# STM32F446_front_pane_-_v3.net
KiCad netlist of a schematic drawn in EAGLE
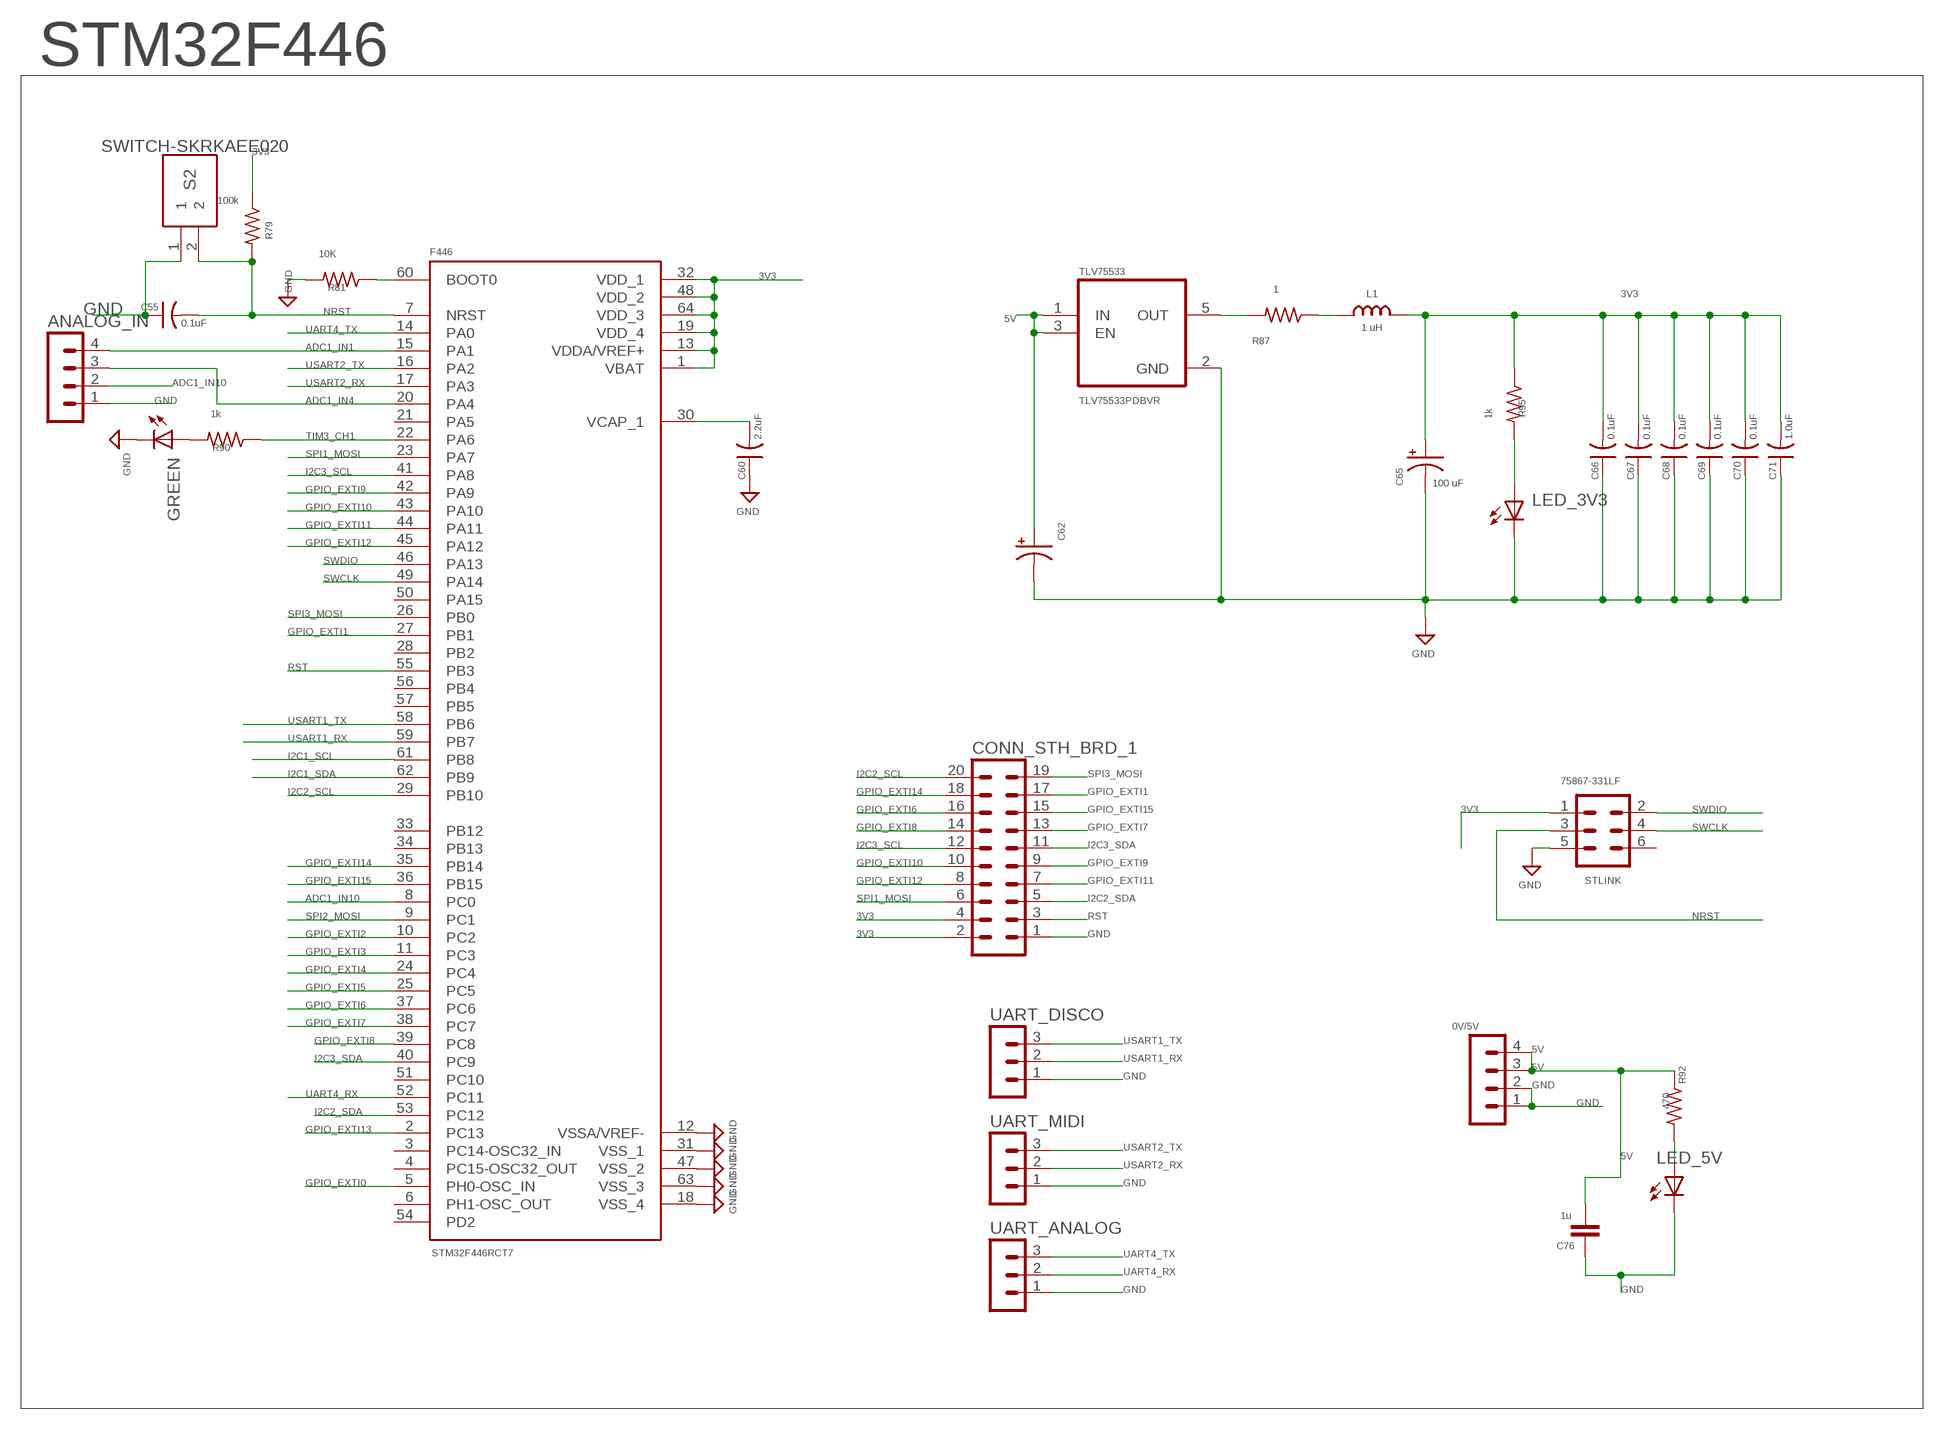
[diagram p0: schematic, sheet 1]
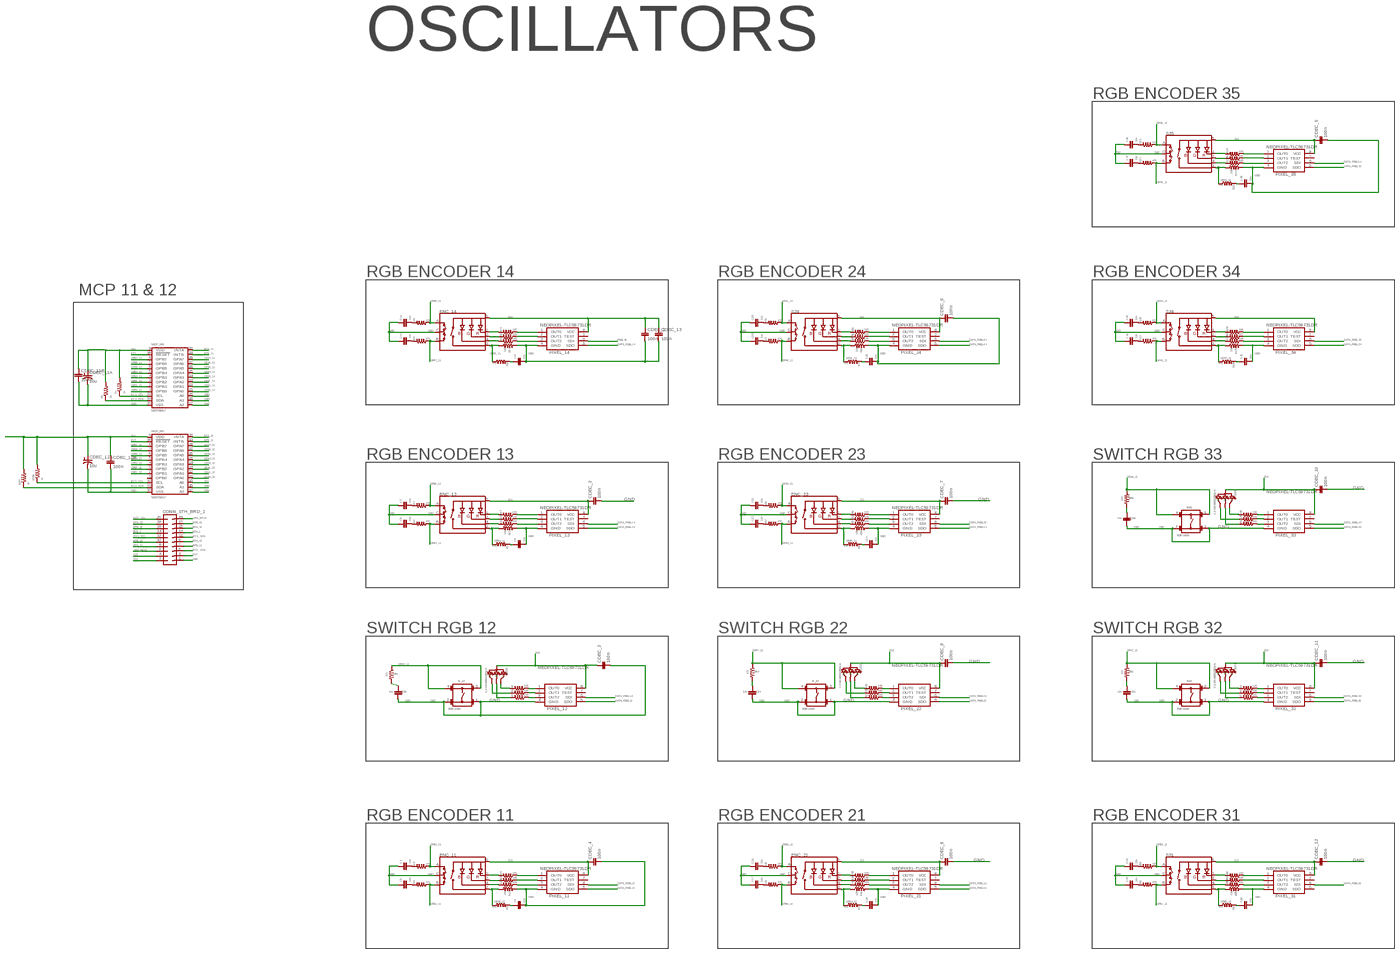
[diagram p1: schematic, sheet 2, overview]
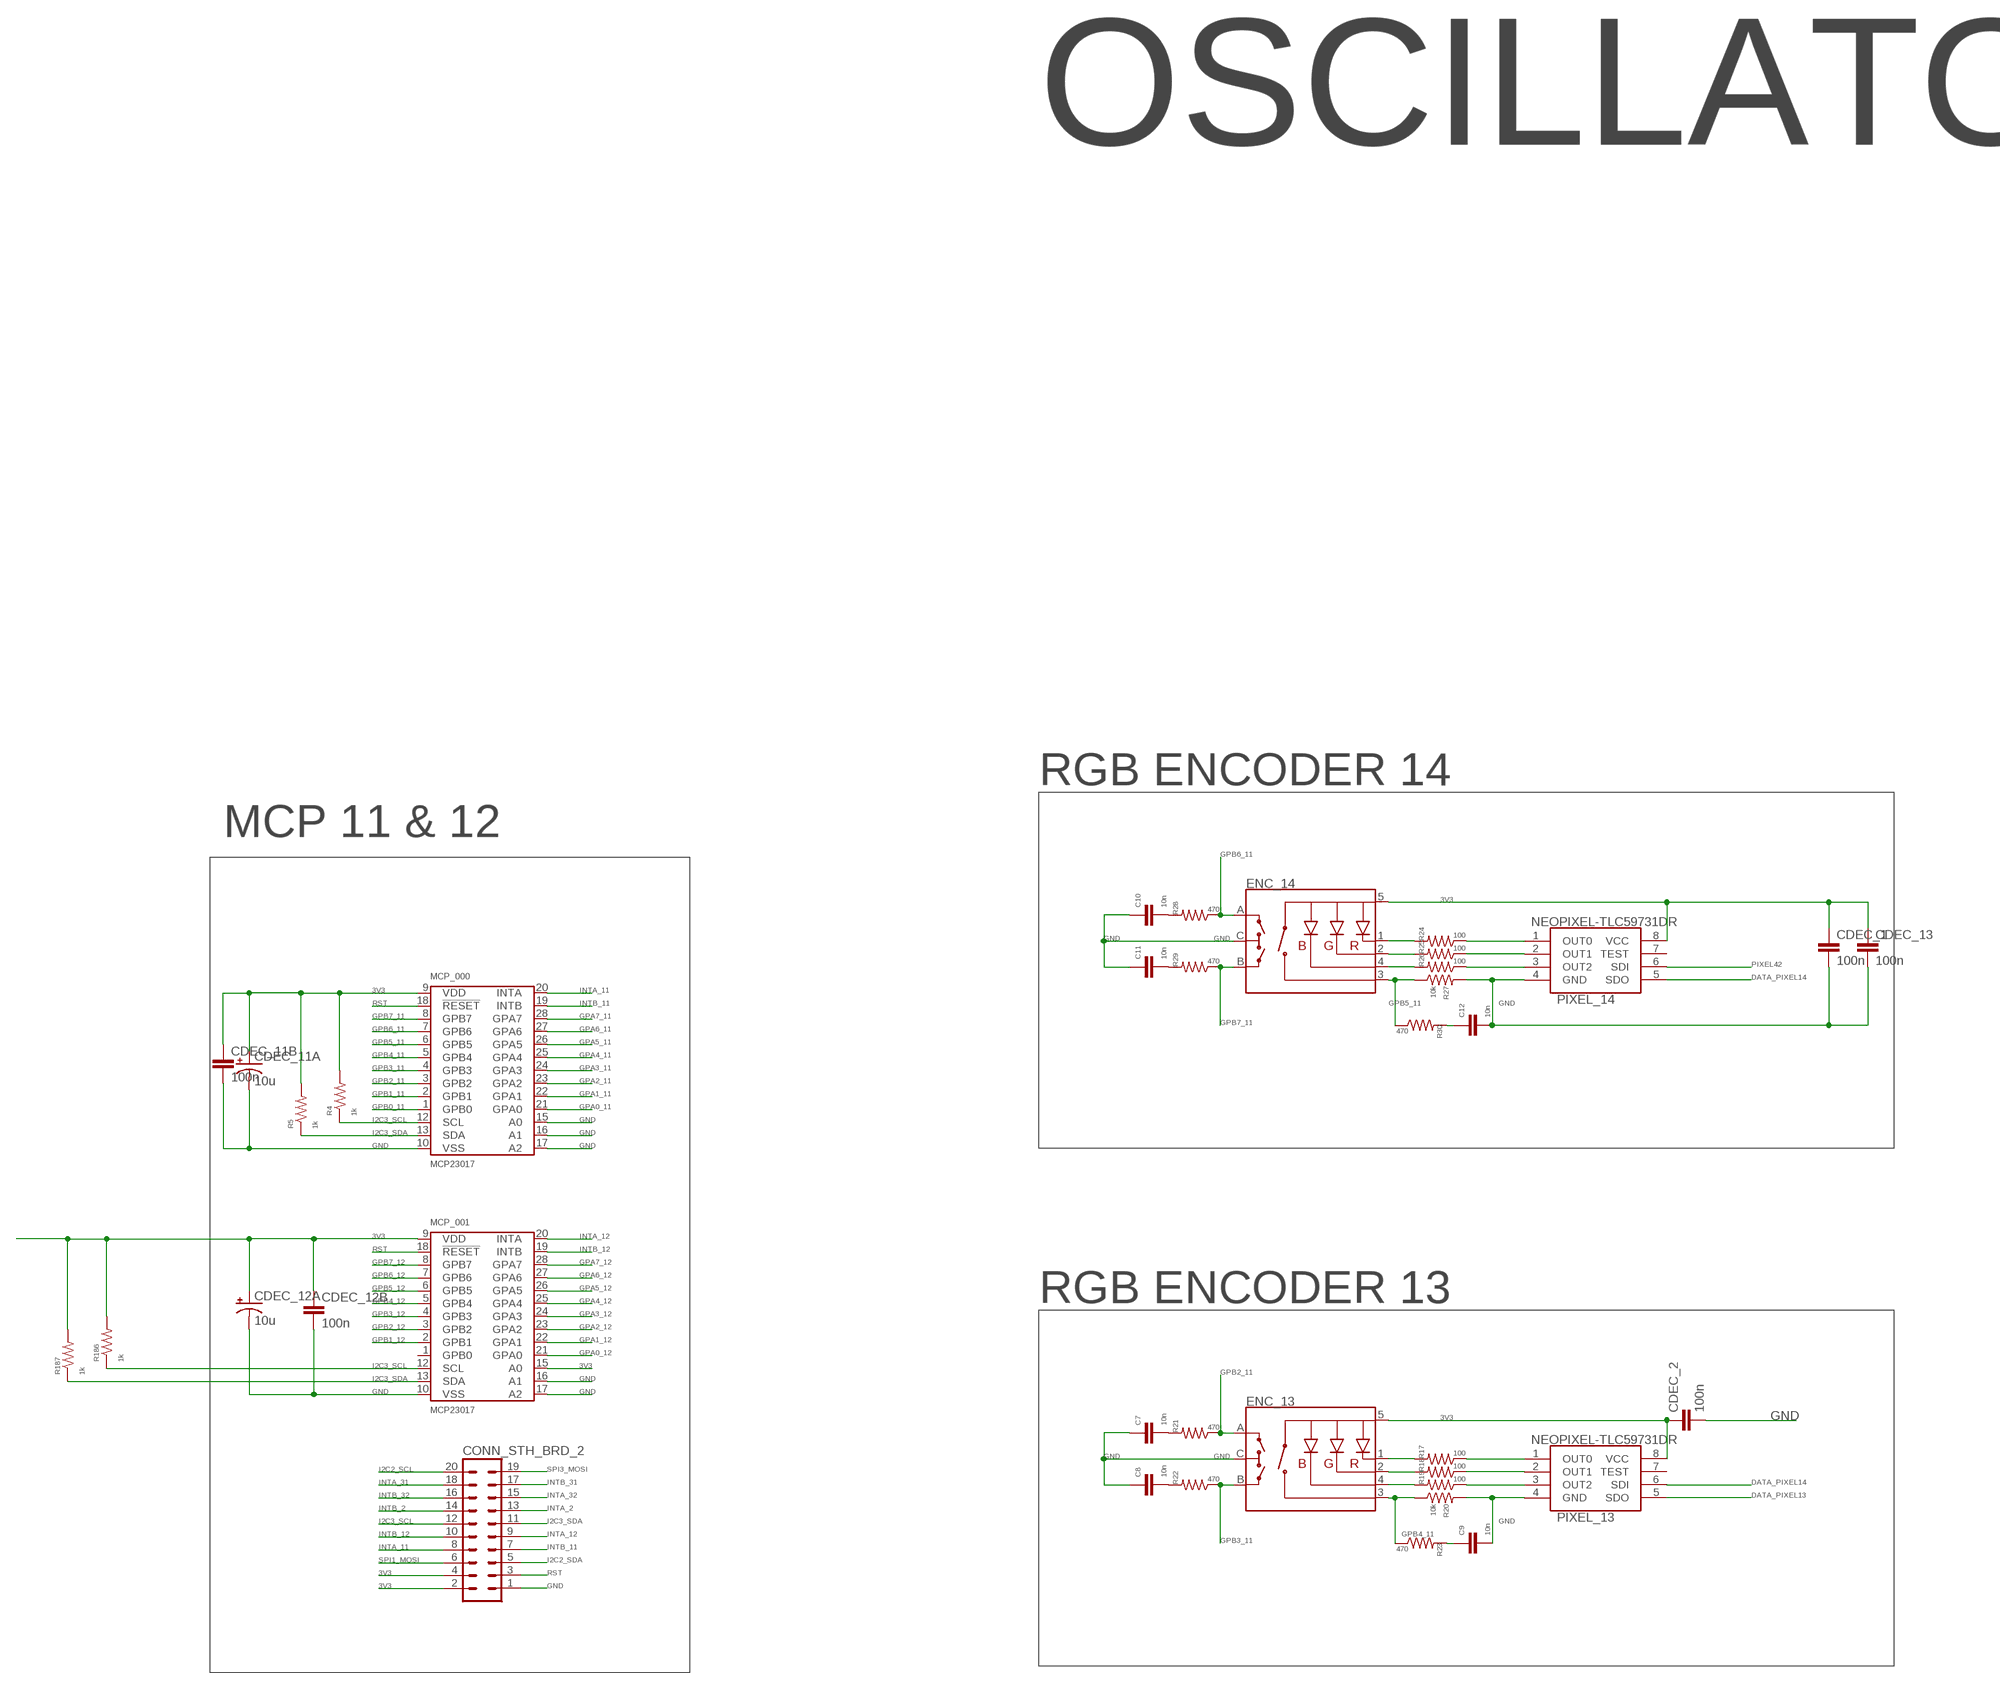
[diagram p2: schematic, sheet 2, part 1 of 4]
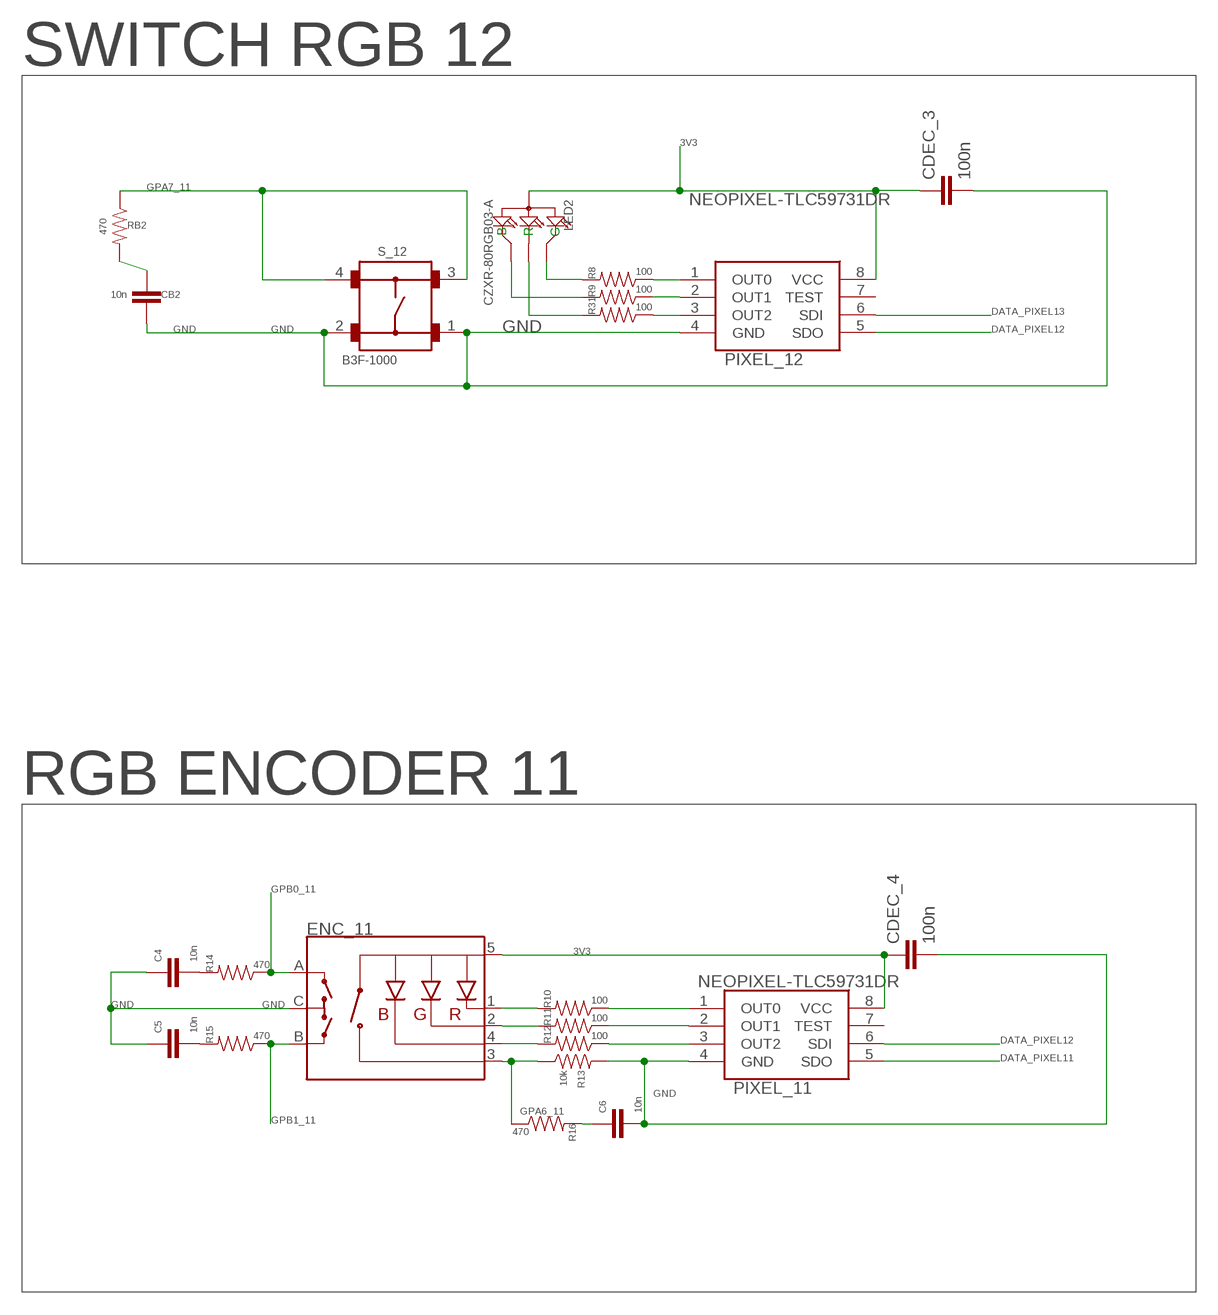
[diagram p3: schematic, sheet 2, part 2 of 4]
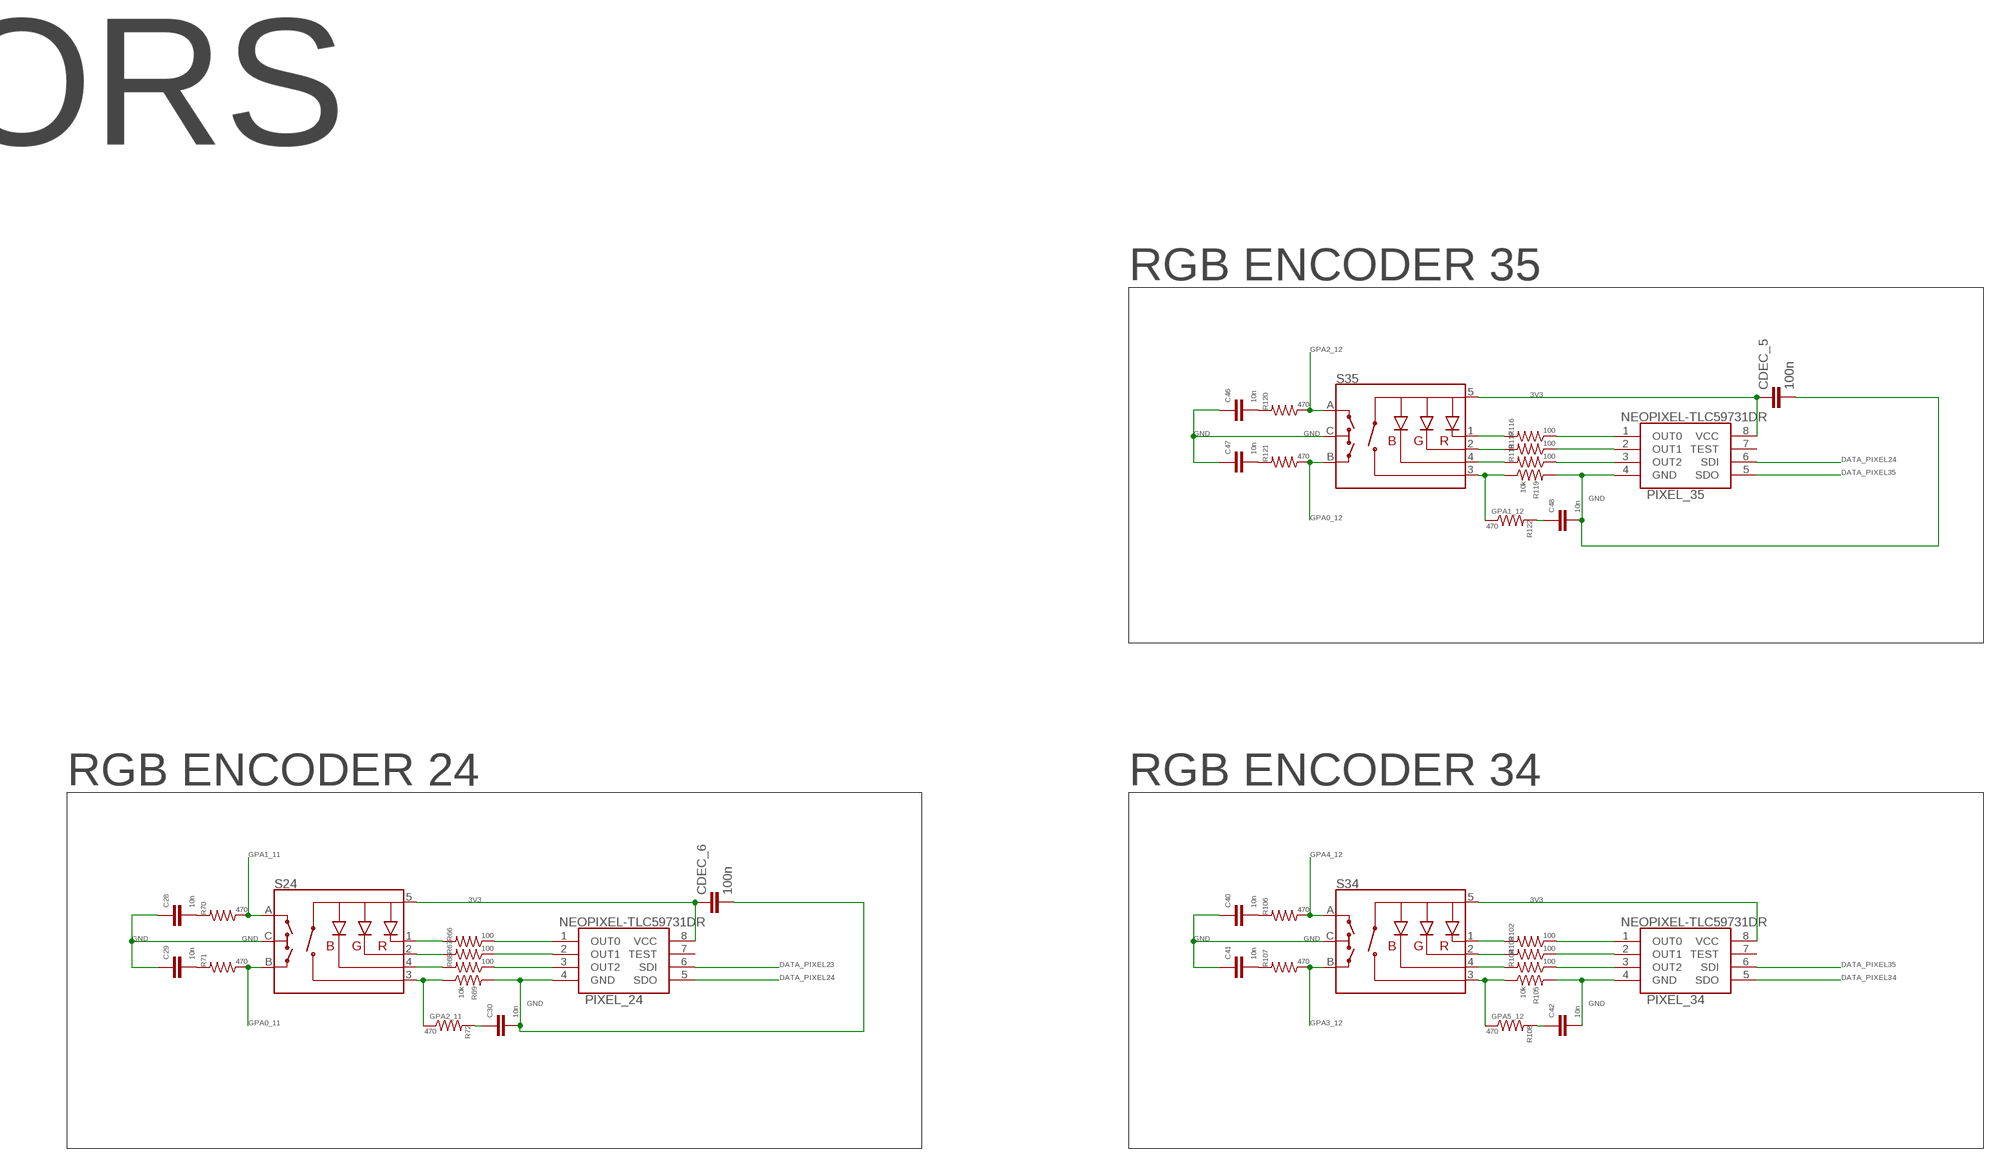
[diagram p4: schematic, sheet 2, part 3 of 4]
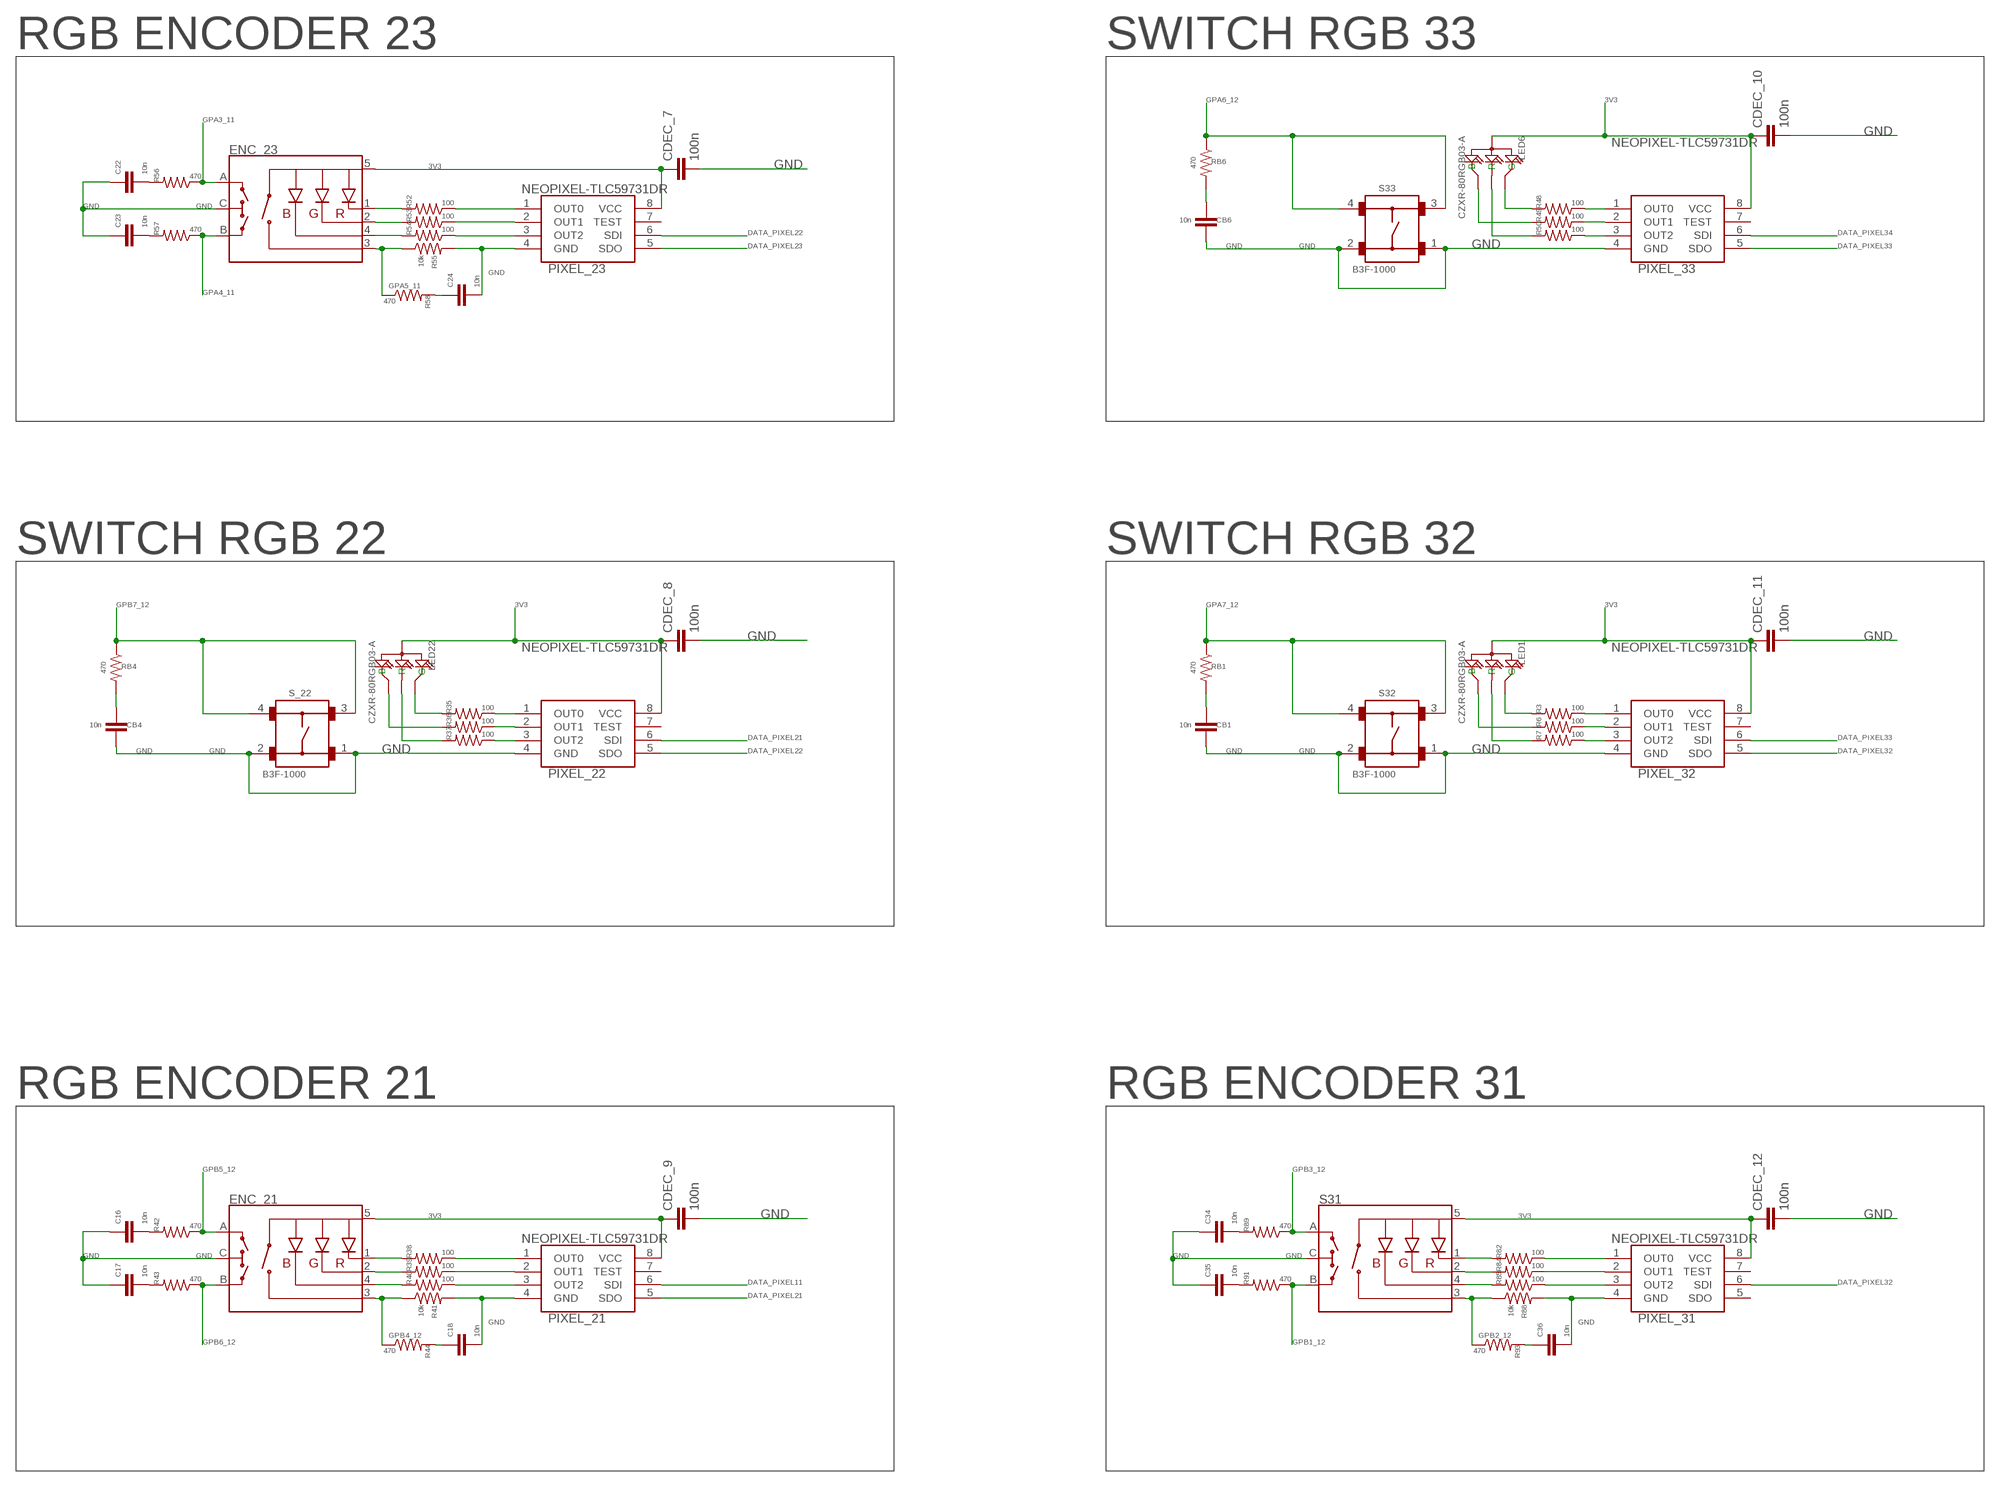
[diagram p5: schematic, sheet 2, part 4 of 4]
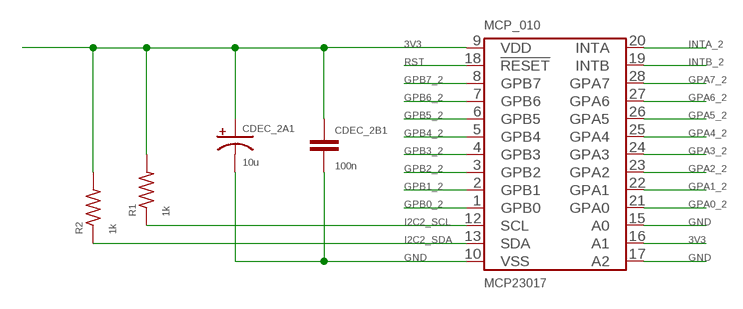
[diagram p6: schematic, sheet 3, part 1 of 2]
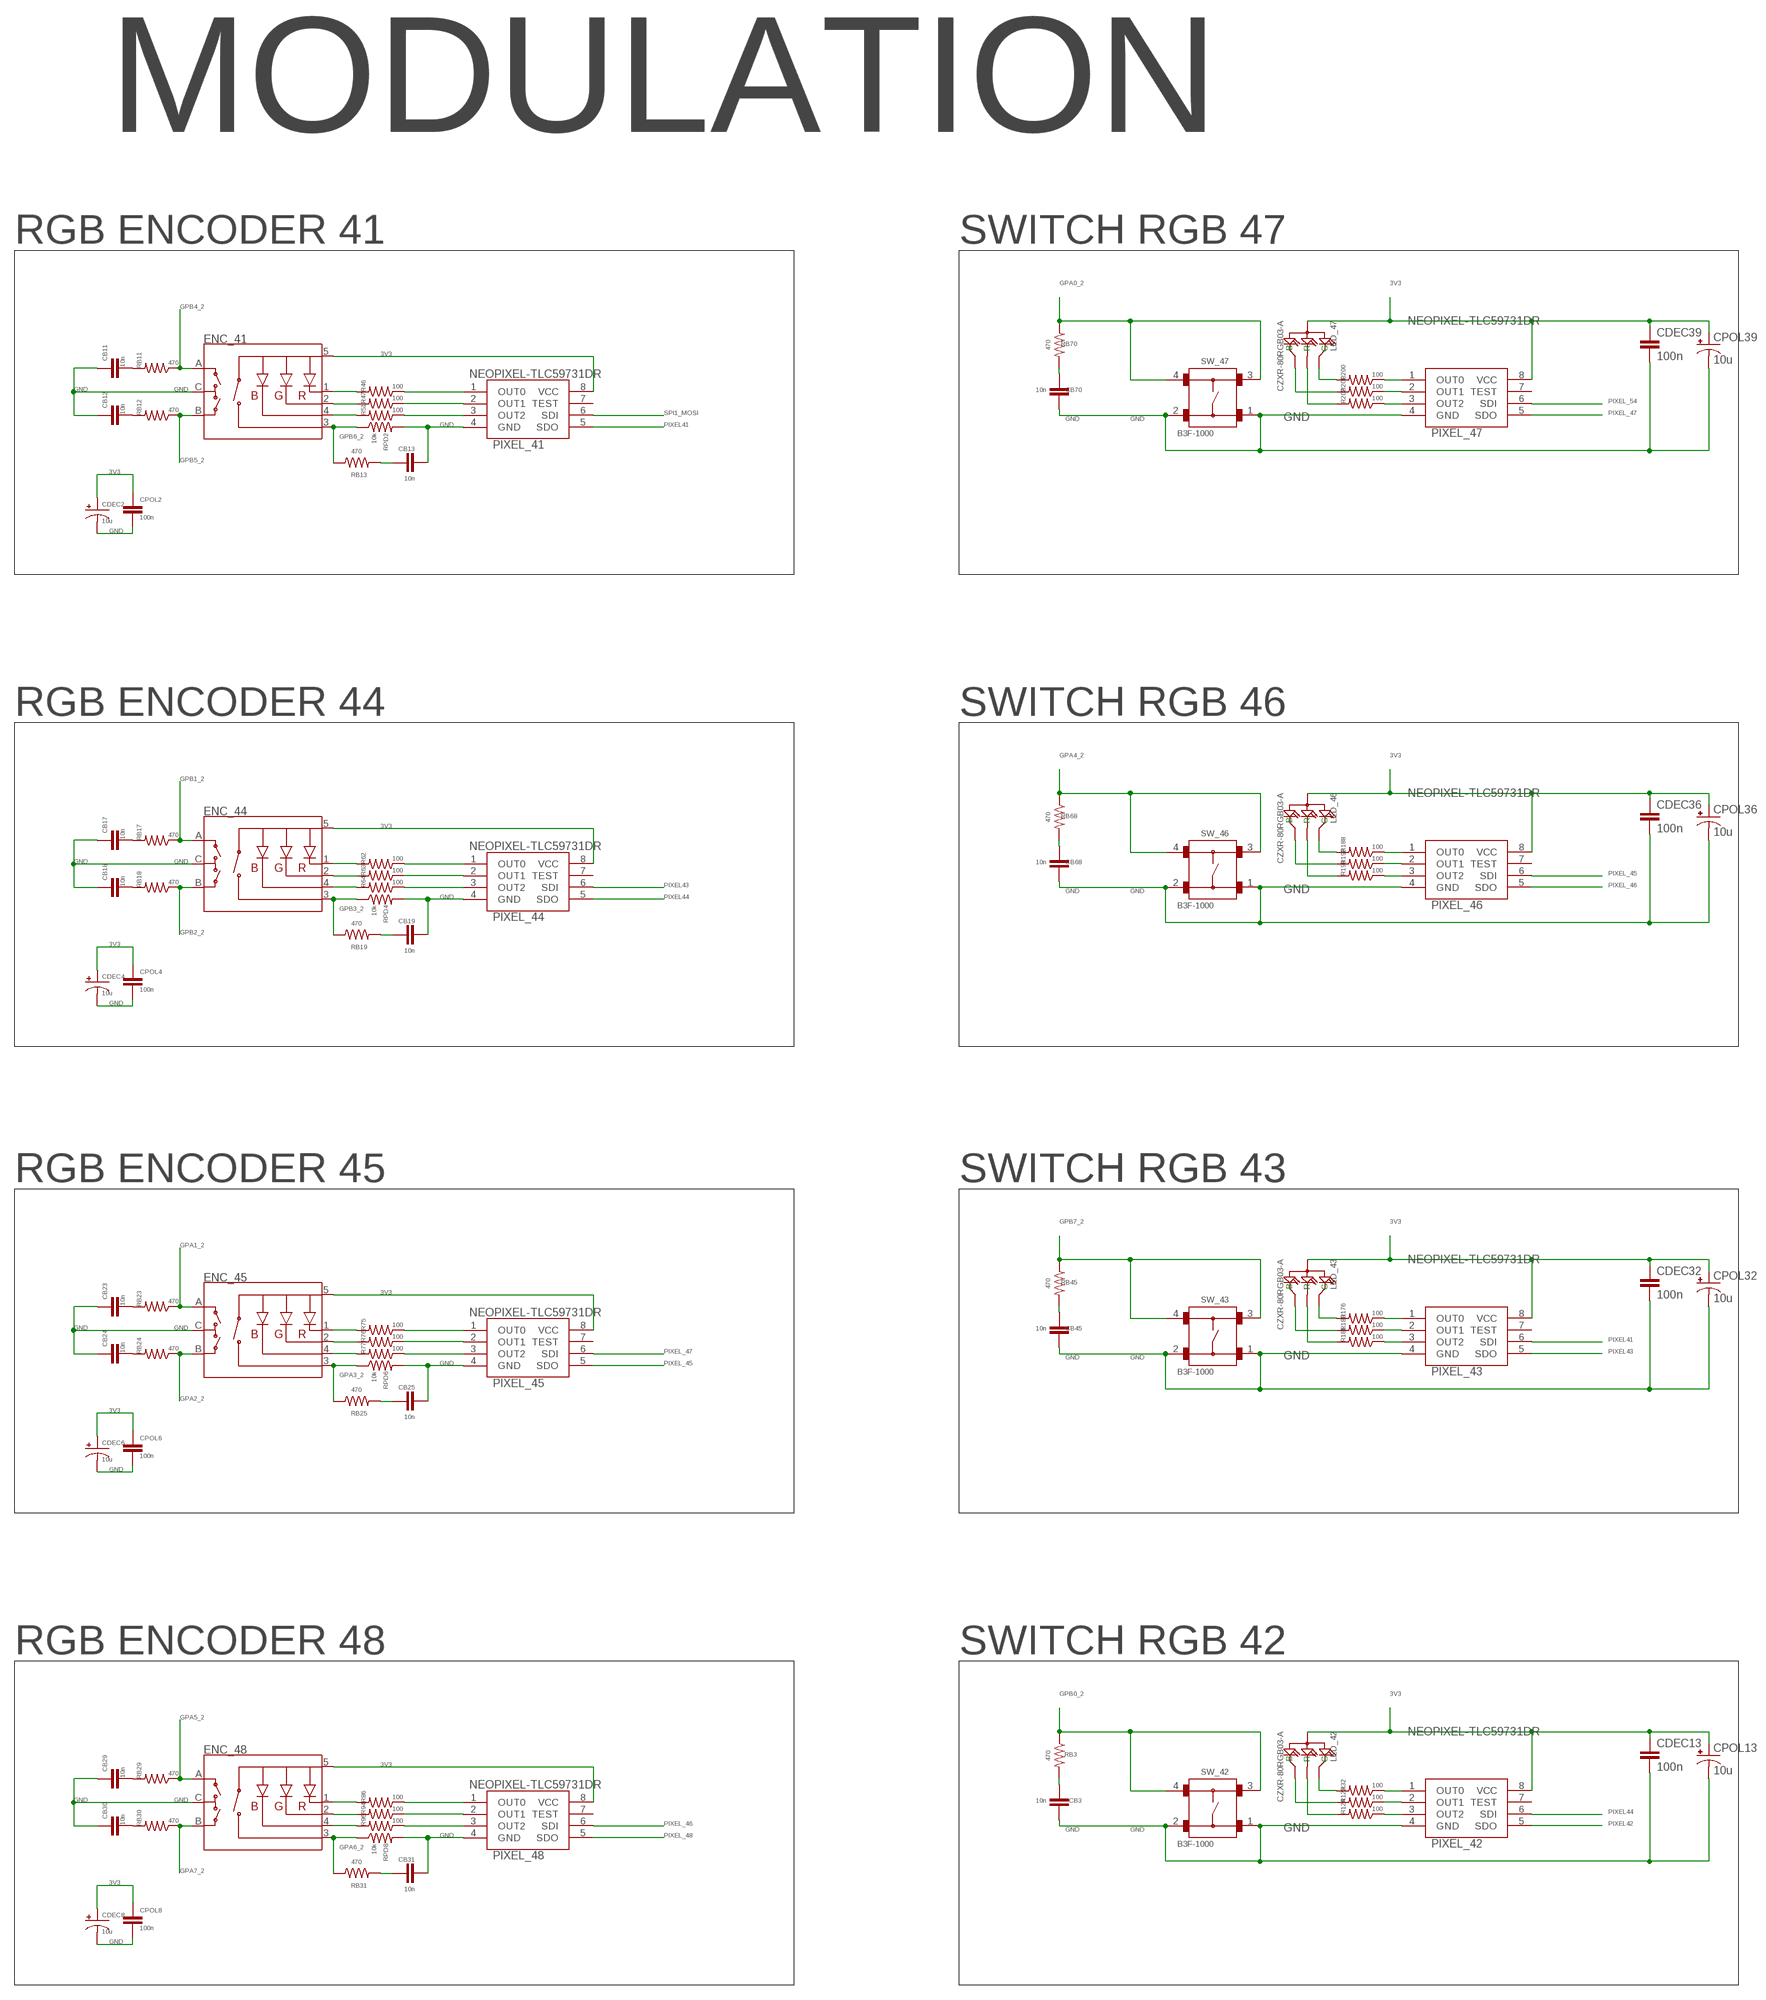
[diagram p7: schematic, sheet 3, part 2 of 2]
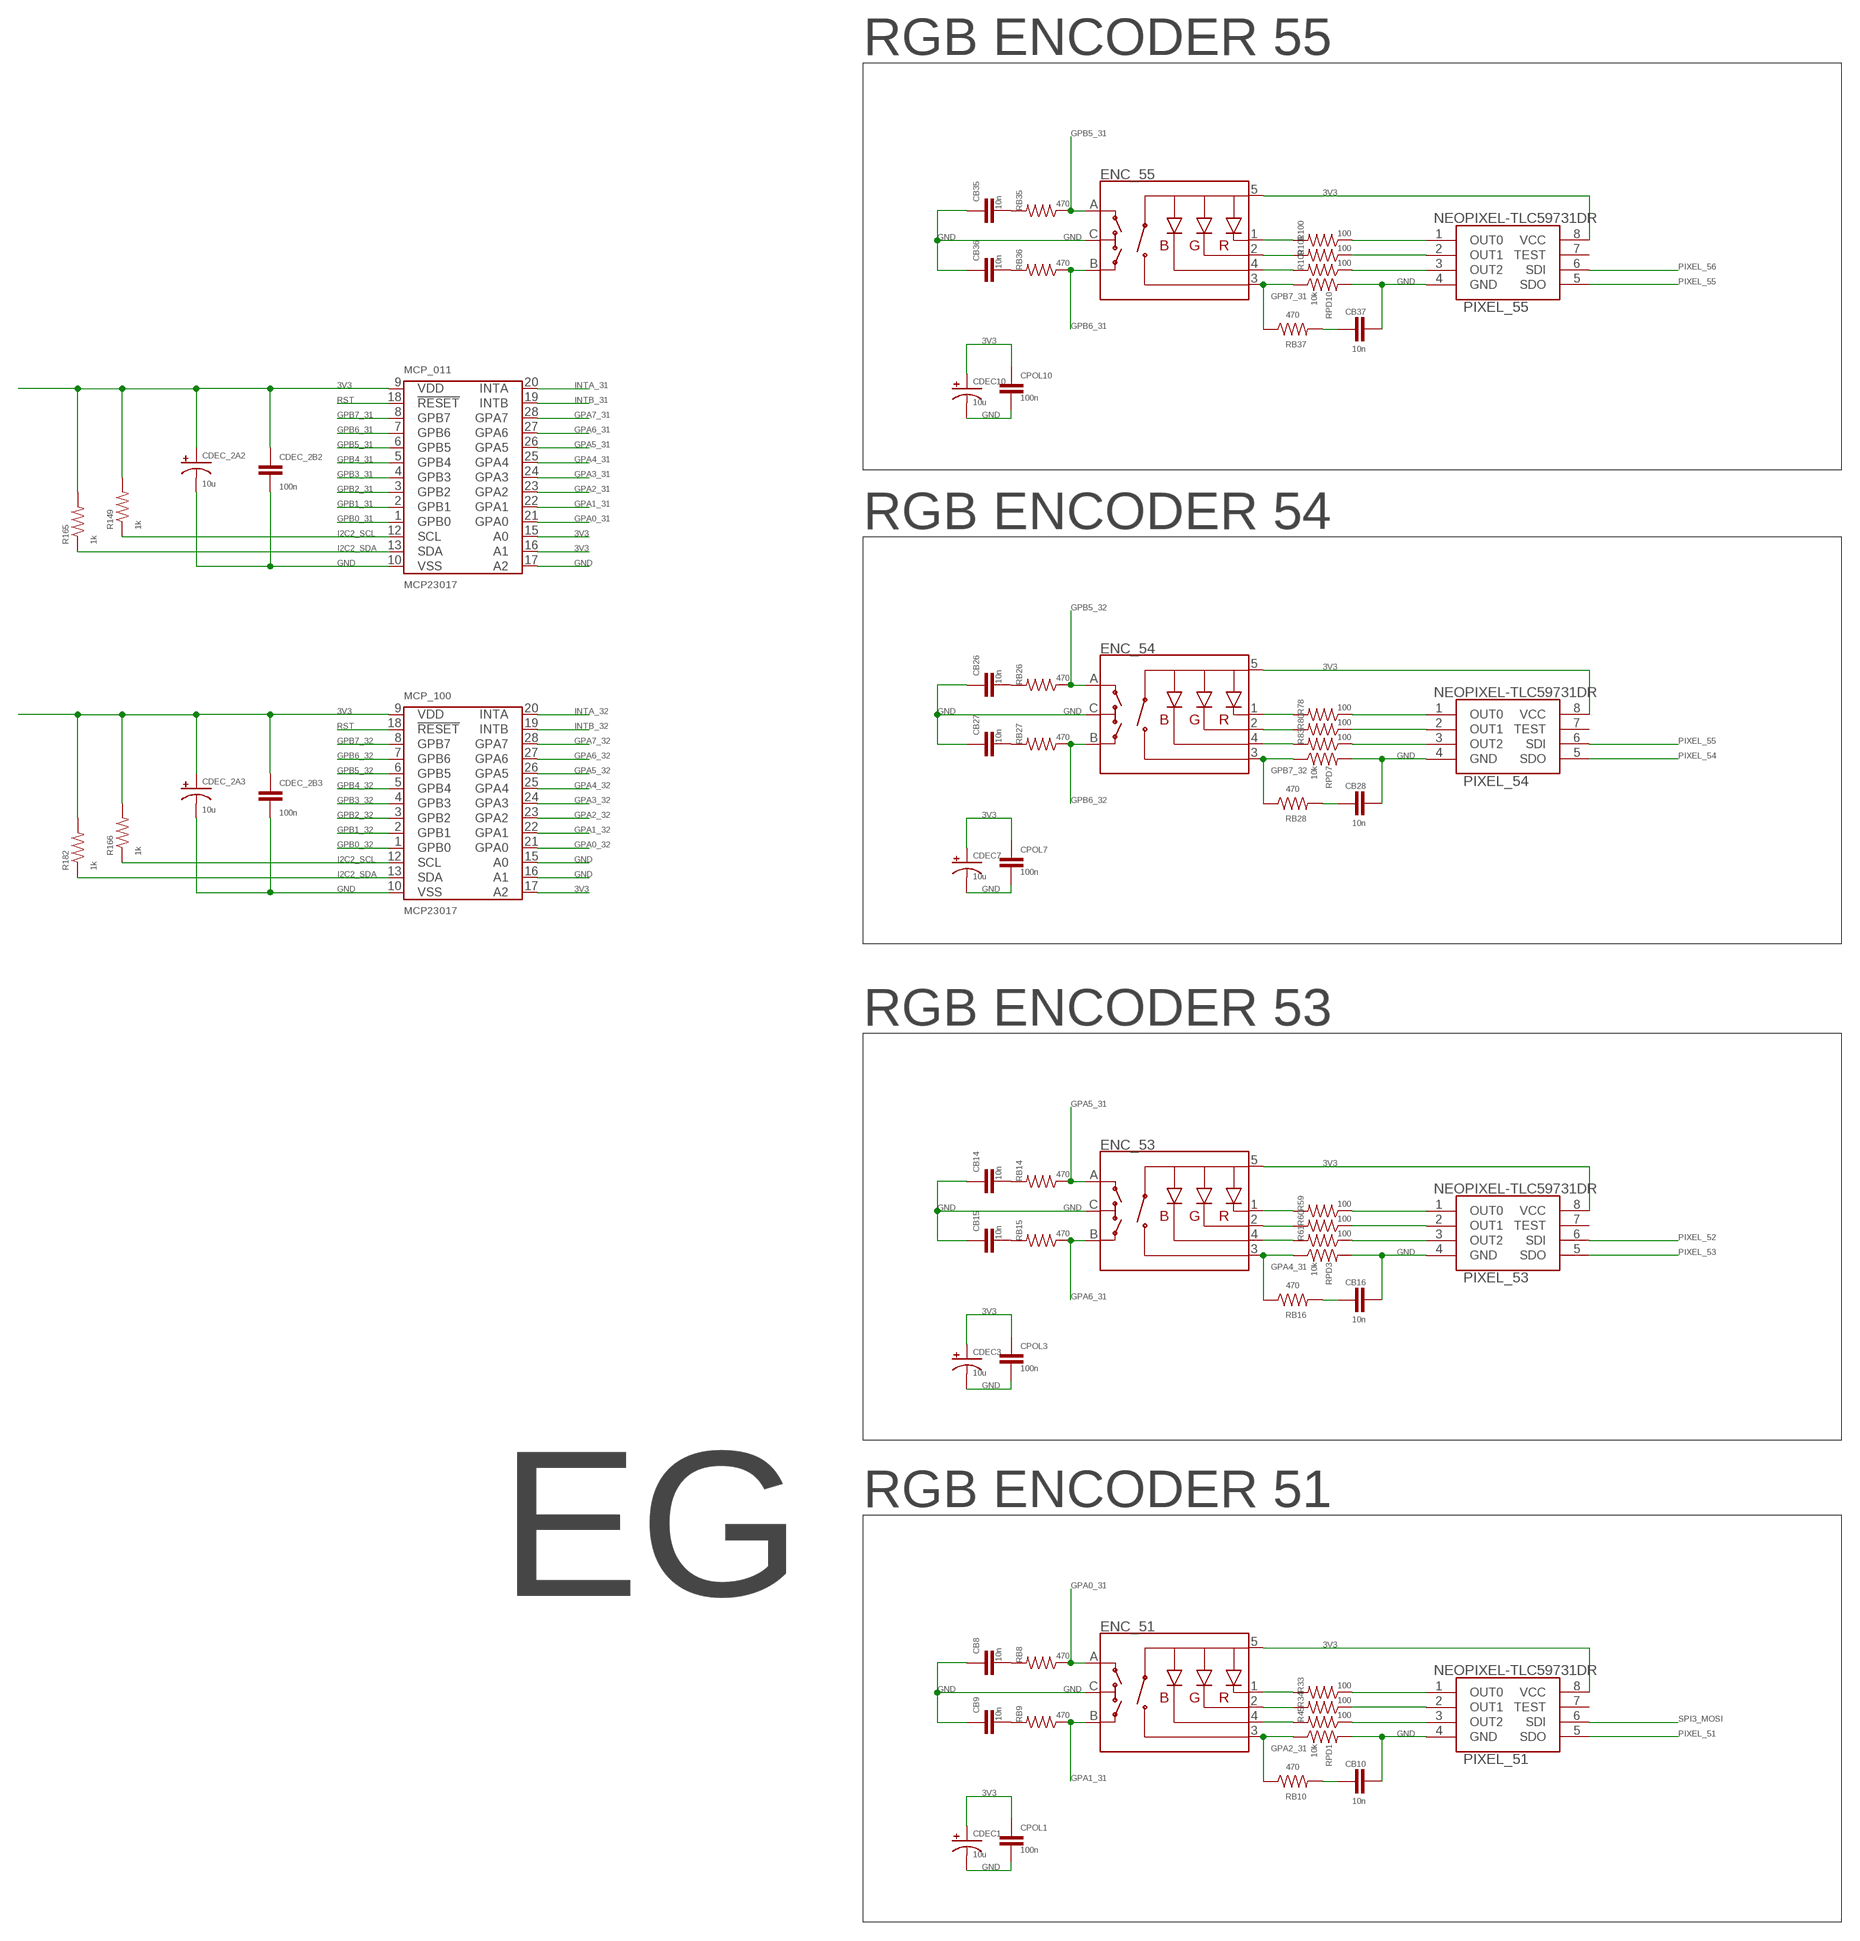
[diagram p8: schematic, sheet 4, part 1 of 2]
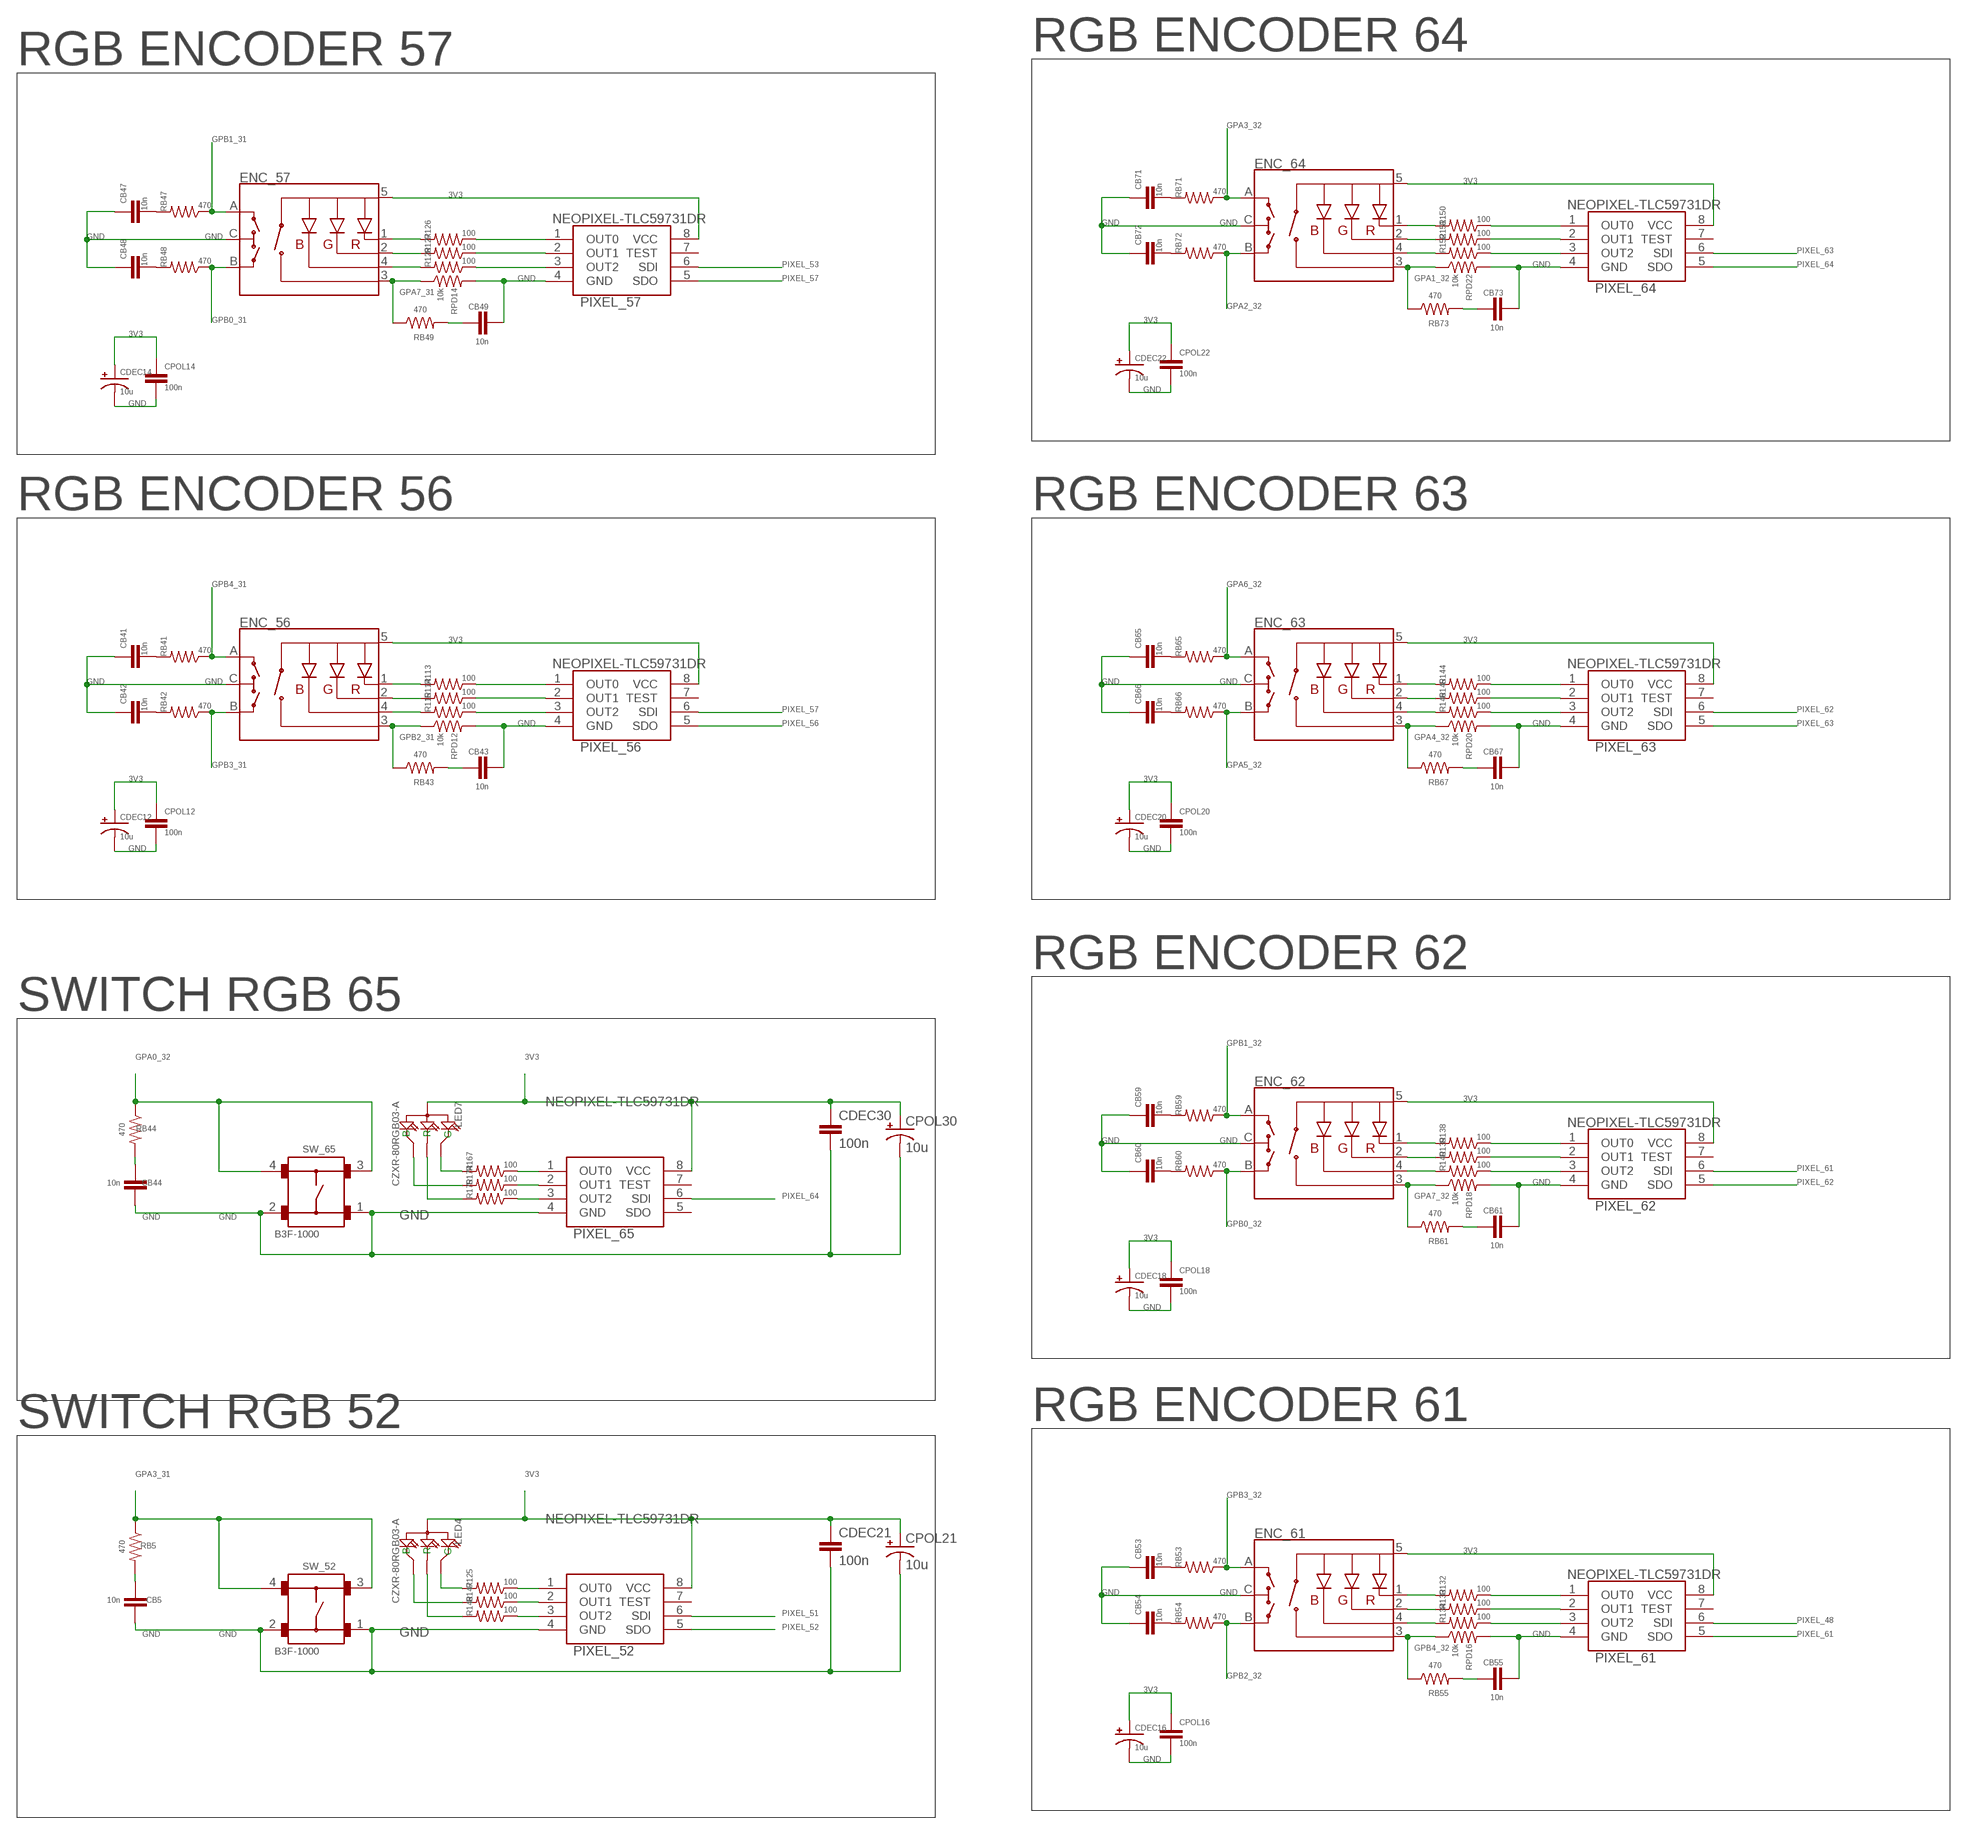
[diagram p9: schematic, sheet 4, part 2 of 2]
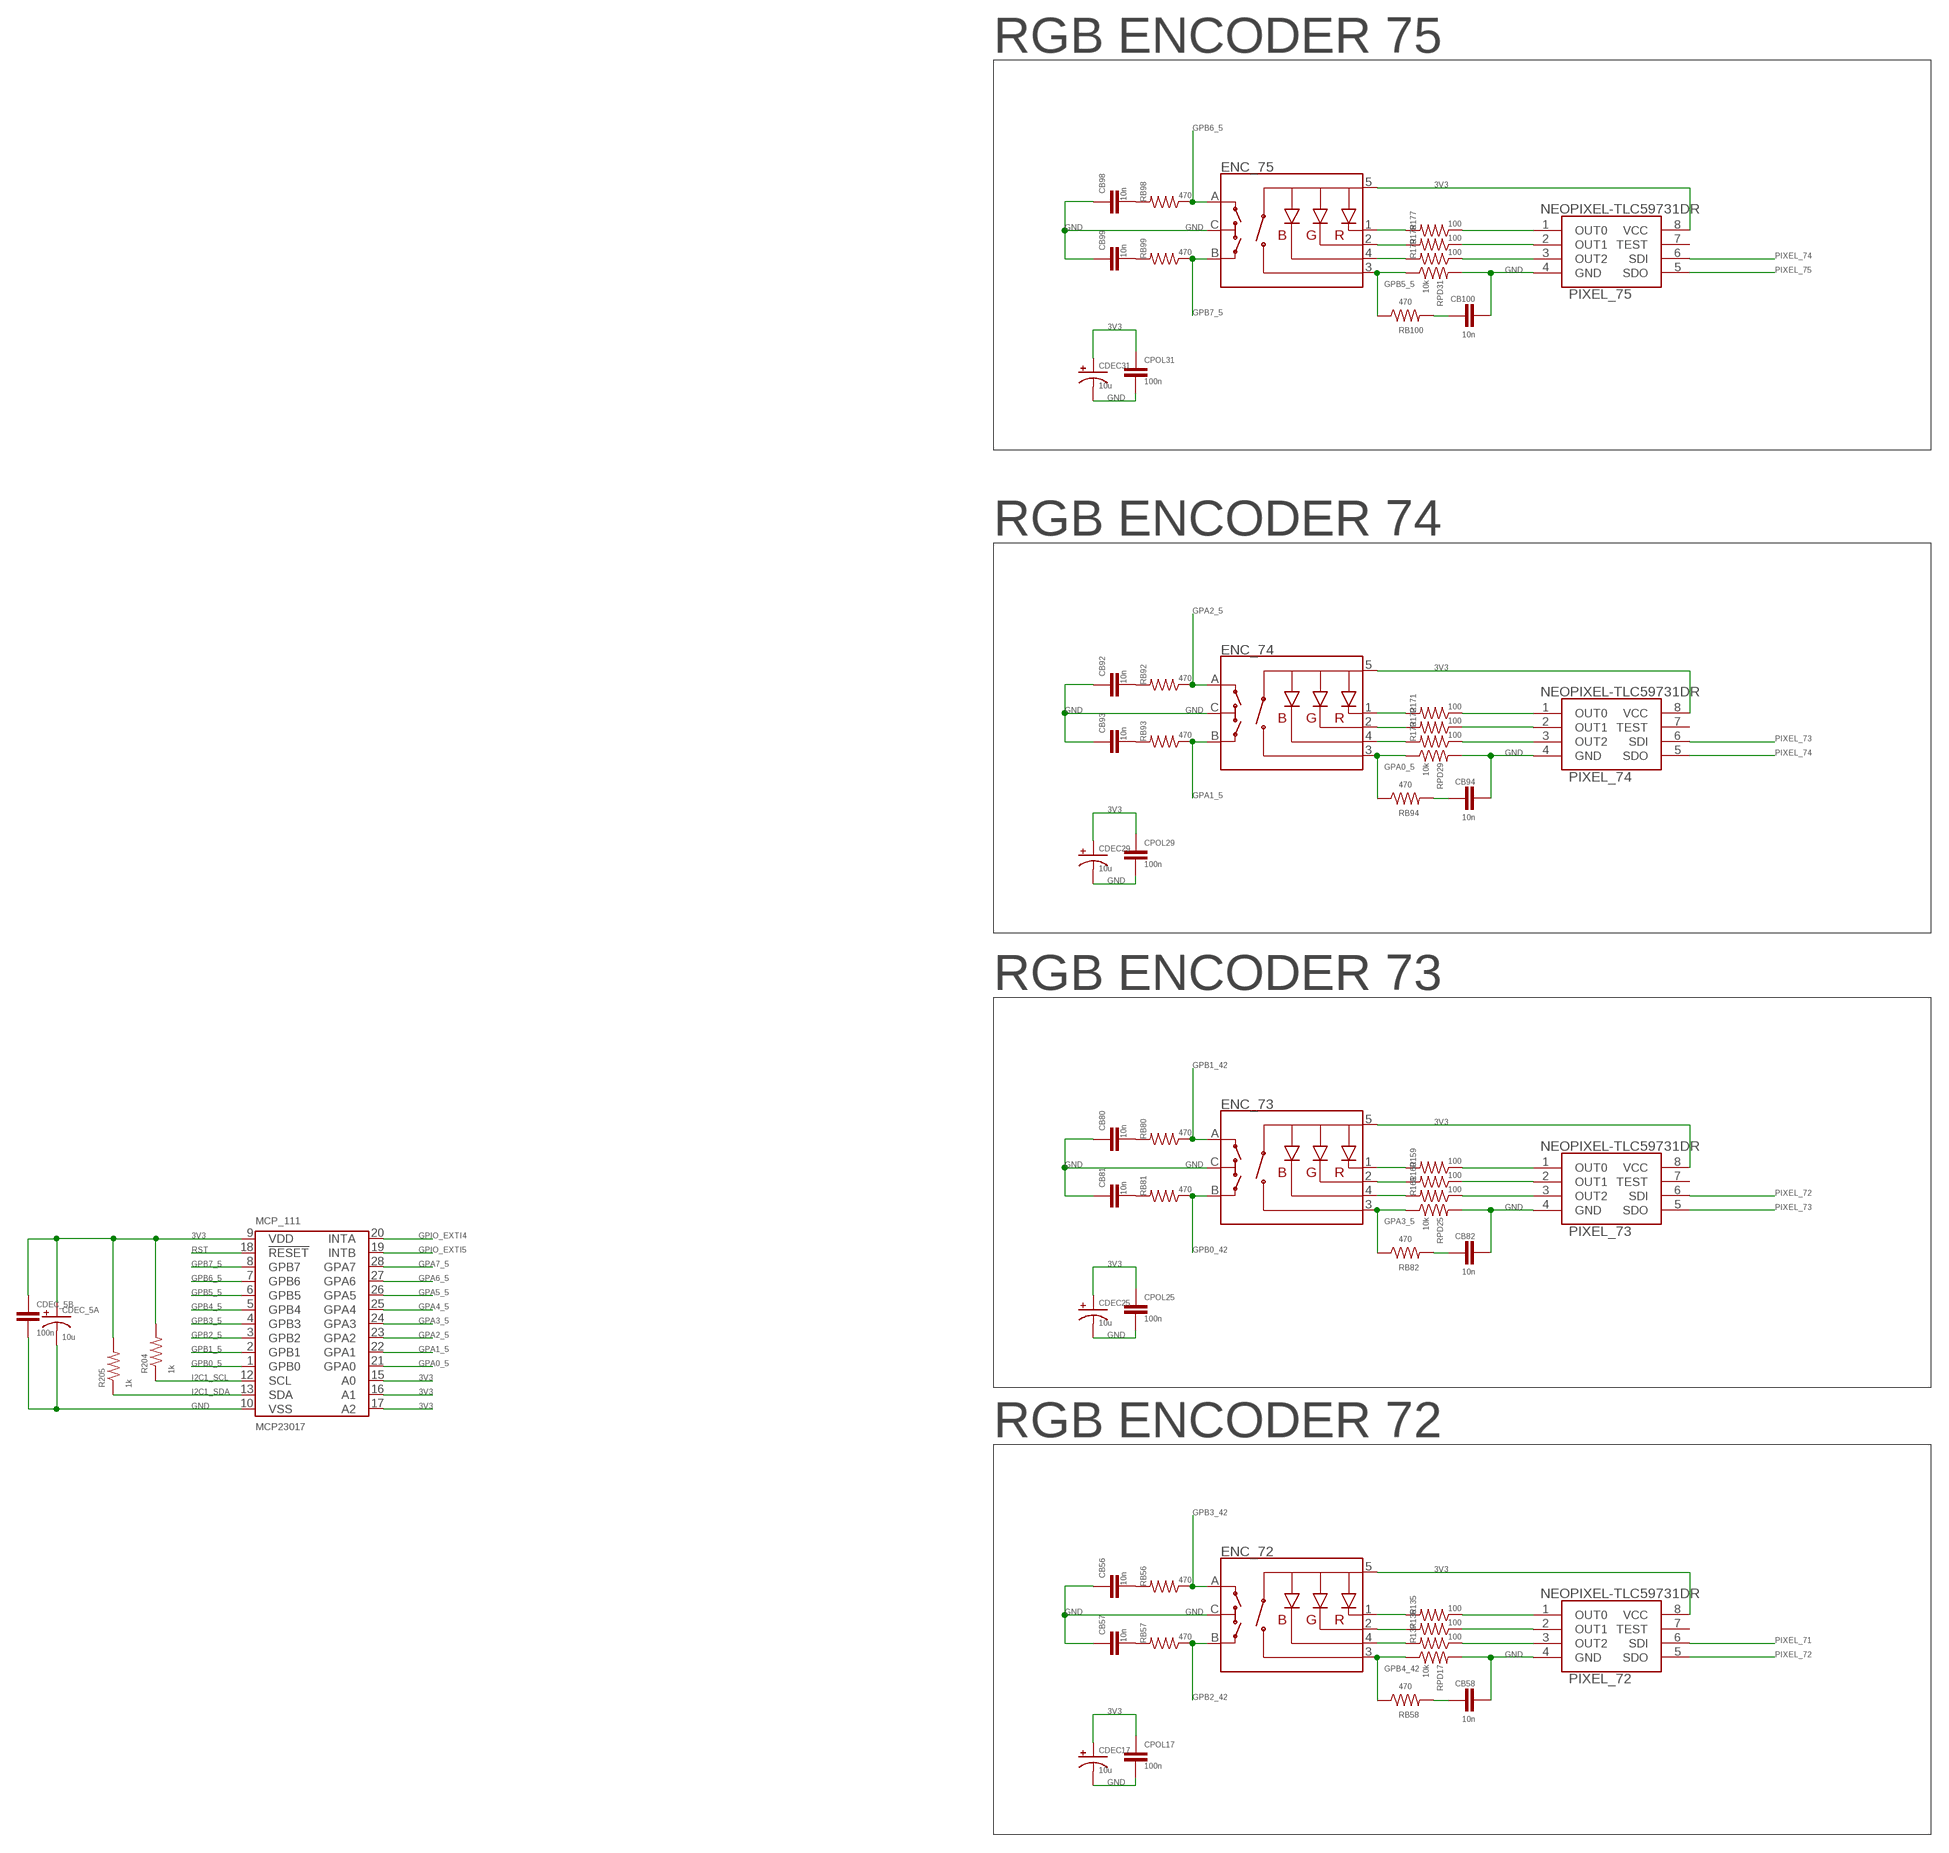
[diagram p10: schematic, sheet 5, part 1 of 2]
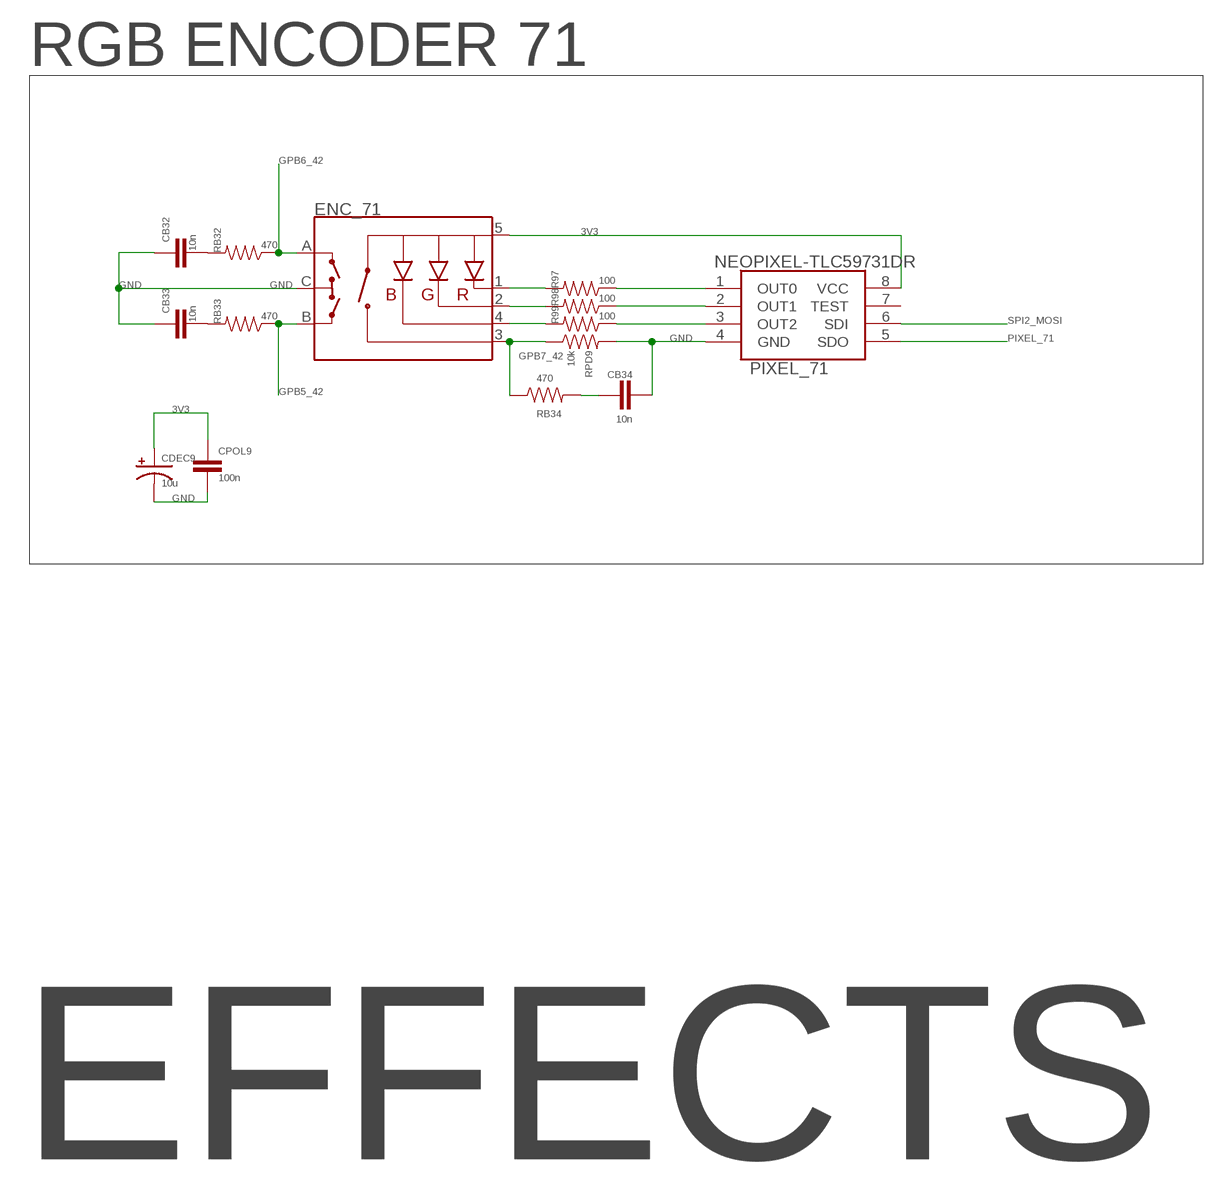
[diagram p11: schematic, sheet 5, part 2 of 2]
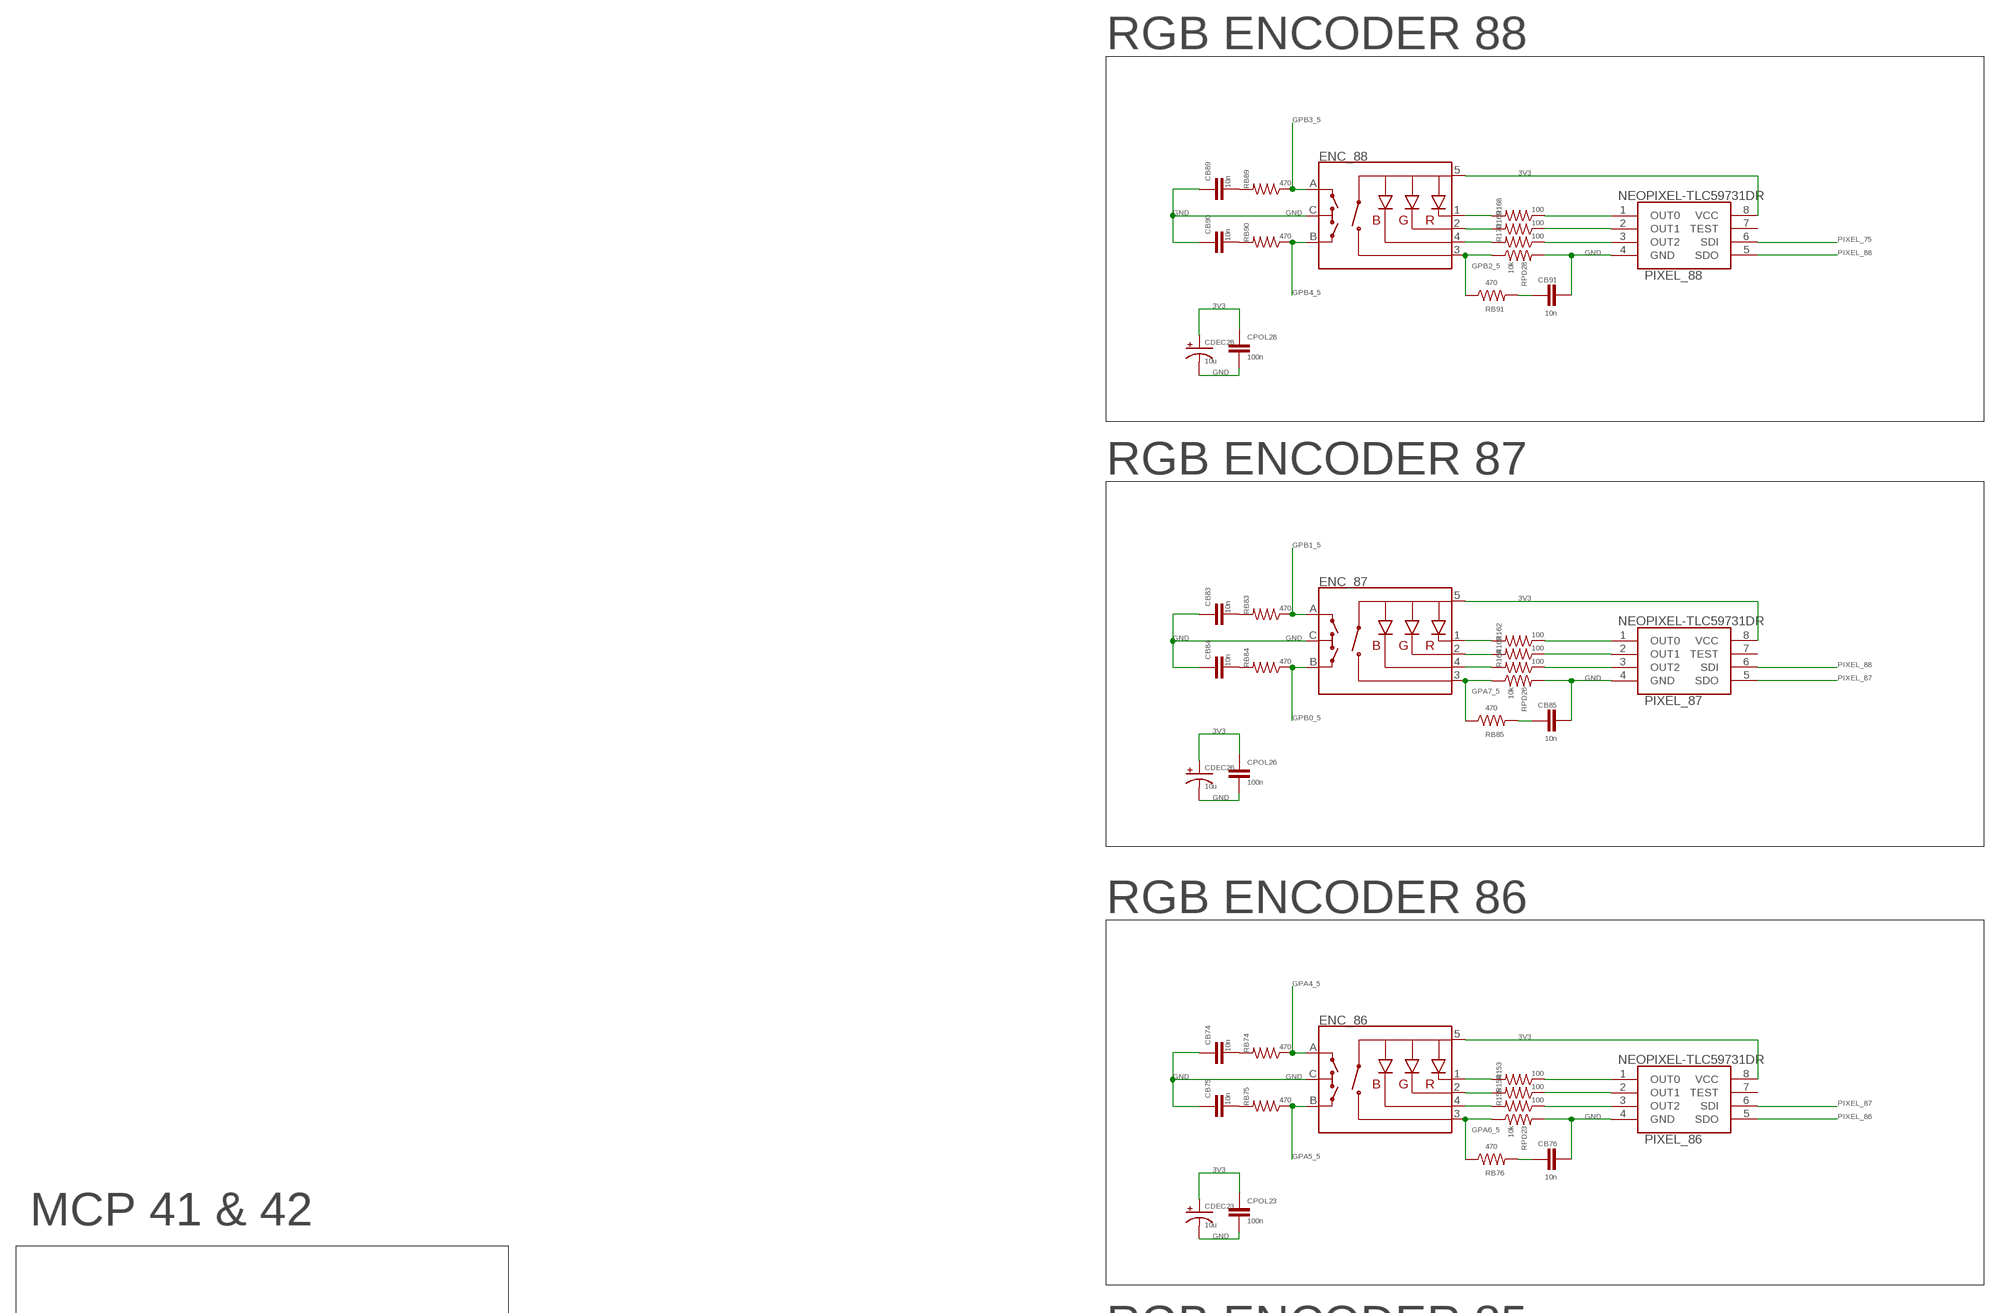
[diagram p12: schematic, sheet 6, part 1 of 2]
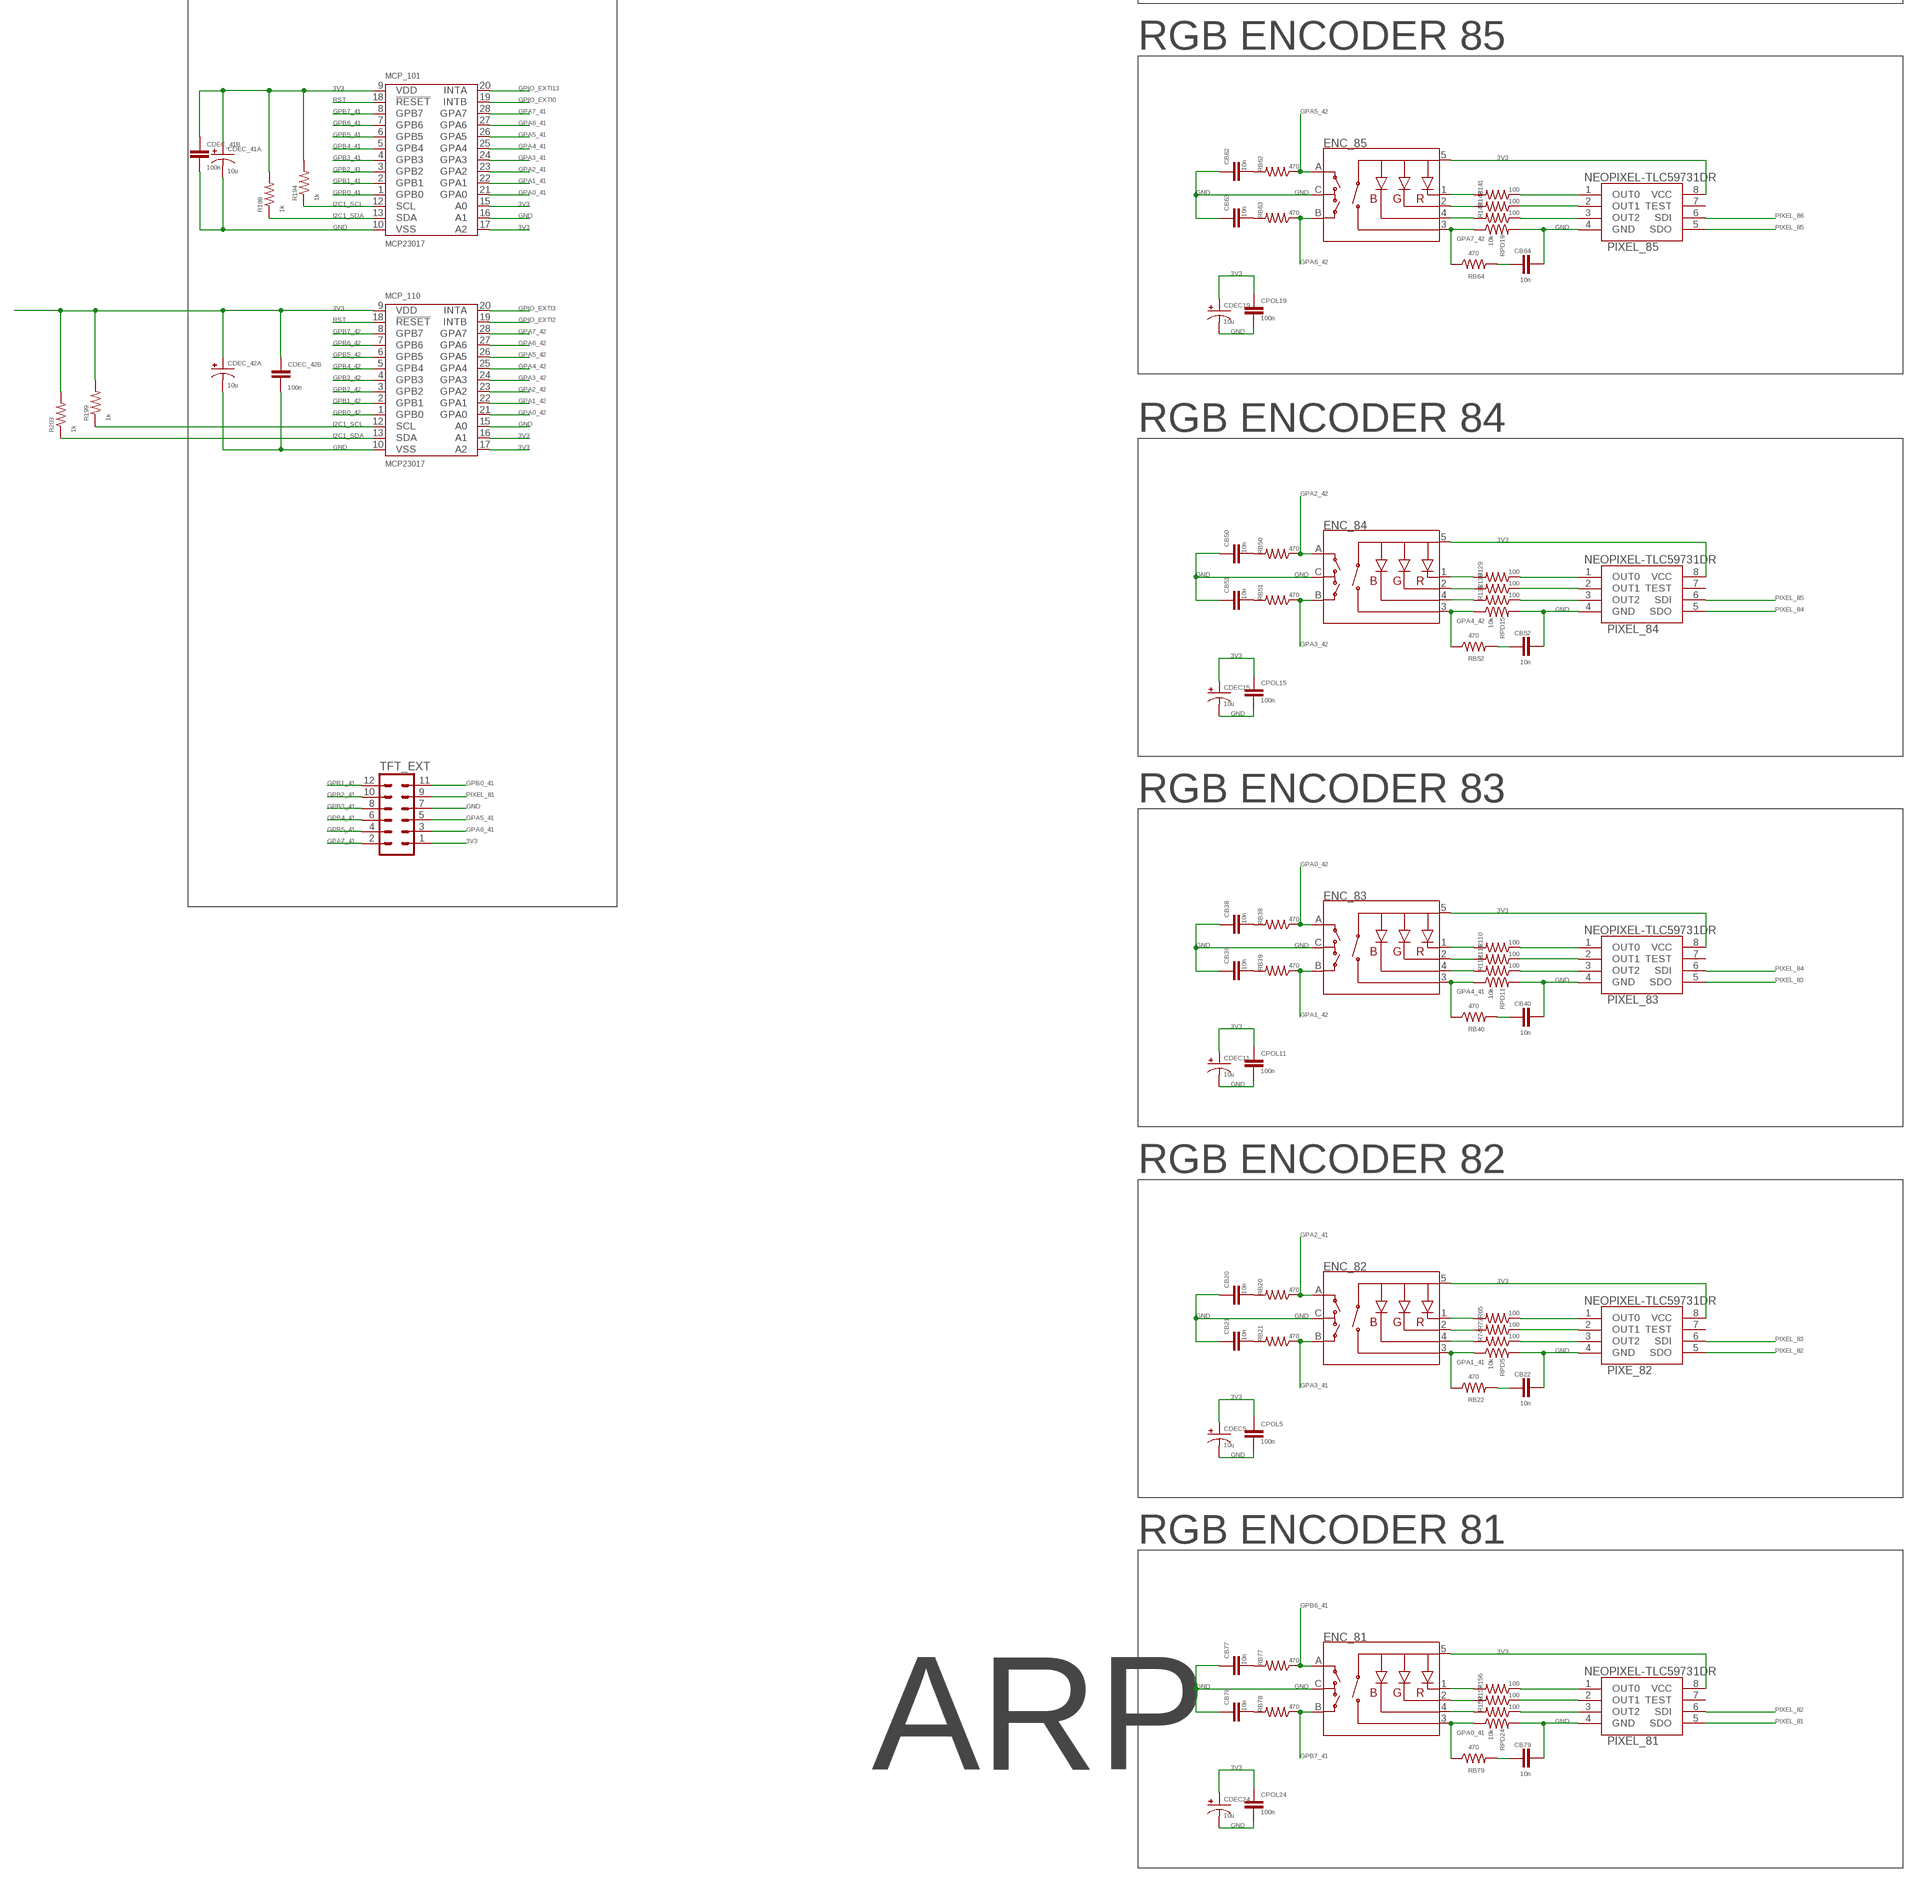
[diagram p13: schematic, sheet 6, part 2 of 2]
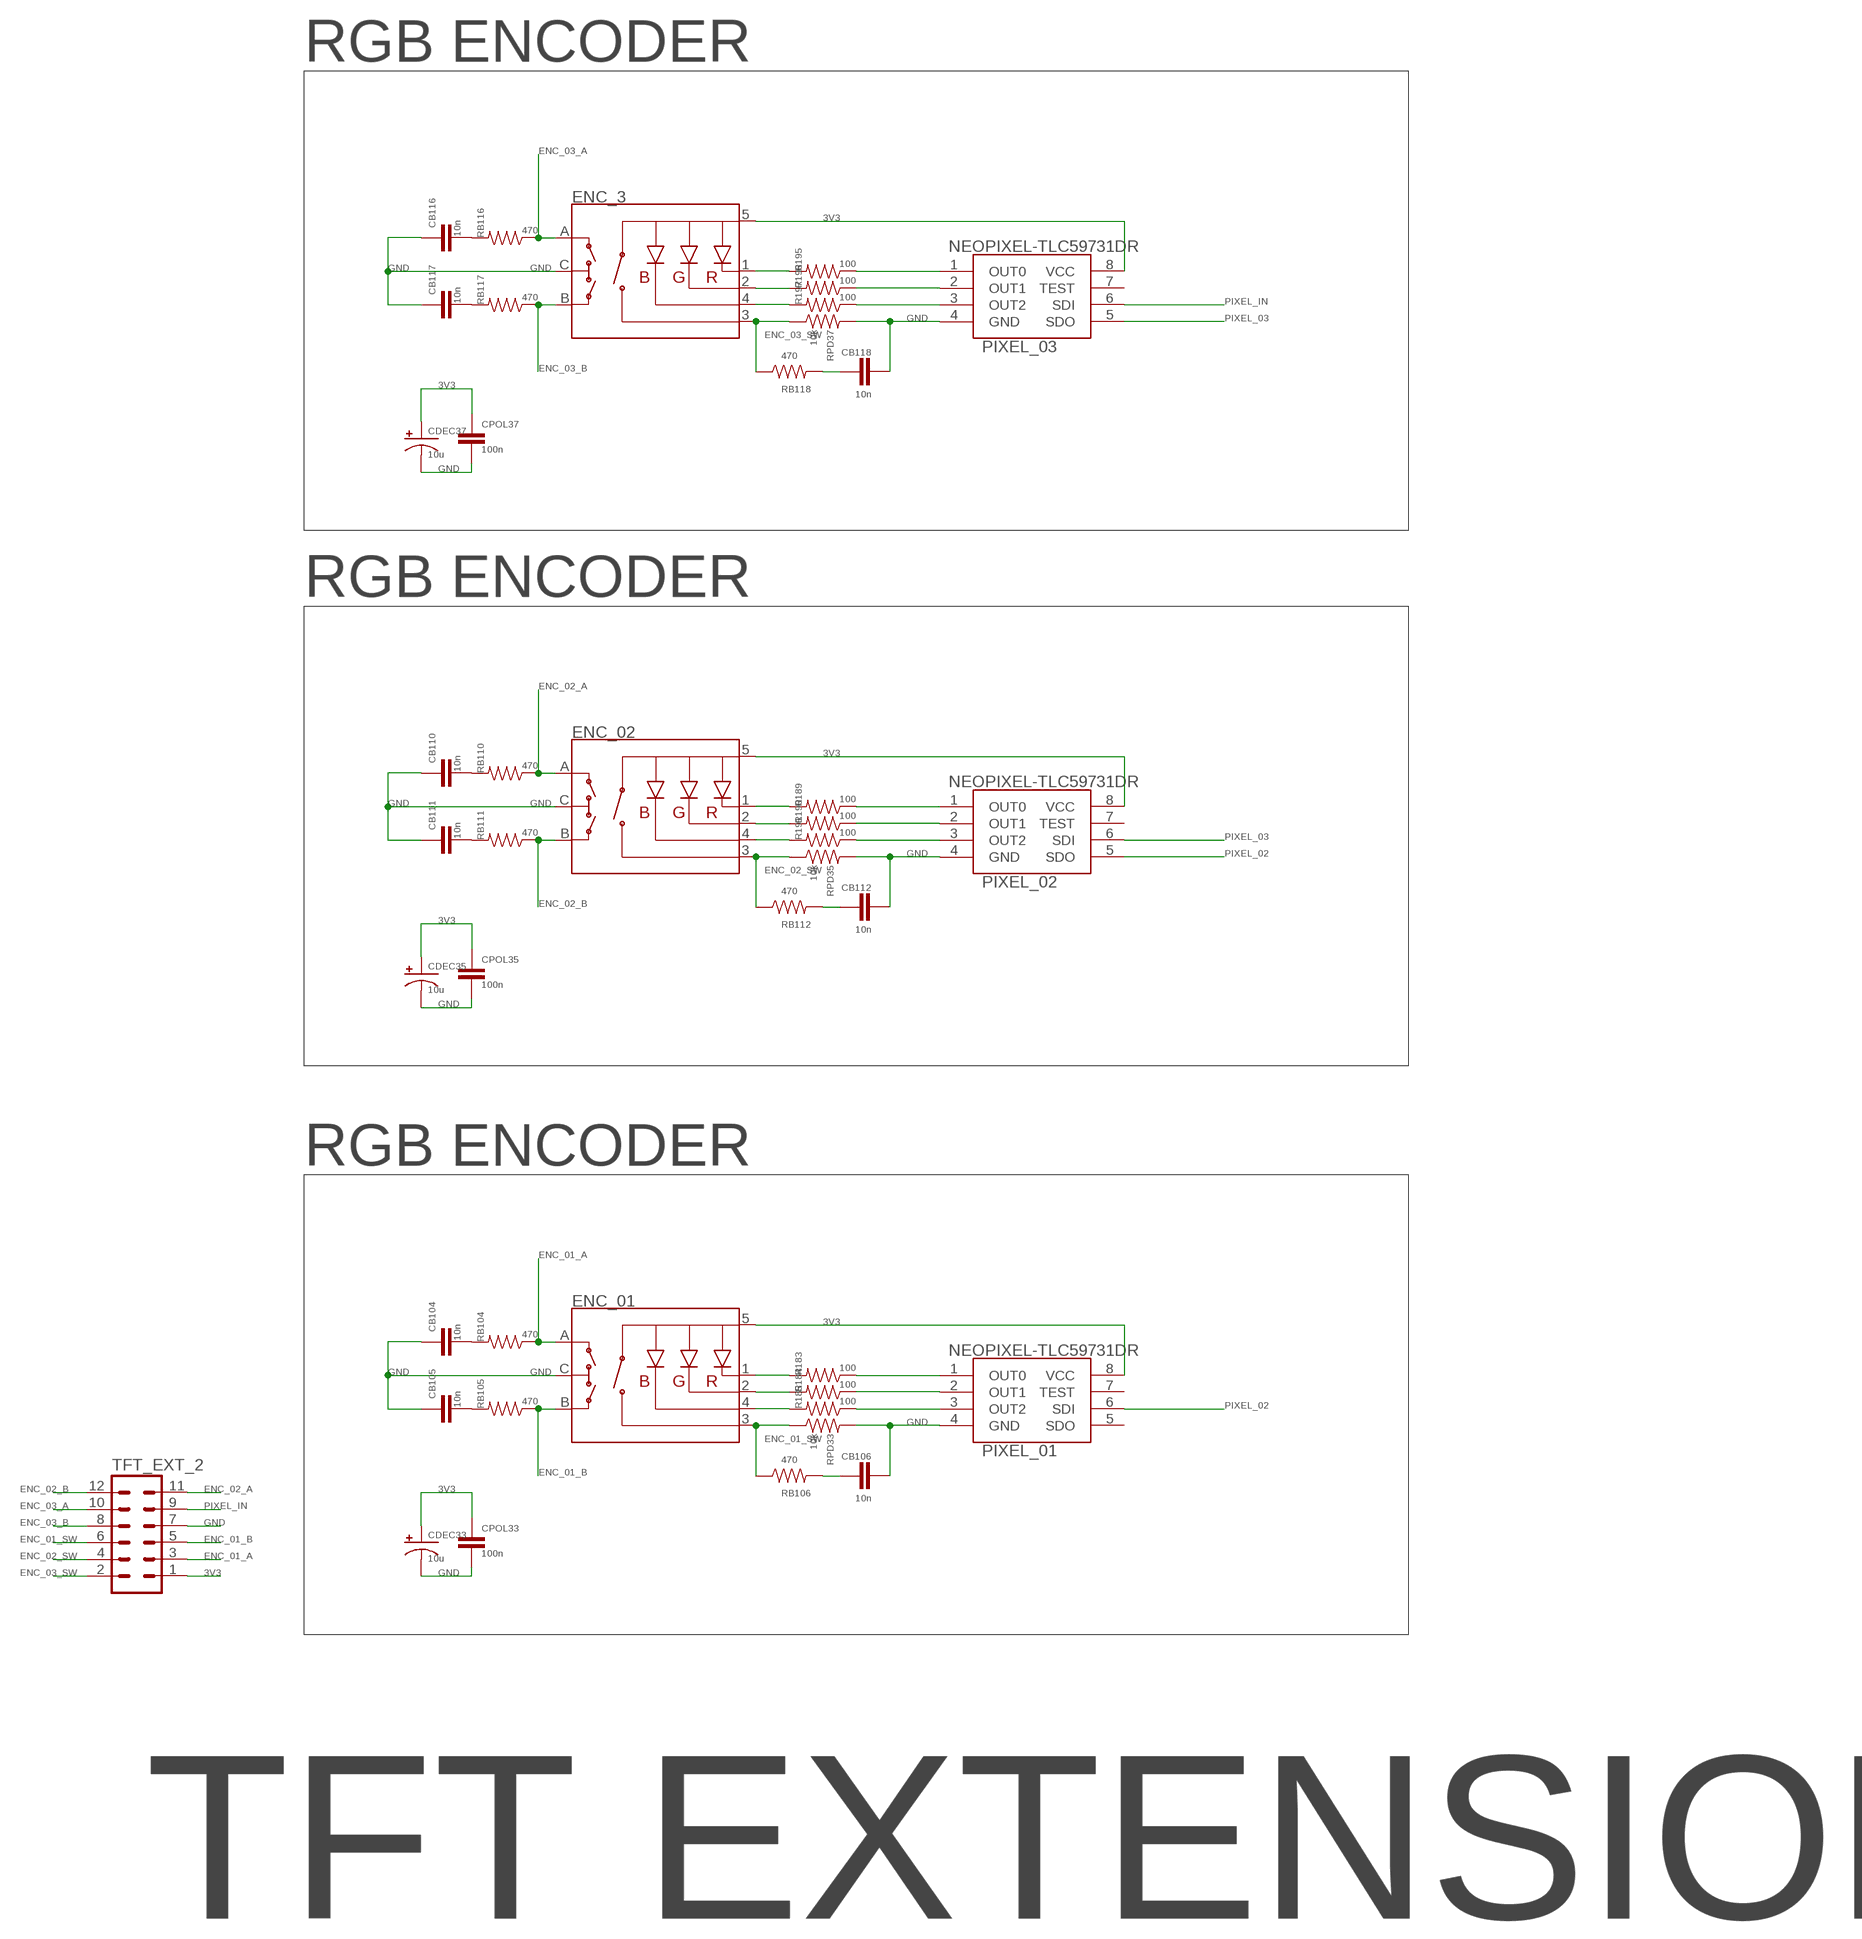
[diagram p14: schematic, sheet 7]

(export (version "E")
  (design (tool "Eeschema 10.0.6"))
  (components
    (comp (ref "CB20")
      (value "10n")
      (footprint "eagle-import:0805-CAP")
      (libsource (lib "eagle-import") (part "PASSIF-CAP-0805"))
    )
    (comp (ref "CB21")
      (value "10n")
      (footprint "eagle-import:0805-CAP")
      (libsource (lib "eagle-import") (part "PASSIF-CAP-0805"))
    )
    (comp (ref "CB22")
      (value "10n")
      (footprint "eagle-import:0805-CAP")
      (libsource (lib "eagle-import") (part "PASSIF-CAP-0805"))
    )
    (comp (ref "CB38")
      (value "10n")
      (footprint "eagle-import:0805-CAP")
      (libsource (lib "eagle-import") (part "PASSIF-CAP-0805"))
    )
    (comp (ref "CB39")
      (value "10n")
      (footprint "eagle-import:0805-CAP")
      (libsource (lib "eagle-import") (part "PASSIF-CAP-0805"))
    )
    (comp (ref "CB40")
      (value "10n")
      (footprint "eagle-import:0805-CAP")
      (libsource (lib "eagle-import") (part "PASSIF-CAP-0805"))
    )
    (comp (ref "CB50")
      (value "10n")
      (footprint "eagle-import:0805-CAP")
      (libsource (lib "eagle-import") (part "PASSIF-CAP-0805"))
    )
    (comp (ref "CB51")
      (value "10n")
      (footprint "eagle-import:0805-CAP")
      (libsource (lib "eagle-import") (part "PASSIF-CAP-0805"))
    )
    (comp (ref "CB52")
      (value "10n")
      (footprint "eagle-import:0805-CAP")
      (libsource (lib "eagle-import") (part "PASSIF-CAP-0805"))
    )
    (comp (ref "CB62")
      (value "10n")
      (footprint "eagle-import:0805-CAP")
      (libsource (lib "eagle-import") (part "PASSIF-CAP-0805"))
    )
    (comp (ref "CB63")
      (value "10n")
      (footprint "eagle-import:0805-CAP")
      (libsource (lib "eagle-import") (part "PASSIF-CAP-0805"))
    )
    (comp (ref "CB64")
      (value "10n")
      (footprint "eagle-import:0805-CAP")
      (libsource (lib "eagle-import") (part "PASSIF-CAP-0805"))
    )
    (comp (ref "CB74")
      (value "10n")
      (footprint "eagle-import:0805-CAP")
      (libsource (lib "eagle-import") (part "PASSIF-CAP-0805"))
    )
    (comp (ref "CB75")
      (value "10n")
      (footprint "eagle-import:0805-CAP")
      (libsource (lib "eagle-import") (part "PASSIF-CAP-0805"))
    )
    (comp (ref "CB76")
      (value "10n")
      (footprint "eagle-import:0805-CAP")
      (libsource (lib "eagle-import") (part "PASSIF-CAP-0805"))
    )
    (comp (ref "CB77")
      (value "10n")
      (footprint "eagle-import:0805-CAP")
      (libsource (lib "eagle-import") (part "PASSIF-CAP-0805"))
    )
    (comp (ref "CB78")
      (value "10n")
      (footprint "eagle-import:0805-CAP")
      (libsource (lib "eagle-import") (part "PASSIF-CAP-0805"))
    )
    (comp (ref "CB79")
      (value "10n")
      (footprint "eagle-import:0805-CAP")
      (libsource (lib "eagle-import") (part "PASSIF-CAP-0805"))
    )
    (comp (ref "CB83")
      (value "10n")
      (footprint "eagle-import:0805-CAP")
      (libsource (lib "eagle-import") (part "PASSIF-CAP-0805"))
    )
    (comp (ref "CB84")
      (value "10n")
      (footprint "eagle-import:0805-CAP")
      (libsource (lib "eagle-import") (part "PASSIF-CAP-0805"))
    )
    (comp (ref "CB85")
      (value "10n")
      (footprint "eagle-import:0805-CAP")
      (libsource (lib "eagle-import") (part "PASSIF-CAP-0805"))
    )
    (comp (ref "CB89")
      (value "10n")
      (footprint "eagle-import:0805-CAP")
      (libsource (lib "eagle-import") (part "PASSIF-CAP-0805"))
    )
    (comp (ref "CB90")
      (value "10n")
      (footprint "eagle-import:0805-CAP")
      (libsource (lib "eagle-import") (part "PASSIF-CAP-0805"))
    )
    (comp (ref "CB91")
      (value "10n")
      (footprint "eagle-import:0805-CAP")
      (libsource (lib "eagle-import") (part "PASSIF-CAP-0805"))
    )
    (comp (ref "CDEC5")
      (value "10u")
      (footprint "eagle-import:CPOL2917")
      (libsource (lib "eagle-import") (part "PASSIF-CPOL-US2917"))
    )
    (comp (ref "CDEC11")
      (value "10u")
      (footprint "eagle-import:CPOL2917")
      (libsource (lib "eagle-import") (part "PASSIF-CPOL-US2917"))
    )
    (comp (ref "CDEC15")
      (value "10u")
      (footprint "eagle-import:CPOL2917")
      (libsource (lib "eagle-import") (part "PASSIF-CPOL-US2917"))
    )
    (comp (ref "CDEC19")
      (value "10u")
      (footprint "eagle-import:CPOL2917")
      (libsource (lib "eagle-import") (part "PASSIF-CPOL-US2917"))
    )
    (comp (ref "CDEC23")
      (value "10u")
      (footprint "eagle-import:CPOL2917")
      (libsource (lib "eagle-import") (part "PASSIF-CPOL-US2917"))
    )
    (comp (ref "CDEC24")
      (value "10u")
      (footprint "eagle-import:CPOL2917")
      (libsource (lib "eagle-import") (part "PASSIF-CPOL-US2917"))
    )
    (comp (ref "CDEC26")
      (value "10u")
      (footprint "eagle-import:CPOL2917")
      (libsource (lib "eagle-import") (part "PASSIF-CPOL-US2917"))
    )
    (comp (ref "CDEC28")
      (value "10u")
      (footprint "eagle-import:CPOL2917")
      (libsource (lib "eagle-import") (part "PASSIF-CPOL-US2917"))
    )
    (comp (ref "CDEC_41A")
      (value "10u")
      (footprint "eagle-import:CPOL2917")
      (libsource (lib "eagle-import") (part "PASSIF-CPOL-US2917"))
    )
    (comp (ref "CDEC_41B")
      (value "100n")
      (footprint "eagle-import:0805-CAP")
      (libsource (lib "eagle-import") (part "PASSIF-CAP-0805"))
    )
    (comp (ref "CDEC_42A")
      (value "10u")
      (footprint "eagle-import:CPOL2917")
      (libsource (lib "eagle-import") (part "PASSIF-CPOL-US2917"))
    )
    (comp (ref "CDEC_42B")
      (value "100n")
      (footprint "eagle-import:0805-CAP")
      (libsource (lib "eagle-import") (part "PASSIF-CAP-0805"))
    )
    (comp (ref "CPOL5")
      (value "100n")
      (footprint "eagle-import:0805-CAP")
      (libsource (lib "eagle-import") (part "PASSIF-CAP-0805"))
    )
    (comp (ref "CPOL11")
      (value "100n")
      (footprint "eagle-import:0805-CAP")
      (libsource (lib "eagle-import") (part "PASSIF-CAP-0805"))
    )
    (comp (ref "CPOL15")
      (value "100n")
      (footprint "eagle-import:0805-CAP")
      (libsource (lib "eagle-import") (part "PASSIF-CAP-0805"))
    )
    (comp (ref "CPOL19")
      (value "100n")
      (footprint "eagle-import:0805-CAP")
      (libsource (lib "eagle-import") (part "PASSIF-CAP-0805"))
    )
    (comp (ref "CPOL23")
      (value "100n")
      (footprint "eagle-import:0805-CAP")
      (libsource (lib "eagle-import") (part "PASSIF-CAP-0805"))
    )
    (comp (ref "CPOL24")
      (value "100n")
      (footprint "eagle-import:0805-CAP")
      (libsource (lib "eagle-import") (part "PASSIF-CAP-0805"))
    )
    (comp (ref "CPOL26")
      (value "100n")
      (footprint "eagle-import:0805-CAP")
      (libsource (lib "eagle-import") (part "PASSIF-CAP-0805"))
    )
    (comp (ref "CPOL28")
      (value "100n")
      (footprint "eagle-import:0805-CAP")
      (libsource (lib "eagle-import") (part "PASSIF-CAP-0805"))
    )
    (comp (ref "ENC_81")
      (value "ENCODER-RGB-SWITCH-NO_NUT")
      (footprint "eagle-import:ENCODER_LED_3")
      (libsource (lib "eagle-import") (part "ENCODER-RGB-SWITCH-NO_NUT"))
    )
    (comp (ref "ENC_82")
      (value "ENCODER-RGB-SWITCH-NO_NUT")
      (footprint "eagle-import:ENCODER_LED_3")
      (libsource (lib "eagle-import") (part "ENCODER-RGB-SWITCH-NO_NUT"))
    )
    (comp (ref "ENC_83")
      (value "ENCODER-RGB-SWITCH-NO_NUT")
      (footprint "eagle-import:ENCODER_LED_3")
      (libsource (lib "eagle-import") (part "ENCODER-RGB-SWITCH-NO_NUT"))
    )
    (comp (ref "ENC_84")
      (value "ENCODER-RGB-SWITCH-NO_NUT")
      (footprint "eagle-import:ENCODER_LED_3")
      (libsource (lib "eagle-import") (part "ENCODER-RGB-SWITCH-NO_NUT"))
    )
    (comp (ref "ENC_85")
      (value "ENCODER-RGB-SWITCH-NO_NUT")
      (footprint "eagle-import:ENCODER_LED_3")
      (libsource (lib "eagle-import") (part "ENCODER-RGB-SWITCH-NO_NUT"))
    )
    (comp (ref "ENC_86")
      (value "ENCODER-RGB-SWITCH-NO_NUT")
      (footprint "eagle-import:ENCODER_LED_3")
      (libsource (lib "eagle-import") (part "ENCODER-RGB-SWITCH-NO_NUT"))
    )
    (comp (ref "ENC_87")
      (value "ENCODER-RGB-SWITCH-NO_NUT")
      (footprint "eagle-import:ENCODER_LED_3")
      (libsource (lib "eagle-import") (part "ENCODER-RGB-SWITCH-NO_NUT"))
    )
    (comp (ref "ENC_88")
      (value "ENCODER-RGB-SWITCH-NO_NUT")
      (footprint "eagle-import:ENCODER_LED_3")
      (libsource (lib "eagle-import") (part "ENCODER-RGB-SWITCH-NO_NUT"))
    )
    (comp (ref "MCP_101")
      (value "MCP23017")
      (footprint "eagle-import:SOIC-28")
      (libsource (lib "eagle-import") (part "MCP23017"))
    )
    (comp (ref "MCP_110")
      (value "MCP23017")
      (footprint "eagle-import:SOIC-28")
      (libsource (lib "eagle-import") (part "MCP23017"))
    )
    (comp (ref "PIXEL_81")
      (value "NEOPIXEL-TLC59731DR")
      (footprint "eagle-import:SOIC127P600X175-8N")
      (fields
        (field (name "ARROW_PART_NUMBER") "TLC59731DR")
        (field (name "MOUSER_PART_NUMBER") "595-TLC59731DR")
      )
      (libsource (lib "eagle-import") (part "NEOPIXEL-TLC59731DR"))
    )
    (comp (ref "PIXEL_83")
      (value "NEOPIXEL-TLC59731DR")
      (footprint "eagle-import:SOIC127P600X175-8N")
      (fields
        (field (name "ARROW_PART_NUMBER") "TLC59731DR")
        (field (name "MOUSER_PART_NUMBER") "595-TLC59731DR")
      )
      (libsource (lib "eagle-import") (part "NEOPIXEL-TLC59731DR"))
    )
    (comp (ref "PIXEL_84")
      (value "NEOPIXEL-TLC59731DR")
      (footprint "eagle-import:SOIC127P600X175-8N")
      (fields
        (field (name "ARROW_PART_NUMBER") "TLC59731DR")
        (field (name "MOUSER_PART_NUMBER") "595-TLC59731DR")
      )
      (libsource (lib "eagle-import") (part "NEOPIXEL-TLC59731DR"))
    )
    (comp (ref "PIXEL_85")
      (value "NEOPIXEL-TLC59731DR")
      (footprint "eagle-import:SOIC127P600X175-8N")
      (fields
        (field (name "ARROW_PART_NUMBER") "TLC59731DR")
        (field (name "MOUSER_PART_NUMBER") "595-TLC59731DR")
      )
      (libsource (lib "eagle-import") (part "NEOPIXEL-TLC59731DR"))
    )
    (comp (ref "PIXEL_86")
      (value "NEOPIXEL-TLC59731DR")
      (footprint "eagle-import:SOIC127P600X175-8N")
      (fields
        (field (name "ARROW_PART_NUMBER") "TLC59731DR")
        (field (name "MOUSER_PART_NUMBER") "595-TLC59731DR")
      )
      (libsource (lib "eagle-import") (part "NEOPIXEL-TLC59731DR"))
    )
    (comp (ref "PIXEL_87")
      (value "NEOPIXEL-TLC59731DR")
      (footprint "eagle-import:SOIC127P600X175-8N")
      (fields
        (field (name "ARROW_PART_NUMBER") "TLC59731DR")
        (field (name "MOUSER_PART_NUMBER") "595-TLC59731DR")
      )
      (libsource (lib "eagle-import") (part "NEOPIXEL-TLC59731DR"))
    )
    (comp (ref "PIXEL_88")
      (value "NEOPIXEL-TLC59731DR")
      (footprint "eagle-import:SOIC127P600X175-8N")
      (fields
        (field (name "ARROW_PART_NUMBER") "TLC59731DR")
        (field (name "MOUSER_PART_NUMBER") "595-TLC59731DR")
      )
      (libsource (lib "eagle-import") (part "NEOPIXEL-TLC59731DR"))
    )
    (comp (ref "PIXE_82")
      (value "NEOPIXEL-TLC59731DR")
      (footprint "eagle-import:SOIC127P600X175-8N")
      (fields
        (field (name "ARROW_PART_NUMBER") "TLC59731DR")
        (field (name "MOUSER_PART_NUMBER") "595-TLC59731DR")
      )
      (libsource (lib "eagle-import") (part "NEOPIXEL-TLC59731DR"))
    )
    (comp (ref "R65")
      (value "100")
      (footprint "eagle-import:1206")
      (libsource (lib "eagle-import") (part "PASSIF-RESISTOR-1206"))
    )
    (comp (ref "R73")
      (value "100")
      (footprint "eagle-import:1206")
      (libsource (lib "eagle-import") (part "PASSIF-RESISTOR-1206"))
    )
    (comp (ref "R74")
      (value "100")
      (footprint "eagle-import:1206")
      (libsource (lib "eagle-import") (part "PASSIF-RESISTOR-1206"))
    )
    (comp (ref "R110")
      (value "100")
      (footprint "eagle-import:1206")
      (libsource (lib "eagle-import") (part "PASSIF-RESISTOR-1206"))
    )
    (comp (ref "R111")
      (value "100")
      (footprint "eagle-import:1206")
      (libsource (lib "eagle-import") (part "PASSIF-RESISTOR-1206"))
    )
    (comp (ref "R112")
      (value "100")
      (footprint "eagle-import:1206")
      (libsource (lib "eagle-import") (part "PASSIF-RESISTOR-1206"))
    )
    (comp (ref "R129")
      (value "100")
      (footprint "eagle-import:1206")
      (libsource (lib "eagle-import") (part "PASSIF-RESISTOR-1206"))
    )
    (comp (ref "R130")
      (value "100")
      (footprint "eagle-import:1206")
      (libsource (lib "eagle-import") (part "PASSIF-RESISTOR-1206"))
    )
    (comp (ref "R131")
      (value "100")
      (footprint "eagle-import:1206")
      (libsource (lib "eagle-import") (part "PASSIF-RESISTOR-1206"))
    )
    (comp (ref "R141")
      (value "100")
      (footprint "eagle-import:1206")
      (libsource (lib "eagle-import") (part "PASSIF-RESISTOR-1206"))
    )
    (comp (ref "R142")
      (value "100")
      (footprint "eagle-import:1206")
      (libsource (lib "eagle-import") (part "PASSIF-RESISTOR-1206"))
    )
    (comp (ref "R143")
      (value "100")
      (footprint "eagle-import:1206")
      (libsource (lib "eagle-import") (part "PASSIF-RESISTOR-1206"))
    )
    (comp (ref "R153")
      (value "100")
      (footprint "eagle-import:1206")
      (libsource (lib "eagle-import") (part "PASSIF-RESISTOR-1206"))
    )
    (comp (ref "R154")
      (value "100")
      (footprint "eagle-import:1206")
      (libsource (lib "eagle-import") (part "PASSIF-RESISTOR-1206"))
    )
    (comp (ref "R155")
      (value "100")
      (footprint "eagle-import:1206")
      (libsource (lib "eagle-import") (part "PASSIF-RESISTOR-1206"))
    )
    (comp (ref "R156")
      (value "100")
      (footprint "eagle-import:1206")
      (libsource (lib "eagle-import") (part "PASSIF-RESISTOR-1206"))
    )
    (comp (ref "R157")
      (value "100")
      (footprint "eagle-import:1206")
      (libsource (lib "eagle-import") (part "PASSIF-RESISTOR-1206"))
    )
    (comp (ref "R158")
      (value "100")
      (footprint "eagle-import:1206")
      (libsource (lib "eagle-import") (part "PASSIF-RESISTOR-1206"))
    )
    (comp (ref "R162")
      (value "100")
      (footprint "eagle-import:1206")
      (libsource (lib "eagle-import") (part "PASSIF-RESISTOR-1206"))
    )
    (comp (ref "R163")
      (value "100")
      (footprint "eagle-import:1206")
      (libsource (lib "eagle-import") (part "PASSIF-RESISTOR-1206"))
    )
    (comp (ref "R164")
      (value "100")
      (footprint "eagle-import:1206")
      (libsource (lib "eagle-import") (part "PASSIF-RESISTOR-1206"))
    )
    (comp (ref "R168")
      (value "100")
      (footprint "eagle-import:1206")
      (libsource (lib "eagle-import") (part "PASSIF-RESISTOR-1206"))
    )
    (comp (ref "R169")
      (value "100")
      (footprint "eagle-import:1206")
      (libsource (lib "eagle-import") (part "PASSIF-RESISTOR-1206"))
    )
    (comp (ref "R170")
      (value "100")
      (footprint "eagle-import:1206")
      (libsource (lib "eagle-import") (part "PASSIF-RESISTOR-1206"))
    )
    (comp (ref "R194")
      (value "1k")
      (footprint "eagle-import:R0805")
      (libsource (lib "eagle-import") (part "R-US_R0805"))
    )
    (comp (ref "R198")
      (value "1k")
      (footprint "eagle-import:R0805")
      (libsource (lib "eagle-import") (part "R-US_R0805"))
    )
    (comp (ref "R199")
      (value "1k")
      (footprint "eagle-import:R0805")
      (libsource (lib "eagle-import") (part "R-US_R0805"))
    )
    (comp (ref "R203")
      (value "1k")
      (footprint "eagle-import:R0805")
      (libsource (lib "eagle-import") (part "R-US_R0805"))
    )
    (comp (ref "RB20")
      (value "470")
      (footprint "eagle-import:1206")
      (libsource (lib "eagle-import") (part "PASSIF-RESISTOR-1206"))
    )
    (comp (ref "RB21")
      (value "470")
      (footprint "eagle-import:1206")
      (libsource (lib "eagle-import") (part "PASSIF-RESISTOR-1206"))
    )
    (comp (ref "RB22")
      (value "470")
      (footprint "eagle-import:1206")
      (libsource (lib "eagle-import") (part "PASSIF-RESISTOR-1206"))
    )
    (comp (ref "RB38")
      (value "470")
      (footprint "eagle-import:1206")
      (libsource (lib "eagle-import") (part "PASSIF-RESISTOR-1206"))
    )
    (comp (ref "RB39")
      (value "470")
      (footprint "eagle-import:1206")
      (libsource (lib "eagle-import") (part "PASSIF-RESISTOR-1206"))
    )
    (comp (ref "RB40")
      (value "470")
      (footprint "eagle-import:1206")
      (libsource (lib "eagle-import") (part "PASSIF-RESISTOR-1206"))
    )
    (comp (ref "RB50")
      (value "470")
      (footprint "eagle-import:1206")
      (libsource (lib "eagle-import") (part "PASSIF-RESISTOR-1206"))
    )
    (comp (ref "RB51")
      (value "470")
      (footprint "eagle-import:1206")
      (libsource (lib "eagle-import") (part "PASSIF-RESISTOR-1206"))
    )
    (comp (ref "RB52")
      (value "470")
      (footprint "eagle-import:1206")
      (libsource (lib "eagle-import") (part "PASSIF-RESISTOR-1206"))
    )
    (comp (ref "RB62")
      (value "470")
      (footprint "eagle-import:1206")
      (libsource (lib "eagle-import") (part "PASSIF-RESISTOR-1206"))
    )
    (comp (ref "RB63")
      (value "470")
      (footprint "eagle-import:1206")
      (libsource (lib "eagle-import") (part "PASSIF-RESISTOR-1206"))
    )
    (comp (ref "RB64")
      (value "470")
      (footprint "eagle-import:1206")
      (libsource (lib "eagle-import") (part "PASSIF-RESISTOR-1206"))
    )
    (comp (ref "RB74")
      (value "470")
      (footprint "eagle-import:1206")
      (libsource (lib "eagle-import") (part "PASSIF-RESISTOR-1206"))
    )
    (comp (ref "RB75")
      (value "470")
      (footprint "eagle-import:1206")
      (libsource (lib "eagle-import") (part "PASSIF-RESISTOR-1206"))
    )
    (comp (ref "RB76")
      (value "470")
      (footprint "eagle-import:1206")
      (libsource (lib "eagle-import") (part "PASSIF-RESISTOR-1206"))
    )
    (comp (ref "RB77")
      (value "470")
      (footprint "eagle-import:1206")
      (libsource (lib "eagle-import") (part "PASSIF-RESISTOR-1206"))
    )
    (comp (ref "RB78")
      (value "470")
      (footprint "eagle-import:1206")
      (libsource (lib "eagle-import") (part "PASSIF-RESISTOR-1206"))
    )
    (comp (ref "RB79")
      (value "470")
      (footprint "eagle-import:1206")
      (libsource (lib "eagle-import") (part "PASSIF-RESISTOR-1206"))
    )
    (comp (ref "RB83")
      (value "470")
      (footprint "eagle-import:1206")
      (libsource (lib "eagle-import") (part "PASSIF-RESISTOR-1206"))
    )
    (comp (ref "RB84")
      (value "470")
      (footprint "eagle-import:1206")
      (libsource (lib "eagle-import") (part "PASSIF-RESISTOR-1206"))
    )
    (comp (ref "RB85")
      (value "470")
      (footprint "eagle-import:1206")
      (libsource (lib "eagle-import") (part "PASSIF-RESISTOR-1206"))
    )
    (comp (ref "RB89")
      (value "470")
      (footprint "eagle-import:1206")
      (libsource (lib "eagle-import") (part "PASSIF-RESISTOR-1206"))
    )
    (comp (ref "RB90")
      (value "470")
      (footprint "eagle-import:1206")
      (libsource (lib "eagle-import") (part "PASSIF-RESISTOR-1206"))
    )
    (comp (ref "RB91")
      (value "470")
      (footprint "eagle-import:1206")
      (libsource (lib "eagle-import") (part "PASSIF-RESISTOR-1206"))
    )
    (comp (ref "RPD5")
      (value "10k")
      (footprint "eagle-import:1206")
      (libsource (lib "eagle-import") (part "PASSIF-RESISTOR-1206"))
    )
    (comp (ref "RPD11")
      (value "10k")
      (footprint "eagle-import:1206")
      (libsource (lib "eagle-import") (part "PASSIF-RESISTOR-1206"))
    )
    (comp (ref "RPD15")
      (value "10k")
      (footprint "eagle-import:1206")
      (libsource (lib "eagle-import") (part "PASSIF-RESISTOR-1206"))
    )
    (comp (ref "RPD19")
      (value "10k")
      (footprint "eagle-import:1206")
      (libsource (lib "eagle-import") (part "PASSIF-RESISTOR-1206"))
    )
    (comp (ref "RPD23")
      (value "10k")
      (footprint "eagle-import:1206")
      (libsource (lib "eagle-import") (part "PASSIF-RESISTOR-1206"))
    )
    (comp (ref "RPD24")
      (value "10k")
      (footprint "eagle-import:1206")
      (libsource (lib "eagle-import") (part "PASSIF-RESISTOR-1206"))
    )
    (comp (ref "RPD26")
      (value "10k")
      (footprint "eagle-import:1206")
      (libsource (lib "eagle-import") (part "PASSIF-RESISTOR-1206"))
    )
    (comp (ref "RPD28")
      (value "10k")
      (footprint "eagle-import:1206")
      (libsource (lib "eagle-import") (part "PASSIF-RESISTOR-1206"))
    )
    (comp (ref "TFT_EXT")
      (value "MA06-2")
      (footprint "eagle-import:MA06-2")
      (libsource (lib "eagle-import") (part "MA06-2"))
    )
    (comp (ref "C4")
      (value "10n")
      (footprint "eagle-import:0805-CAP")
      (libsource (lib "eagle-import") (part "PASSIF-CAP-0805"))
    )
    (comp (ref "C5")
      (value "10n")
      (footprint "eagle-import:0805-CAP")
      (libsource (lib "eagle-import") (part "PASSIF-CAP-0805"))
    )
    (comp (ref "C6")
      (value "10n")
      (footprint "eagle-import:0805-CAP")
      (libsource (lib "eagle-import") (part "PASSIF-CAP-0805"))
    )
    (comp (ref "C7")
      (value "10n")
      (footprint "eagle-import:0805-CAP")
      (libsource (lib "eagle-import") (part "PASSIF-CAP-0805"))
    )
    (comp (ref "C8")
      (value "10n")
      (footprint "eagle-import:0805-CAP")
      (libsource (lib "eagle-import") (part "PASSIF-CAP-0805"))
    )
    (comp (ref "C9")
      (value "10n")
      (footprint "eagle-import:0805-CAP")
      (libsource (lib "eagle-import") (part "PASSIF-CAP-0805"))
    )
    (comp (ref "C10")
      (value "10n")
      (footprint "eagle-import:0805-CAP")
      (libsource (lib "eagle-import") (part "PASSIF-CAP-0805"))
    )
    (comp (ref "C11")
      (value "10n")
      (footprint "eagle-import:0805-CAP")
      (libsource (lib "eagle-import") (part "PASSIF-CAP-0805"))
    )
    (comp (ref "C12")
      (value "10n")
      (footprint "eagle-import:0805-CAP")
      (libsource (lib "eagle-import") (part "PASSIF-CAP-0805"))
    )
    (comp (ref "C16")
      (value "10n")
      (footprint "eagle-import:0805-CAP")
      (libsource (lib "eagle-import") (part "PASSIF-CAP-0805"))
    )
    (comp (ref "C17")
      (value "10n")
      (footprint "eagle-import:0805-CAP")
      (libsource (lib "eagle-import") (part "PASSIF-CAP-0805"))
    )
    (comp (ref "C18")
      (value "10n")
      (footprint "eagle-import:0805-CAP")
      (libsource (lib "eagle-import") (part "PASSIF-CAP-0805"))
    )
    (comp (ref "C22")
      (value "10n")
      (footprint "eagle-import:0805-CAP")
      (libsource (lib "eagle-import") (part "PASSIF-CAP-0805"))
    )
    (comp (ref "C23")
      (value "10n")
      (footprint "eagle-import:0805-CAP")
      (libsource (lib "eagle-import") (part "PASSIF-CAP-0805"))
    )
    (comp (ref "C24")
      (value "10n")
      (footprint "eagle-import:0805-CAP")
      (libsource (lib "eagle-import") (part "PASSIF-CAP-0805"))
    )
    (comp (ref "C28")
      (value "10n")
      (footprint "eagle-import:0805-CAP")
      (libsource (lib "eagle-import") (part "PASSIF-CAP-0805"))
    )
    (comp (ref "C29")
      (value "10n")
      (footprint "eagle-import:0805-CAP")
      (libsource (lib "eagle-import") (part "PASSIF-CAP-0805"))
    )
    (comp (ref "C30")
      (value "10n")
      (footprint "eagle-import:0805-CAP")
      (libsource (lib "eagle-import") (part "PASSIF-CAP-0805"))
    )
    (comp (ref "C34")
      (value "10n")
      (footprint "eagle-import:0805-CAP")
      (libsource (lib "eagle-import") (part "PASSIF-CAP-0805"))
    )
    (comp (ref "C35")
      (value "10n")
      (footprint "eagle-import:0805-CAP")
      (libsource (lib "eagle-import") (part "PASSIF-CAP-0805"))
    )
    (comp (ref "C36")
      (value "10n")
      (footprint "eagle-import:0805-CAP")
      (libsource (lib "eagle-import") (part "PASSIF-CAP-0805"))
    )
    (comp (ref "C40")
      (value "10n")
      (footprint "eagle-import:0805-CAP")
      (libsource (lib "eagle-import") (part "PASSIF-CAP-0805"))
    )
    (comp (ref "C41")
      (value "10n")
      (footprint "eagle-import:0805-CAP")
      (libsource (lib "eagle-import") (part "PASSIF-CAP-0805"))
    )
    (comp (ref "C42")
      (value "10n")
      (footprint "eagle-import:0805-CAP")
      (libsource (lib "eagle-import") (part "PASSIF-CAP-0805"))
    )
    (comp (ref "C46")
      (value "10n")
      (footprint "eagle-import:0805-CAP")
      (libsource (lib "eagle-import") (part "PASSIF-CAP-0805"))
    )
    (comp (ref "C47")
      (value "10n")
      (footprint "eagle-import:0805-CAP")
      (libsource (lib "eagle-import") (part "PASSIF-CAP-0805"))
    )
    (comp (ref "C48")
      (value "10n")
      (footprint "eagle-import:0805-CAP")
      (libsource (lib "eagle-import") (part "PASSIF-CAP-0805"))
    )
    (comp (ref "CB1")
      (value "10n")
      (footprint "eagle-import:0805-CAP")
      (libsource (lib "eagle-import") (part "PASSIF-CAP-0805"))
    )
    (comp (ref "CB2")
      (value "10n")
      (footprint "eagle-import:0805-CAP")
      (libsource (lib "eagle-import") (part "PASSIF-CAP-0805"))
    )
    (comp (ref "CB4")
      (value "10n")
      (footprint "eagle-import:0805-CAP")
      (libsource (lib "eagle-import") (part "PASSIF-CAP-0805"))
    )
    (comp (ref "CB6")
      (value "10n")
      (footprint "eagle-import:0805-CAP")
      (libsource (lib "eagle-import") (part "PASSIF-CAP-0805"))
    )
    (comp (ref "CDEC_1")
      (value "100n")
      (footprint "eagle-import:1206")
      (libsource (lib "eagle-import") (part "PASSIF-CAP-1206"))
    )
    (comp (ref "CDEC_2")
      (value "100n")
      (footprint "eagle-import:1206")
      (libsource (lib "eagle-import") (part "PASSIF-CAP-1206"))
    )
    (comp (ref "CDEC_3")
      (value "100n")
      (footprint "eagle-import:1206")
      (libsource (lib "eagle-import") (part "PASSIF-CAP-1206"))
    )
    (comp (ref "CDEC_4")
      (value "100n")
      (footprint "eagle-import:1206")
      (libsource (lib "eagle-import") (part "PASSIF-CAP-1206"))
    )
    (comp (ref "CDEC_5")
      (value "100n")
      (footprint "eagle-import:1206")
      (libsource (lib "eagle-import") (part "PASSIF-CAP-1206"))
    )
    (comp (ref "CDEC_6")
      (value "100n")
      (footprint "eagle-import:1206")
      (libsource (lib "eagle-import") (part "PASSIF-CAP-1206"))
    )
    (comp (ref "CDEC_7")
      (value "100n")
      (footprint "eagle-import:1206")
      (libsource (lib "eagle-import") (part "PASSIF-CAP-1206"))
    )
    (comp (ref "CDEC_8")
      (value "100n")
      (footprint "eagle-import:1206")
      (libsource (lib "eagle-import") (part "PASSIF-CAP-1206"))
    )
    (comp (ref "CDEC_9")
      (value "100n")
      (footprint "eagle-import:1206")
      (libsource (lib "eagle-import") (part "PASSIF-CAP-1206"))
    )
    (comp (ref "CDEC_10")
      (value "100n")
      (footprint "eagle-import:1206")
      (libsource (lib "eagle-import") (part "PASSIF-CAP-1206"))
    )
    (comp (ref "CDEC_11")
      (value "100n")
      (footprint "eagle-import:1206")
      (libsource (lib "eagle-import") (part "PASSIF-CAP-1206"))
    )
    (comp (ref "CDEC_11A")
      (value "10u")
      (footprint "eagle-import:CPOL2917")
      (libsource (lib "eagle-import") (part "PASSIF-CPOL-US2917"))
    )
    (comp (ref "CDEC_11B")
      (value "100n")
      (footprint "eagle-import:0805-CAP")
      (libsource (lib "eagle-import") (part "PASSIF-CAP-0805"))
    )
    (comp (ref "CDEC_12")
      (value "100n")
      (footprint "eagle-import:1206")
      (libsource (lib "eagle-import") (part "PASSIF-CAP-1206"))
    )
    (comp (ref "CDEC_12A")
      (value "10u")
      (footprint "eagle-import:CPOL2917")
      (libsource (lib "eagle-import") (part "PASSIF-CPOL-US2917"))
    )
    (comp (ref "CDEC_12B")
      (value "100n")
      (footprint "eagle-import:0805-CAP")
      (libsource (lib "eagle-import") (part "PASSIF-CAP-0805"))
    )
    (comp (ref "CDEC_13")
      (value "100n")
      (footprint "eagle-import:1206")
      (libsource (lib "eagle-import") (part "PASSIF-CAP-1206"))
    )
    (comp (ref "CONN_STH_BRD_2")
      (value "MA10-2")
      (footprint "eagle-import:MA10-2")
      (libsource (lib "eagle-import") (part "MA10-2"))
    )
    (comp (ref "ENC_11")
      (value "ENCODER-RGB-SWITCH-NO_NUT")
      (footprint "eagle-import:ENCODER_LED_3")
      (libsource (lib "eagle-import") (part "ENCODER-RGB-SWITCH-NO_NUT"))
    )
    (comp (ref "ENC_13")
      (value "ENCODER-RGB-SWITCH-NO_NUT")
      (footprint "eagle-import:ENCODER_LED_3")
      (libsource (lib "eagle-import") (part "ENCODER-RGB-SWITCH-NO_NUT"))
    )
    (comp (ref "ENC_14")
      (value "ENCODER-RGB-SWITCH-NO_NUT")
      (footprint "eagle-import:ENCODER_LED_3")
      (libsource (lib "eagle-import") (part "ENCODER-RGB-SWITCH-NO_NUT"))
    )
    (comp (ref "ENC_21")
      (value "ENCODER-RGB-SWITCH-NO_NUT")
      (footprint "eagle-import:ENCODER_LED_3")
      (libsource (lib "eagle-import") (part "ENCODER-RGB-SWITCH-NO_NUT"))
    )
    (comp (ref "ENC_23")
      (value "ENCODER-RGB-SWITCH-NO_NUT")
      (footprint "eagle-import:ENCODER_LED_3")
      (libsource (lib "eagle-import") (part "ENCODER-RGB-SWITCH-NO_NUT"))
    )
    (comp (ref "LED1")
      (value "CZXR-80RGB03-A")
      (footprint "eagle-import:LED4-2.0-D8.0MM")
      (libsource (lib "eagle-import") (part "DIP-LED-RGB-COMMON-ANODE(4P-D8MM)"))
    )
    (comp (ref "LED2")
      (value "CZXR-80RGB03-A")
      (footprint "eagle-import:LED4-2.0-D8.0MM")
      (libsource (lib "eagle-import") (part "DIP-LED-RGB-COMMON-ANODE(4P-D8MM)"))
    )
    (comp (ref "LED6")
      (value "CZXR-80RGB03-A")
      (footprint "eagle-import:LED4-2.0-D8.0MM")
      (libsource (lib "eagle-import") (part "DIP-LED-RGB-COMMON-ANODE(4P-D8MM)"))
    )
    (comp (ref "LED22")
      (value "CZXR-80RGB03-A")
      (footprint "eagle-import:LED4-2.0-D8.0MM")
      (libsource (lib "eagle-import") (part "DIP-LED-RGB-COMMON-ANODE(4P-D8MM)"))
    )
    (comp (ref "MCP_000")
      (value "MCP23017")
      (footprint "eagle-import:SOIC-28")
      (libsource (lib "eagle-import") (part "MCP23017"))
    )
    (comp (ref "MCP_001")
      (value "MCP23017")
      (footprint "eagle-import:SOIC-28")
      (libsource (lib "eagle-import") (part "MCP23017"))
    )
    (comp (ref "PIXEL_11")
      (value "NEOPIXEL-TLC59731DR")
      (footprint "eagle-import:SOIC127P600X175-8N")
      (fields
        (field (name "ARROW_PART_NUMBER") "TLC59731DR")
        (field (name "MOUSER_PART_NUMBER") "595-TLC59731DR")
      )
      (libsource (lib "eagle-import") (part "NEOPIXEL-TLC59731DR"))
    )
    (comp (ref "PIXEL_12")
      (value "NEOPIXEL-TLC59731DR")
      (footprint "eagle-import:SOIC127P600X175-8N")
      (fields
        (field (name "ARROW_PART_NUMBER") "TLC59731DR")
        (field (name "MOUSER_PART_NUMBER") "595-TLC59731DR")
      )
      (libsource (lib "eagle-import") (part "NEOPIXEL-TLC59731DR"))
    )
    (comp (ref "PIXEL_13")
      (value "NEOPIXEL-TLC59731DR")
      (footprint "eagle-import:SOIC127P600X175-8N")
      (fields
        (field (name "ARROW_PART_NUMBER") "TLC59731DR")
        (field (name "MOUSER_PART_NUMBER") "595-TLC59731DR")
      )
      (libsource (lib "eagle-import") (part "NEOPIXEL-TLC59731DR"))
    )
    (comp (ref "PIXEL_14")
      (value "NEOPIXEL-TLC59731DR")
      (footprint "eagle-import:SOIC127P600X175-8N")
      (fields
        (field (name "ARROW_PART_NUMBER") "TLC59731DR")
        (field (name "MOUSER_PART_NUMBER") "595-TLC59731DR")
      )
      (libsource (lib "eagle-import") (part "NEOPIXEL-TLC59731DR"))
    )
    (comp (ref "PIXEL_21")
      (value "NEOPIXEL-TLC59731DR")
      (footprint "eagle-import:SOIC127P600X175-8N")
      (fields
        (field (name "ARROW_PART_NUMBER") "TLC59731DR")
        (field (name "MOUSER_PART_NUMBER") "595-TLC59731DR")
      )
      (libsource (lib "eagle-import") (part "NEOPIXEL-TLC59731DR"))
    )
    (comp (ref "PIXEL_22")
      (value "NEOPIXEL-TLC59731DR")
      (footprint "eagle-import:SOIC127P600X175-8N")
      (fields
        (field (name "ARROW_PART_NUMBER") "TLC59731DR")
        (field (name "MOUSER_PART_NUMBER") "595-TLC59731DR")
      )
      (libsource (lib "eagle-import") (part "NEOPIXEL-TLC59731DR"))
    )
    (comp (ref "PIXEL_23")
      (value "NEOPIXEL-TLC59731DR")
      (footprint "eagle-import:SOIC127P600X175-8N")
      (fields
        (field (name "ARROW_PART_NUMBER") "TLC59731DR")
        (field (name "MOUSER_PART_NUMBER") "595-TLC59731DR")
      )
      (libsource (lib "eagle-import") (part "NEOPIXEL-TLC59731DR"))
    )
    (comp (ref "PIXEL_24")
      (value "NEOPIXEL-TLC59731DR")
      (footprint "eagle-import:SOIC127P600X175-8N")
      (fields
        (field (name "ARROW_PART_NUMBER") "TLC59731DR")
        (field (name "MOUSER_PART_NUMBER") "595-TLC59731DR")
      )
      (libsource (lib "eagle-import") (part "NEOPIXEL-TLC59731DR"))
    )
    (comp (ref "PIXEL_31")
      (value "NEOPIXEL-TLC59731DR")
      (footprint "eagle-import:SOIC127P600X175-8N")
      (fields
        (field (name "ARROW_PART_NUMBER") "TLC59731DR")
        (field (name "MOUSER_PART_NUMBER") "595-TLC59731DR")
      )
      (libsource (lib "eagle-import") (part "NEOPIXEL-TLC59731DR"))
    )
    (comp (ref "PIXEL_32")
      (value "NEOPIXEL-TLC59731DR")
      (footprint "eagle-import:SOIC127P600X175-8N")
      (fields
        (field (name "ARROW_PART_NUMBER") "TLC59731DR")
        (field (name "MOUSER_PART_NUMBER") "595-TLC59731DR")
      )
      (libsource (lib "eagle-import") (part "NEOPIXEL-TLC59731DR"))
    )
    (comp (ref "PIXEL_33")
      (value "NEOPIXEL-TLC59731DR")
      (footprint "eagle-import:SOIC127P600X175-8N")
      (fields
        (field (name "ARROW_PART_NUMBER") "TLC59731DR")
        (field (name "MOUSER_PART_NUMBER") "595-TLC59731DR")
      )
      (libsource (lib "eagle-import") (part "NEOPIXEL-TLC59731DR"))
    )
    (comp (ref "PIXEL_34")
      (value "NEOPIXEL-TLC59731DR")
      (footprint "eagle-import:SOIC127P600X175-8N")
      (fields
        (field (name "ARROW_PART_NUMBER") "TLC59731DR")
        (field (name "MOUSER_PART_NUMBER") "595-TLC59731DR")
      )
      (libsource (lib "eagle-import") (part "NEOPIXEL-TLC59731DR"))
    )
    (comp (ref "PIXEL_35")
      (value "NEOPIXEL-TLC59731DR")
      (footprint "eagle-import:SOIC127P600X175-8N")
      (fields
        (field (name "ARROW_PART_NUMBER") "TLC59731DR")
        (field (name "MOUSER_PART_NUMBER") "595-TLC59731DR")
      )
      (libsource (lib "eagle-import") (part "NEOPIXEL-TLC59731DR"))
    )
    (comp (ref "R3")
      (value "100")
      (footprint "eagle-import:1206")
      (libsource (lib "eagle-import") (part "PASSIF-RESISTOR-1206"))
    )
    (comp (ref "R4")
      (value "1k")
      (footprint "eagle-import:R0805")
      (libsource (lib "eagle-import") (part "R-US_R0805"))
    )
    (comp (ref "R5")
      (value "1k")
      (footprint "eagle-import:R0805")
      (libsource (lib "eagle-import") (part "R-US_R0805"))
    )
    (comp (ref "R6")
      (value "100")
      (footprint "eagle-import:1206")
      (libsource (lib "eagle-import") (part "PASSIF-RESISTOR-1206"))
    )
    (comp (ref "R7")
      (value "100")
      (footprint "eagle-import:1206")
      (libsource (lib "eagle-import") (part "PASSIF-RESISTOR-1206"))
    )
    (comp (ref "R8")
      (value "100")
      (footprint "eagle-import:1206")
      (libsource (lib "eagle-import") (part "PASSIF-RESISTOR-1206"))
    )
    (comp (ref "R9")
      (value "100")
      (footprint "eagle-import:1206")
      (libsource (lib "eagle-import") (part "PASSIF-RESISTOR-1206"))
    )
    (comp (ref "R10")
      (value "100")
      (footprint "eagle-import:1206")
      (libsource (lib "eagle-import") (part "PASSIF-RESISTOR-1206"))
    )
    (comp (ref "R11")
      (value "100")
      (footprint "eagle-import:1206")
      (libsource (lib "eagle-import") (part "PASSIF-RESISTOR-1206"))
    )
    (comp (ref "R12")
      (value "100")
      (footprint "eagle-import:1206")
      (libsource (lib "eagle-import") (part "PASSIF-RESISTOR-1206"))
    )
    (comp (ref "R13")
      (value "10k")
      (footprint "eagle-import:1206")
      (libsource (lib "eagle-import") (part "PASSIF-RESISTOR-1206"))
    )
    (comp (ref "R14")
      (value "470")
      (footprint "eagle-import:1206")
      (libsource (lib "eagle-import") (part "PASSIF-RESISTOR-1206"))
    )
    (comp (ref "R15")
      (value "470")
      (footprint "eagle-import:1206")
      (libsource (lib "eagle-import") (part "PASSIF-RESISTOR-1206"))
    )
    (comp (ref "R16")
      (value "470")
      (footprint "eagle-import:1206")
      (libsource (lib "eagle-import") (part "PASSIF-RESISTOR-1206"))
    )
    (comp (ref "R17")
      (value "100")
      (footprint "eagle-import:1206")
      (libsource (lib "eagle-import") (part "PASSIF-RESISTOR-1206"))
    )
    (comp (ref "R18")
      (value "100")
      (footprint "eagle-import:1206")
      (libsource (lib "eagle-import") (part "PASSIF-RESISTOR-1206"))
    )
    (comp (ref "R19")
      (value "100")
      (footprint "eagle-import:1206")
      (libsource (lib "eagle-import") (part "PASSIF-RESISTOR-1206"))
    )
    (comp (ref "R20")
      (value "10k")
      (footprint "eagle-import:1206")
      (libsource (lib "eagle-import") (part "PASSIF-RESISTOR-1206"))
    )
    (comp (ref "R21")
      (value "470")
      (footprint "eagle-import:1206")
      (libsource (lib "eagle-import") (part "PASSIF-RESISTOR-1206"))
    )
    (comp (ref "R22")
      (value "470")
      (footprint "eagle-import:1206")
      (libsource (lib "eagle-import") (part "PASSIF-RESISTOR-1206"))
    )
    (comp (ref "R23")
      (value "470")
      (footprint "eagle-import:1206")
      (libsource (lib "eagle-import") (part "PASSIF-RESISTOR-1206"))
    )
    (comp (ref "R24")
      (value "100")
      (footprint "eagle-import:1206")
      (libsource (lib "eagle-import") (part "PASSIF-RESISTOR-1206"))
    )
    (comp (ref "R25")
      (value "100")
      (footprint "eagle-import:1206")
      (libsource (lib "eagle-import") (part "PASSIF-RESISTOR-1206"))
    )
    (comp (ref "R26")
      (value "100")
      (footprint "eagle-import:1206")
      (libsource (lib "eagle-import") (part "PASSIF-RESISTOR-1206"))
    )
    (comp (ref "R27")
      (value "10k")
      (footprint "eagle-import:1206")
      (libsource (lib "eagle-import") (part "PASSIF-RESISTOR-1206"))
    )
    (comp (ref "R28")
      (value "470")
      (footprint "eagle-import:1206")
      (libsource (lib "eagle-import") (part "PASSIF-RESISTOR-1206"))
    )
    (comp (ref "R29")
      (value "470")
      (footprint "eagle-import:1206")
      (libsource (lib "eagle-import") (part "PASSIF-RESISTOR-1206"))
    )
    (comp (ref "R30")
      (value "470")
      (footprint "eagle-import:1206")
      (libsource (lib "eagle-import") (part "PASSIF-RESISTOR-1206"))
    )
    (comp (ref "R31")
      (value "100")
      (footprint "eagle-import:1206")
      (libsource (lib "eagle-import") (part "PASSIF-RESISTOR-1206"))
    )
    (comp (ref "R35")
      (value "100")
      (footprint "eagle-import:1206")
      (libsource (lib "eagle-import") (part "PASSIF-RESISTOR-1206"))
    )
    (comp (ref "R36")
      (value "100")
      (footprint "eagle-import:1206")
      (libsource (lib "eagle-import") (part "PASSIF-RESISTOR-1206"))
    )
    (comp (ref "R37")
      (value "100")
      (footprint "eagle-import:1206")
      (libsource (lib "eagle-import") (part "PASSIF-RESISTOR-1206"))
    )
    (comp (ref "R38")
      (value "100")
      (footprint "eagle-import:1206")
      (libsource (lib "eagle-import") (part "PASSIF-RESISTOR-1206"))
    )
    (comp (ref "R39")
      (value "100")
      (footprint "eagle-import:1206")
      (libsource (lib "eagle-import") (part "PASSIF-RESISTOR-1206"))
    )
    (comp (ref "R40")
      (value "100")
      (footprint "eagle-import:1206")
      (libsource (lib "eagle-import") (part "PASSIF-RESISTOR-1206"))
    )
    (comp (ref "R41")
      (value "10k")
      (footprint "eagle-import:1206")
      (libsource (lib "eagle-import") (part "PASSIF-RESISTOR-1206"))
    )
    (comp (ref "R42")
      (value "470")
      (footprint "eagle-import:1206")
      (libsource (lib "eagle-import") (part "PASSIF-RESISTOR-1206"))
    )
    (comp (ref "R43")
      (value "470")
      (footprint "eagle-import:1206")
      (libsource (lib "eagle-import") (part "PASSIF-RESISTOR-1206"))
    )
    (comp (ref "R44")
      (value "470")
      (footprint "eagle-import:1206")
      (libsource (lib "eagle-import") (part "PASSIF-RESISTOR-1206"))
    )
    (comp (ref "R48")
      (value "100")
      (footprint "eagle-import:1206")
      (libsource (lib "eagle-import") (part "PASSIF-RESISTOR-1206"))
    )
    (comp (ref "R49")
      (value "100")
      (footprint "eagle-import:1206")
      (libsource (lib "eagle-import") (part "PASSIF-RESISTOR-1206"))
    )
    (comp (ref "R50")
      (value "100")
      (footprint "eagle-import:1206")
      (libsource (lib "eagle-import") (part "PASSIF-RESISTOR-1206"))
    )
    (comp (ref "R52")
      (value "100")
      (footprint "eagle-import:1206")
      (libsource (lib "eagle-import") (part "PASSIF-RESISTOR-1206"))
    )
    (comp (ref "R53")
      (value "100")
      (footprint "eagle-import:1206")
      (libsource (lib "eagle-import") (part "PASSIF-RESISTOR-1206"))
    )
    (comp (ref "R54")
      (value "100")
      (footprint "eagle-import:1206")
      (libsource (lib "eagle-import") (part "PASSIF-RESISTOR-1206"))
    )
    (comp (ref "R55")
      (value "10k")
      (footprint "eagle-import:1206")
      (libsource (lib "eagle-import") (part "PASSIF-RESISTOR-1206"))
    )
    (comp (ref "R56")
      (value "470")
      (footprint "eagle-import:1206")
      (libsource (lib "eagle-import") (part "PASSIF-RESISTOR-1206"))
    )
    (comp (ref "R57")
      (value "470")
      (footprint "eagle-import:1206")
      (libsource (lib "eagle-import") (part "PASSIF-RESISTOR-1206"))
    )
    (comp (ref "R58")
      (value "470")
      (footprint "eagle-import:1206")
      (libsource (lib "eagle-import") (part "PASSIF-RESISTOR-1206"))
    )
    (comp (ref "R66")
      (value "100")
      (footprint "eagle-import:1206")
      (libsource (lib "eagle-import") (part "PASSIF-RESISTOR-1206"))
    )
    (comp (ref "R67")
      (value "100")
      (footprint "eagle-import:1206")
      (libsource (lib "eagle-import") (part "PASSIF-RESISTOR-1206"))
    )
    (comp (ref "R68")
      (value "100")
      (footprint "eagle-import:1206")
      (libsource (lib "eagle-import") (part "PASSIF-RESISTOR-1206"))
    )
    (comp (ref "R69")
      (value "10k")
      (footprint "eagle-import:1206")
      (libsource (lib "eagle-import") (part "PASSIF-RESISTOR-1206"))
    )
    (comp (ref "R70")
      (value "470")
      (footprint "eagle-import:1206")
      (libsource (lib "eagle-import") (part "PASSIF-RESISTOR-1206"))
    )
    (comp (ref "R71")
      (value "470")
      (footprint "eagle-import:1206")
      (libsource (lib "eagle-import") (part "PASSIF-RESISTOR-1206"))
    )
    (comp (ref "R72")
      (value "470")
      (footprint "eagle-import:1206")
      (libsource (lib "eagle-import") (part "PASSIF-RESISTOR-1206"))
    )
    (comp (ref "R82")
      (value "100")
      (footprint "eagle-import:1206")
      (libsource (lib "eagle-import") (part "PASSIF-RESISTOR-1206"))
    )
    (comp (ref "R84")
      (value "100")
      (footprint "eagle-import:1206")
      (libsource (lib "eagle-import") (part "PASSIF-RESISTOR-1206"))
    )
    (comp (ref "R85")
      (value "100")
      (footprint "eagle-import:1206")
      (libsource (lib "eagle-import") (part "PASSIF-RESISTOR-1206"))
    )
    (comp (ref "R88")
      (value "10k")
      (footprint "eagle-import:1206")
      (libsource (lib "eagle-import") (part "PASSIF-RESISTOR-1206"))
    )
    (comp (ref "R89")
      (value "470")
      (footprint "eagle-import:1206")
      (libsource (lib "eagle-import") (part "PASSIF-RESISTOR-1206"))
    )
    (comp (ref "R91")
      (value "470")
      (footprint "eagle-import:1206")
      (libsource (lib "eagle-import") (part "PASSIF-RESISTOR-1206"))
    )
    (comp (ref "R93")
      (value "470")
      (footprint "eagle-import:1206")
      (libsource (lib "eagle-import") (part "PASSIF-RESISTOR-1206"))
    )
    (comp (ref "R102")
      (value "100")
      (footprint "eagle-import:1206")
      (libsource (lib "eagle-import") (part "PASSIF-RESISTOR-1206"))
    )
    (comp (ref "R103")
      (value "100")
      (footprint "eagle-import:1206")
      (libsource (lib "eagle-import") (part "PASSIF-RESISTOR-1206"))
    )
    (comp (ref "R104")
      (value "100")
      (footprint "eagle-import:1206")
      (libsource (lib "eagle-import") (part "PASSIF-RESISTOR-1206"))
    )
    (comp (ref "R105")
      (value "10k")
      (footprint "eagle-import:1206")
      (libsource (lib "eagle-import") (part "PASSIF-RESISTOR-1206"))
    )
    (comp (ref "R106")
      (value "470")
      (footprint "eagle-import:1206")
      (libsource (lib "eagle-import") (part "PASSIF-RESISTOR-1206"))
    )
    (comp (ref "R107")
      (value "470")
      (footprint "eagle-import:1206")
      (libsource (lib "eagle-import") (part "PASSIF-RESISTOR-1206"))
    )
    (comp (ref "R108")
      (value "470")
      (footprint "eagle-import:1206")
      (libsource (lib "eagle-import") (part "PASSIF-RESISTOR-1206"))
    )
    (comp (ref "R116")
      (value "100")
      (footprint "eagle-import:1206")
      (libsource (lib "eagle-import") (part "PASSIF-RESISTOR-1206"))
    )
    (comp (ref "R117")
      (value "100")
      (footprint "eagle-import:1206")
      (libsource (lib "eagle-import") (part "PASSIF-RESISTOR-1206"))
    )
    (comp (ref "R118")
      (value "100")
      (footprint "eagle-import:1206")
      (libsource (lib "eagle-import") (part "PASSIF-RESISTOR-1206"))
    )
    (comp (ref "R119")
      (value "10k")
      (footprint "eagle-import:1206")
      (libsource (lib "eagle-import") (part "PASSIF-RESISTOR-1206"))
    )
    (comp (ref "R120")
      (value "470")
      (footprint "eagle-import:1206")
      (libsource (lib "eagle-import") (part "PASSIF-RESISTOR-1206"))
    )
    (comp (ref "R121")
      (value "470")
      (footprint "eagle-import:1206")
      (libsource (lib "eagle-import") (part "PASSIF-RESISTOR-1206"))
    )
    (comp (ref "R122")
      (value "470")
      (footprint "eagle-import:1206")
      (libsource (lib "eagle-import") (part "PASSIF-RESISTOR-1206"))
    )
    (comp (ref "R186")
      (value "1k")
      (footprint "eagle-import:R0805")
      (libsource (lib "eagle-import") (part "R-US_R0805"))
    )
    (comp (ref "R187")
      (value "1k")
      (footprint "eagle-import:R0805")
      (libsource (lib "eagle-import") (part "R-US_R0805"))
    )
    (comp (ref "RB1")
      (value "470")
      (footprint "eagle-import:1206")
      (libsource (lib "eagle-import") (part "PASSIF-RESISTOR-1206"))
    )
    (comp (ref "RB2")
      (value "470")
      (footprint "eagle-import:1206")
      (libsource (lib "eagle-import") (part "PASSIF-RESISTOR-1206"))
    )
    (comp (ref "RB4")
      (value "470")
      (footprint "eagle-import:1206")
      (libsource (lib "eagle-import") (part "PASSIF-RESISTOR-1206"))
    )
    (comp (ref "RB6")
      (value "470")
      (footprint "eagle-import:1206")
      (libsource (lib "eagle-import") (part "PASSIF-RESISTOR-1206"))
    )
    (comp (ref "S24")
      (value "ENCODER-RGB-SWITCH-NO_NUT")
      (footprint "eagle-import:ENCODER_LED_3")
      (libsource (lib "eagle-import") (part "ENCODER-RGB-SWITCH-NO_NUT"))
    )
    (comp (ref "S31")
      (value "ENCODER-RGB-SWITCH-NO_NUT")
      (footprint "eagle-import:ENCODER_LED_3")
      (libsource (lib "eagle-import") (part "ENCODER-RGB-SWITCH-NO_NUT"))
    )
    (comp (ref "S32")
      (value "B3F-1000")
      (footprint "eagle-import:B3F-1000")
      (fields
        (field (name "DIGI_KEY_PART_NUMBER") "SW400-ND")
        (field (name "MANUFACTURER") "Omron Electronics Inc-EMC Div")
        (field (name "CREATED_BY") "PCBLayout.com")
      )
      (libsource (lib "eagle-import") (part "B3F-1000"))
    )
    (comp (ref "S33")
      (value "B3F-1000")
      (footprint "eagle-import:B3F-1000")
      (fields
        (field (name "DIGI_KEY_PART_NUMBER") "SW400-ND")
        (field (name "MANUFACTURER") "Omron Electronics Inc-EMC Div")
        (field (name "CREATED_BY") "PCBLayout.com")
      )
      (libsource (lib "eagle-import") (part "B3F-1000"))
    )
    (comp (ref "S34")
      (value "ENCODER-RGB-SWITCH-NO_NUT")
      (footprint "eagle-import:ENCODER_LED_3")
      (libsource (lib "eagle-import") (part "ENCODER-RGB-SWITCH-NO_NUT"))
    )
    (comp (ref "S35")
      (value "ENCODER-RGB-SWITCH-NO_NUT")
      (footprint "eagle-import:ENCODER_LED_3")
      (libsource (lib "eagle-import") (part "ENCODER-RGB-SWITCH-NO_NUT"))
    )
    (comp (ref "S_12")
      (value "B3F-1000")
      (footprint "eagle-import:B3F-1000")
      (fields
        (field (name "DIGI_KEY_PART_NUMBER") "SW400-ND")
        (field (name "MANUFACTURER") "Omron Electronics Inc-EMC Div")
        (field (name "CREATED_BY") "PCBLayout.com")
      )
      (libsource (lib "eagle-import") (part "B3F-1000"))
    )
    (comp (ref "S_22")
      (value "B3F-1000")
      (footprint "eagle-import:B3F-1000")
      (fields
        (field (name "DIGI_KEY_PART_NUMBER") "SW400-ND")
        (field (name "MANUFACTURER") "Omron Electronics Inc-EMC Div")
        (field (name "CREATED_BY") "PCBLayout.com")
      )
      (libsource (lib "eagle-import") (part "B3F-1000"))
    )
    (comp (ref "CB3")
      (value "10n")
      (footprint "eagle-import:0805-CAP")
      (libsource (lib "eagle-import") (part "PASSIF-CAP-0805"))
    )
    (comp (ref "CB11")
      (value "10n")
      (footprint "eagle-import:0805-CAP")
      (libsource (lib "eagle-import") (part "PASSIF-CAP-0805"))
    )
    (comp (ref "CB12")
      (value "10n")
      (footprint "eagle-import:0805-CAP")
      (libsource (lib "eagle-import") (part "PASSIF-CAP-0805"))
    )
    (comp (ref "CB13")
      (value "10n")
      (footprint "eagle-import:0805-CAP")
      (libsource (lib "eagle-import") (part "PASSIF-CAP-0805"))
    )
    (comp (ref "CB17")
      (value "10n")
      (footprint "eagle-import:0805-CAP")
      (libsource (lib "eagle-import") (part "PASSIF-CAP-0805"))
    )
    (comp (ref "CB18")
      (value "10n")
      (footprint "eagle-import:0805-CAP")
      (libsource (lib "eagle-import") (part "PASSIF-CAP-0805"))
    )
    (comp (ref "CB19")
      (value "10n")
      (footprint "eagle-import:0805-CAP")
      (libsource (lib "eagle-import") (part "PASSIF-CAP-0805"))
    )
    (comp (ref "CB23")
      (value "10n")
      (footprint "eagle-import:0805-CAP")
      (libsource (lib "eagle-import") (part "PASSIF-CAP-0805"))
    )
    (comp (ref "CB24")
      (value "10n")
      (footprint "eagle-import:0805-CAP")
      (libsource (lib "eagle-import") (part "PASSIF-CAP-0805"))
    )
    (comp (ref "CB25")
      (value "10n")
      (footprint "eagle-import:0805-CAP")
      (libsource (lib "eagle-import") (part "PASSIF-CAP-0805"))
    )
    (comp (ref "CB29")
      (value "10n")
      (footprint "eagle-import:0805-CAP")
      (libsource (lib "eagle-import") (part "PASSIF-CAP-0805"))
    )
    (comp (ref "CB30")
      (value "10n")
      (footprint "eagle-import:0805-CAP")
      (libsource (lib "eagle-import") (part "PASSIF-CAP-0805"))
    )
    (comp (ref "CB31")
      (value "10n")
      (footprint "eagle-import:0805-CAP")
      (libsource (lib "eagle-import") (part "PASSIF-CAP-0805"))
    )
    (comp (ref "CB45")
      (value "10n")
      (footprint "eagle-import:0805-CAP")
      (libsource (lib "eagle-import") (part "PASSIF-CAP-0805"))
    )
    (comp (ref "CB68")
      (value "10n")
      (footprint "eagle-import:0805-CAP")
      (libsource (lib "eagle-import") (part "PASSIF-CAP-0805"))
    )
    (comp (ref "CB70")
      (value "10n")
      (footprint "eagle-import:0805-CAP")
      (libsource (lib "eagle-import") (part "PASSIF-CAP-0805"))
    )
    (comp (ref "CDEC2")
      (value "10u")
      (footprint "eagle-import:CPOL2917")
      (libsource (lib "eagle-import") (part "PASSIF-CPOL-US2917"))
    )
    (comp (ref "CDEC4")
      (value "10u")
      (footprint "eagle-import:CPOL2917")
      (libsource (lib "eagle-import") (part "PASSIF-CPOL-US2917"))
    )
    (comp (ref "CDEC6")
      (value "10u")
      (footprint "eagle-import:CPOL2917")
      (libsource (lib "eagle-import") (part "PASSIF-CPOL-US2917"))
    )
    (comp (ref "CDEC8")
      (value "10u")
      (footprint "eagle-import:CPOL2917")
      (libsource (lib "eagle-import") (part "PASSIF-CPOL-US2917"))
    )
    (comp (ref "CDEC13")
      (value "100n")
      (footprint "eagle-import:0805-CAP")
      (libsource (lib "eagle-import") (part "PASSIF-CAP-0805"))
    )
    (comp (ref "CDEC32")
      (value "100n")
      (footprint "eagle-import:0805-CAP")
      (libsource (lib "eagle-import") (part "PASSIF-CAP-0805"))
    )
    (comp (ref "CDEC36")
      (value "100n")
      (footprint "eagle-import:0805-CAP")
      (libsource (lib "eagle-import") (part "PASSIF-CAP-0805"))
    )
    (comp (ref "CDEC39")
      (value "100n")
      (footprint "eagle-import:0805-CAP")
      (libsource (lib "eagle-import") (part "PASSIF-CAP-0805"))
    )
    (comp (ref "CDEC_2A1")
      (value "10u")
      (footprint "eagle-import:CPOL2917")
      (libsource (lib "eagle-import") (part "PASSIF-CPOL-US2917"))
    )
    (comp (ref "CDEC_2B1")
      (value "100n")
      (footprint "eagle-import:0805-CAP")
      (libsource (lib "eagle-import") (part "PASSIF-CAP-0805"))
    )
    (comp (ref "CPOL2")
      (value "100n")
      (footprint "eagle-import:0805-CAP")
      (libsource (lib "eagle-import") (part "PASSIF-CAP-0805"))
    )
    (comp (ref "CPOL4")
      (value "100n")
      (footprint "eagle-import:0805-CAP")
      (libsource (lib "eagle-import") (part "PASSIF-CAP-0805"))
    )
    (comp (ref "CPOL6")
      (value "100n")
      (footprint "eagle-import:0805-CAP")
      (libsource (lib "eagle-import") (part "PASSIF-CAP-0805"))
    )
    (comp (ref "CPOL8")
      (value "100n")
      (footprint "eagle-import:0805-CAP")
      (libsource (lib "eagle-import") (part "PASSIF-CAP-0805"))
    )
    (comp (ref "CPOL13")
      (value "10u")
      (footprint "eagle-import:CPOL2917")
      (libsource (lib "eagle-import") (part "PASSIF-CPOL-US2917"))
    )
    (comp (ref "CPOL32")
      (value "10u")
      (footprint "eagle-import:CPOL2917")
      (libsource (lib "eagle-import") (part "PASSIF-CPOL-US2917"))
    )
    (comp (ref "CPOL36")
      (value "10u")
      (footprint "eagle-import:CPOL2917")
      (libsource (lib "eagle-import") (part "PASSIF-CPOL-US2917"))
    )
    (comp (ref "CPOL39")
      (value "10u")
      (footprint "eagle-import:CPOL2917")
      (libsource (lib "eagle-import") (part "PASSIF-CPOL-US2917"))
    )
    (comp (ref "ENC_41")
      (value "ENCODER-RGB-SWITCH-NO_NUT")
      (footprint "eagle-import:ENCODER_LED_3")
      (libsource (lib "eagle-import") (part "ENCODER-RGB-SWITCH-NO_NUT"))
    )
    (comp (ref "ENC_44")
      (value "ENCODER-RGB-SWITCH-NO_NUT")
      (footprint "eagle-import:ENCODER_LED_3")
      (libsource (lib "eagle-import") (part "ENCODER-RGB-SWITCH-NO_NUT"))
    )
    (comp (ref "ENC_45")
      (value "ENCODER-RGB-SWITCH-NO_NUT")
      (footprint "eagle-import:ENCODER_LED_3")
      (libsource (lib "eagle-import") (part "ENCODER-RGB-SWITCH-NO_NUT"))
    )
    (comp (ref "ENC_48")
      (value "ENCODER-RGB-SWITCH-NO_NUT")
      (footprint "eagle-import:ENCODER_LED_3")
      (libsource (lib "eagle-import") (part "ENCODER-RGB-SWITCH-NO_NUT"))
    )
    (comp (ref "LED_42")
      (value "CZXR-80RGB03-A")
      (footprint "eagle-import:LED4-2.0-D8.0MM")
      (libsource (lib "eagle-import") (part "DIP-LED-RGB-COMMON-ANODE(4P-D8MM)"))
    )
    (comp (ref "LED_43")
      (value "CZXR-80RGB03-A")
      (footprint "eagle-import:LED4-2.0-D8.0MM")
      (libsource (lib "eagle-import") (part "DIP-LED-RGB-COMMON-ANODE(4P-D8MM)"))
    )
    (comp (ref "LED_46")
      (value "CZXR-80RGB03-A")
      (footprint "eagle-import:LED4-2.0-D8.0MM")
      (libsource (lib "eagle-import") (part "DIP-LED-RGB-COMMON-ANODE(4P-D8MM)"))
    )
    (comp (ref "LED_47")
      (value "CZXR-80RGB03-A")
      (footprint "eagle-import:LED4-2.0-D8.0MM")
      (libsource (lib "eagle-import") (part "DIP-LED-RGB-COMMON-ANODE(4P-D8MM)"))
    )
    (comp (ref "MCP_010")
      (value "MCP23017")
      (footprint "eagle-import:SOIC-28")
      (libsource (lib "eagle-import") (part "MCP23017"))
    )
    (comp (ref "PIXEL_41")
      (value "NEOPIXEL-TLC59731DR")
      (footprint "eagle-import:SOIC127P600X175-8N")
      (fields
        (field (name "ARROW_PART_NUMBER") "TLC59731DR")
        (field (name "MOUSER_PART_NUMBER") "595-TLC59731DR")
      )
      (libsource (lib "eagle-import") (part "NEOPIXEL-TLC59731DR"))
    )
    (comp (ref "PIXEL_42")
      (value "NEOPIXEL-TLC59731DR")
      (footprint "eagle-import:SOIC127P600X175-8N")
      (fields
        (field (name "ARROW_PART_NUMBER") "TLC59731DR")
        (field (name "MOUSER_PART_NUMBER") "595-TLC59731DR")
      )
      (libsource (lib "eagle-import") (part "NEOPIXEL-TLC59731DR"))
    )
    (comp (ref "PIXEL_43")
      (value "NEOPIXEL-TLC59731DR")
      (footprint "eagle-import:SOIC127P600X175-8N")
      (fields
        (field (name "ARROW_PART_NUMBER") "TLC59731DR")
        (field (name "MOUSER_PART_NUMBER") "595-TLC59731DR")
      )
      (libsource (lib "eagle-import") (part "NEOPIXEL-TLC59731DR"))
    )
    (comp (ref "PIXEL_44")
      (value "NEOPIXEL-TLC59731DR")
      (footprint "eagle-import:SOIC127P600X175-8N")
      (fields
        (field (name "ARROW_PART_NUMBER") "TLC59731DR")
        (field (name "MOUSER_PART_NUMBER") "595-TLC59731DR")
      )
      (libsource (lib "eagle-import") (part "NEOPIXEL-TLC59731DR"))
    )
    (comp (ref "PIXEL_45")
      (value "NEOPIXEL-TLC59731DR")
      (footprint "eagle-import:SOIC127P600X175-8N")
      (fields
        (field (name "ARROW_PART_NUMBER") "TLC59731DR")
        (field (name "MOUSER_PART_NUMBER") "595-TLC59731DR")
      )
      (libsource (lib "eagle-import") (part "NEOPIXEL-TLC59731DR"))
    )
    (comp (ref "PIXEL_46")
      (value "NEOPIXEL-TLC59731DR")
      (footprint "eagle-import:SOIC127P600X175-8N")
      (fields
        (field (name "ARROW_PART_NUMBER") "TLC59731DR")
        (field (name "MOUSER_PART_NUMBER") "595-TLC59731DR")
      )
      (libsource (lib "eagle-import") (part "NEOPIXEL-TLC59731DR"))
    )
    (comp (ref "PIXEL_47")
      (value "NEOPIXEL-TLC59731DR")
      (footprint "eagle-import:SOIC127P600X175-8N")
      (fields
        (field (name "ARROW_PART_NUMBER") "TLC59731DR")
        (field (name "MOUSER_PART_NUMBER") "595-TLC59731DR")
      )
      (libsource (lib "eagle-import") (part "NEOPIXEL-TLC59731DR"))
    )
    (comp (ref "PIXEL_48")
      (value "NEOPIXEL-TLC59731DR")
      (footprint "eagle-import:SOIC127P600X175-8N")
      (fields
        (field (name "ARROW_PART_NUMBER") "TLC59731DR")
        (field (name "MOUSER_PART_NUMBER") "595-TLC59731DR")
      )
      (libsource (lib "eagle-import") (part "NEOPIXEL-TLC59731DR"))
    )
    (comp (ref "R1")
      (value "1k")
      (footprint "eagle-import:R0805")
      (libsource (lib "eagle-import") (part "R-US_R0805"))
    )
    (comp (ref "R2")
      (value "1k")
      (footprint "eagle-import:R0805")
      (libsource (lib "eagle-import") (part "R-US_R0805"))
    )
    (comp (ref "R32")
      (value "100")
      (footprint "eagle-import:1206")
      (libsource (lib "eagle-import") (part "PASSIF-RESISTOR-1206"))
    )
    (comp (ref "R46")
      (value "100")
      (footprint "eagle-import:1206")
      (libsource (lib "eagle-import") (part "PASSIF-RESISTOR-1206"))
    )
    (comp (ref "R47")
      (value "100")
      (footprint "eagle-import:1206")
      (libsource (lib "eagle-import") (part "PASSIF-RESISTOR-1206"))
    )
    (comp (ref "R51")
      (value "100")
      (footprint "eagle-import:1206")
      (libsource (lib "eagle-import") (part "PASSIF-RESISTOR-1206"))
    )
    (comp (ref "R62")
      (value "100")
      (footprint "eagle-import:1206")
      (libsource (lib "eagle-import") (part "PASSIF-RESISTOR-1206"))
    )
    (comp (ref "R63")
      (value "100")
      (footprint "eagle-import:1206")
      (libsource (lib "eagle-import") (part "PASSIF-RESISTOR-1206"))
    )
    (comp (ref "R64")
      (value "100")
      (footprint "eagle-import:1206")
      (libsource (lib "eagle-import") (part "PASSIF-RESISTOR-1206"))
    )
    (comp (ref "R75")
      (value "100")
      (footprint "eagle-import:1206")
      (libsource (lib "eagle-import") (part "PASSIF-RESISTOR-1206"))
    )
    (comp (ref "R76")
      (value "100")
      (footprint "eagle-import:1206")
      (libsource (lib "eagle-import") (part "PASSIF-RESISTOR-1206"))
    )
    (comp (ref "R77")
      (value "100")
      (footprint "eagle-import:1206")
      (libsource (lib "eagle-import") (part "PASSIF-RESISTOR-1206"))
    )
    (comp (ref "R86")
      (value "100")
      (footprint "eagle-import:1206")
      (libsource (lib "eagle-import") (part "PASSIF-RESISTOR-1206"))
    )
    (comp (ref "R94")
      (value "100")
      (footprint "eagle-import:1206")
      (libsource (lib "eagle-import") (part "PASSIF-RESISTOR-1206"))
    )
    (comp (ref "R96")
      (value "100")
      (footprint "eagle-import:1206")
      (libsource (lib "eagle-import") (part "PASSIF-RESISTOR-1206"))
    )
    (comp (ref "R123")
      (value "100")
      (footprint "eagle-import:1206")
      (libsource (lib "eagle-import") (part "PASSIF-RESISTOR-1206"))
    )
    (comp (ref "R124")
      (value "100")
      (footprint "eagle-import:1206")
      (libsource (lib "eagle-import") (part "PASSIF-RESISTOR-1206"))
    )
    (comp (ref "R176")
      (value "100")
      (footprint "eagle-import:1206")
      (libsource (lib "eagle-import") (part "PASSIF-RESISTOR-1206"))
    )
    (comp (ref "R180")
      (value "100")
      (footprint "eagle-import:1206")
      (libsource (lib "eagle-import") (part "PASSIF-RESISTOR-1206"))
    )
    (comp (ref "R181")
      (value "100")
      (footprint "eagle-import:1206")
      (libsource (lib "eagle-import") (part "PASSIF-RESISTOR-1206"))
    )
    (comp (ref "R188")
      (value "100")
      (footprint "eagle-import:1206")
      (libsource (lib "eagle-import") (part "PASSIF-RESISTOR-1206"))
    )
    (comp (ref "R192")
      (value "100")
      (footprint "eagle-import:1206")
      (libsource (lib "eagle-import") (part "PASSIF-RESISTOR-1206"))
    )
    (comp (ref "R193")
      (value "100")
      (footprint "eagle-import:1206")
      (libsource (lib "eagle-import") (part "PASSIF-RESISTOR-1206"))
    )
    (comp (ref "R200")
      (value "100")
      (footprint "eagle-import:1206")
      (libsource (lib "eagle-import") (part "PASSIF-RESISTOR-1206"))
    )
    (comp (ref "R201")
      (value "100")
      (footprint "eagle-import:1206")
      (libsource (lib "eagle-import") (part "PASSIF-RESISTOR-1206"))
    )
    (comp (ref "R202")
      (value "100")
      (footprint "eagle-import:1206")
      (libsource (lib "eagle-import") (part "PASSIF-RESISTOR-1206"))
    )
    (comp (ref "RB3")
      (value "470")
      (footprint "eagle-import:1206")
      (libsource (lib "eagle-import") (part "PASSIF-RESISTOR-1206"))
    )
    (comp (ref "RB11")
      (value "470")
      (footprint "eagle-import:1206")
      (libsource (lib "eagle-import") (part "PASSIF-RESISTOR-1206"))
    )
    (comp (ref "RB12")
      (value "470")
      (footprint "eagle-import:1206")
      (libsource (lib "eagle-import") (part "PASSIF-RESISTOR-1206"))
    )
    (comp (ref "RB13")
      (value "470")
      (footprint "eagle-import:1206")
      (libsource (lib "eagle-import") (part "PASSIF-RESISTOR-1206"))
    )
    (comp (ref "RB17")
      (value "470")
      (footprint "eagle-import:1206")
      (libsource (lib "eagle-import") (part "PASSIF-RESISTOR-1206"))
    )
    (comp (ref "RB18")
      (value "470")
      (footprint "eagle-import:1206")
      (libsource (lib "eagle-import") (part "PASSIF-RESISTOR-1206"))
    )
    (comp (ref "RB19")
      (value "470")
      (footprint "eagle-import:1206")
      (libsource (lib "eagle-import") (part "PASSIF-RESISTOR-1206"))
    )
    (comp (ref "RB23")
      (value "470")
      (footprint "eagle-import:1206")
      (libsource (lib "eagle-import") (part "PASSIF-RESISTOR-1206"))
    )
    (comp (ref "RB24")
      (value "470")
      (footprint "eagle-import:1206")
      (libsource (lib "eagle-import") (part "PASSIF-RESISTOR-1206"))
    )
    (comp (ref "RB25")
      (value "470")
      (footprint "eagle-import:1206")
      (libsource (lib "eagle-import") (part "PASSIF-RESISTOR-1206"))
    )
    (comp (ref "RB29")
      (value "470")
      (footprint "eagle-import:1206")
      (libsource (lib "eagle-import") (part "PASSIF-RESISTOR-1206"))
    )
    (comp (ref "RB30")
      (value "470")
      (footprint "eagle-import:1206")
      (libsource (lib "eagle-import") (part "PASSIF-RESISTOR-1206"))
    )
    (comp (ref "RB31")
      (value "470")
      (footprint "eagle-import:1206")
      (libsource (lib "eagle-import") (part "PASSIF-RESISTOR-1206"))
    )
    (comp (ref "RB45")
      (value "470")
      (footprint "eagle-import:1206")
      (libsource (lib "eagle-import") (part "PASSIF-RESISTOR-1206"))
    )
    (comp (ref "RB68")
      (value "470")
      (footprint "eagle-import:1206")
      (libsource (lib "eagle-import") (part "PASSIF-RESISTOR-1206"))
    )
    (comp (ref "RB70")
      (value "470")
      (footprint "eagle-import:1206")
      (libsource (lib "eagle-import") (part "PASSIF-RESISTOR-1206"))
    )
    (comp (ref "RPD2")
      (value "10k")
      (footprint "eagle-import:1206")
      (libsource (lib "eagle-import") (part "PASSIF-RESISTOR-1206"))
    )
    (comp (ref "RPD4")
      (value "10k")
      (footprint "eagle-import:1206")
      (libsource (lib "eagle-import") (part "PASSIF-RESISTOR-1206"))
    )
    (comp (ref "RPD6")
      (value "10k")
      (footprint "eagle-import:1206")
      (libsource (lib "eagle-import") (part "PASSIF-RESISTOR-1206"))
    )
    (comp (ref "RPD8")
      (value "10k")
      (footprint "eagle-import:1206")
      (libsource (lib "eagle-import") (part "PASSIF-RESISTOR-1206"))
    )
    (comp (ref "SW_42")
      (value "B3F-1000")
      (footprint "eagle-import:B3F-1000")
      (fields
        (field (name "DIGI_KEY_PART_NUMBER") "SW400-ND")
        (field (name "MANUFACTURER") "Omron Electronics Inc-EMC Div")
        (field (name "CREATED_BY") "PCBLayout.com")
      )
      (libsource (lib "eagle-import") (part "B3F-1000"))
    )
    (comp (ref "SW_43")
      (value "B3F-1000")
      (footprint "eagle-import:B3F-1000")
      (fields
        (field (name "DIGI_KEY_PART_NUMBER") "SW400-ND")
        (field (name "MANUFACTURER") "Omron Electronics Inc-EMC Div")
        (field (name "CREATED_BY") "PCBLayout.com")
      )
      (libsource (lib "eagle-import") (part "B3F-1000"))
    )
    (comp (ref "SW_46")
      (value "B3F-1000")
      (footprint "eagle-import:B3F-1000")
      (fields
        (field (name "DIGI_KEY_PART_NUMBER") "SW400-ND")
        (field (name "MANUFACTURER") "Omron Electronics Inc-EMC Div")
        (field (name "CREATED_BY") "PCBLayout.com")
      )
      (libsource (lib "eagle-import") (part "B3F-1000"))
    )
    (comp (ref "SW_47")
      (value "B3F-1000")
      (footprint "eagle-import:B3F-1000")
      (fields
        (field (name "DIGI_KEY_PART_NUMBER") "SW400-ND")
        (field (name "MANUFACTURER") "Omron Electronics Inc-EMC Div")
        (field (name "CREATED_BY") "PCBLayout.com")
      )
      (libsource (lib "eagle-import") (part "B3F-1000"))
    )
    (comp (ref "0V/5V")
      (value "PINHEADER-M04PL")
      (footprint "eagle-import:MA04-1")
      (libsource (lib "eagle-import") (part "PINHEADER-M04PL"))
    )
    (comp (ref "ANALOG_IN")
      (value "MA04-1")
      (footprint "eagle-import:MA04-1")
      (libsource (lib "eagle-import") (part "MA04-1"))
    )
    (comp (ref "C55")
      (value "0.1uF")
      (footprint "eagle-import:C0805")
      (libsource (lib "eagle-import") (part "C-US0805"))
    )
    (comp (ref "C60")
      (value "2.2uF")
      (footprint "eagle-import:C0805")
      (libsource (lib "eagle-import") (part "C-US0805"))
    )
    (comp (ref "C62")
      (value "10u")
      (footprint "eagle-import:CPOL2917")
      (libsource (lib "eagle-import") (part "CPOL-US2917"))
    )
    (comp (ref "C65")
      (value "100 uF")
      (footprint "eagle-import:CPOL2917")
      (libsource (lib "eagle-import") (part "CPOL-US2917"))
    )
    (comp (ref "C66")
      (value "0.1uF")
      (footprint "eagle-import:C0805")
      (libsource (lib "eagle-import") (part "C-US0805"))
    )
    (comp (ref "C67")
      (value "0.1uF")
      (footprint "eagle-import:C0805")
      (libsource (lib "eagle-import") (part "C-US0805"))
    )
    (comp (ref "C68")
      (value "0.1uF")
      (footprint "eagle-import:C0805")
      (libsource (lib "eagle-import") (part "C-US0805"))
    )
    (comp (ref "C69")
      (value "0.1uF")
      (footprint "eagle-import:C0805")
      (libsource (lib "eagle-import") (part "C-US0805"))
    )
    (comp (ref "C70")
      (value "0.1uF")
      (footprint "eagle-import:C0805")
      (libsource (lib "eagle-import") (part "C-US0805"))
    )
    (comp (ref "C71")
      (value "1.0uF")
      (footprint "eagle-import:C0805")
      (libsource (lib "eagle-import") (part "C-US0805"))
    )
    (comp (ref "C76")
      (value "1u")
      (footprint "eagle-import:C1206")
      (libsource (lib "eagle-import") (part "C-EUC1206"))
    )
    (comp (ref "CONN_STH_BRD_1")
      (value "MA10-2")
      (footprint "eagle-import:MA10-2")
      (libsource (lib "eagle-import") (part "MA10-2"))
    )
    (comp (ref "F446")
      (value "STM32F446RCT7")
      (footprint "eagle-import:QFP50P1200X1200X160-64N")
      (fields (field (name "MF") "STMicroelectronics"))
      (libsource (lib "eagle-import") (part "STM32F446RCT7"))
    )
    (comp (ref "GREEN")
      (value "LED-0805")
      (footprint "eagle-import:0805-LED")
      (libsource (lib "eagle-import") (part "LED-0805"))
    )
    (comp (ref "L1")
      (value "1 uH")
      (footprint "eagle-import:L0805")
      (libsource (lib "eagle-import") (part "L-USL0805"))
    )
    (comp (ref "LED_3V3")
      (value "LED-0805")
      (footprint "eagle-import:0805-LED")
      (libsource (lib "eagle-import") (part "LED-0805"))
    )
    (comp (ref "LED_5V")
      (value "LED-0603")
      (footprint "eagle-import:0603-LED")
      (libsource (lib "eagle-import") (part "LED-0603"))
    )
    (comp (ref "R79")
      (value "100k")
      (footprint "eagle-import:R0805")
      (libsource (lib "eagle-import") (part "R-US0805"))
    )
    (comp (ref "R81")
      (value "10K")
      (footprint "eagle-import:R0805")
      (libsource (lib "eagle-import") (part "R-US0805"))
    )
    (comp (ref "R87")
      (value "1")
      (footprint "eagle-import:R0805")
      (libsource (lib "eagle-import") (part "R-US0805"))
    )
    (comp (ref "R90")
      (value "1k")
      (footprint "eagle-import:R0805")
      (libsource (lib "eagle-import") (part "R-US0805"))
    )
    (comp (ref "R92")
      (value "470")
      (footprint "eagle-import:R0805")
      (libsource (lib "eagle-import") (part "R-US0805"))
    )
    (comp (ref "R95")
      (value "1k")
      (footprint "eagle-import:R0805")
      (libsource (lib "eagle-import") (part "R-US0805"))
    )
    (comp (ref "S2")
      (value "SWITCH-SKRKAEE020")
      (footprint "eagle-import:SKRKAEE020")
      (fields
        (field (name "MANUFACTURER_PART_NUMBER") "SKRKAEE020")
        (field (name "MOUSER_PART_NUMBER") "688-SKRKAEE020")
      )
      (libsource (lib "eagle-import") (part "SWITCH-SKRKAEE020"))
    )
    (comp (ref "STLINK")
      (value "75867-331LF")
      (footprint "eagle-import:MA03-2")
      (libsource (lib "eagle-import") (part "MA03-2"))
    )
    (comp (ref "TLV75533")
      (value "TLV75533PDBVR")
      (footprint "eagle-import:SOT95P280X145-5N")
      (fields (field (name "MF") "Texas Instruments"))
      (libsource (lib "eagle-import") (part "TLV75533PDBVR"))
    )
    (comp (ref "UART_ANALOG")
      (value "MA03-1")
      (footprint "eagle-import:MA03-1")
      (libsource (lib "eagle-import") (part "MA03-1"))
    )
    (comp (ref "UART_DISCO")
      (value "MA03-1")
      (footprint "eagle-import:MA03-1")
      (libsource (lib "eagle-import") (part "MA03-1"))
    )
    (comp (ref "UART_MIDI")
      (value "MA03-1")
      (footprint "eagle-import:MA03-1")
      (libsource (lib "eagle-import") (part "MA03-1"))
    )
    (comp (ref "CB32")
      (value "10n")
      (footprint "eagle-import:0805-CAP")
      (libsource (lib "eagle-import") (part "PASSIF-CAP-0805"))
    )
    (comp (ref "CB33")
      (value "10n")
      (footprint "eagle-import:0805-CAP")
      (libsource (lib "eagle-import") (part "PASSIF-CAP-0805"))
    )
    (comp (ref "CB34")
      (value "10n")
      (footprint "eagle-import:0805-CAP")
      (libsource (lib "eagle-import") (part "PASSIF-CAP-0805"))
    )
    (comp (ref "CB56")
      (value "10n")
      (footprint "eagle-import:0805-CAP")
      (libsource (lib "eagle-import") (part "PASSIF-CAP-0805"))
    )
    (comp (ref "CB57")
      (value "10n")
      (footprint "eagle-import:0805-CAP")
      (libsource (lib "eagle-import") (part "PASSIF-CAP-0805"))
    )
    (comp (ref "CB58")
      (value "10n")
      (footprint "eagle-import:0805-CAP")
      (libsource (lib "eagle-import") (part "PASSIF-CAP-0805"))
    )
    (comp (ref "CB80")
      (value "10n")
      (footprint "eagle-import:0805-CAP")
      (libsource (lib "eagle-import") (part "PASSIF-CAP-0805"))
    )
    (comp (ref "CB81")
      (value "10n")
      (footprint "eagle-import:0805-CAP")
      (libsource (lib "eagle-import") (part "PASSIF-CAP-0805"))
    )
    (comp (ref "CB82")
      (value "10n")
      (footprint "eagle-import:0805-CAP")
      (libsource (lib "eagle-import") (part "PASSIF-CAP-0805"))
    )
    (comp (ref "CB92")
      (value "10n")
      (footprint "eagle-import:0805-CAP")
      (libsource (lib "eagle-import") (part "PASSIF-CAP-0805"))
    )
    (comp (ref "CB93")
      (value "10n")
      (footprint "eagle-import:0805-CAP")
      (libsource (lib "eagle-import") (part "PASSIF-CAP-0805"))
    )
    (comp (ref "CB94")
      (value "10n")
      (footprint "eagle-import:0805-CAP")
      (libsource (lib "eagle-import") (part "PASSIF-CAP-0805"))
    )
    (comp (ref "CB98")
      (value "10n")
      (footprint "eagle-import:0805-CAP")
      (libsource (lib "eagle-import") (part "PASSIF-CAP-0805"))
    )
    (comp (ref "CB99")
      (value "10n")
      (footprint "eagle-import:0805-CAP")
      (libsource (lib "eagle-import") (part "PASSIF-CAP-0805"))
    )
    (comp (ref "CB100")
      (value "10n")
      (footprint "eagle-import:0805-CAP")
      (libsource (lib "eagle-import") (part "PASSIF-CAP-0805"))
    )
    (comp (ref "CDEC9")
      (value "10u")
      (footprint "eagle-import:CPOL2917")
      (libsource (lib "eagle-import") (part "PASSIF-CPOL-US2917"))
    )
    (comp (ref "CDEC17")
      (value "10u")
      (footprint "eagle-import:CPOL2917")
      (libsource (lib "eagle-import") (part "PASSIF-CPOL-US2917"))
    )
    (comp (ref "CDEC25")
      (value "10u")
      (footprint "eagle-import:CPOL2917")
      (libsource (lib "eagle-import") (part "PASSIF-CPOL-US2917"))
    )
    (comp (ref "CDEC29")
      (value "10u")
      (footprint "eagle-import:CPOL2917")
      (libsource (lib "eagle-import") (part "PASSIF-CPOL-US2917"))
    )
    (comp (ref "CDEC31")
      (value "10u")
      (footprint "eagle-import:CPOL2917")
      (libsource (lib "eagle-import") (part "PASSIF-CPOL-US2917"))
    )
    (comp (ref "CDEC_5A")
      (value "10u")
      (footprint "eagle-import:CPOL2917")
      (libsource (lib "eagle-import") (part "PASSIF-CPOL-US2917"))
    )
    (comp (ref "CDEC_5B")
      (value "100n")
      (footprint "eagle-import:0805-CAP")
      (libsource (lib "eagle-import") (part "PASSIF-CAP-0805"))
    )
    (comp (ref "CPOL9")
      (value "100n")
      (footprint "eagle-import:0805-CAP")
      (libsource (lib "eagle-import") (part "PASSIF-CAP-0805"))
    )
    (comp (ref "CPOL17")
      (value "100n")
      (footprint "eagle-import:0805-CAP")
      (libsource (lib "eagle-import") (part "PASSIF-CAP-0805"))
    )
    (comp (ref "CPOL25")
      (value "100n")
      (footprint "eagle-import:0805-CAP")
      (libsource (lib "eagle-import") (part "PASSIF-CAP-0805"))
    )
    (comp (ref "CPOL29")
      (value "100n")
      (footprint "eagle-import:0805-CAP")
      (libsource (lib "eagle-import") (part "PASSIF-CAP-0805"))
    )
    (comp (ref "CPOL31")
      (value "100n")
      (footprint "eagle-import:0805-CAP")
      (libsource (lib "eagle-import") (part "PASSIF-CAP-0805"))
    )
    (comp (ref "ENC_71")
      (value "ENCODER-RGB-SWITCH-NO_NUT")
      (footprint "eagle-import:ENCODER_LED_3")
      (libsource (lib "eagle-import") (part "ENCODER-RGB-SWITCH-NO_NUT"))
    )
    (comp (ref "ENC_72")
      (value "ENCODER-RGB-SWITCH-NO_NUT")
      (footprint "eagle-import:ENCODER_LED_3")
      (libsource (lib "eagle-import") (part "ENCODER-RGB-SWITCH-NO_NUT"))
    )
    (comp (ref "ENC_73")
      (value "ENCODER-RGB-SWITCH-NO_NUT")
      (footprint "eagle-import:ENCODER_LED_3")
      (libsource (lib "eagle-import") (part "ENCODER-RGB-SWITCH-NO_NUT"))
    )
    (comp (ref "ENC_74")
      (value "ENCODER-RGB-SWITCH-NO_NUT")
      (footprint "eagle-import:ENCODER_LED_3")
      (libsource (lib "eagle-import") (part "ENCODER-RGB-SWITCH-NO_NUT"))
    )
    (comp (ref "ENC_75")
      (value "ENCODER-RGB-SWITCH-NO_NUT")
      (footprint "eagle-import:ENCODER_LED_3")
      (libsource (lib "eagle-import") (part "ENCODER-RGB-SWITCH-NO_NUT"))
    )
    (comp (ref "MCP_111")
      (value "MCP23017")
      (footprint "eagle-import:SOIC-28")
      (libsource (lib "eagle-import") (part "MCP23017"))
    )
    (comp (ref "PIXEL_71")
      (value "NEOPIXEL-TLC59731DR")
      (footprint "eagle-import:SOIC127P600X175-8N")
      (fields
        (field (name "ARROW_PART_NUMBER") "TLC59731DR")
        (field (name "MOUSER_PART_NUMBER") "595-TLC59731DR")
      )
      (libsource (lib "eagle-import") (part "NEOPIXEL-TLC59731DR"))
    )
    (comp (ref "PIXEL_72")
      (value "NEOPIXEL-TLC59731DR")
      (footprint "eagle-import:SOIC127P600X175-8N")
      (fields
        (field (name "ARROW_PART_NUMBER") "TLC59731DR")
        (field (name "MOUSER_PART_NUMBER") "595-TLC59731DR")
      )
      (libsource (lib "eagle-import") (part "NEOPIXEL-TLC59731DR"))
    )
    (comp (ref "PIXEL_73")
      (value "NEOPIXEL-TLC59731DR")
      (footprint "eagle-import:SOIC127P600X175-8N")
      (fields
        (field (name "ARROW_PART_NUMBER") "TLC59731DR")
        (field (name "MOUSER_PART_NUMBER") "595-TLC59731DR")
      )
      (libsource (lib "eagle-import") (part "NEOPIXEL-TLC59731DR"))
    )
    (comp (ref "PIXEL_74")
      (value "NEOPIXEL-TLC59731DR")
      (footprint "eagle-import:SOIC127P600X175-8N")
      (fields
        (field (name "ARROW_PART_NUMBER") "TLC59731DR")
        (field (name "MOUSER_PART_NUMBER") "595-TLC59731DR")
      )
      (libsource (lib "eagle-import") (part "NEOPIXEL-TLC59731DR"))
    )
    (comp (ref "PIXEL_75")
      (value "NEOPIXEL-TLC59731DR")
      (footprint "eagle-import:SOIC127P600X175-8N")
      (fields
        (field (name "ARROW_PART_NUMBER") "TLC59731DR")
        (field (name "MOUSER_PART_NUMBER") "595-TLC59731DR")
      )
      (libsource (lib "eagle-import") (part "NEOPIXEL-TLC59731DR"))
    )
    (comp (ref "R97")
      (value "100")
      (footprint "eagle-import:1206")
      (libsource (lib "eagle-import") (part "PASSIF-RESISTOR-1206"))
    )
    (comp (ref "R98")
      (value "100")
      (footprint "eagle-import:1206")
      (libsource (lib "eagle-import") (part "PASSIF-RESISTOR-1206"))
    )
    (comp (ref "R99")
      (value "100")
      (footprint "eagle-import:1206")
      (libsource (lib "eagle-import") (part "PASSIF-RESISTOR-1206"))
    )
    (comp (ref "R135")
      (value "100")
      (footprint "eagle-import:1206")
      (libsource (lib "eagle-import") (part "PASSIF-RESISTOR-1206"))
    )
    (comp (ref "R136")
      (value "100")
      (footprint "eagle-import:1206")
      (libsource (lib "eagle-import") (part "PASSIF-RESISTOR-1206"))
    )
    (comp (ref "R137")
      (value "100")
      (footprint "eagle-import:1206")
      (libsource (lib "eagle-import") (part "PASSIF-RESISTOR-1206"))
    )
    (comp (ref "R159")
      (value "100")
      (footprint "eagle-import:1206")
      (libsource (lib "eagle-import") (part "PASSIF-RESISTOR-1206"))
    )
    (comp (ref "R160")
      (value "100")
      (footprint "eagle-import:1206")
      (libsource (lib "eagle-import") (part "PASSIF-RESISTOR-1206"))
    )
    (comp (ref "R161")
      (value "100")
      (footprint "eagle-import:1206")
      (libsource (lib "eagle-import") (part "PASSIF-RESISTOR-1206"))
    )
    (comp (ref "R171")
      (value "100")
      (footprint "eagle-import:1206")
      (libsource (lib "eagle-import") (part "PASSIF-RESISTOR-1206"))
    )
    (comp (ref "R172")
      (value "100")
      (footprint "eagle-import:1206")
      (libsource (lib "eagle-import") (part "PASSIF-RESISTOR-1206"))
    )
    (comp (ref "R173")
      (value "100")
      (footprint "eagle-import:1206")
      (libsource (lib "eagle-import") (part "PASSIF-RESISTOR-1206"))
    )
    (comp (ref "R177")
      (value "100")
      (footprint "eagle-import:1206")
      (libsource (lib "eagle-import") (part "PASSIF-RESISTOR-1206"))
    )
    (comp (ref "R178")
      (value "100")
      (footprint "eagle-import:1206")
      (libsource (lib "eagle-import") (part "PASSIF-RESISTOR-1206"))
    )
    (comp (ref "R179")
      (value "100")
      (footprint "eagle-import:1206")
      (libsource (lib "eagle-import") (part "PASSIF-RESISTOR-1206"))
    )
    (comp (ref "R204")
      (value "1k")
      (footprint "eagle-import:R0805")
      (libsource (lib "eagle-import") (part "R-US_R0805"))
    )
    (comp (ref "R205")
      (value "1k")
      (footprint "eagle-import:R0805")
      (libsource (lib "eagle-import") (part "R-US_R0805"))
    )
    (comp (ref "RB32")
      (value "470")
      (footprint "eagle-import:1206")
      (libsource (lib "eagle-import") (part "PASSIF-RESISTOR-1206"))
    )
    (comp (ref "RB33")
      (value "470")
      (footprint "eagle-import:1206")
      (libsource (lib "eagle-import") (part "PASSIF-RESISTOR-1206"))
    )
    (comp (ref "RB34")
      (value "470")
      (footprint "eagle-import:1206")
      (libsource (lib "eagle-import") (part "PASSIF-RESISTOR-1206"))
    )
    (comp (ref "RB56")
      (value "470")
      (footprint "eagle-import:1206")
      (libsource (lib "eagle-import") (part "PASSIF-RESISTOR-1206"))
    )
    (comp (ref "RB57")
      (value "470")
      (footprint "eagle-import:1206")
      (libsource (lib "eagle-import") (part "PASSIF-RESISTOR-1206"))
    )
    (comp (ref "RB58")
      (value "470")
      (footprint "eagle-import:1206")
      (libsource (lib "eagle-import") (part "PASSIF-RESISTOR-1206"))
    )
    (comp (ref "RB80")
      (value "470")
      (footprint "eagle-import:1206")
      (libsource (lib "eagle-import") (part "PASSIF-RESISTOR-1206"))
    )
    (comp (ref "RB81")
      (value "470")
      (footprint "eagle-import:1206")
      (libsource (lib "eagle-import") (part "PASSIF-RESISTOR-1206"))
    )
    (comp (ref "RB82")
      (value "470")
      (footprint "eagle-import:1206")
      (libsource (lib "eagle-import") (part "PASSIF-RESISTOR-1206"))
    )
    (comp (ref "RB92")
      (value "470")
      (footprint "eagle-import:1206")
      (libsource (lib "eagle-import") (part "PASSIF-RESISTOR-1206"))
    )
    (comp (ref "RB93")
      (value "470")
      (footprint "eagle-import:1206")
      (libsource (lib "eagle-import") (part "PASSIF-RESISTOR-1206"))
    )
    (comp (ref "RB94")
      (value "470")
      (footprint "eagle-import:1206")
      (libsource (lib "eagle-import") (part "PASSIF-RESISTOR-1206"))
    )
    (comp (ref "RB98")
      (value "470")
      (footprint "eagle-import:1206")
      (libsource (lib "eagle-import") (part "PASSIF-RESISTOR-1206"))
    )
    (comp (ref "RB99")
      (value "470")
      (footprint "eagle-import:1206")
      (libsource (lib "eagle-import") (part "PASSIF-RESISTOR-1206"))
    )
    (comp (ref "RB100")
      (value "470")
      (footprint "eagle-import:1206")
      (libsource (lib "eagle-import") (part "PASSIF-RESISTOR-1206"))
    )
    (comp (ref "RPD9")
      (value "10k")
      (footprint "eagle-import:1206")
      (libsource (lib "eagle-import") (part "PASSIF-RESISTOR-1206"))
    )
    (comp (ref "RPD17")
      (value "10k")
      (footprint "eagle-import:1206")
      (libsource (lib "eagle-import") (part "PASSIF-RESISTOR-1206"))
    )
    (comp (ref "RPD25")
      (value "10k")
      (footprint "eagle-import:1206")
      (libsource (lib "eagle-import") (part "PASSIF-RESISTOR-1206"))
    )
    (comp (ref "RPD29")
      (value "10k")
      (footprint "eagle-import:1206")
      (libsource (lib "eagle-import") (part "PASSIF-RESISTOR-1206"))
    )
    (comp (ref "RPD31")
      (value "10k")
      (footprint "eagle-import:1206")
      (libsource (lib "eagle-import") (part "PASSIF-RESISTOR-1206"))
    )
    (comp (ref "CB104")
      (value "10n")
      (footprint "eagle-import:0805-CAP")
      (libsource (lib "eagle-import") (part "PASSIF-CAP-0805"))
    )
    (comp (ref "CB105")
      (value "10n")
      (footprint "eagle-import:0805-CAP")
      (libsource (lib "eagle-import") (part "PASSIF-CAP-0805"))
    )
    (comp (ref "CB106")
      (value "10n")
      (footprint "eagle-import:0805-CAP")
      (libsource (lib "eagle-import") (part "PASSIF-CAP-0805"))
    )
    (comp (ref "CB110")
      (value "10n")
      (footprint "eagle-import:0805-CAP")
      (libsource (lib "eagle-import") (part "PASSIF-CAP-0805"))
    )
    (comp (ref "CB111")
      (value "10n")
      (footprint "eagle-import:0805-CAP")
      (libsource (lib "eagle-import") (part "PASSIF-CAP-0805"))
    )
    (comp (ref "CB112")
      (value "10n")
      (footprint "eagle-import:0805-CAP")
      (libsource (lib "eagle-import") (part "PASSIF-CAP-0805"))
    )
    (comp (ref "CB116")
      (value "10n")
      (footprint "eagle-import:0805-CAP")
      (libsource (lib "eagle-import") (part "PASSIF-CAP-0805"))
    )
    (comp (ref "CB117")
      (value "10n")
      (footprint "eagle-import:0805-CAP")
      (libsource (lib "eagle-import") (part "PASSIF-CAP-0805"))
    )
    (comp (ref "CB118")
      (value "10n")
      (footprint "eagle-import:0805-CAP")
      (libsource (lib "eagle-import") (part "PASSIF-CAP-0805"))
    )
    (comp (ref "CDEC33")
      (value "10u")
      (footprint "eagle-import:CPOL2917")
      (libsource (lib "eagle-import") (part "PASSIF-CPOL-US2917"))
    )
    (comp (ref "CDEC35")
      (value "10u")
      (footprint "eagle-import:CPOL2917")
      (libsource (lib "eagle-import") (part "PASSIF-CPOL-US2917"))
    )
    (comp (ref "CDEC37")
      (value "10u")
      (footprint "eagle-import:CPOL2917")
      (libsource (lib "eagle-import") (part "PASSIF-CPOL-US2917"))
    )
    (comp (ref "CPOL33")
      (value "100n")
      (footprint "eagle-import:0805-CAP")
      (libsource (lib "eagle-import") (part "PASSIF-CAP-0805"))
    )
    (comp (ref "CPOL35")
      (value "100n")
      (footprint "eagle-import:0805-CAP")
      (libsource (lib "eagle-import") (part "PASSIF-CAP-0805"))
    )
    (comp (ref "CPOL37")
      (value "100n")
      (footprint "eagle-import:0805-CAP")
      (libsource (lib "eagle-import") (part "PASSIF-CAP-0805"))
    )
    (comp (ref "ENC_01")
      (value "ENCODER-RGB-SWITCH-NO_NUT")
      (footprint "eagle-import:ENCODER_LED_3")
      (libsource (lib "eagle-import") (part "ENCODER-RGB-SWITCH-NO_NUT"))
    )
    (comp (ref "ENC_02")
      (value "ENCODER-RGB-SWITCH-NO_NUT")
      (footprint "eagle-import:ENCODER_LED_3")
      (libsource (lib "eagle-import") (part "ENCODER-RGB-SWITCH-NO_NUT"))
    )
    (comp (ref "ENC_3")
      (value "ENCODER-RGB-SWITCH-NO_NUT")
      (footprint "eagle-import:ENCODER_LED_3")
      (libsource (lib "eagle-import") (part "ENCODER-RGB-SWITCH-NO_NUT"))
    )
    (comp (ref "PIXEL_01")
      (value "NEOPIXEL-TLC59731DR")
      (footprint "eagle-import:SOIC127P600X175-8N")
      (fields
        (field (name "ARROW_PART_NUMBER") "TLC59731DR")
        (field (name "MOUSER_PART_NUMBER") "595-TLC59731DR")
      )
      (libsource (lib "eagle-import") (part "NEOPIXEL-TLC59731DR"))
    )
    (comp (ref "PIXEL_02")
      (value "NEOPIXEL-TLC59731DR")
      (footprint "eagle-import:SOIC127P600X175-8N")
      (fields
        (field (name "ARROW_PART_NUMBER") "TLC59731DR")
        (field (name "MOUSER_PART_NUMBER") "595-TLC59731DR")
      )
      (libsource (lib "eagle-import") (part "NEOPIXEL-TLC59731DR"))
    )
    (comp (ref "PIXEL_03")
      (value "NEOPIXEL-TLC59731DR")
      (footprint "eagle-import:SOIC127P600X175-8N")
      (fields
        (field (name "ARROW_PART_NUMBER") "TLC59731DR")
        (field (name "MOUSER_PART_NUMBER") "595-TLC59731DR")
      )
      (libsource (lib "eagle-import") (part "NEOPIXEL-TLC59731DR"))
    )
    (comp (ref "R183")
      (value "100")
      (footprint "eagle-import:1206")
      (libsource (lib "eagle-import") (part "PASSIF-RESISTOR-1206"))
    )
    (comp (ref "R184")
      (value "100")
      (footprint "eagle-import:1206")
      (libsource (lib "eagle-import") (part "PASSIF-RESISTOR-1206"))
    )
    (comp (ref "R185")
      (value "100")
      (footprint "eagle-import:1206")
      (libsource (lib "eagle-import") (part "PASSIF-RESISTOR-1206"))
    )
    (comp (ref "R189")
      (value "100")
      (footprint "eagle-import:1206")
      (libsource (lib "eagle-import") (part "PASSIF-RESISTOR-1206"))
    )
    (comp (ref "R190")
      (value "100")
      (footprint "eagle-import:1206")
      (libsource (lib "eagle-import") (part "PASSIF-RESISTOR-1206"))
    )
    (comp (ref "R191")
      (value "100")
      (footprint "eagle-import:1206")
      (libsource (lib "eagle-import") (part "PASSIF-RESISTOR-1206"))
    )
    (comp (ref "R195")
      (value "100")
      (footprint "eagle-import:1206")
      (libsource (lib "eagle-import") (part "PASSIF-RESISTOR-1206"))
    )
    (comp (ref "R196")
      (value "100")
      (footprint "eagle-import:1206")
      (libsource (lib "eagle-import") (part "PASSIF-RESISTOR-1206"))
    )
    (comp (ref "R197")
      (value "100")
      (footprint "eagle-import:1206")
      (libsource (lib "eagle-import") (part "PASSIF-RESISTOR-1206"))
    )
    (comp (ref "RB104")
      (value "470")
      (footprint "eagle-import:1206")
      (libsource (lib "eagle-import") (part "PASSIF-RESISTOR-1206"))
    )
    (comp (ref "RB105")
      (value "470")
      (footprint "eagle-import:1206")
      (libsource (lib "eagle-import") (part "PASSIF-RESISTOR-1206"))
    )
    (comp (ref "RB106")
      (value "470")
      (footprint "eagle-import:1206")
      (libsource (lib "eagle-import") (part "PASSIF-RESISTOR-1206"))
    )
    (comp (ref "RB110")
      (value "470")
      (footprint "eagle-import:1206")
      (libsource (lib "eagle-import") (part "PASSIF-RESISTOR-1206"))
    )
    (comp (ref "RB111")
      (value "470")
      (footprint "eagle-import:1206")
      (libsource (lib "eagle-import") (part "PASSIF-RESISTOR-1206"))
    )
    (comp (ref "RB112")
      (value "470")
      (footprint "eagle-import:1206")
      (libsource (lib "eagle-import") (part "PASSIF-RESISTOR-1206"))
    )
    (comp (ref "RB116")
      (value "470")
      (footprint "eagle-import:1206")
      (libsource (lib "eagle-import") (part "PASSIF-RESISTOR-1206"))
    )
    (comp (ref "RB117")
      (value "470")
      (footprint "eagle-import:1206")
      (libsource (lib "eagle-import") (part "PASSIF-RESISTOR-1206"))
    )
    (comp (ref "RB118")
      (value "470")
      (footprint "eagle-import:1206")
      (libsource (lib "eagle-import") (part "PASSIF-RESISTOR-1206"))
    )
    (comp (ref "RPD33")
      (value "10k")
      (footprint "eagle-import:1206")
      (libsource (lib "eagle-import") (part "PASSIF-RESISTOR-1206"))
    )
    (comp (ref "RPD35")
      (value "10k")
      (footprint "eagle-import:1206")
      (libsource (lib "eagle-import") (part "PASSIF-RESISTOR-1206"))
    )
    (comp (ref "RPD37")
      (value "10k")
      (footprint "eagle-import:1206")
      (libsource (lib "eagle-import") (part "PASSIF-RESISTOR-1206"))
    )
    (comp (ref "TFT_EXT_2")
      (value "MA06-2")
      (footprint "eagle-import:MA06-2")
      (libsource (lib "eagle-import") (part "MA06-2"))
    )
    (comp (ref "CB5")
      (value "10n")
      (footprint "eagle-import:0805-CAP")
      (libsource (lib "eagle-import") (part "PASSIF-CAP-0805"))
    )
    (comp (ref "CB8")
      (value "10n")
      (footprint "eagle-import:0805-CAP")
      (libsource (lib "eagle-import") (part "PASSIF-CAP-0805"))
    )
    (comp (ref "CB9")
      (value "10n")
      (footprint "eagle-import:0805-CAP")
      (libsource (lib "eagle-import") (part "PASSIF-CAP-0805"))
    )
    (comp (ref "CB10")
      (value "10n")
      (footprint "eagle-import:0805-CAP")
      (libsource (lib "eagle-import") (part "PASSIF-CAP-0805"))
    )
    (comp (ref "CB14")
      (value "10n")
      (footprint "eagle-import:0805-CAP")
      (libsource (lib "eagle-import") (part "PASSIF-CAP-0805"))
    )
    (comp (ref "CB15")
      (value "10n")
      (footprint "eagle-import:0805-CAP")
      (libsource (lib "eagle-import") (part "PASSIF-CAP-0805"))
    )
    (comp (ref "CB16")
      (value "10n")
      (footprint "eagle-import:0805-CAP")
      (libsource (lib "eagle-import") (part "PASSIF-CAP-0805"))
    )
    (comp (ref "CB26")
      (value "10n")
      (footprint "eagle-import:0805-CAP")
      (libsource (lib "eagle-import") (part "PASSIF-CAP-0805"))
    )
    (comp (ref "CB27")
      (value "10n")
      (footprint "eagle-import:0805-CAP")
      (libsource (lib "eagle-import") (part "PASSIF-CAP-0805"))
    )
    (comp (ref "CB28")
      (value "10n")
      (footprint "eagle-import:0805-CAP")
      (libsource (lib "eagle-import") (part "PASSIF-CAP-0805"))
    )
    (comp (ref "CB35")
      (value "10n")
      (footprint "eagle-import:0805-CAP")
      (libsource (lib "eagle-import") (part "PASSIF-CAP-0805"))
    )
    (comp (ref "CB36")
      (value "10n")
      (footprint "eagle-import:0805-CAP")
      (libsource (lib "eagle-import") (part "PASSIF-CAP-0805"))
    )
    (comp (ref "CB37")
      (value "10n")
      (footprint "eagle-import:0805-CAP")
      (libsource (lib "eagle-import") (part "PASSIF-CAP-0805"))
    )
    (comp (ref "CB41")
      (value "10n")
      (footprint "eagle-import:0805-CAP")
      (libsource (lib "eagle-import") (part "PASSIF-CAP-0805"))
    )
    (comp (ref "CB42")
      (value "10n")
      (footprint "eagle-import:0805-CAP")
      (libsource (lib "eagle-import") (part "PASSIF-CAP-0805"))
    )
    (comp (ref "CB43")
      (value "10n")
      (footprint "eagle-import:0805-CAP")
      (libsource (lib "eagle-import") (part "PASSIF-CAP-0805"))
    )
    (comp (ref "CB44")
      (value "10n")
      (footprint "eagle-import:0805-CAP")
      (libsource (lib "eagle-import") (part "PASSIF-CAP-0805"))
    )
    (comp (ref "CB47")
      (value "10n")
      (footprint "eagle-import:0805-CAP")
      (libsource (lib "eagle-import") (part "PASSIF-CAP-0805"))
    )
    (comp (ref "CB48")
      (value "10n")
      (footprint "eagle-import:0805-CAP")
      (libsource (lib "eagle-import") (part "PASSIF-CAP-0805"))
    )
    (comp (ref "CB49")
      (value "10n")
      (footprint "eagle-import:0805-CAP")
      (libsource (lib "eagle-import") (part "PASSIF-CAP-0805"))
    )
    (comp (ref "CB53")
      (value "10n")
      (footprint "eagle-import:0805-CAP")
      (libsource (lib "eagle-import") (part "PASSIF-CAP-0805"))
    )
    (comp (ref "CB54")
      (value "10n")
      (footprint "eagle-import:0805-CAP")
      (libsource (lib "eagle-import") (part "PASSIF-CAP-0805"))
    )
    (comp (ref "CB55")
      (value "10n")
      (footprint "eagle-import:0805-CAP")
      (libsource (lib "eagle-import") (part "PASSIF-CAP-0805"))
    )
    (comp (ref "CB59")
      (value "10n")
      (footprint "eagle-import:0805-CAP")
      (libsource (lib "eagle-import") (part "PASSIF-CAP-0805"))
    )
    (comp (ref "CB60")
      (value "10n")
      (footprint "eagle-import:0805-CAP")
      (libsource (lib "eagle-import") (part "PASSIF-CAP-0805"))
    )
    (comp (ref "CB61")
      (value "10n")
      (footprint "eagle-import:0805-CAP")
      (libsource (lib "eagle-import") (part "PASSIF-CAP-0805"))
    )
    (comp (ref "CB65")
      (value "10n")
      (footprint "eagle-import:0805-CAP")
      (libsource (lib "eagle-import") (part "PASSIF-CAP-0805"))
    )
    (comp (ref "CB66")
      (value "10n")
      (footprint "eagle-import:0805-CAP")
      (libsource (lib "eagle-import") (part "PASSIF-CAP-0805"))
    )
    (comp (ref "CB67")
      (value "10n")
      (footprint "eagle-import:0805-CAP")
      (libsource (lib "eagle-import") (part "PASSIF-CAP-0805"))
    )
    (comp (ref "CB71")
      (value "10n")
      (footprint "eagle-import:0805-CAP")
      (libsource (lib "eagle-import") (part "PASSIF-CAP-0805"))
    )
    (comp (ref "CB72")
      (value "10n")
      (footprint "eagle-import:0805-CAP")
      (libsource (lib "eagle-import") (part "PASSIF-CAP-0805"))
    )
    (comp (ref "CB73")
      (value "10n")
      (footprint "eagle-import:0805-CAP")
      (libsource (lib "eagle-import") (part "PASSIF-CAP-0805"))
    )
    (comp (ref "CDEC1")
      (value "10u")
      (footprint "eagle-import:CPOL2917")
      (libsource (lib "eagle-import") (part "PASSIF-CPOL-US2917"))
    )
    (comp (ref "CDEC3")
      (value "10u")
      (footprint "eagle-import:CPOL2917")
      (libsource (lib "eagle-import") (part "PASSIF-CPOL-US2917"))
    )
    (comp (ref "CDEC7")
      (value "10u")
      (footprint "eagle-import:CPOL2917")
      (libsource (lib "eagle-import") (part "PASSIF-CPOL-US2917"))
    )
    (comp (ref "CDEC10")
      (value "10u")
      (footprint "eagle-import:CPOL2917")
      (libsource (lib "eagle-import") (part "PASSIF-CPOL-US2917"))
    )
    (comp (ref "CDEC12")
      (value "10u")
      (footprint "eagle-import:CPOL2917")
      (libsource (lib "eagle-import") (part "PASSIF-CPOL-US2917"))
    )
    (comp (ref "CDEC14")
      (value "10u")
      (footprint "eagle-import:CPOL2917")
      (libsource (lib "eagle-import") (part "PASSIF-CPOL-US2917"))
    )
    (comp (ref "CDEC16")
      (value "10u")
      (footprint "eagle-import:CPOL2917")
      (libsource (lib "eagle-import") (part "PASSIF-CPOL-US2917"))
    )
    (comp (ref "CDEC18")
      (value "10u")
      (footprint "eagle-import:CPOL2917")
      (libsource (lib "eagle-import") (part "PASSIF-CPOL-US2917"))
    )
    (comp (ref "CDEC20")
      (value "10u")
      (footprint "eagle-import:CPOL2917")
      (libsource (lib "eagle-import") (part "PASSIF-CPOL-US2917"))
    )
    (comp (ref "CDEC21")
      (value "100n")
      (footprint "eagle-import:0805-CAP")
      (libsource (lib "eagle-import") (part "PASSIF-CAP-0805"))
    )
    (comp (ref "CDEC22")
      (value "10u")
      (footprint "eagle-import:CPOL2917")
      (libsource (lib "eagle-import") (part "PASSIF-CPOL-US2917"))
    )
    (comp (ref "CDEC30")
      (value "100n")
      (footprint "eagle-import:0805-CAP")
      (libsource (lib "eagle-import") (part "PASSIF-CAP-0805"))
    )
    (comp (ref "CDEC_2A2")
      (value "10u")
      (footprint "eagle-import:CPOL2917")
      (libsource (lib "eagle-import") (part "PASSIF-CPOL-US2917"))
    )
    (comp (ref "CDEC_2A3")
      (value "10u")
      (footprint "eagle-import:CPOL2917")
      (libsource (lib "eagle-import") (part "PASSIF-CPOL-US2917"))
    )
    (comp (ref "CDEC_2B2")
      (value "100n")
      (footprint "eagle-import:0805-CAP")
      (libsource (lib "eagle-import") (part "PASSIF-CAP-0805"))
    )
    (comp (ref "CDEC_2B3")
      (value "100n")
      (footprint "eagle-import:0805-CAP")
      (libsource (lib "eagle-import") (part "PASSIF-CAP-0805"))
    )
    (comp (ref "CPOL1")
      (value "100n")
      (footprint "eagle-import:0805-CAP")
      (libsource (lib "eagle-import") (part "PASSIF-CAP-0805"))
    )
    (comp (ref "CPOL3")
      (value "100n")
      (footprint "eagle-import:0805-CAP")
      (libsource (lib "eagle-import") (part "PASSIF-CAP-0805"))
    )
    (comp (ref "CPOL7")
      (value "100n")
      (footprint "eagle-import:0805-CAP")
      (libsource (lib "eagle-import") (part "PASSIF-CAP-0805"))
    )
    (comp (ref "CPOL10")
      (value "100n")
      (footprint "eagle-import:0805-CAP")
      (libsource (lib "eagle-import") (part "PASSIF-CAP-0805"))
    )
    (comp (ref "CPOL12")
      (value "100n")
      (footprint "eagle-import:0805-CAP")
      (libsource (lib "eagle-import") (part "PASSIF-CAP-0805"))
    )
    (comp (ref "CPOL14")
      (value "100n")
      (footprint "eagle-import:0805-CAP")
      (libsource (lib "eagle-import") (part "PASSIF-CAP-0805"))
    )
    (comp (ref "CPOL16")
      (value "100n")
      (footprint "eagle-import:0805-CAP")
      (libsource (lib "eagle-import") (part "PASSIF-CAP-0805"))
    )
    (comp (ref "CPOL18")
      (value "100n")
      (footprint "eagle-import:0805-CAP")
      (libsource (lib "eagle-import") (part "PASSIF-CAP-0805"))
    )
    (comp (ref "CPOL20")
      (value "100n")
      (footprint "eagle-import:0805-CAP")
      (libsource (lib "eagle-import") (part "PASSIF-CAP-0805"))
    )
    (comp (ref "CPOL21")
      (value "10u")
      (footprint "eagle-import:CPOL2917")
      (libsource (lib "eagle-import") (part "PASSIF-CPOL-US2917"))
    )
    (comp (ref "CPOL22")
      (value "100n")
      (footprint "eagle-import:0805-CAP")
      (libsource (lib "eagle-import") (part "PASSIF-CAP-0805"))
    )
    (comp (ref "CPOL30")
      (value "10u")
      (footprint "eagle-import:CPOL2917")
      (libsource (lib "eagle-import") (part "PASSIF-CPOL-US2917"))
    )
    (comp (ref "ENC_51")
      (value "ENCODER-RGB-SWITCH-NO_NUT")
      (footprint "eagle-import:ENCODER_LED_3")
      (libsource (lib "eagle-import") (part "ENCODER-RGB-SWITCH-NO_NUT"))
    )
    (comp (ref "ENC_53")
      (value "ENCODER-RGB-SWITCH-NO_NUT")
      (footprint "eagle-import:ENCODER_LED_3")
      (libsource (lib "eagle-import") (part "ENCODER-RGB-SWITCH-NO_NUT"))
    )
    (comp (ref "ENC_54")
      (value "ENCODER-RGB-SWITCH-NO_NUT")
      (footprint "eagle-import:ENCODER_LED_3")
      (libsource (lib "eagle-import") (part "ENCODER-RGB-SWITCH-NO_NUT"))
    )
    (comp (ref "ENC_55")
      (value "ENCODER-RGB-SWITCH-NO_NUT")
      (footprint "eagle-import:ENCODER_LED_3")
      (libsource (lib "eagle-import") (part "ENCODER-RGB-SWITCH-NO_NUT"))
    )
    (comp (ref "ENC_56")
      (value "ENCODER-RGB-SWITCH-NO_NUT")
      (footprint "eagle-import:ENCODER_LED_3")
      (libsource (lib "eagle-import") (part "ENCODER-RGB-SWITCH-NO_NUT"))
    )
    (comp (ref "ENC_57")
      (value "ENCODER-RGB-SWITCH-NO_NUT")
      (footprint "eagle-import:ENCODER_LED_3")
      (libsource (lib "eagle-import") (part "ENCODER-RGB-SWITCH-NO_NUT"))
    )
    (comp (ref "ENC_61")
      (value "ENCODER-RGB-SWITCH-NO_NUT")
      (footprint "eagle-import:ENCODER_LED_3")
      (libsource (lib "eagle-import") (part "ENCODER-RGB-SWITCH-NO_NUT"))
    )
    (comp (ref "ENC_62")
      (value "ENCODER-RGB-SWITCH-NO_NUT")
      (footprint "eagle-import:ENCODER_LED_3")
      (libsource (lib "eagle-import") (part "ENCODER-RGB-SWITCH-NO_NUT"))
    )
    (comp (ref "ENC_63")
      (value "ENCODER-RGB-SWITCH-NO_NUT")
      (footprint "eagle-import:ENCODER_LED_3")
      (libsource (lib "eagle-import") (part "ENCODER-RGB-SWITCH-NO_NUT"))
    )
    (comp (ref "ENC_64")
      (value "ENCODER-RGB-SWITCH-NO_NUT")
      (footprint "eagle-import:ENCODER_LED_3")
      (libsource (lib "eagle-import") (part "ENCODER-RGB-SWITCH-NO_NUT"))
    )
    (comp (ref "LED4")
      (value "CZXR-80RGB03-A")
      (footprint "eagle-import:LED4-2.0-D8.0MM")
      (libsource (lib "eagle-import") (part "DIP-LED-RGB-COMMON-ANODE(4P-D8MM)"))
    )
    (comp (ref "LED7")
      (value "CZXR-80RGB03-A")
      (footprint "eagle-import:LED4-2.0-D8.0MM")
      (libsource (lib "eagle-import") (part "DIP-LED-RGB-COMMON-ANODE(4P-D8MM)"))
    )
    (comp (ref "MCP_011")
      (value "MCP23017")
      (footprint "eagle-import:SOIC-28")
      (libsource (lib "eagle-import") (part "MCP23017"))
    )
    (comp (ref "MCP_100")
      (value "MCP23017")
      (footprint "eagle-import:SOIC-28")
      (libsource (lib "eagle-import") (part "MCP23017"))
    )
    (comp (ref "PIXEL_51")
      (value "NEOPIXEL-TLC59731DR")
      (footprint "eagle-import:SOIC127P600X175-8N")
      (fields
        (field (name "ARROW_PART_NUMBER") "TLC59731DR")
        (field (name "MOUSER_PART_NUMBER") "595-TLC59731DR")
      )
      (libsource (lib "eagle-import") (part "NEOPIXEL-TLC59731DR"))
    )
    (comp (ref "PIXEL_52")
      (value "NEOPIXEL-TLC59731DR")
      (footprint "eagle-import:SOIC127P600X175-8N")
      (fields
        (field (name "ARROW_PART_NUMBER") "TLC59731DR")
        (field (name "MOUSER_PART_NUMBER") "595-TLC59731DR")
      )
      (libsource (lib "eagle-import") (part "NEOPIXEL-TLC59731DR"))
    )
    (comp (ref "PIXEL_53")
      (value "NEOPIXEL-TLC59731DR")
      (footprint "eagle-import:SOIC127P600X175-8N")
      (fields
        (field (name "ARROW_PART_NUMBER") "TLC59731DR")
        (field (name "MOUSER_PART_NUMBER") "595-TLC59731DR")
      )
      (libsource (lib "eagle-import") (part "NEOPIXEL-TLC59731DR"))
    )
    (comp (ref "PIXEL_54")
      (value "NEOPIXEL-TLC59731DR")
      (footprint "eagle-import:SOIC127P600X175-8N")
      (fields
        (field (name "ARROW_PART_NUMBER") "TLC59731DR")
        (field (name "MOUSER_PART_NUMBER") "595-TLC59731DR")
      )
      (libsource (lib "eagle-import") (part "NEOPIXEL-TLC59731DR"))
    )
    (comp (ref "PIXEL_55")
      (value "NEOPIXEL-TLC59731DR")
      (footprint "eagle-import:SOIC127P600X175-8N")
      (fields
        (field (name "ARROW_PART_NUMBER") "TLC59731DR")
        (field (name "MOUSER_PART_NUMBER") "595-TLC59731DR")
      )
      (libsource (lib "eagle-import") (part "NEOPIXEL-TLC59731DR"))
    )
    (comp (ref "PIXEL_56")
      (value "NEOPIXEL-TLC59731DR")
      (footprint "eagle-import:SOIC127P600X175-8N")
      (fields
        (field (name "ARROW_PART_NUMBER") "TLC59731DR")
        (field (name "MOUSER_PART_NUMBER") "595-TLC59731DR")
      )
      (libsource (lib "eagle-import") (part "NEOPIXEL-TLC59731DR"))
    )
    (comp (ref "PIXEL_57")
      (value "NEOPIXEL-TLC59731DR")
      (footprint "eagle-import:SOIC127P600X175-8N")
      (fields
        (field (name "ARROW_PART_NUMBER") "TLC59731DR")
        (field (name "MOUSER_PART_NUMBER") "595-TLC59731DR")
      )
      (libsource (lib "eagle-import") (part "NEOPIXEL-TLC59731DR"))
    )
    (comp (ref "PIXEL_61")
      (value "NEOPIXEL-TLC59731DR")
      (footprint "eagle-import:SOIC127P600X175-8N")
      (fields
        (field (name "ARROW_PART_NUMBER") "TLC59731DR")
        (field (name "MOUSER_PART_NUMBER") "595-TLC59731DR")
      )
      (libsource (lib "eagle-import") (part "NEOPIXEL-TLC59731DR"))
    )
    (comp (ref "PIXEL_62")
      (value "NEOPIXEL-TLC59731DR")
      (footprint "eagle-import:SOIC127P600X175-8N")
      (fields
        (field (name "ARROW_PART_NUMBER") "TLC59731DR")
        (field (name "MOUSER_PART_NUMBER") "595-TLC59731DR")
      )
      (libsource (lib "eagle-import") (part "NEOPIXEL-TLC59731DR"))
    )
    (comp (ref "PIXEL_63")
      (value "NEOPIXEL-TLC59731DR")
      (footprint "eagle-import:SOIC127P600X175-8N")
      (fields
        (field (name "ARROW_PART_NUMBER") "TLC59731DR")
        (field (name "MOUSER_PART_NUMBER") "595-TLC59731DR")
      )
      (libsource (lib "eagle-import") (part "NEOPIXEL-TLC59731DR"))
    )
    (comp (ref "PIXEL_64")
      (value "NEOPIXEL-TLC59731DR")
      (footprint "eagle-import:SOIC127P600X175-8N")
      (fields
        (field (name "ARROW_PART_NUMBER") "TLC59731DR")
        (field (name "MOUSER_PART_NUMBER") "595-TLC59731DR")
      )
      (libsource (lib "eagle-import") (part "NEOPIXEL-TLC59731DR"))
    )
    (comp (ref "PIXEL_65")
      (value "NEOPIXEL-TLC59731DR")
      (footprint "eagle-import:SOIC127P600X175-8N")
      (fields
        (field (name "ARROW_PART_NUMBER") "TLC59731DR")
        (field (name "MOUSER_PART_NUMBER") "595-TLC59731DR")
      )
      (libsource (lib "eagle-import") (part "NEOPIXEL-TLC59731DR"))
    )
    (comp (ref "R33")
      (value "100")
      (footprint "eagle-import:1206")
      (libsource (lib "eagle-import") (part "PASSIF-RESISTOR-1206"))
    )
    (comp (ref "R34")
      (value "100")
      (footprint "eagle-import:1206")
      (libsource (lib "eagle-import") (part "PASSIF-RESISTOR-1206"))
    )
    (comp (ref "R45")
      (value "100")
      (footprint "eagle-import:1206")
      (libsource (lib "eagle-import") (part "PASSIF-RESISTOR-1206"))
    )
    (comp (ref "R59")
      (value "100")
      (footprint "eagle-import:1206")
      (libsource (lib "eagle-import") (part "PASSIF-RESISTOR-1206"))
    )
    (comp (ref "R60")
      (value "100")
      (footprint "eagle-import:1206")
      (libsource (lib "eagle-import") (part "PASSIF-RESISTOR-1206"))
    )
    (comp (ref "R61")
      (value "100")
      (footprint "eagle-import:1206")
      (libsource (lib "eagle-import") (part "PASSIF-RESISTOR-1206"))
    )
    (comp (ref "R78")
      (value "100")
      (footprint "eagle-import:1206")
      (libsource (lib "eagle-import") (part "PASSIF-RESISTOR-1206"))
    )
    (comp (ref "R80")
      (value "100")
      (footprint "eagle-import:1206")
      (libsource (lib "eagle-import") (part "PASSIF-RESISTOR-1206"))
    )
    (comp (ref "R83")
      (value "100")
      (footprint "eagle-import:1206")
      (libsource (lib "eagle-import") (part "PASSIF-RESISTOR-1206"))
    )
    (comp (ref "R100")
      (value "100")
      (footprint "eagle-import:1206")
      (libsource (lib "eagle-import") (part "PASSIF-RESISTOR-1206"))
    )
    (comp (ref "R101")
      (value "100")
      (footprint "eagle-import:1206")
      (libsource (lib "eagle-import") (part "PASSIF-RESISTOR-1206"))
    )
    (comp (ref "R109")
      (value "100")
      (footprint "eagle-import:1206")
      (libsource (lib "eagle-import") (part "PASSIF-RESISTOR-1206"))
    )
    (comp (ref "R113")
      (value "100")
      (footprint "eagle-import:1206")
      (libsource (lib "eagle-import") (part "PASSIF-RESISTOR-1206"))
    )
    (comp (ref "R114")
      (value "100")
      (footprint "eagle-import:1206")
      (libsource (lib "eagle-import") (part "PASSIF-RESISTOR-1206"))
    )
    (comp (ref "R115")
      (value "100")
      (footprint "eagle-import:1206")
      (libsource (lib "eagle-import") (part "PASSIF-RESISTOR-1206"))
    )
    (comp (ref "R125")
      (value "100")
      (footprint "eagle-import:1206")
      (libsource (lib "eagle-import") (part "PASSIF-RESISTOR-1206"))
    )
    (comp (ref "R126")
      (value "100")
      (footprint "eagle-import:1206")
      (libsource (lib "eagle-import") (part "PASSIF-RESISTOR-1206"))
    )
    (comp (ref "R127")
      (value "100")
      (footprint "eagle-import:1206")
      (libsource (lib "eagle-import") (part "PASSIF-RESISTOR-1206"))
    )
    (comp (ref "R128")
      (value "100")
      (footprint "eagle-import:1206")
      (libsource (lib "eagle-import") (part "PASSIF-RESISTOR-1206"))
    )
    (comp (ref "R132")
      (value "100")
      (footprint "eagle-import:1206")
      (libsource (lib "eagle-import") (part "PASSIF-RESISTOR-1206"))
    )
    (comp (ref "R133")
      (value "100")
      (footprint "eagle-import:1206")
      (libsource (lib "eagle-import") (part "PASSIF-RESISTOR-1206"))
    )
    (comp (ref "R134")
      (value "100")
      (footprint "eagle-import:1206")
      (libsource (lib "eagle-import") (part "PASSIF-RESISTOR-1206"))
    )
    (comp (ref "R138")
      (value "100")
      (footprint "eagle-import:1206")
      (libsource (lib "eagle-import") (part "PASSIF-RESISTOR-1206"))
    )
    (comp (ref "R139")
      (value "100")
      (footprint "eagle-import:1206")
      (libsource (lib "eagle-import") (part "PASSIF-RESISTOR-1206"))
    )
    (comp (ref "R140")
      (value "100")
      (footprint "eagle-import:1206")
      (libsource (lib "eagle-import") (part "PASSIF-RESISTOR-1206"))
    )
    (comp (ref "R144")
      (value "100")
      (footprint "eagle-import:1206")
      (libsource (lib "eagle-import") (part "PASSIF-RESISTOR-1206"))
    )
    (comp (ref "R145")
      (value "100")
      (footprint "eagle-import:1206")
      (libsource (lib "eagle-import") (part "PASSIF-RESISTOR-1206"))
    )
    (comp (ref "R146")
      (value "100")
      (footprint "eagle-import:1206")
      (libsource (lib "eagle-import") (part "PASSIF-RESISTOR-1206"))
    )
    (comp (ref "R147")
      (value "100")
      (footprint "eagle-import:1206")
      (libsource (lib "eagle-import") (part "PASSIF-RESISTOR-1206"))
    )
    (comp (ref "R148")
      (value "100")
      (footprint "eagle-import:1206")
      (libsource (lib "eagle-import") (part "PASSIF-RESISTOR-1206"))
    )
    (comp (ref "R149")
      (value "1k")
      (footprint "eagle-import:R0805")
      (libsource (lib "eagle-import") (part "R-US_R0805"))
    )
    (comp (ref "R150")
      (value "100")
      (footprint "eagle-import:1206")
      (libsource (lib "eagle-import") (part "PASSIF-RESISTOR-1206"))
    )
    (comp (ref "R151")
      (value "100")
      (footprint "eagle-import:1206")
      (libsource (lib "eagle-import") (part "PASSIF-RESISTOR-1206"))
    )
    (comp (ref "R152")
      (value "100")
      (footprint "eagle-import:1206")
      (libsource (lib "eagle-import") (part "PASSIF-RESISTOR-1206"))
    )
    (comp (ref "R165")
      (value "1k")
      (footprint "eagle-import:R0805")
      (libsource (lib "eagle-import") (part "R-US_R0805"))
    )
    (comp (ref "R166")
      (value "1k")
      (footprint "eagle-import:R0805")
      (libsource (lib "eagle-import") (part "R-US_R0805"))
    )
    (comp (ref "R167")
      (value "100")
      (footprint "eagle-import:1206")
      (libsource (lib "eagle-import") (part "PASSIF-RESISTOR-1206"))
    )
    (comp (ref "R174")
      (value "100")
      (footprint "eagle-import:1206")
      (libsource (lib "eagle-import") (part "PASSIF-RESISTOR-1206"))
    )
    (comp (ref "R175")
      (value "100")
      (footprint "eagle-import:1206")
      (libsource (lib "eagle-import") (part "PASSIF-RESISTOR-1206"))
    )
    (comp (ref "R182")
      (value "1k")
      (footprint "eagle-import:R0805")
      (libsource (lib "eagle-import") (part "R-US_R0805"))
    )
    (comp (ref "RB5")
      (value "470")
      (footprint "eagle-import:1206")
      (libsource (lib "eagle-import") (part "PASSIF-RESISTOR-1206"))
    )
    (comp (ref "RB8")
      (value "470")
      (footprint "eagle-import:1206")
      (libsource (lib "eagle-import") (part "PASSIF-RESISTOR-1206"))
    )
    (comp (ref "RB9")
      (value "470")
      (footprint "eagle-import:1206")
      (libsource (lib "eagle-import") (part "PASSIF-RESISTOR-1206"))
    )
    (comp (ref "RB10")
      (value "470")
      (footprint "eagle-import:1206")
      (libsource (lib "eagle-import") (part "PASSIF-RESISTOR-1206"))
    )
    (comp (ref "RB14")
      (value "470")
      (footprint "eagle-import:1206")
      (libsource (lib "eagle-import") (part "PASSIF-RESISTOR-1206"))
    )
    (comp (ref "RB15")
      (value "470")
      (footprint "eagle-import:1206")
      (libsource (lib "eagle-import") (part "PASSIF-RESISTOR-1206"))
    )
    (comp (ref "RB16")
      (value "470")
      (footprint "eagle-import:1206")
      (libsource (lib "eagle-import") (part "PASSIF-RESISTOR-1206"))
    )
    (comp (ref "RB26")
      (value "470")
      (footprint "eagle-import:1206")
      (libsource (lib "eagle-import") (part "PASSIF-RESISTOR-1206"))
    )
    (comp (ref "RB27")
      (value "470")
      (footprint "eagle-import:1206")
      (libsource (lib "eagle-import") (part "PASSIF-RESISTOR-1206"))
    )
    (comp (ref "RB28")
      (value "470")
      (footprint "eagle-import:1206")
      (libsource (lib "eagle-import") (part "PASSIF-RESISTOR-1206"))
    )
    (comp (ref "RB35")
      (value "470")
      (footprint "eagle-import:1206")
      (libsource (lib "eagle-import") (part "PASSIF-RESISTOR-1206"))
    )
    (comp (ref "RB36")
      (value "470")
      (footprint "eagle-import:1206")
      (libsource (lib "eagle-import") (part "PASSIF-RESISTOR-1206"))
    )
    (comp (ref "RB37")
      (value "470")
      (footprint "eagle-import:1206")
      (libsource (lib "eagle-import") (part "PASSIF-RESISTOR-1206"))
    )
    (comp (ref "RB41")
      (value "470")
      (footprint "eagle-import:1206")
      (libsource (lib "eagle-import") (part "PASSIF-RESISTOR-1206"))
    )
    (comp (ref "RB42")
      (value "470")
      (footprint "eagle-import:1206")
      (libsource (lib "eagle-import") (part "PASSIF-RESISTOR-1206"))
    )
    (comp (ref "RB43")
      (value "470")
      (footprint "eagle-import:1206")
      (libsource (lib "eagle-import") (part "PASSIF-RESISTOR-1206"))
    )
    (comp (ref "RB44")
      (value "470")
      (footprint "eagle-import:1206")
      (libsource (lib "eagle-import") (part "PASSIF-RESISTOR-1206"))
    )
    (comp (ref "RB47")
      (value "470")
      (footprint "eagle-import:1206")
      (libsource (lib "eagle-import") (part "PASSIF-RESISTOR-1206"))
    )
    (comp (ref "RB48")
      (value "470")
      (footprint "eagle-import:1206")
      (libsource (lib "eagle-import") (part "PASSIF-RESISTOR-1206"))
    )
    (comp (ref "RB49")
      (value "470")
      (footprint "eagle-import:1206")
      (libsource (lib "eagle-import") (part "PASSIF-RESISTOR-1206"))
    )
    (comp (ref "RB53")
      (value "470")
      (footprint "eagle-import:1206")
      (libsource (lib "eagle-import") (part "PASSIF-RESISTOR-1206"))
    )
    (comp (ref "RB54")
      (value "470")
      (footprint "eagle-import:1206")
      (libsource (lib "eagle-import") (part "PASSIF-RESISTOR-1206"))
    )
    (comp (ref "RB55")
      (value "470")
      (footprint "eagle-import:1206")
      (libsource (lib "eagle-import") (part "PASSIF-RESISTOR-1206"))
    )
    (comp (ref "RB59")
      (value "470")
      (footprint "eagle-import:1206")
      (libsource (lib "eagle-import") (part "PASSIF-RESISTOR-1206"))
    )
    (comp (ref "RB60")
      (value "470")
      (footprint "eagle-import:1206")
      (libsource (lib "eagle-import") (part "PASSIF-RESISTOR-1206"))
    )
    (comp (ref "RB61")
      (value "470")
      (footprint "eagle-import:1206")
      (libsource (lib "eagle-import") (part "PASSIF-RESISTOR-1206"))
    )
    (comp (ref "RB65")
      (value "470")
      (footprint "eagle-import:1206")
      (libsource (lib "eagle-import") (part "PASSIF-RESISTOR-1206"))
    )
    (comp (ref "RB66")
      (value "470")
      (footprint "eagle-import:1206")
      (libsource (lib "eagle-import") (part "PASSIF-RESISTOR-1206"))
    )
    (comp (ref "RB67")
      (value "470")
      (footprint "eagle-import:1206")
      (libsource (lib "eagle-import") (part "PASSIF-RESISTOR-1206"))
    )
    (comp (ref "RB71")
      (value "470")
      (footprint "eagle-import:1206")
      (libsource (lib "eagle-import") (part "PASSIF-RESISTOR-1206"))
    )
    (comp (ref "RB72")
      (value "470")
      (footprint "eagle-import:1206")
      (libsource (lib "eagle-import") (part "PASSIF-RESISTOR-1206"))
    )
    (comp (ref "RB73")
      (value "470")
      (footprint "eagle-import:1206")
      (libsource (lib "eagle-import") (part "PASSIF-RESISTOR-1206"))
    )
    (comp (ref "RPD1")
      (value "10k")
      (footprint "eagle-import:1206")
      (libsource (lib "eagle-import") (part "PASSIF-RESISTOR-1206"))
    )
    (comp (ref "RPD3")
      (value "10k")
      (footprint "eagle-import:1206")
      (libsource (lib "eagle-import") (part "PASSIF-RESISTOR-1206"))
    )
    (comp (ref "RPD7")
      (value "10k")
      (footprint "eagle-import:1206")
      (libsource (lib "eagle-import") (part "PASSIF-RESISTOR-1206"))
    )
    (comp (ref "RPD10")
      (value "10k")
      (footprint "eagle-import:1206")
      (libsource (lib "eagle-import") (part "PASSIF-RESISTOR-1206"))
    )
    (comp (ref "RPD12")
      (value "10k")
      (footprint "eagle-import:1206")
      (libsource (lib "eagle-import") (part "PASSIF-RESISTOR-1206"))
    )
    (comp (ref "RPD14")
      (value "10k")
      (footprint "eagle-import:1206")
      (libsource (lib "eagle-import") (part "PASSIF-RESISTOR-1206"))
    )
    (comp (ref "RPD16")
      (value "10k")
      (footprint "eagle-import:1206")
      (libsource (lib "eagle-import") (part "PASSIF-RESISTOR-1206"))
    )
    (comp (ref "RPD18")
      (value "10k")
      (footprint "eagle-import:1206")
      (libsource (lib "eagle-import") (part "PASSIF-RESISTOR-1206"))
    )
    (comp (ref "RPD20")
      (value "10k")
      (footprint "eagle-import:1206")
      (libsource (lib "eagle-import") (part "PASSIF-RESISTOR-1206"))
    )
    (comp (ref "RPD22")
      (value "10k")
      (footprint "eagle-import:1206")
      (libsource (lib "eagle-import") (part "PASSIF-RESISTOR-1206"))
    )
    (comp (ref "SW_52")
      (value "B3F-1000")
      (footprint "eagle-import:B3F-1000")
      (fields
        (field (name "DIGI_KEY_PART_NUMBER") "SW400-ND")
        (field (name "MANUFACTURER") "Omron Electronics Inc-EMC Div")
        (field (name "CREATED_BY") "PCBLayout.com")
      )
      (libsource (lib "eagle-import") (part "B3F-1000"))
    )
    (comp (ref "SW_65")
      (value "B3F-1000")
      (footprint "eagle-import:B3F-1000")
      (fields
        (field (name "DIGI_KEY_PART_NUMBER") "SW400-ND")
        (field (name "MANUFACTURER") "Omron Electronics Inc-EMC Div")
        (field (name "CREATED_BY") "PCBLayout.com")
      )
      (libsource (lib "eagle-import") (part "B3F-1000"))
    )
  )
  (nets
    (net (code "1") (name "3V3") (class "Default")
      (node (ref "C65") (pin "+") (pinfunction "+_+") (pintype "passive"))
      (node (ref "C66") (pin "2") (pinfunction "2_2") (pintype "passive"))
      (node (ref "C67") (pin "2") (pinfunction "2_2") (pintype "passive"))
      (node (ref "C68") (pin "2") (pinfunction "2_2") (pintype "passive"))
      (node (ref "C69") (pin "2") (pinfunction "2_2") (pintype "passive"))
      (node (ref "C70") (pin "2") (pinfunction "2_2") (pintype "passive"))
      (node (ref "C71") (pin "2") (pinfunction "2_2") (pintype "passive"))
      (node (ref "CDEC1") (pin "+") (pinfunction "+_+") (pintype "passive"))
      (node (ref "CDEC10") (pin "+") (pinfunction "+_+") (pintype "passive"))
      (node (ref "CDEC11") (pin "+") (pinfunction "+_+") (pintype "passive"))
      (node (ref "CDEC12") (pin "+") (pinfunction "+_+") (pintype "passive"))
      (node (ref "CDEC13") (pin "1") (pinfunction "1_1") (pintype "passive"))
      (node (ref "CDEC14") (pin "+") (pinfunction "+_+") (pintype "passive"))
      (node (ref "CDEC15") (pin "+") (pinfunction "+_+") (pintype "passive"))
      (node (ref "CDEC16") (pin "+") (pinfunction "+_+") (pintype "passive"))
      (node (ref "CDEC17") (pin "+") (pinfunction "+_+") (pintype "passive"))
      (node (ref "CDEC18") (pin "+") (pinfunction "+_+") (pintype "passive"))
      (node (ref "CDEC19") (pin "+") (pinfunction "+_+") (pintype "passive"))
      (node (ref "CDEC2") (pin "+") (pinfunction "+_+") (pintype "passive"))
      (node (ref "CDEC20") (pin "+") (pinfunction "+_+") (pintype "passive"))
      (node (ref "CDEC21") (pin "1") (pinfunction "1_1") (pintype "passive"))
      (node (ref "CDEC22") (pin "+") (pinfunction "+_+") (pintype "passive"))
      (node (ref "CDEC23") (pin "+") (pinfunction "+_+") (pintype "passive"))
      (node (ref "CDEC24") (pin "+") (pinfunction "+_+") (pintype "passive"))
      (node (ref "CDEC25") (pin "+") (pinfunction "+_+") (pintype "passive"))
      (node (ref "CDEC26") (pin "+") (pinfunction "+_+") (pintype "passive"))
      (node (ref "CDEC28") (pin "+") (pinfunction "+_+") (pintype "passive"))
      (node (ref "CDEC29") (pin "+") (pinfunction "+_+") (pintype "passive"))
      (node (ref "CDEC3") (pin "+") (pinfunction "+_+") (pintype "passive"))
      (node (ref "CDEC30") (pin "1") (pinfunction "1_1") (pintype "passive"))
      (node (ref "CDEC31") (pin "+") (pinfunction "+_+") (pintype "passive"))
      (node (ref "CDEC32") (pin "1") (pinfunction "1_1") (pintype "passive"))
      (node (ref "CDEC33") (pin "+") (pinfunction "+_+") (pintype "passive"))
      (node (ref "CDEC35") (pin "+") (pinfunction "+_+") (pintype "passive"))
      (node (ref "CDEC36") (pin "1") (pinfunction "1_1") (pintype "passive"))
      (node (ref "CDEC37") (pin "+") (pinfunction "+_+") (pintype "passive"))
      (node (ref "CDEC39") (pin "1") (pinfunction "1_1") (pintype "passive"))
      (node (ref "CDEC4") (pin "+") (pinfunction "+_+") (pintype "passive"))
      (node (ref "CDEC5") (pin "+") (pinfunction "+_+") (pintype "passive"))
      (node (ref "CDEC6") (pin "+") (pinfunction "+_+") (pintype "passive"))
      (node (ref "CDEC7") (pin "+") (pinfunction "+_+") (pintype "passive"))
      (node (ref "CDEC8") (pin "+") (pinfunction "+_+") (pintype "passive"))
      (node (ref "CDEC9") (pin "+") (pinfunction "+_+") (pintype "passive"))
      (node (ref "CDEC_1") (pin "1") (pinfunction "1_1") (pintype "passive"))
      (node (ref "CDEC_10") (pin "1") (pinfunction "1_1") (pintype "passive"))
      (node (ref "CDEC_11") (pin "1") (pinfunction "1_1") (pintype "passive"))
      (node (ref "CDEC_11A") (pin "+") (pinfunction "+_+") (pintype "passive"))
      (node (ref "CDEC_11B") (pin "1") (pinfunction "1_1") (pintype "passive"))
      (node (ref "CDEC_12") (pin "1") (pinfunction "1_1") (pintype "passive"))
      (node (ref "CDEC_12A") (pin "+") (pinfunction "+_+") (pintype "passive"))
      (node (ref "CDEC_12B") (pin "1") (pinfunction "1_1") (pintype "passive"))
      (node (ref "CDEC_13") (pin "1") (pinfunction "1_1") (pintype "passive"))
      (node (ref "CDEC_2") (pin "1") (pinfunction "1_1") (pintype "passive"))
      (node (ref "CDEC_2A1") (pin "+") (pinfunction "+_+") (pintype "passive"))
      (node (ref "CDEC_2A2") (pin "+") (pinfunction "+_+") (pintype "passive"))
      (node (ref "CDEC_2A3") (pin "+") (pinfunction "+_+") (pintype "passive"))
      (node (ref "CDEC_2B1") (pin "1") (pinfunction "1_1") (pintype "passive"))
      (node (ref "CDEC_2B2") (pin "1") (pinfunction "1_1") (pintype "passive"))
      (node (ref "CDEC_2B3") (pin "1") (pinfunction "1_1") (pintype "passive"))
      (node (ref "CDEC_3") (pin "1") (pinfunction "1_1") (pintype "passive"))
      (node (ref "CDEC_4") (pin "1") (pinfunction "1_1") (pintype "passive"))
      (node (ref "CDEC_41A") (pin "+") (pinfunction "+_+") (pintype "passive"))
      (node (ref "CDEC_41B") (pin "1") (pinfunction "1_1") (pintype "passive"))
      (node (ref "CDEC_42A") (pin "+") (pinfunction "+_+") (pintype "passive"))
      (node (ref "CDEC_42B") (pin "1") (pinfunction "1_1") (pintype "passive"))
      (node (ref "CDEC_5") (pin "1") (pinfunction "1_1") (pintype "passive"))
      (node (ref "CDEC_5A") (pin "+") (pinfunction "+_+") (pintype "passive"))
      (node (ref "CDEC_5B") (pin "1") (pinfunction "1_1") (pintype "passive"))
      (node (ref "CDEC_6") (pin "1") (pinfunction "1_1") (pintype "passive"))
      (node (ref "CDEC_7") (pin "1") (pinfunction "1_1") (pintype "passive"))
      (node (ref "CDEC_8") (pin "1") (pinfunction "1_1") (pintype "passive"))
      (node (ref "CDEC_9") (pin "1") (pinfunction "1_1") (pintype "passive"))
      (node (ref "CONN_STH_BRD_1") (pin "2") (pinfunction "2_2") (pintype "passive"))
      (node (ref "CONN_STH_BRD_1") (pin "4") (pinfunction "4_4") (pintype "passive"))
      (node (ref "CONN_STH_BRD_2") (pin "2") (pinfunction "2_2") (pintype "passive"))
      (node (ref "CONN_STH_BRD_2") (pin "4") (pinfunction "4_4") (pintype "passive"))
      (node (ref "CPOL1") (pin "1") (pinfunction "1_1") (pintype "passive"))
      (node (ref "CPOL10") (pin "1") (pinfunction "1_1") (pintype "passive"))
      (node (ref "CPOL11") (pin "1") (pinfunction "1_1") (pintype "passive"))
      (node (ref "CPOL12") (pin "1") (pinfunction "1_1") (pintype "passive"))
      (node (ref "CPOL13") (pin "+") (pinfunction "+_+") (pintype "passive"))
      (node (ref "CPOL14") (pin "1") (pinfunction "1_1") (pintype "passive"))
      (node (ref "CPOL15") (pin "1") (pinfunction "1_1") (pintype "passive"))
      (node (ref "CPOL16") (pin "1") (pinfunction "1_1") (pintype "passive"))
      (node (ref "CPOL17") (pin "1") (pinfunction "1_1") (pintype "passive"))
      (node (ref "CPOL18") (pin "1") (pinfunction "1_1") (pintype "passive"))
      (node (ref "CPOL19") (pin "1") (pinfunction "1_1") (pintype "passive"))
      (node (ref "CPOL2") (pin "1") (pinfunction "1_1") (pintype "passive"))
      (node (ref "CPOL20") (pin "1") (pinfunction "1_1") (pintype "passive"))
      (node (ref "CPOL21") (pin "+") (pinfunction "+_+") (pintype "passive"))
      (node (ref "CPOL22") (pin "1") (pinfunction "1_1") (pintype "passive"))
      (node (ref "CPOL23") (pin "1") (pinfunction "1_1") (pintype "passive"))
      (node (ref "CPOL24") (pin "1") (pinfunction "1_1") (pintype "passive"))
      (node (ref "CPOL25") (pin "1") (pinfunction "1_1") (pintype "passive"))
      (node (ref "CPOL26") (pin "1") (pinfunction "1_1") (pintype "passive"))
      (node (ref "CPOL28") (pin "1") (pinfunction "1_1") (pintype "passive"))
      (node (ref "CPOL29") (pin "1") (pinfunction "1_1") (pintype "passive"))
      (node (ref "CPOL3") (pin "1") (pinfunction "1_1") (pintype "passive"))
      (node (ref "CPOL30") (pin "+") (pinfunction "+_+") (pintype "passive"))
      (node (ref "CPOL31") (pin "1") (pinfunction "1_1") (pintype "passive"))
      (node (ref "CPOL32") (pin "+") (pinfunction "+_+") (pintype "passive"))
      (node (ref "CPOL33") (pin "1") (pinfunction "1_1") (pintype "passive"))
      (node (ref "CPOL35") (pin "1") (pinfunction "1_1") (pintype "passive"))
      (node (ref "CPOL36") (pin "+") (pinfunction "+_+") (pintype "passive"))
      (node (ref "CPOL37") (pin "1") (pinfunction "1_1") (pintype "passive"))
      (node (ref "CPOL39") (pin "+") (pinfunction "+_+") (pintype "passive"))
      (node (ref "CPOL4") (pin "1") (pinfunction "1_1") (pintype "passive"))
      (node (ref "CPOL5") (pin "1") (pinfunction "1_1") (pintype "passive"))
      (node (ref "CPOL6") (pin "1") (pinfunction "1_1") (pintype "passive"))
      (node (ref "CPOL7") (pin "1") (pinfunction "1_1") (pintype "passive"))
      (node (ref "CPOL8") (pin "1") (pinfunction "1_1") (pintype "passive"))
      (node (ref "CPOL9") (pin "1") (pinfunction "1_1") (pintype "passive"))
      (node (ref "ENC_01") (pin "5") (pinfunction "+_5") (pintype "passive"))
      (node (ref "ENC_02") (pin "5") (pinfunction "+_5") (pintype "passive"))
      (node (ref "ENC_11") (pin "5") (pinfunction "+_5") (pintype "passive"))
      (node (ref "ENC_13") (pin "5") (pinfunction "+_5") (pintype "passive"))
      (node (ref "ENC_14") (pin "5") (pinfunction "+_5") (pintype "passive"))
      (node (ref "ENC_21") (pin "5") (pinfunction "+_5") (pintype "passive"))
      (node (ref "ENC_23") (pin "5") (pinfunction "+_5") (pintype "passive"))
      (node (ref "ENC_3") (pin "5") (pinfunction "+_5") (pintype "passive"))
      (node (ref "ENC_41") (pin "5") (pinfunction "+_5") (pintype "passive"))
      (node (ref "ENC_44") (pin "5") (pinfunction "+_5") (pintype "passive"))
      (node (ref "ENC_45") (pin "5") (pinfunction "+_5") (pintype "passive"))
      (node (ref "ENC_48") (pin "5") (pinfunction "+_5") (pintype "passive"))
      (node (ref "ENC_51") (pin "5") (pinfunction "+_5") (pintype "passive"))
      (node (ref "ENC_53") (pin "5") (pinfunction "+_5") (pintype "passive"))
      (node (ref "ENC_54") (pin "5") (pinfunction "+_5") (pintype "passive"))
      (node (ref "ENC_55") (pin "5") (pinfunction "+_5") (pintype "passive"))
      (node (ref "ENC_56") (pin "5") (pinfunction "+_5") (pintype "passive"))
      (node (ref "ENC_57") (pin "5") (pinfunction "+_5") (pintype "passive"))
      (node (ref "ENC_61") (pin "5") (pinfunction "+_5") (pintype "passive"))
      (node (ref "ENC_62") (pin "5") (pinfunction "+_5") (pintype "passive"))
      (node (ref "ENC_63") (pin "5") (pinfunction "+_5") (pintype "passive"))
      (node (ref "ENC_64") (pin "5") (pinfunction "+_5") (pintype "passive"))
      (node (ref "ENC_71") (pin "5") (pinfunction "+_5") (pintype "passive"))
      (node (ref "ENC_72") (pin "5") (pinfunction "+_5") (pintype "passive"))
      (node (ref "ENC_73") (pin "5") (pinfunction "+_5") (pintype "passive"))
      (node (ref "ENC_74") (pin "5") (pinfunction "+_5") (pintype "passive"))
      (node (ref "ENC_75") (pin "5") (pinfunction "+_5") (pintype "passive"))
      (node (ref "ENC_81") (pin "5") (pinfunction "+_5") (pintype "passive"))
      (node (ref "ENC_82") (pin "5") (pinfunction "+_5") (pintype "passive"))
      (node (ref "ENC_83") (pin "5") (pinfunction "+_5") (pintype "passive"))
      (node (ref "ENC_84") (pin "5") (pinfunction "+_5") (pintype "passive"))
      (node (ref "ENC_85") (pin "5") (pinfunction "+_5") (pintype "passive"))
      (node (ref "ENC_86") (pin "5") (pinfunction "+_5") (pintype "passive"))
      (node (ref "ENC_87") (pin "5") (pinfunction "+_5") (pintype "passive"))
      (node (ref "ENC_88") (pin "5") (pinfunction "+_5") (pintype "passive"))
      (node (ref "F446") (pin "1") (pinfunction "VBAT_1") (pintype "power_in"))
      (node (ref "F446") (pin "13") (pinfunction "VDDA/VREF+_13") (pintype "power_in"))
      (node (ref "F446") (pin "19") (pinfunction "VDD_4_19") (pintype "power_in"))
      (node (ref "F446") (pin "32") (pinfunction "VDD_1_32") (pintype "power_in"))
      (node (ref "F446") (pin "48") (pinfunction "VDD_2_48") (pintype "power_in"))
      (node (ref "F446") (pin "64") (pinfunction "VDD_3_64") (pintype "power_in"))
      (node (ref "L1") (pin "2") (pinfunction "2_2") (pintype "passive"))
      (node (ref "LED1") (pin "2") (pinfunction "+_2") (pintype "bidirectional"))
      (node (ref "LED2") (pin "2") (pinfunction "+_2") (pintype "bidirectional"))
      (node (ref "LED22") (pin "2") (pinfunction "+_2") (pintype "bidirectional"))
      (node (ref "LED4") (pin "2") (pinfunction "+_2") (pintype "bidirectional"))
      (node (ref "LED6") (pin "2") (pinfunction "+_2") (pintype "bidirectional"))
      (node (ref "LED7") (pin "2") (pinfunction "+_2") (pintype "bidirectional"))
      (node (ref "LED_42") (pin "2") (pinfunction "+_2") (pintype "bidirectional"))
      (node (ref "LED_43") (pin "2") (pinfunction "+_2") (pintype "bidirectional"))
      (node (ref "LED_46") (pin "2") (pinfunction "+_2") (pintype "bidirectional"))
      (node (ref "LED_47") (pin "2") (pinfunction "+_2") (pintype "bidirectional"))
      (node (ref "MCP_000") (pin "9") (pinfunction "VDD_9") (pintype "bidirectional"))
      (node (ref "MCP_001") (pin "15") (pinfunction "A0_15") (pintype "bidirectional"))
      (node (ref "MCP_001") (pin "9") (pinfunction "VDD_9") (pintype "bidirectional"))
      (node (ref "MCP_010") (pin "16") (pinfunction "A1_16") (pintype "bidirectional"))
      (node (ref "MCP_010") (pin "9") (pinfunction "VDD_9") (pintype "bidirectional"))
      (node (ref "MCP_011") (pin "15") (pinfunction "A0_15") (pintype "bidirectional"))
      (node (ref "MCP_011") (pin "16") (pinfunction "A1_16") (pintype "bidirectional"))
      (node (ref "MCP_011") (pin "9") (pinfunction "VDD_9") (pintype "bidirectional"))
      (node (ref "MCP_100") (pin "17") (pinfunction "A2_17") (pintype "bidirectional"))
      (node (ref "MCP_100") (pin "9") (pinfunction "VDD_9") (pintype "bidirectional"))
      (node (ref "MCP_101") (pin "15") (pinfunction "A0_15") (pintype "bidirectional"))
      (node (ref "MCP_101") (pin "17") (pinfunction "A2_17") (pintype "bidirectional"))
      (node (ref "MCP_101") (pin "9") (pinfunction "VDD_9") (pintype "bidirectional"))
      (node (ref "MCP_110") (pin "16") (pinfunction "A1_16") (pintype "bidirectional"))
      (node (ref "MCP_110") (pin "17") (pinfunction "A2_17") (pintype "bidirectional"))
      (node (ref "MCP_110") (pin "9") (pinfunction "VDD_9") (pintype "bidirectional"))
      (node (ref "MCP_111") (pin "15") (pinfunction "A0_15") (pintype "bidirectional"))
      (node (ref "MCP_111") (pin "16") (pinfunction "A1_16") (pintype "bidirectional"))
      (node (ref "MCP_111") (pin "17") (pinfunction "A2_17") (pintype "bidirectional"))
      (node (ref "MCP_111") (pin "9") (pinfunction "VDD_9") (pintype "bidirectional"))
      (node (ref "PIXEL_01") (pin "8") (pinfunction "VCC_8") (pintype "bidirectional"))
      (node (ref "PIXEL_02") (pin "8") (pinfunction "VCC_8") (pintype "bidirectional"))
      (node (ref "PIXEL_03") (pin "8") (pinfunction "VCC_8") (pintype "bidirectional"))
      (node (ref "PIXEL_11") (pin "8") (pinfunction "VCC_8") (pintype "bidirectional"))
      (node (ref "PIXEL_12") (pin "8") (pinfunction "VCC_8") (pintype "bidirectional"))
      (node (ref "PIXEL_13") (pin "8") (pinfunction "VCC_8") (pintype "bidirectional"))
      (node (ref "PIXEL_14") (pin "8") (pinfunction "VCC_8") (pintype "bidirectional"))
      (node (ref "PIXEL_21") (pin "8") (pinfunction "VCC_8") (pintype "bidirectional"))
      (node (ref "PIXEL_22") (pin "8") (pinfunction "VCC_8") (pintype "bidirectional"))
      (node (ref "PIXEL_23") (pin "8") (pinfunction "VCC_8") (pintype "bidirectional"))
      (node (ref "PIXEL_24") (pin "8") (pinfunction "VCC_8") (pintype "bidirectional"))
      (node (ref "PIXEL_31") (pin "8") (pinfunction "VCC_8") (pintype "bidirectional"))
      (node (ref "PIXEL_32") (pin "8") (pinfunction "VCC_8") (pintype "bidirectional"))
      (node (ref "PIXEL_33") (pin "8") (pinfunction "VCC_8") (pintype "bidirectional"))
      (node (ref "PIXEL_34") (pin "8") (pinfunction "VCC_8") (pintype "bidirectional"))
      (node (ref "PIXEL_35") (pin "8") (pinfunction "VCC_8") (pintype "bidirectional"))
      (node (ref "PIXEL_41") (pin "8") (pinfunction "VCC_8") (pintype "bidirectional"))
      (node (ref "PIXEL_42") (pin "8") (pinfunction "VCC_8") (pintype "bidirectional"))
      (node (ref "PIXEL_43") (pin "8") (pinfunction "VCC_8") (pintype "bidirectional"))
      (node (ref "PIXEL_44") (pin "8") (pinfunction "VCC_8") (pintype "bidirectional"))
      (node (ref "PIXEL_45") (pin "8") (pinfunction "VCC_8") (pintype "bidirectional"))
      (node (ref "PIXEL_46") (pin "8") (pinfunction "VCC_8") (pintype "bidirectional"))
      (node (ref "PIXEL_47") (pin "8") (pinfunction "VCC_8") (pintype "bidirectional"))
      (node (ref "PIXEL_48") (pin "8") (pinfunction "VCC_8") (pintype "bidirectional"))
      (node (ref "PIXEL_51") (pin "8") (pinfunction "VCC_8") (pintype "bidirectional"))
      (node (ref "PIXEL_52") (pin "8") (pinfunction "VCC_8") (pintype "bidirectional"))
      (node (ref "PIXEL_53") (pin "8") (pinfunction "VCC_8") (pintype "bidirectional"))
      (node (ref "PIXEL_54") (pin "8") (pinfunction "VCC_8") (pintype "bidirectional"))
      (node (ref "PIXEL_55") (pin "8") (pinfunction "VCC_8") (pintype "bidirectional"))
      (node (ref "PIXEL_56") (pin "8") (pinfunction "VCC_8") (pintype "bidirectional"))
      (node (ref "PIXEL_57") (pin "8") (pinfunction "VCC_8") (pintype "bidirectional"))
      (node (ref "PIXEL_61") (pin "8") (pinfunction "VCC_8") (pintype "bidirectional"))
      (node (ref "PIXEL_62") (pin "8") (pinfunction "VCC_8") (pintype "bidirectional"))
      (node (ref "PIXEL_63") (pin "8") (pinfunction "VCC_8") (pintype "bidirectional"))
      (node (ref "PIXEL_64") (pin "8") (pinfunction "VCC_8") (pintype "bidirectional"))
      (node (ref "PIXEL_65") (pin "8") (pinfunction "VCC_8") (pintype "bidirectional"))
      (node (ref "PIXEL_71") (pin "8") (pinfunction "VCC_8") (pintype "bidirectional"))
      (node (ref "PIXEL_72") (pin "8") (pinfunction "VCC_8") (pintype "bidirectional"))
      (node (ref "PIXEL_73") (pin "8") (pinfunction "VCC_8") (pintype "bidirectional"))
      (node (ref "PIXEL_74") (pin "8") (pinfunction "VCC_8") (pintype "bidirectional"))
      (node (ref "PIXEL_75") (pin "8") (pinfunction "VCC_8") (pintype "bidirectional"))
      (node (ref "PIXEL_81") (pin "8") (pinfunction "VCC_8") (pintype "bidirectional"))
      (node (ref "PIXEL_83") (pin "8") (pinfunction "VCC_8") (pintype "bidirectional"))
      (node (ref "PIXEL_84") (pin "8") (pinfunction "VCC_8") (pintype "bidirectional"))
      (node (ref "PIXEL_85") (pin "8") (pinfunction "VCC_8") (pintype "bidirectional"))
      (node (ref "PIXEL_86") (pin "8") (pinfunction "VCC_8") (pintype "bidirectional"))
      (node (ref "PIXEL_87") (pin "8") (pinfunction "VCC_8") (pintype "bidirectional"))
      (node (ref "PIXEL_88") (pin "8") (pinfunction "VCC_8") (pintype "bidirectional"))
      (node (ref "PIXE_82") (pin "8") (pinfunction "VCC_8") (pintype "bidirectional"))
      (node (ref "R1") (pin "2") (pinfunction "2_2") (pintype "passive"))
      (node (ref "R149") (pin "2") (pinfunction "2_2") (pintype "passive"))
      (node (ref "R165") (pin "2") (pinfunction "2_2") (pintype "passive"))
      (node (ref "R166") (pin "2") (pinfunction "2_2") (pintype "passive"))
      (node (ref "R182") (pin "2") (pinfunction "2_2") (pintype "passive"))
      (node (ref "R186") (pin "2") (pinfunction "2_2") (pintype "passive"))
      (node (ref "R187") (pin "2") (pinfunction "2_2") (pintype "passive"))
      (node (ref "R194") (pin "2") (pinfunction "2_2") (pintype "passive"))
      (node (ref "R198") (pin "2") (pinfunction "2_2") (pintype "passive"))
      (node (ref "R199") (pin "2") (pinfunction "2_2") (pintype "passive"))
      (node (ref "R2") (pin "2") (pinfunction "2_2") (pintype "passive"))
      (node (ref "R203") (pin "2") (pinfunction "2_2") (pintype "passive"))
      (node (ref "R204") (pin "2") (pinfunction "2_2") (pintype "passive"))
      (node (ref "R205") (pin "2") (pinfunction "2_2") (pintype "passive"))
      (node (ref "R4") (pin "2") (pinfunction "2_2") (pintype "passive"))
      (node (ref "R5") (pin "2") (pinfunction "2_2") (pintype "passive"))
      (node (ref "R79") (pin "1") (pinfunction "1_1") (pintype "passive"))
      (node (ref "R95") (pin "1") (pinfunction "1_1") (pintype "passive"))
      (node (ref "S24") (pin "5") (pinfunction "+_5") (pintype "passive"))
      (node (ref "S31") (pin "5") (pinfunction "+_5") (pintype "passive"))
      (node (ref "S34") (pin "5") (pinfunction "+_5") (pintype "passive"))
      (node (ref "S35") (pin "5") (pinfunction "+_5") (pintype "passive"))
      (node (ref "STLINK") (pin "1") (pinfunction "1_1") (pintype "passive"))
      (node (ref "TFT_EXT") (pin "1") (pinfunction "1_1") (pintype "passive"))
      (node (ref "TFT_EXT_2") (pin "1") (pinfunction "1_1") (pintype "passive"))
    )
    (net (code "2") (name "5V") (class "Default")
      (node (ref "0V/5V") (pin "3") (pinfunction "3_3") (pintype "passive"))
      (node (ref "0V/5V") (pin "4") (pinfunction "4_4") (pintype "passive"))
      (node (ref "C62") (pin "+") (pinfunction "+_+") (pintype "passive"))
      (node (ref "C76") (pin "2") (pinfunction "2_2") (pintype "passive"))
      (node (ref "R92") (pin "1") (pinfunction "1_1") (pintype "passive"))
      (node (ref "TLV75533") (pin "1") (pinfunction "IN_1") (pintype "input"))
      (node (ref "TLV75533") (pin "3") (pinfunction "EN_3") (pintype "input"))
    )
    (net (code "3") (name "ADC1_IN1") (class "Default")
      (node (ref "ANALOG_IN") (pin "4") (pinfunction "4_4") (pintype "passive"))
      (node (ref "F446") (pin "15") (pinfunction "PA1_15") (pintype "bidirectional"))
    )
    (net (code "4") (name "ADC1_IN4") (class "Default")
      (node (ref "ANALOG_IN") (pin "3") (pinfunction "3_3") (pintype "passive"))
      (node (ref "F446") (pin "20") (pinfunction "PA4_20") (pintype "bidirectional"))
    )
    (net (code "5") (name "ADC1_IN10") (class "Default")
      (node (ref "ANALOG_IN") (pin "2") (pinfunction "2_2") (pintype "passive"))
      (node (ref "F446") (pin "8") (pinfunction "PC0_8") (pintype "bidirectional"))
    )
    (net (code "6") (name "DATA_PIXEL11") (class "Default")
      (node (ref "PIXEL_11") (pin "5") (pinfunction "SDO_5") (pintype "bidirectional"))
      (node (ref "PIXEL_21") (pin "6") (pinfunction "SDI_6") (pintype "bidirectional"))
    )
    (net (code "7") (name "DATA_PIXEL12") (class "Default")
      (node (ref "PIXEL_11") (pin "6") (pinfunction "SDI_6") (pintype "bidirectional"))
      (node (ref "PIXEL_12") (pin "5") (pinfunction "SDO_5") (pintype "bidirectional"))
    )
    (net (code "8") (name "DATA_PIXEL13") (class "Default")
      (node (ref "PIXEL_12") (pin "6") (pinfunction "SDI_6") (pintype "bidirectional"))
      (node (ref "PIXEL_13") (pin "5") (pinfunction "SDO_5") (pintype "bidirectional"))
    )
    (net (code "9") (name "DATA_PIXEL14") (class "Default")
      (node (ref "PIXEL_13") (pin "6") (pinfunction "SDI_6") (pintype "bidirectional"))
      (node (ref "PIXEL_14") (pin "5") (pinfunction "SDO_5") (pintype "bidirectional"))
    )
    (net (code "10") (name "DATA_PIXEL21") (class "Default")
      (node (ref "PIXEL_21") (pin "5") (pinfunction "SDO_5") (pintype "bidirectional"))
      (node (ref "PIXEL_22") (pin "6") (pinfunction "SDI_6") (pintype "bidirectional"))
    )
    (net (code "11") (name "DATA_PIXEL22") (class "Default")
      (node (ref "PIXEL_22") (pin "5") (pinfunction "SDO_5") (pintype "bidirectional"))
      (node (ref "PIXEL_23") (pin "6") (pinfunction "SDI_6") (pintype "bidirectional"))
    )
    (net (code "12") (name "DATA_PIXEL23") (class "Default")
      (node (ref "PIXEL_23") (pin "5") (pinfunction "SDO_5") (pintype "bidirectional"))
      (node (ref "PIXEL_24") (pin "6") (pinfunction "SDI_6") (pintype "bidirectional"))
    )
    (net (code "13") (name "DATA_PIXEL24") (class "Default")
      (node (ref "PIXEL_24") (pin "5") (pinfunction "SDO_5") (pintype "bidirectional"))
      (node (ref "PIXEL_35") (pin "6") (pinfunction "SDI_6") (pintype "bidirectional"))
    )
    (net (code "14") (name "DATA_PIXEL32") (class "Default")
      (node (ref "PIXEL_31") (pin "6") (pinfunction "SDI_6") (pintype "bidirectional"))
      (node (ref "PIXEL_32") (pin "5") (pinfunction "SDO_5") (pintype "bidirectional"))
    )
    (net (code "15") (name "DATA_PIXEL33") (class "Default")
      (node (ref "PIXEL_32") (pin "6") (pinfunction "SDI_6") (pintype "bidirectional"))
      (node (ref "PIXEL_33") (pin "5") (pinfunction "SDO_5") (pintype "bidirectional"))
    )
    (net (code "16") (name "DATA_PIXEL34") (class "Default")
      (node (ref "PIXEL_33") (pin "6") (pinfunction "SDI_6") (pintype "bidirectional"))
      (node (ref "PIXEL_34") (pin "5") (pinfunction "SDO_5") (pintype "bidirectional"))
    )
    (net (code "17") (name "DATA_PIXEL35") (class "Default")
      (node (ref "PIXEL_34") (pin "6") (pinfunction "SDI_6") (pintype "bidirectional"))
      (node (ref "PIXEL_35") (pin "5") (pinfunction "SDO_5") (pintype "bidirectional"))
    )
    (net (code "18") (name "ENC_01_A") (class "Default")
      (node (ref "ENC_01") (pin "A") (pinfunction "A_A") (pintype "bidirectional"))
      (node (ref "RB104") (pin "1") (pinfunction "1_1") (pintype "passive"))
      (node (ref "TFT_EXT_2") (pin "3") (pinfunction "3_3") (pintype "passive"))
    )
    (net (code "19") (name "ENC_01_B") (class "Default")
      (node (ref "ENC_01") (pin "B") (pinfunction "B_B") (pintype "bidirectional"))
      (node (ref "RB105") (pin "1") (pinfunction "1_1") (pintype "passive"))
      (node (ref "TFT_EXT_2") (pin "5") (pinfunction "5_5") (pintype "passive"))
    )
    (net (code "20") (name "ENC_01_SW") (class "Default")
      (node (ref "ENC_01") (pin "3") (pinfunction "SW_3") (pintype "passive"))
      (node (ref "RB106") (pin "1") (pinfunction "1_1") (pintype "passive"))
      (node (ref "RPD33") (pin "1") (pinfunction "1_1") (pintype "passive"))
      (node (ref "TFT_EXT_2") (pin "6") (pinfunction "6_6") (pintype "passive"))
    )
    (net (code "21") (name "ENC_02_A") (class "Default")
      (node (ref "ENC_02") (pin "A") (pinfunction "A_A") (pintype "bidirectional"))
      (node (ref "RB110") (pin "1") (pinfunction "1_1") (pintype "passive"))
      (node (ref "TFT_EXT_2") (pin "11") (pinfunction "11_11") (pintype "passive"))
    )
    (net (code "22") (name "ENC_02_B") (class "Default")
      (node (ref "ENC_02") (pin "B") (pinfunction "B_B") (pintype "bidirectional"))
      (node (ref "RB111") (pin "1") (pinfunction "1_1") (pintype "passive"))
      (node (ref "TFT_EXT_2") (pin "12") (pinfunction "12_12") (pintype "passive"))
    )
    (net (code "23") (name "ENC_02_SW") (class "Default")
      (node (ref "ENC_02") (pin "3") (pinfunction "SW_3") (pintype "passive"))
      (node (ref "RB112") (pin "1") (pinfunction "1_1") (pintype "passive"))
      (node (ref "RPD35") (pin "1") (pinfunction "1_1") (pintype "passive"))
      (node (ref "TFT_EXT_2") (pin "4") (pinfunction "4_4") (pintype "passive"))
    )
    (net (code "24") (name "ENC_03_A") (class "Default")
      (node (ref "ENC_3") (pin "A") (pinfunction "A_A") (pintype "bidirectional"))
      (node (ref "RB116") (pin "1") (pinfunction "1_1") (pintype "passive"))
      (node (ref "TFT_EXT_2") (pin "10") (pinfunction "10_10") (pintype "passive"))
    )
    (net (code "25") (name "ENC_03_B") (class "Default")
      (node (ref "ENC_3") (pin "B") (pinfunction "B_B") (pintype "bidirectional"))
      (node (ref "RB117") (pin "1") (pinfunction "1_1") (pintype "passive"))
      (node (ref "TFT_EXT_2") (pin "8") (pinfunction "8_8") (pintype "passive"))
    )
    (net (code "26") (name "ENC_03_SW") (class "Default")
      (node (ref "ENC_3") (pin "3") (pinfunction "SW_3") (pintype "passive"))
      (node (ref "RB118") (pin "1") (pinfunction "1_1") (pintype "passive"))
      (node (ref "RPD37") (pin "1") (pinfunction "1_1") (pintype "passive"))
      (node (ref "TFT_EXT_2") (pin "2") (pinfunction "2_2") (pintype "passive"))
    )
    (net (code "27") (name "GND") (class "Default")
      (node (ref "0V/5V") (pin "1") (pinfunction "1_1") (pintype "passive"))
      (node (ref "0V/5V") (pin "2") (pinfunction "2_2") (pintype "passive"))
      (node (ref "ANALOG_IN") (pin "1") (pinfunction "1_1") (pintype "passive"))
      (node (ref "C10") (pin "1") (pinfunction "1_1") (pintype "passive"))
      (node (ref "C11") (pin "1") (pinfunction "1_1") (pintype "passive"))
      (node (ref "C12") (pin "2") (pinfunction "2_2") (pintype "passive"))
      (node (ref "C16") (pin "1") (pinfunction "1_1") (pintype "passive"))
      (node (ref "C17") (pin "1") (pinfunction "1_1") (pintype "passive"))
      (node (ref "C18") (pin "2") (pinfunction "2_2") (pintype "passive"))
      (node (ref "C22") (pin "1") (pinfunction "1_1") (pintype "passive"))
      (node (ref "C23") (pin "1") (pinfunction "1_1") (pintype "passive"))
      (node (ref "C24") (pin "2") (pinfunction "2_2") (pintype "passive"))
      (node (ref "C28") (pin "1") (pinfunction "1_1") (pintype "passive"))
      (node (ref "C29") (pin "1") (pinfunction "1_1") (pintype "passive"))
      (node (ref "C30") (pin "2") (pinfunction "2_2") (pintype "passive"))
      (node (ref "C34") (pin "1") (pinfunction "1_1") (pintype "passive"))
      (node (ref "C35") (pin "1") (pinfunction "1_1") (pintype "passive"))
      (node (ref "C36") (pin "2") (pinfunction "2_2") (pintype "passive"))
      (node (ref "C4") (pin "1") (pinfunction "1_1") (pintype "passive"))
      (node (ref "C40") (pin "1") (pinfunction "1_1") (pintype "passive"))
      (node (ref "C41") (pin "1") (pinfunction "1_1") (pintype "passive"))
      (node (ref "C42") (pin "2") (pinfunction "2_2") (pintype "passive"))
      (node (ref "C46") (pin "1") (pinfunction "1_1") (pintype "passive"))
      (node (ref "C47") (pin "1") (pinfunction "1_1") (pintype "passive"))
      (node (ref "C48") (pin "2") (pinfunction "2_2") (pintype "passive"))
      (node (ref "C5") (pin "1") (pinfunction "1_1") (pintype "passive"))
      (node (ref "C55") (pin "1") (pinfunction "1_1") (pintype "passive"))
      (node (ref "C6") (pin "2") (pinfunction "2_2") (pintype "passive"))
      (node (ref "C60") (pin "1") (pinfunction "1_1") (pintype "passive"))
      (node (ref "C62") (pin "-") (pinfunction "-_-") (pintype "passive"))
      (node (ref "C65") (pin "-") (pinfunction "-_-") (pintype "passive"))
      (node (ref "C66") (pin "1") (pinfunction "1_1") (pintype "passive"))
      (node (ref "C67") (pin "1") (pinfunction "1_1") (pintype "passive"))
      (node (ref "C68") (pin "1") (pinfunction "1_1") (pintype "passive"))
      (node (ref "C69") (pin "1") (pinfunction "1_1") (pintype "passive"))
      (node (ref "C7") (pin "1") (pinfunction "1_1") (pintype "passive"))
      (node (ref "C70") (pin "1") (pinfunction "1_1") (pintype "passive"))
      (node (ref "C71") (pin "1") (pinfunction "1_1") (pintype "passive"))
      (node (ref "C76") (pin "1") (pinfunction "1_1") (pintype "passive"))
      (node (ref "C8") (pin "1") (pinfunction "1_1") (pintype "passive"))
      (node (ref "C9") (pin "2") (pinfunction "2_2") (pintype "passive"))
      (node (ref "CB1") (pin "1") (pinfunction "1_1") (pintype "passive"))
      (node (ref "CB10") (pin "2") (pinfunction "2_2") (pintype "passive"))
      (node (ref "CB100") (pin "2") (pinfunction "2_2") (pintype "passive"))
      (node (ref "CB104") (pin "1") (pinfunction "1_1") (pintype "passive"))
      (node (ref "CB105") (pin "1") (pinfunction "1_1") (pintype "passive"))
      (node (ref "CB106") (pin "2") (pinfunction "2_2") (pintype "passive"))
      (node (ref "CB11") (pin "1") (pinfunction "1_1") (pintype "passive"))
      (node (ref "CB110") (pin "1") (pinfunction "1_1") (pintype "passive"))
      (node (ref "CB111") (pin "1") (pinfunction "1_1") (pintype "passive"))
      (node (ref "CB112") (pin "2") (pinfunction "2_2") (pintype "passive"))
      (node (ref "CB116") (pin "1") (pinfunction "1_1") (pintype "passive"))
      (node (ref "CB117") (pin "1") (pinfunction "1_1") (pintype "passive"))
      (node (ref "CB118") (pin "2") (pinfunction "2_2") (pintype "passive"))
      (node (ref "CB12") (pin "1") (pinfunction "1_1") (pintype "passive"))
      (node (ref "CB13") (pin "2") (pinfunction "2_2") (pintype "passive"))
      (node (ref "CB14") (pin "1") (pinfunction "1_1") (pintype "passive"))
      (node (ref "CB15") (pin "1") (pinfunction "1_1") (pintype "passive"))
      (node (ref "CB16") (pin "2") (pinfunction "2_2") (pintype "passive"))
      (node (ref "CB17") (pin "1") (pinfunction "1_1") (pintype "passive"))
      (node (ref "CB18") (pin "1") (pinfunction "1_1") (pintype "passive"))
      (node (ref "CB19") (pin "2") (pinfunction "2_2") (pintype "passive"))
      (node (ref "CB2") (pin "1") (pinfunction "1_1") (pintype "passive"))
      (node (ref "CB20") (pin "1") (pinfunction "1_1") (pintype "passive"))
      (node (ref "CB21") (pin "1") (pinfunction "1_1") (pintype "passive"))
      (node (ref "CB22") (pin "2") (pinfunction "2_2") (pintype "passive"))
      (node (ref "CB23") (pin "1") (pinfunction "1_1") (pintype "passive"))
      (node (ref "CB24") (pin "1") (pinfunction "1_1") (pintype "passive"))
      (node (ref "CB25") (pin "2") (pinfunction "2_2") (pintype "passive"))
      (node (ref "CB26") (pin "1") (pinfunction "1_1") (pintype "passive"))
      (node (ref "CB27") (pin "1") (pinfunction "1_1") (pintype "passive"))
      (node (ref "CB28") (pin "2") (pinfunction "2_2") (pintype "passive"))
      (node (ref "CB29") (pin "1") (pinfunction "1_1") (pintype "passive"))
      (node (ref "CB3") (pin "1") (pinfunction "1_1") (pintype "passive"))
      (node (ref "CB30") (pin "1") (pinfunction "1_1") (pintype "passive"))
      (node (ref "CB31") (pin "2") (pinfunction "2_2") (pintype "passive"))
      (node (ref "CB32") (pin "1") (pinfunction "1_1") (pintype "passive"))
      (node (ref "CB33") (pin "1") (pinfunction "1_1") (pintype "passive"))
      (node (ref "CB34") (pin "2") (pinfunction "2_2") (pintype "passive"))
      (node (ref "CB35") (pin "1") (pinfunction "1_1") (pintype "passive"))
      (node (ref "CB36") (pin "1") (pinfunction "1_1") (pintype "passive"))
      (node (ref "CB37") (pin "2") (pinfunction "2_2") (pintype "passive"))
      (node (ref "CB38") (pin "1") (pinfunction "1_1") (pintype "passive"))
      (node (ref "CB39") (pin "1") (pinfunction "1_1") (pintype "passive"))
      (node (ref "CB4") (pin "1") (pinfunction "1_1") (pintype "passive"))
      (node (ref "CB40") (pin "2") (pinfunction "2_2") (pintype "passive"))
      (node (ref "CB41") (pin "1") (pinfunction "1_1") (pintype "passive"))
      (node (ref "CB42") (pin "1") (pinfunction "1_1") (pintype "passive"))
      (node (ref "CB43") (pin "2") (pinfunction "2_2") (pintype "passive"))
      (node (ref "CB44") (pin "1") (pinfunction "1_1") (pintype "passive"))
      (node (ref "CB45") (pin "1") (pinfunction "1_1") (pintype "passive"))
      (node (ref "CB47") (pin "1") (pinfunction "1_1") (pintype "passive"))
      (node (ref "CB48") (pin "1") (pinfunction "1_1") (pintype "passive"))
      (node (ref "CB49") (pin "2") (pinfunction "2_2") (pintype "passive"))
      (node (ref "CB5") (pin "1") (pinfunction "1_1") (pintype "passive"))
      (node (ref "CB50") (pin "1") (pinfunction "1_1") (pintype "passive"))
      (node (ref "CB51") (pin "1") (pinfunction "1_1") (pintype "passive"))
      (node (ref "CB52") (pin "2") (pinfunction "2_2") (pintype "passive"))
      (node (ref "CB53") (pin "1") (pinfunction "1_1") (pintype "passive"))
      (node (ref "CB54") (pin "1") (pinfunction "1_1") (pintype "passive"))
      (node (ref "CB55") (pin "2") (pinfunction "2_2") (pintype "passive"))
      (node (ref "CB56") (pin "1") (pinfunction "1_1") (pintype "passive"))
      (node (ref "CB57") (pin "1") (pinfunction "1_1") (pintype "passive"))
      (node (ref "CB58") (pin "2") (pinfunction "2_2") (pintype "passive"))
      (node (ref "CB59") (pin "1") (pinfunction "1_1") (pintype "passive"))
      (node (ref "CB6") (pin "1") (pinfunction "1_1") (pintype "passive"))
      (node (ref "CB60") (pin "1") (pinfunction "1_1") (pintype "passive"))
      (node (ref "CB61") (pin "2") (pinfunction "2_2") (pintype "passive"))
      (node (ref "CB62") (pin "1") (pinfunction "1_1") (pintype "passive"))
      (node (ref "CB63") (pin "1") (pinfunction "1_1") (pintype "passive"))
      (node (ref "CB64") (pin "2") (pinfunction "2_2") (pintype "passive"))
      (node (ref "CB65") (pin "1") (pinfunction "1_1") (pintype "passive"))
      (node (ref "CB66") (pin "1") (pinfunction "1_1") (pintype "passive"))
      (node (ref "CB67") (pin "2") (pinfunction "2_2") (pintype "passive"))
      (node (ref "CB68") (pin "1") (pinfunction "1_1") (pintype "passive"))
      (node (ref "CB70") (pin "1") (pinfunction "1_1") (pintype "passive"))
      (node (ref "CB71") (pin "1") (pinfunction "1_1") (pintype "passive"))
      (node (ref "CB72") (pin "1") (pinfunction "1_1") (pintype "passive"))
      (node (ref "CB73") (pin "2") (pinfunction "2_2") (pintype "passive"))
      (node (ref "CB74") (pin "1") (pinfunction "1_1") (pintype "passive"))
      (node (ref "CB75") (pin "1") (pinfunction "1_1") (pintype "passive"))
      (node (ref "CB76") (pin "2") (pinfunction "2_2") (pintype "passive"))
      (node (ref "CB77") (pin "1") (pinfunction "1_1") (pintype "passive"))
      (node (ref "CB78") (pin "1") (pinfunction "1_1") (pintype "passive"))
      (node (ref "CB79") (pin "2") (pinfunction "2_2") (pintype "passive"))
      (node (ref "CB8") (pin "1") (pinfunction "1_1") (pintype "passive"))
      (node (ref "CB80") (pin "1") (pinfunction "1_1") (pintype "passive"))
      (node (ref "CB81") (pin "1") (pinfunction "1_1") (pintype "passive"))
      (node (ref "CB82") (pin "2") (pinfunction "2_2") (pintype "passive"))
      (node (ref "CB83") (pin "1") (pinfunction "1_1") (pintype "passive"))
      (node (ref "CB84") (pin "1") (pinfunction "1_1") (pintype "passive"))
      (node (ref "CB85") (pin "2") (pinfunction "2_2") (pintype "passive"))
      (node (ref "CB89") (pin "1") (pinfunction "1_1") (pintype "passive"))
      (node (ref "CB9") (pin "1") (pinfunction "1_1") (pintype "passive"))
      (node (ref "CB90") (pin "1") (pinfunction "1_1") (pintype "passive"))
      (node (ref "CB91") (pin "2") (pinfunction "2_2") (pintype "passive"))
      (node (ref "CB92") (pin "1") (pinfunction "1_1") (pintype "passive"))
      (node (ref "CB93") (pin "1") (pinfunction "1_1") (pintype "passive"))
      (node (ref "CB94") (pin "2") (pinfunction "2_2") (pintype "passive"))
      (node (ref "CB98") (pin "1") (pinfunction "1_1") (pintype "passive"))
      (node (ref "CB99") (pin "1") (pinfunction "1_1") (pintype "passive"))
      (node (ref "CDEC1") (pin "-") (pinfunction "-_-") (pintype "passive"))
      (node (ref "CDEC10") (pin "-") (pinfunction "-_-") (pintype "passive"))
      (node (ref "CDEC11") (pin "-") (pinfunction "-_-") (pintype "passive"))
      (node (ref "CDEC12") (pin "-") (pinfunction "-_-") (pintype "passive"))
      (node (ref "CDEC13") (pin "2") (pinfunction "2_2") (pintype "passive"))
      (node (ref "CDEC14") (pin "-") (pinfunction "-_-") (pintype "passive"))
      (node (ref "CDEC15") (pin "-") (pinfunction "-_-") (pintype "passive"))
      (node (ref "CDEC16") (pin "-") (pinfunction "-_-") (pintype "passive"))
      (node (ref "CDEC17") (pin "-") (pinfunction "-_-") (pintype "passive"))
      (node (ref "CDEC18") (pin "-") (pinfunction "-_-") (pintype "passive"))
      (node (ref "CDEC19") (pin "-") (pinfunction "-_-") (pintype "passive"))
      (node (ref "CDEC2") (pin "-") (pinfunction "-_-") (pintype "passive"))
      (node (ref "CDEC20") (pin "-") (pinfunction "-_-") (pintype "passive"))
      (node (ref "CDEC21") (pin "2") (pinfunction "2_2") (pintype "passive"))
      (node (ref "CDEC22") (pin "-") (pinfunction "-_-") (pintype "passive"))
      (node (ref "CDEC23") (pin "-") (pinfunction "-_-") (pintype "passive"))
      (node (ref "CDEC24") (pin "-") (pinfunction "-_-") (pintype "passive"))
      (node (ref "CDEC25") (pin "-") (pinfunction "-_-") (pintype "passive"))
      (node (ref "CDEC26") (pin "-") (pinfunction "-_-") (pintype "passive"))
      (node (ref "CDEC28") (pin "-") (pinfunction "-_-") (pintype "passive"))
      (node (ref "CDEC29") (pin "-") (pinfunction "-_-") (pintype "passive"))
      (node (ref "CDEC3") (pin "-") (pinfunction "-_-") (pintype "passive"))
      (node (ref "CDEC30") (pin "2") (pinfunction "2_2") (pintype "passive"))
      (node (ref "CDEC31") (pin "-") (pinfunction "-_-") (pintype "passive"))
      (node (ref "CDEC32") (pin "2") (pinfunction "2_2") (pintype "passive"))
      (node (ref "CDEC33") (pin "-") (pinfunction "-_-") (pintype "passive"))
      (node (ref "CDEC35") (pin "-") (pinfunction "-_-") (pintype "passive"))
      (node (ref "CDEC36") (pin "2") (pinfunction "2_2") (pintype "passive"))
      (node (ref "CDEC37") (pin "-") (pinfunction "-_-") (pintype "passive"))
      (node (ref "CDEC39") (pin "2") (pinfunction "2_2") (pintype "passive"))
      (node (ref "CDEC4") (pin "-") (pinfunction "-_-") (pintype "passive"))
      (node (ref "CDEC5") (pin "-") (pinfunction "-_-") (pintype "passive"))
      (node (ref "CDEC6") (pin "-") (pinfunction "-_-") (pintype "passive"))
      (node (ref "CDEC7") (pin "-") (pinfunction "-_-") (pintype "passive"))
      (node (ref "CDEC8") (pin "-") (pinfunction "-_-") (pintype "passive"))
      (node (ref "CDEC9") (pin "-") (pinfunction "-_-") (pintype "passive"))
      (node (ref "CDEC_1") (pin "2") (pinfunction "2_2") (pintype "passive"))
      (node (ref "CDEC_10") (pin "2") (pinfunction "2_2") (pintype "passive"))
      (node (ref "CDEC_11") (pin "2") (pinfunction "2_2") (pintype "passive"))
      (node (ref "CDEC_11A") (pin "-") (pinfunction "-_-") (pintype "passive"))
      (node (ref "CDEC_11B") (pin "2") (pinfunction "2_2") (pintype "passive"))
      (node (ref "CDEC_12") (pin "2") (pinfunction "2_2") (pintype "passive"))
      (node (ref "CDEC_12A") (pin "-") (pinfunction "-_-") (pintype "passive"))
      (node (ref "CDEC_12B") (pin "2") (pinfunction "2_2") (pintype "passive"))
      (node (ref "CDEC_13") (pin "2") (pinfunction "2_2") (pintype "passive"))
      (node (ref "CDEC_2") (pin "2") (pinfunction "2_2") (pintype "passive"))
      (node (ref "CDEC_2A1") (pin "-") (pinfunction "-_-") (pintype "passive"))
      (node (ref "CDEC_2A2") (pin "-") (pinfunction "-_-") (pintype "passive"))
      (node (ref "CDEC_2A3") (pin "-") (pinfunction "-_-") (pintype "passive"))
      (node (ref "CDEC_2B1") (pin "2") (pinfunction "2_2") (pintype "passive"))
      (node (ref "CDEC_2B2") (pin "2") (pinfunction "2_2") (pintype "passive"))
      (node (ref "CDEC_2B3") (pin "2") (pinfunction "2_2") (pintype "passive"))
      (node (ref "CDEC_3") (pin "2") (pinfunction "2_2") (pintype "passive"))
      (node (ref "CDEC_4") (pin "2") (pinfunction "2_2") (pintype "passive"))
      (node (ref "CDEC_41A") (pin "-") (pinfunction "-_-") (pintype "passive"))
      (node (ref "CDEC_41B") (pin "2") (pinfunction "2_2") (pintype "passive"))
      (node (ref "CDEC_42A") (pin "-") (pinfunction "-_-") (pintype "passive"))
      (node (ref "CDEC_42B") (pin "2") (pinfunction "2_2") (pintype "passive"))
      (node (ref "CDEC_5") (pin "2") (pinfunction "2_2") (pintype "passive"))
      (node (ref "CDEC_5A") (pin "-") (pinfunction "-_-") (pintype "passive"))
      (node (ref "CDEC_5B") (pin "2") (pinfunction "2_2") (pintype "passive"))
      (node (ref "CDEC_6") (pin "2") (pinfunction "2_2") (pintype "passive"))
      (node (ref "CDEC_7") (pin "2") (pinfunction "2_2") (pintype "passive"))
      (node (ref "CDEC_8") (pin "2") (pinfunction "2_2") (pintype "passive"))
      (node (ref "CDEC_9") (pin "2") (pinfunction "2_2") (pintype "passive"))
      (node (ref "CONN_STH_BRD_1") (pin "1") (pinfunction "1_1") (pintype "passive"))
      (node (ref "CONN_STH_BRD_2") (pin "1") (pinfunction "1_1") (pintype "passive"))
      (node (ref "CPOL1") (pin "2") (pinfunction "2_2") (pintype "passive"))
      (node (ref "CPOL10") (pin "2") (pinfunction "2_2") (pintype "passive"))
      (node (ref "CPOL11") (pin "2") (pinfunction "2_2") (pintype "passive"))
      (node (ref "CPOL12") (pin "2") (pinfunction "2_2") (pintype "passive"))
      (node (ref "CPOL13") (pin "-") (pinfunction "-_-") (pintype "passive"))
      (node (ref "CPOL14") (pin "2") (pinfunction "2_2") (pintype "passive"))
      (node (ref "CPOL15") (pin "2") (pinfunction "2_2") (pintype "passive"))
      (node (ref "CPOL16") (pin "2") (pinfunction "2_2") (pintype "passive"))
      (node (ref "CPOL17") (pin "2") (pinfunction "2_2") (pintype "passive"))
      (node (ref "CPOL18") (pin "2") (pinfunction "2_2") (pintype "passive"))
      (node (ref "CPOL19") (pin "2") (pinfunction "2_2") (pintype "passive"))
      (node (ref "CPOL2") (pin "2") (pinfunction "2_2") (pintype "passive"))
      (node (ref "CPOL20") (pin "2") (pinfunction "2_2") (pintype "passive"))
      (node (ref "CPOL21") (pin "-") (pinfunction "-_-") (pintype "passive"))
      (node (ref "CPOL22") (pin "2") (pinfunction "2_2") (pintype "passive"))
      (node (ref "CPOL23") (pin "2") (pinfunction "2_2") (pintype "passive"))
      (node (ref "CPOL24") (pin "2") (pinfunction "2_2") (pintype "passive"))
      (node (ref "CPOL25") (pin "2") (pinfunction "2_2") (pintype "passive"))
      (node (ref "CPOL26") (pin "2") (pinfunction "2_2") (pintype "passive"))
      (node (ref "CPOL28") (pin "2") (pinfunction "2_2") (pintype "passive"))
      (node (ref "CPOL29") (pin "2") (pinfunction "2_2") (pintype "passive"))
      (node (ref "CPOL3") (pin "2") (pinfunction "2_2") (pintype "passive"))
      (node (ref "CPOL30") (pin "-") (pinfunction "-_-") (pintype "passive"))
      (node (ref "CPOL31") (pin "2") (pinfunction "2_2") (pintype "passive"))
      (node (ref "CPOL32") (pin "-") (pinfunction "-_-") (pintype "passive"))
      (node (ref "CPOL33") (pin "2") (pinfunction "2_2") (pintype "passive"))
      (node (ref "CPOL35") (pin "2") (pinfunction "2_2") (pintype "passive"))
      (node (ref "CPOL36") (pin "-") (pinfunction "-_-") (pintype "passive"))
      (node (ref "CPOL37") (pin "2") (pinfunction "2_2") (pintype "passive"))
      (node (ref "CPOL39") (pin "-") (pinfunction "-_-") (pintype "passive"))
      (node (ref "CPOL4") (pin "2") (pinfunction "2_2") (pintype "passive"))
      (node (ref "CPOL5") (pin "2") (pinfunction "2_2") (pintype "passive"))
      (node (ref "CPOL6") (pin "2") (pinfunction "2_2") (pintype "passive"))
      (node (ref "CPOL7") (pin "2") (pinfunction "2_2") (pintype "passive"))
      (node (ref "CPOL8") (pin "2") (pinfunction "2_2") (pintype "passive"))
      (node (ref "CPOL9") (pin "2") (pinfunction "2_2") (pintype "passive"))
      (node (ref "ENC_01") (pin "C") (pinfunction "C_C") (pintype "bidirectional"))
      (node (ref "ENC_02") (pin "C") (pinfunction "C_C") (pintype "bidirectional"))
      (node (ref "ENC_11") (pin "C") (pinfunction "C_C") (pintype "bidirectional"))
      (node (ref "ENC_13") (pin "C") (pinfunction "C_C") (pintype "bidirectional"))
      (node (ref "ENC_14") (pin "C") (pinfunction "C_C") (pintype "bidirectional"))
      (node (ref "ENC_21") (pin "C") (pinfunction "C_C") (pintype "bidirectional"))
      (node (ref "ENC_23") (pin "C") (pinfunction "C_C") (pintype "bidirectional"))
      (node (ref "ENC_3") (pin "C") (pinfunction "C_C") (pintype "bidirectional"))
      (node (ref "ENC_41") (pin "C") (pinfunction "C_C") (pintype "bidirectional"))
      (node (ref "ENC_44") (pin "C") (pinfunction "C_C") (pintype "bidirectional"))
      (node (ref "ENC_45") (pin "C") (pinfunction "C_C") (pintype "bidirectional"))
      (node (ref "ENC_48") (pin "C") (pinfunction "C_C") (pintype "bidirectional"))
      (node (ref "ENC_51") (pin "C") (pinfunction "C_C") (pintype "bidirectional"))
      (node (ref "ENC_53") (pin "C") (pinfunction "C_C") (pintype "bidirectional"))
      (node (ref "ENC_54") (pin "C") (pinfunction "C_C") (pintype "bidirectional"))
      (node (ref "ENC_55") (pin "C") (pinfunction "C_C") (pintype "bidirectional"))
      (node (ref "ENC_56") (pin "C") (pinfunction "C_C") (pintype "bidirectional"))
      (node (ref "ENC_57") (pin "C") (pinfunction "C_C") (pintype "bidirectional"))
      (node (ref "ENC_61") (pin "C") (pinfunction "C_C") (pintype "bidirectional"))
      (node (ref "ENC_62") (pin "C") (pinfunction "C_C") (pintype "bidirectional"))
      (node (ref "ENC_63") (pin "C") (pinfunction "C_C") (pintype "bidirectional"))
      (node (ref "ENC_64") (pin "C") (pinfunction "C_C") (pintype "bidirectional"))
      (node (ref "ENC_71") (pin "C") (pinfunction "C_C") (pintype "bidirectional"))
      (node (ref "ENC_72") (pin "C") (pinfunction "C_C") (pintype "bidirectional"))
      (node (ref "ENC_73") (pin "C") (pinfunction "C_C") (pintype "bidirectional"))
      (node (ref "ENC_74") (pin "C") (pinfunction "C_C") (pintype "bidirectional"))
      (node (ref "ENC_75") (pin "C") (pinfunction "C_C") (pintype "bidirectional"))
      (node (ref "ENC_81") (pin "C") (pinfunction "C_C") (pintype "bidirectional"))
      (node (ref "ENC_82") (pin "C") (pinfunction "C_C") (pintype "bidirectional"))
      (node (ref "ENC_83") (pin "C") (pinfunction "C_C") (pintype "bidirectional"))
      (node (ref "ENC_84") (pin "C") (pinfunction "C_C") (pintype "bidirectional"))
      (node (ref "ENC_85") (pin "C") (pinfunction "C_C") (pintype "bidirectional"))
      (node (ref "ENC_86") (pin "C") (pinfunction "C_C") (pintype "bidirectional"))
      (node (ref "ENC_87") (pin "C") (pinfunction "C_C") (pintype "bidirectional"))
      (node (ref "ENC_88") (pin "C") (pinfunction "C_C") (pintype "bidirectional"))
      (node (ref "F446") (pin "12") (pinfunction "VSSA/VREF-_12") (pintype "power_in"))
      (node (ref "F446") (pin "18") (pinfunction "VSS_4_18") (pintype "power_in"))
      (node (ref "F446") (pin "31") (pinfunction "VSS_1_31") (pintype "power_in"))
      (node (ref "F446") (pin "47") (pinfunction "VSS_2_47") (pintype "power_in"))
      (node (ref "F446") (pin "63") (pinfunction "VSS_3_63") (pintype "power_in"))
      (node (ref "GREEN") (pin "C") (pinfunction "C_C") (pintype "passive"))
      (node (ref "LED_3V3") (pin "C") (pinfunction "C_C") (pintype "passive"))
      (node (ref "LED_5V") (pin "C") (pinfunction "C_C") (pintype "passive"))
      (node (ref "MCP_000") (pin "10") (pinfunction "VSS_10") (pintype "bidirectional"))
      (node (ref "MCP_000") (pin "15") (pinfunction "A0_15") (pintype "bidirectional"))
      (node (ref "MCP_000") (pin "16") (pinfunction "A1_16") (pintype "bidirectional"))
      (node (ref "MCP_000") (pin "17") (pinfunction "A2_17") (pintype "bidirectional"))
      (node (ref "MCP_001") (pin "10") (pinfunction "VSS_10") (pintype "bidirectional"))
      (node (ref "MCP_001") (pin "16") (pinfunction "A1_16") (pintype "bidirectional"))
      (node (ref "MCP_001") (pin "17") (pinfunction "A2_17") (pintype "bidirectional"))
      (node (ref "MCP_010") (pin "10") (pinfunction "VSS_10") (pintype "bidirectional"))
      (node (ref "MCP_010") (pin "15") (pinfunction "A0_15") (pintype "bidirectional"))
      (node (ref "MCP_010") (pin "17") (pinfunction "A2_17") (pintype "bidirectional"))
      (node (ref "MCP_011") (pin "10") (pinfunction "VSS_10") (pintype "bidirectional"))
      (node (ref "MCP_011") (pin "17") (pinfunction "A2_17") (pintype "bidirectional"))
      (node (ref "MCP_100") (pin "10") (pinfunction "VSS_10") (pintype "bidirectional"))
      (node (ref "MCP_100") (pin "15") (pinfunction "A0_15") (pintype "bidirectional"))
      (node (ref "MCP_100") (pin "16") (pinfunction "A1_16") (pintype "bidirectional"))
      (node (ref "MCP_101") (pin "10") (pinfunction "VSS_10") (pintype "bidirectional"))
      (node (ref "MCP_101") (pin "16") (pinfunction "A1_16") (pintype "bidirectional"))
      (node (ref "MCP_110") (pin "10") (pinfunction "VSS_10") (pintype "bidirectional"))
      (node (ref "MCP_110") (pin "15") (pinfunction "A0_15") (pintype "bidirectional"))
      (node (ref "MCP_111") (pin "10") (pinfunction "VSS_10") (pintype "bidirectional"))
      (node (ref "PIXEL_01") (pin "4") (pinfunction "GND_4") (pintype "bidirectional"))
      (node (ref "PIXEL_02") (pin "4") (pinfunction "GND_4") (pintype "bidirectional"))
      (node (ref "PIXEL_03") (pin "4") (pinfunction "GND_4") (pintype "bidirectional"))
      (node (ref "PIXEL_11") (pin "4") (pinfunction "GND_4") (pintype "bidirectional"))
      (node (ref "PIXEL_12") (pin "4") (pinfunction "GND_4") (pintype "bidirectional"))
      (node (ref "PIXEL_13") (pin "4") (pinfunction "GND_4") (pintype "bidirectional"))
      (node (ref "PIXEL_14") (pin "4") (pinfunction "GND_4") (pintype "bidirectional"))
      (node (ref "PIXEL_21") (pin "4") (pinfunction "GND_4") (pintype "bidirectional"))
      (node (ref "PIXEL_22") (pin "4") (pinfunction "GND_4") (pintype "bidirectional"))
      (node (ref "PIXEL_23") (pin "4") (pinfunction "GND_4") (pintype "bidirectional"))
      (node (ref "PIXEL_24") (pin "4") (pinfunction "GND_4") (pintype "bidirectional"))
      (node (ref "PIXEL_31") (pin "4") (pinfunction "GND_4") (pintype "bidirectional"))
      (node (ref "PIXEL_32") (pin "4") (pinfunction "GND_4") (pintype "bidirectional"))
      (node (ref "PIXEL_33") (pin "4") (pinfunction "GND_4") (pintype "bidirectional"))
      (node (ref "PIXEL_34") (pin "4") (pinfunction "GND_4") (pintype "bidirectional"))
      (node (ref "PIXEL_35") (pin "4") (pinfunction "GND_4") (pintype "bidirectional"))
      (node (ref "PIXEL_41") (pin "4") (pinfunction "GND_4") (pintype "bidirectional"))
      (node (ref "PIXEL_42") (pin "4") (pinfunction "GND_4") (pintype "bidirectional"))
      (node (ref "PIXEL_43") (pin "4") (pinfunction "GND_4") (pintype "bidirectional"))
      (node (ref "PIXEL_44") (pin "4") (pinfunction "GND_4") (pintype "bidirectional"))
      (node (ref "PIXEL_45") (pin "4") (pinfunction "GND_4") (pintype "bidirectional"))
      (node (ref "PIXEL_46") (pin "4") (pinfunction "GND_4") (pintype "bidirectional"))
      (node (ref "PIXEL_47") (pin "4") (pinfunction "GND_4") (pintype "bidirectional"))
      (node (ref "PIXEL_48") (pin "4") (pinfunction "GND_4") (pintype "bidirectional"))
      (node (ref "PIXEL_51") (pin "4") (pinfunction "GND_4") (pintype "bidirectional"))
      (node (ref "PIXEL_52") (pin "4") (pinfunction "GND_4") (pintype "bidirectional"))
      (node (ref "PIXEL_53") (pin "4") (pinfunction "GND_4") (pintype "bidirectional"))
      (node (ref "PIXEL_54") (pin "4") (pinfunction "GND_4") (pintype "bidirectional"))
      (node (ref "PIXEL_55") (pin "4") (pinfunction "GND_4") (pintype "bidirectional"))
      (node (ref "PIXEL_56") (pin "4") (pinfunction "GND_4") (pintype "bidirectional"))
      (node (ref "PIXEL_57") (pin "4") (pinfunction "GND_4") (pintype "bidirectional"))
      (node (ref "PIXEL_61") (pin "4") (pinfunction "GND_4") (pintype "bidirectional"))
      (node (ref "PIXEL_62") (pin "4") (pinfunction "GND_4") (pintype "bidirectional"))
      (node (ref "PIXEL_63") (pin "4") (pinfunction "GND_4") (pintype "bidirectional"))
      (node (ref "PIXEL_64") (pin "4") (pinfunction "GND_4") (pintype "bidirectional"))
      (node (ref "PIXEL_65") (pin "4") (pinfunction "GND_4") (pintype "bidirectional"))
      (node (ref "PIXEL_71") (pin "4") (pinfunction "GND_4") (pintype "bidirectional"))
      (node (ref "PIXEL_72") (pin "4") (pinfunction "GND_4") (pintype "bidirectional"))
      (node (ref "PIXEL_73") (pin "4") (pinfunction "GND_4") (pintype "bidirectional"))
      (node (ref "PIXEL_74") (pin "4") (pinfunction "GND_4") (pintype "bidirectional"))
      (node (ref "PIXEL_75") (pin "4") (pinfunction "GND_4") (pintype "bidirectional"))
      (node (ref "PIXEL_81") (pin "4") (pinfunction "GND_4") (pintype "bidirectional"))
      (node (ref "PIXEL_83") (pin "4") (pinfunction "GND_4") (pintype "bidirectional"))
      (node (ref "PIXEL_84") (pin "4") (pinfunction "GND_4") (pintype "bidirectional"))
      (node (ref "PIXEL_85") (pin "4") (pinfunction "GND_4") (pintype "bidirectional"))
      (node (ref "PIXEL_86") (pin "4") (pinfunction "GND_4") (pintype "bidirectional"))
      (node (ref "PIXEL_87") (pin "4") (pinfunction "GND_4") (pintype "bidirectional"))
      (node (ref "PIXEL_88") (pin "4") (pinfunction "GND_4") (pintype "bidirectional"))
      (node (ref "PIXE_82") (pin "4") (pinfunction "GND_4") (pintype "bidirectional"))
      (node (ref "R105") (pin "2") (pinfunction "2_2") (pintype "passive"))
      (node (ref "R119") (pin "2") (pinfunction "2_2") (pintype "passive"))
      (node (ref "R13") (pin "2") (pinfunction "2_2") (pintype "passive"))
      (node (ref "R20") (pin "2") (pinfunction "2_2") (pintype "passive"))
      (node (ref "R27") (pin "2") (pinfunction "2_2") (pintype "passive"))
      (node (ref "R41") (pin "2") (pinfunction "2_2") (pintype "passive"))
      (node (ref "R55") (pin "2") (pinfunction "2_2") (pintype "passive"))
      (node (ref "R69") (pin "2") (pinfunction "2_2") (pintype "passive"))
      (node (ref "R81") (pin "2") (pinfunction "2_2") (pintype "passive"))
      (node (ref "R88") (pin "2") (pinfunction "2_2") (pintype "passive"))
      (node (ref "RPD1") (pin "2") (pinfunction "2_2") (pintype "passive"))
      (node (ref "RPD10") (pin "2") (pinfunction "2_2") (pintype "passive"))
      (node (ref "RPD11") (pin "2") (pinfunction "2_2") (pintype "passive"))
      (node (ref "RPD12") (pin "2") (pinfunction "2_2") (pintype "passive"))
      (node (ref "RPD14") (pin "2") (pinfunction "2_2") (pintype "passive"))
      (node (ref "RPD15") (pin "2") (pinfunction "2_2") (pintype "passive"))
      (node (ref "RPD16") (pin "2") (pinfunction "2_2") (pintype "passive"))
      (node (ref "RPD17") (pin "2") (pinfunction "2_2") (pintype "passive"))
      (node (ref "RPD18") (pin "2") (pinfunction "2_2") (pintype "passive"))
      (node (ref "RPD19") (pin "2") (pinfunction "2_2") (pintype "passive"))
      (node (ref "RPD2") (pin "2") (pinfunction "2_2") (pintype "passive"))
      (node (ref "RPD20") (pin "2") (pinfunction "2_2") (pintype "passive"))
      (node (ref "RPD22") (pin "2") (pinfunction "2_2") (pintype "passive"))
      (node (ref "RPD23") (pin "2") (pinfunction "2_2") (pintype "passive"))
      (node (ref "RPD24") (pin "2") (pinfunction "2_2") (pintype "passive"))
      (node (ref "RPD25") (pin "2") (pinfunction "2_2") (pintype "passive"))
      (node (ref "RPD26") (pin "2") (pinfunction "2_2") (pintype "passive"))
      (node (ref "RPD28") (pin "2") (pinfunction "2_2") (pintype "passive"))
      (node (ref "RPD29") (pin "2") (pinfunction "2_2") (pintype "passive"))
      (node (ref "RPD3") (pin "2") (pinfunction "2_2") (pintype "passive"))
      (node (ref "RPD31") (pin "2") (pinfunction "2_2") (pintype "passive"))
      (node (ref "RPD33") (pin "2") (pinfunction "2_2") (pintype "passive"))
      (node (ref "RPD35") (pin "2") (pinfunction "2_2") (pintype "passive"))
      (node (ref "RPD37") (pin "2") (pinfunction "2_2") (pintype "passive"))
      (node (ref "RPD4") (pin "2") (pinfunction "2_2") (pintype "passive"))
      (node (ref "RPD5") (pin "2") (pinfunction "2_2") (pintype "passive"))
      (node (ref "RPD6") (pin "2") (pinfunction "2_2") (pintype "passive"))
      (node (ref "RPD7") (pin "2") (pinfunction "2_2") (pintype "passive"))
      (node (ref "RPD8") (pin "2") (pinfunction "2_2") (pintype "passive"))
      (node (ref "RPD9") (pin "2") (pinfunction "2_2") (pintype "passive"))
      (node (ref "S2") (pin "1") (pinfunction "1_1") (pintype "bidirectional"))
      (node (ref "S24") (pin "C") (pinfunction "C_C") (pintype "bidirectional"))
      (node (ref "S31") (pin "C") (pinfunction "C_C") (pintype "bidirectional"))
      (node (ref "S32") (pin "1") (pinfunction "1_1") (pintype "passive"))
      (node (ref "S32") (pin "2") (pinfunction "2_2") (pintype "passive"))
      (node (ref "S33") (pin "1") (pinfunction "1_1") (pintype "passive"))
      (node (ref "S33") (pin "2") (pinfunction "2_2") (pintype "passive"))
      (node (ref "S34") (pin "C") (pinfunction "C_C") (pintype "bidirectional"))
      (node (ref "S35") (pin "C") (pinfunction "C_C") (pintype "bidirectional"))
      (node (ref "STLINK") (pin "5") (pinfunction "5_5") (pintype "passive"))
      (node (ref "SW_42") (pin "1") (pinfunction "1_1") (pintype "passive"))
      (node (ref "SW_42") (pin "2") (pinfunction "2_2") (pintype "passive"))
      (node (ref "SW_43") (pin "1") (pinfunction "1_1") (pintype "passive"))
      (node (ref "SW_43") (pin "2") (pinfunction "2_2") (pintype "passive"))
      (node (ref "SW_46") (pin "1") (pinfunction "1_1") (pintype "passive"))
      (node (ref "SW_46") (pin "2") (pinfunction "2_2") (pintype "passive"))
      (node (ref "SW_47") (pin "1") (pinfunction "1_1") (pintype "passive"))
      (node (ref "SW_47") (pin "2") (pinfunction "2_2") (pintype "passive"))
      (node (ref "SW_52") (pin "1") (pinfunction "1_1") (pintype "passive"))
      (node (ref "SW_52") (pin "2") (pinfunction "2_2") (pintype "passive"))
      (node (ref "SW_65") (pin "1") (pinfunction "1_1") (pintype "passive"))
      (node (ref "SW_65") (pin "2") (pinfunction "2_2") (pintype "passive"))
      (node (ref "S_12") (pin "1") (pinfunction "1_1") (pintype "passive"))
      (node (ref "S_12") (pin "2") (pinfunction "2_2") (pintype "passive"))
      (node (ref "S_22") (pin "1") (pinfunction "1_1") (pintype "passive"))
      (node (ref "S_22") (pin "2") (pinfunction "2_2") (pintype "passive"))
      (node (ref "TFT_EXT") (pin "7") (pinfunction "7_7") (pintype "passive"))
      (node (ref "TFT_EXT_2") (pin "7") (pinfunction "7_7") (pintype "passive"))
      (node (ref "TLV75533") (pin "2") (pinfunction "GND_2") (pintype "power_in"))
      (node (ref "UART_ANALOG") (pin "1") (pinfunction "1_1") (pintype "passive"))
      (node (ref "UART_DISCO") (pin "1") (pinfunction "1_1") (pintype "passive"))
      (node (ref "UART_MIDI") (pin "1") (pinfunction "1_1") (pintype "passive"))
    )
    (net (code "28") (name "GPA0_2") (class "Default")
      (node (ref "MCP_010") (pin "21") (pinfunction "GPA0_21") (pintype "bidirectional"))
      (node (ref "RB70") (pin "1") (pinfunction "1_1") (pintype "passive"))
      (node (ref "SW_47") (pin "3") (pinfunction "3_3") (pintype "passive"))
      (node (ref "SW_47") (pin "4") (pinfunction "4_4") (pintype "passive"))
    )
    (net (code "29") (name "GPA0_5") (class "Default")
      (node (ref "ENC_74") (pin "3") (pinfunction "SW_3") (pintype "passive"))
      (node (ref "MCP_111") (pin "21") (pinfunction "GPA0_21") (pintype "bidirectional"))
      (node (ref "RB94") (pin "1") (pinfunction "1_1") (pintype "passive"))
      (node (ref "RPD29") (pin "1") (pinfunction "1_1") (pintype "passive"))
    )
    (net (code "30") (name "GPA0_11") (class "Default")
      (node (ref "MCP_000") (pin "21") (pinfunction "GPA0_21") (pintype "bidirectional"))
      (node (ref "R71") (pin "1") (pinfunction "1_1") (pintype "passive"))
      (node (ref "S24") (pin "B") (pinfunction "B_B") (pintype "bidirectional"))
    )
    (net (code "31") (name "GPA0_12") (class "Default")
      (node (ref "MCP_001") (pin "21") (pinfunction "GPA0_21") (pintype "bidirectional"))
      (node (ref "R121") (pin "1") (pinfunction "1_1") (pintype "passive"))
      (node (ref "S35") (pin "B") (pinfunction "B_B") (pintype "bidirectional"))
    )
    (net (code "32") (name "GPA0_31") (class "Default")
      (node (ref "ENC_51") (pin "A") (pinfunction "A_A") (pintype "bidirectional"))
      (node (ref "MCP_011") (pin "21") (pinfunction "GPA0_21") (pintype "bidirectional"))
      (node (ref "RB8") (pin "1") (pinfunction "1_1") (pintype "passive"))
    )
    (net (code "33") (name "GPA0_32") (class "Default")
      (node (ref "MCP_100") (pin "21") (pinfunction "GPA0_21") (pintype "bidirectional"))
      (node (ref "RB44") (pin "1") (pinfunction "1_1") (pintype "passive"))
      (node (ref "SW_65") (pin "3") (pinfunction "3_3") (pintype "passive"))
      (node (ref "SW_65") (pin "4") (pinfunction "4_4") (pintype "passive"))
    )
    (net (code "34") (name "GPA0_41") (class "Default")
      (node (ref "ENC_81") (pin "3") (pinfunction "SW_3") (pintype "passive"))
      (node (ref "MCP_101") (pin "21") (pinfunction "GPA0_21") (pintype "bidirectional"))
      (node (ref "RB79") (pin "1") (pinfunction "1_1") (pintype "passive"))
      (node (ref "RPD24") (pin "1") (pinfunction "1_1") (pintype "passive"))
    )
    (net (code "35") (name "GPA0_42") (class "Default")
      (node (ref "ENC_83") (pin "A") (pinfunction "A_A") (pintype "bidirectional"))
      (node (ref "MCP_110") (pin "21") (pinfunction "GPA0_21") (pintype "bidirectional"))
      (node (ref "RB38") (pin "1") (pinfunction "1_1") (pintype "passive"))
    )
    (net (code "36") (name "GPA1_2") (class "Default")
      (node (ref "ENC_45") (pin "A") (pinfunction "A_A") (pintype "bidirectional"))
      (node (ref "MCP_010") (pin "22") (pinfunction "GPA1_22") (pintype "bidirectional"))
      (node (ref "RB23") (pin "1") (pinfunction "1_1") (pintype "passive"))
    )
    (net (code "37") (name "GPA1_5") (class "Default")
      (node (ref "ENC_74") (pin "B") (pinfunction "B_B") (pintype "bidirectional"))
      (node (ref "MCP_111") (pin "22") (pinfunction "GPA1_22") (pintype "bidirectional"))
      (node (ref "RB93") (pin "1") (pinfunction "1_1") (pintype "passive"))
    )
    (net (code "38") (name "GPA1_11") (class "Default")
      (node (ref "MCP_000") (pin "22") (pinfunction "GPA1_22") (pintype "bidirectional"))
      (node (ref "R70") (pin "1") (pinfunction "1_1") (pintype "passive"))
      (node (ref "S24") (pin "A") (pinfunction "A_A") (pintype "bidirectional"))
    )
    (net (code "39") (name "GPA1_12") (class "Default")
      (node (ref "MCP_001") (pin "22") (pinfunction "GPA1_22") (pintype "bidirectional"))
      (node (ref "R119") (pin "1") (pinfunction "1_1") (pintype "passive"))
      (node (ref "R122") (pin "1") (pinfunction "1_1") (pintype "passive"))
      (node (ref "S35") (pin "3") (pinfunction "SW_3") (pintype "passive"))
    )
    (net (code "40") (name "GPA1_31") (class "Default")
      (node (ref "ENC_51") (pin "B") (pinfunction "B_B") (pintype "bidirectional"))
      (node (ref "MCP_011") (pin "22") (pinfunction "GPA1_22") (pintype "bidirectional"))
      (node (ref "RB9") (pin "1") (pinfunction "1_1") (pintype "passive"))
    )
    (net (code "41") (name "GPA1_32") (class "Default")
      (node (ref "ENC_64") (pin "3") (pinfunction "SW_3") (pintype "passive"))
      (node (ref "MCP_100") (pin "22") (pinfunction "GPA1_22") (pintype "bidirectional"))
      (node (ref "RB73") (pin "1") (pinfunction "1_1") (pintype "passive"))
      (node (ref "RPD22") (pin "1") (pinfunction "1_1") (pintype "passive"))
    )
    (net (code "42") (name "GPA1_41") (class "Default")
      (node (ref "ENC_82") (pin "3") (pinfunction "SW_3") (pintype "passive"))
      (node (ref "MCP_101") (pin "22") (pinfunction "GPA1_22") (pintype "bidirectional"))
      (node (ref "RB22") (pin "1") (pinfunction "1_1") (pintype "passive"))
      (node (ref "RPD5") (pin "1") (pinfunction "1_1") (pintype "passive"))
    )
    (net (code "43") (name "GPA1_42") (class "Default")
      (node (ref "ENC_83") (pin "B") (pinfunction "B_B") (pintype "bidirectional"))
      (node (ref "MCP_110") (pin "22") (pinfunction "GPA1_22") (pintype "bidirectional"))
      (node (ref "RB39") (pin "1") (pinfunction "1_1") (pintype "passive"))
    )
    (net (code "44") (name "GPA2_2") (class "Default")
      (node (ref "ENC_45") (pin "B") (pinfunction "B_B") (pintype "bidirectional"))
      (node (ref "MCP_010") (pin "23") (pinfunction "GPA2_23") (pintype "bidirectional"))
      (node (ref "RB24") (pin "1") (pinfunction "1_1") (pintype "passive"))
    )
    (net (code "45") (name "GPA2_5") (class "Default")
      (node (ref "ENC_74") (pin "A") (pinfunction "A_A") (pintype "bidirectional"))
      (node (ref "MCP_111") (pin "23") (pinfunction "GPA2_23") (pintype "bidirectional"))
      (node (ref "RB92") (pin "1") (pinfunction "1_1") (pintype "passive"))
    )
    (net (code "46") (name "GPA2_11") (class "Default")
      (node (ref "MCP_000") (pin "23") (pinfunction "GPA2_23") (pintype "bidirectional"))
      (node (ref "R69") (pin "1") (pinfunction "1_1") (pintype "passive"))
      (node (ref "R72") (pin "1") (pinfunction "1_1") (pintype "passive"))
      (node (ref "S24") (pin "3") (pinfunction "SW_3") (pintype "passive"))
    )
    (net (code "47") (name "GPA2_12") (class "Default")
      (node (ref "MCP_001") (pin "23") (pinfunction "GPA2_23") (pintype "bidirectional"))
      (node (ref "R120") (pin "1") (pinfunction "1_1") (pintype "passive"))
      (node (ref "S35") (pin "A") (pinfunction "A_A") (pintype "bidirectional"))
    )
    (net (code "48") (name "GPA2_31") (class "Default")
      (node (ref "ENC_51") (pin "3") (pinfunction "SW_3") (pintype "passive"))
      (node (ref "MCP_011") (pin "23") (pinfunction "GPA2_23") (pintype "bidirectional"))
      (node (ref "RB10") (pin "1") (pinfunction "1_1") (pintype "passive"))
      (node (ref "RPD1") (pin "1") (pinfunction "1_1") (pintype "passive"))
    )
    (net (code "49") (name "GPA2_32") (class "Default")
      (node (ref "ENC_64") (pin "B") (pinfunction "B_B") (pintype "bidirectional"))
      (node (ref "MCP_100") (pin "23") (pinfunction "GPA2_23") (pintype "bidirectional"))
      (node (ref "RB72") (pin "1") (pinfunction "1_1") (pintype "passive"))
    )
    (net (code "50") (name "GPA2_41") (class "Default")
      (node (ref "ENC_82") (pin "A") (pinfunction "A_A") (pintype "bidirectional"))
      (node (ref "MCP_101") (pin "23") (pinfunction "GPA2_23") (pintype "bidirectional"))
      (node (ref "RB20") (pin "1") (pinfunction "1_1") (pintype "passive"))
    )
    (net (code "51") (name "GPA2_42") (class "Default")
      (node (ref "ENC_84") (pin "A") (pinfunction "A_A") (pintype "bidirectional"))
      (node (ref "MCP_110") (pin "23") (pinfunction "GPA2_23") (pintype "bidirectional"))
      (node (ref "RB50") (pin "1") (pinfunction "1_1") (pintype "passive"))
    )
    (net (code "52") (name "GPA3_2") (class "Default")
      (node (ref "ENC_45") (pin "3") (pinfunction "SW_3") (pintype "passive"))
      (node (ref "MCP_010") (pin "24") (pinfunction "GPA3_24") (pintype "bidirectional"))
      (node (ref "RB25") (pin "1") (pinfunction "1_1") (pintype "passive"))
      (node (ref "RPD6") (pin "1") (pinfunction "1_1") (pintype "passive"))
    )
    (net (code "53") (name "GPA3_5") (class "Default")
      (node (ref "ENC_73") (pin "3") (pinfunction "SW_3") (pintype "passive"))
      (node (ref "MCP_111") (pin "24") (pinfunction "GPA3_24") (pintype "bidirectional"))
      (node (ref "RB82") (pin "1") (pinfunction "1_1") (pintype "passive"))
      (node (ref "RPD25") (pin "1") (pinfunction "1_1") (pintype "passive"))
    )
    (net (code "54") (name "GPA3_11") (class "Default")
      (node (ref "ENC_23") (pin "A") (pinfunction "A_A") (pintype "bidirectional"))
      (node (ref "MCP_000") (pin "24") (pinfunction "GPA3_24") (pintype "bidirectional"))
      (node (ref "R56") (pin "1") (pinfunction "1_1") (pintype "passive"))
    )
    (net (code "55") (name "GPA3_12") (class "Default")
      (node (ref "MCP_001") (pin "24") (pinfunction "GPA3_24") (pintype "bidirectional"))
      (node (ref "R107") (pin "1") (pinfunction "1_1") (pintype "passive"))
      (node (ref "S34") (pin "B") (pinfunction "B_B") (pintype "bidirectional"))
    )
    (net (code "56") (name "GPA3_31") (class "Default")
      (node (ref "MCP_011") (pin "24") (pinfunction "GPA3_24") (pintype "bidirectional"))
      (node (ref "RB5") (pin "1") (pinfunction "1_1") (pintype "passive"))
      (node (ref "SW_52") (pin "3") (pinfunction "3_3") (pintype "passive"))
      (node (ref "SW_52") (pin "4") (pinfunction "4_4") (pintype "passive"))
    )
    (net (code "57") (name "GPA3_32") (class "Default")
      (node (ref "ENC_64") (pin "A") (pinfunction "A_A") (pintype "bidirectional"))
      (node (ref "MCP_100") (pin "24") (pinfunction "GPA3_24") (pintype "bidirectional"))
      (node (ref "RB71") (pin "1") (pinfunction "1_1") (pintype "passive"))
    )
    (net (code "58") (name "GPA3_41") (class "Default")
      (node (ref "ENC_82") (pin "B") (pinfunction "B_B") (pintype "bidirectional"))
      (node (ref "MCP_101") (pin "24") (pinfunction "GPA3_24") (pintype "bidirectional"))
      (node (ref "RB21") (pin "1") (pinfunction "1_1") (pintype "passive"))
    )
    (net (code "59") (name "GPA3_42") (class "Default")
      (node (ref "ENC_84") (pin "B") (pinfunction "B_B") (pintype "bidirectional"))
      (node (ref "MCP_110") (pin "24") (pinfunction "GPA3_24") (pintype "bidirectional"))
      (node (ref "RB51") (pin "1") (pinfunction "1_1") (pintype "passive"))
    )
    (net (code "60") (name "GPA4_2") (class "Default")
      (node (ref "MCP_010") (pin "25") (pinfunction "GPA4_25") (pintype "bidirectional"))
      (node (ref "RB68") (pin "1") (pinfunction "1_1") (pintype "passive"))
      (node (ref "SW_46") (pin "3") (pinfunction "3_3") (pintype "passive"))
      (node (ref "SW_46") (pin "4") (pinfunction "4_4") (pintype "passive"))
    )
    (net (code "61") (name "GPA4_5") (class "Default")
      (node (ref "ENC_86") (pin "A") (pinfunction "A_A") (pintype "bidirectional"))
      (node (ref "MCP_111") (pin "25") (pinfunction "GPA4_25") (pintype "bidirectional"))
      (node (ref "RB74") (pin "1") (pinfunction "1_1") (pintype "passive"))
    )
    (net (code "62") (name "GPA4_11") (class "Default")
      (node (ref "ENC_23") (pin "B") (pinfunction "B_B") (pintype "bidirectional"))
      (node (ref "MCP_000") (pin "25") (pinfunction "GPA4_25") (pintype "bidirectional"))
      (node (ref "R57") (pin "1") (pinfunction "1_1") (pintype "passive"))
    )
    (net (code "63") (name "GPA4_12") (class "Default")
      (node (ref "MCP_001") (pin "25") (pinfunction "GPA4_25") (pintype "bidirectional"))
      (node (ref "R106") (pin "1") (pinfunction "1_1") (pintype "passive"))
      (node (ref "S34") (pin "A") (pinfunction "A_A") (pintype "bidirectional"))
    )
    (net (code "64") (name "GPA4_31") (class "Default")
      (node (ref "ENC_53") (pin "3") (pinfunction "SW_3") (pintype "passive"))
      (node (ref "MCP_011") (pin "25") (pinfunction "GPA4_25") (pintype "bidirectional"))
      (node (ref "RB16") (pin "1") (pinfunction "1_1") (pintype "passive"))
      (node (ref "RPD3") (pin "1") (pinfunction "1_1") (pintype "passive"))
    )
    (net (code "65") (name "GPA4_32") (class "Default")
      (node (ref "ENC_63") (pin "3") (pinfunction "SW_3") (pintype "passive"))
      (node (ref "MCP_100") (pin "25") (pinfunction "GPA4_25") (pintype "bidirectional"))
      (node (ref "RB67") (pin "1") (pinfunction "1_1") (pintype "passive"))
      (node (ref "RPD20") (pin "1") (pinfunction "1_1") (pintype "passive"))
    )
    (net (code "66") (name "GPA4_41") (class "Default")
      (node (ref "ENC_83") (pin "3") (pinfunction "SW_3") (pintype "passive"))
      (node (ref "MCP_101") (pin "25") (pinfunction "GPA4_25") (pintype "bidirectional"))
      (node (ref "RB40") (pin "1") (pinfunction "1_1") (pintype "passive"))
      (node (ref "RPD11") (pin "1") (pinfunction "1_1") (pintype "passive"))
    )
    (net (code "67") (name "GPA4_42") (class "Default")
      (node (ref "ENC_84") (pin "3") (pinfunction "SW_3") (pintype "passive"))
      (node (ref "MCP_110") (pin "25") (pinfunction "GPA4_25") (pintype "bidirectional"))
      (node (ref "RB52") (pin "1") (pinfunction "1_1") (pintype "passive"))
      (node (ref "RPD15") (pin "1") (pinfunction "1_1") (pintype "passive"))
    )
    (net (code "68") (name "GPA5_2") (class "Default")
      (node (ref "ENC_48") (pin "A") (pinfunction "A_A") (pintype "bidirectional"))
      (node (ref "MCP_010") (pin "26") (pinfunction "GPA5_26") (pintype "bidirectional"))
      (node (ref "RB29") (pin "1") (pinfunction "1_1") (pintype "passive"))
    )
    (net (code "69") (name "GPA5_5") (class "Default")
      (node (ref "ENC_86") (pin "B") (pinfunction "B_B") (pintype "bidirectional"))
      (node (ref "MCP_111") (pin "26") (pinfunction "GPA5_26") (pintype "bidirectional"))
      (node (ref "RB75") (pin "1") (pinfunction "1_1") (pintype "passive"))
    )
    (net (code "70") (name "GPA5_11") (class "Default")
      (node (ref "ENC_23") (pin "3") (pinfunction "SW_3") (pintype "passive"))
      (node (ref "MCP_000") (pin "26") (pinfunction "GPA5_26") (pintype "bidirectional"))
      (node (ref "R55") (pin "1") (pinfunction "1_1") (pintype "passive"))
      (node (ref "R58") (pin "1") (pinfunction "1_1") (pintype "passive"))
    )
    (net (code "71") (name "GPA5_12") (class "Default")
      (node (ref "MCP_001") (pin "26") (pinfunction "GPA5_26") (pintype "bidirectional"))
      (node (ref "R105") (pin "1") (pinfunction "1_1") (pintype "passive"))
      (node (ref "R108") (pin "1") (pinfunction "1_1") (pintype "passive"))
      (node (ref "S34") (pin "3") (pinfunction "SW_3") (pintype "passive"))
    )
    (net (code "72") (name "GPA5_31") (class "Default")
      (node (ref "ENC_53") (pin "A") (pinfunction "A_A") (pintype "bidirectional"))
      (node (ref "MCP_011") (pin "26") (pinfunction "GPA5_26") (pintype "bidirectional"))
      (node (ref "RB14") (pin "1") (pinfunction "1_1") (pintype "passive"))
    )
    (net (code "73") (name "GPA5_32") (class "Default")
      (node (ref "ENC_63") (pin "B") (pinfunction "B_B") (pintype "bidirectional"))
      (node (ref "MCP_100") (pin "26") (pinfunction "GPA5_26") (pintype "bidirectional"))
      (node (ref "RB66") (pin "1") (pinfunction "1_1") (pintype "passive"))
    )
    (net (code "74") (name "GPA5_41") (class "Default")
      (node (ref "MCP_101") (pin "26") (pinfunction "GPA5_26") (pintype "bidirectional"))
      (node (ref "TFT_EXT") (pin "5") (pinfunction "5_5") (pintype "passive"))
    )
    (net (code "75") (name "GPA5_42") (class "Default")
      (node (ref "ENC_85") (pin "A") (pinfunction "A_A") (pintype "bidirectional"))
      (node (ref "MCP_110") (pin "26") (pinfunction "GPA5_26") (pintype "bidirectional"))
      (node (ref "RB62") (pin "1") (pinfunction "1_1") (pintype "passive"))
    )
    (net (code "76") (name "GPA6_2") (class "Default")
      (node (ref "ENC_48") (pin "3") (pinfunction "SW_3") (pintype "passive"))
      (node (ref "MCP_010") (pin "27") (pinfunction "GPA6_27") (pintype "bidirectional"))
      (node (ref "RB31") (pin "1") (pinfunction "1_1") (pintype "passive"))
      (node (ref "RPD8") (pin "1") (pinfunction "1_1") (pintype "passive"))
    )
    (net (code "77") (name "GPA6_5") (class "Default")
      (node (ref "ENC_86") (pin "3") (pinfunction "SW_3") (pintype "passive"))
      (node (ref "MCP_111") (pin "27") (pinfunction "GPA6_27") (pintype "bidirectional"))
      (node (ref "RB76") (pin "1") (pinfunction "1_1") (pintype "passive"))
      (node (ref "RPD23") (pin "1") (pinfunction "1_1") (pintype "passive"))
    )
    (net (code "78") (name "GPA6_11") (class "Default")
      (node (ref "ENC_11") (pin "3") (pinfunction "SW_3") (pintype "passive"))
      (node (ref "MCP_000") (pin "27") (pinfunction "GPA6_27") (pintype "bidirectional"))
      (node (ref "R13") (pin "1") (pinfunction "1_1") (pintype "passive"))
      (node (ref "R16") (pin "1") (pinfunction "1_1") (pintype "passive"))
    )
    (net (code "79") (name "GPA6_12") (class "Default")
      (node (ref "MCP_001") (pin "27") (pinfunction "GPA6_27") (pintype "bidirectional"))
      (node (ref "RB6") (pin "1") (pinfunction "1_1") (pintype "passive"))
      (node (ref "S33") (pin "3") (pinfunction "3_3") (pintype "passive"))
      (node (ref "S33") (pin "4") (pinfunction "4_4") (pintype "passive"))
    )
    (net (code "80") (name "GPA6_31") (class "Default")
      (node (ref "ENC_53") (pin "B") (pinfunction "B_B") (pintype "bidirectional"))
      (node (ref "MCP_011") (pin "27") (pinfunction "GPA6_27") (pintype "bidirectional"))
      (node (ref "RB15") (pin "1") (pinfunction "1_1") (pintype "passive"))
    )
    (net (code "81") (name "GPA6_32") (class "Default")
      (node (ref "ENC_63") (pin "A") (pinfunction "A_A") (pintype "bidirectional"))
      (node (ref "MCP_100") (pin "27") (pinfunction "GPA6_27") (pintype "bidirectional"))
      (node (ref "RB65") (pin "1") (pinfunction "1_1") (pintype "passive"))
    )
    (net (code "82") (name "GPA6_41") (class "Default")
      (node (ref "MCP_101") (pin "27") (pinfunction "GPA6_27") (pintype "bidirectional"))
      (node (ref "TFT_EXT") (pin "3") (pinfunction "3_3") (pintype "passive"))
    )
    (net (code "83") (name "GPA6_42") (class "Default")
      (node (ref "ENC_85") (pin "B") (pinfunction "B_B") (pintype "bidirectional"))
      (node (ref "MCP_110") (pin "27") (pinfunction "GPA6_27") (pintype "bidirectional"))
      (node (ref "RB63") (pin "1") (pinfunction "1_1") (pintype "passive"))
    )
    (net (code "84") (name "GPA7_2") (class "Default")
      (node (ref "ENC_48") (pin "B") (pinfunction "B_B") (pintype "bidirectional"))
      (node (ref "MCP_010") (pin "28") (pinfunction "GPA7_28") (pintype "bidirectional"))
      (node (ref "RB30") (pin "1") (pinfunction "1_1") (pintype "passive"))
    )
    (net (code "85") (name "GPA7_5") (class "Default")
      (node (ref "ENC_87") (pin "3") (pinfunction "SW_3") (pintype "passive"))
      (node (ref "MCP_111") (pin "28") (pinfunction "GPA7_28") (pintype "bidirectional"))
      (node (ref "RB85") (pin "1") (pinfunction "1_1") (pintype "passive"))
      (node (ref "RPD26") (pin "1") (pinfunction "1_1") (pintype "passive"))
    )
    (net (code "86") (name "GPA7_11") (class "Default")
      (node (ref "MCP_000") (pin "28") (pinfunction "GPA7_28") (pintype "bidirectional"))
      (node (ref "RB2") (pin "1") (pinfunction "1_1") (pintype "passive"))
      (node (ref "S_12") (pin "3") (pinfunction "3_3") (pintype "passive"))
      (node (ref "S_12") (pin "4") (pinfunction "4_4") (pintype "passive"))
    )
    (net (code "87") (name "GPA7_12") (class "Default")
      (node (ref "MCP_001") (pin "28") (pinfunction "GPA7_28") (pintype "bidirectional"))
      (node (ref "RB1") (pin "1") (pinfunction "1_1") (pintype "passive"))
      (node (ref "S32") (pin "3") (pinfunction "3_3") (pintype "passive"))
      (node (ref "S32") (pin "4") (pinfunction "4_4") (pintype "passive"))
    )
    (net (code "88") (name "GPA7_31") (class "Default")
      (node (ref "ENC_57") (pin "3") (pinfunction "SW_3") (pintype "passive"))
      (node (ref "MCP_011") (pin "28") (pinfunction "GPA7_28") (pintype "bidirectional"))
      (node (ref "RB49") (pin "1") (pinfunction "1_1") (pintype "passive"))
      (node (ref "RPD14") (pin "1") (pinfunction "1_1") (pintype "passive"))
    )
    (net (code "89") (name "GPA7_32") (class "Default")
      (node (ref "ENC_62") (pin "3") (pinfunction "SW_3") (pintype "passive"))
      (node (ref "MCP_100") (pin "28") (pinfunction "GPA7_28") (pintype "bidirectional"))
      (node (ref "RB61") (pin "1") (pinfunction "1_1") (pintype "passive"))
      (node (ref "RPD18") (pin "1") (pinfunction "1_1") (pintype "passive"))
    )
    (net (code "90") (name "GPA7_41") (class "Default")
      (node (ref "MCP_101") (pin "28") (pinfunction "GPA7_28") (pintype "bidirectional"))
      (node (ref "TFT_EXT") (pin "2") (pinfunction "2_2") (pintype "passive"))
    )
    (net (code "91") (name "GPA7_42") (class "Default")
      (node (ref "ENC_85") (pin "3") (pinfunction "SW_3") (pintype "passive"))
      (node (ref "MCP_110") (pin "28") (pinfunction "GPA7_28") (pintype "bidirectional"))
      (node (ref "RB64") (pin "1") (pinfunction "1_1") (pintype "passive"))
      (node (ref "RPD19") (pin "1") (pinfunction "1_1") (pintype "passive"))
    )
    (net (code "92") (name "GPB0_2") (class "Default")
      (node (ref "MCP_010") (pin "1") (pinfunction "GPB0_1") (pintype "bidirectional"))
      (node (ref "RB3") (pin "1") (pinfunction "1_1") (pintype "passive"))
      (node (ref "SW_42") (pin "3") (pinfunction "3_3") (pintype "passive"))
      (node (ref "SW_42") (pin "4") (pinfunction "4_4") (pintype "passive"))
    )
    (net (code "93") (name "GPB0_5") (class "Default")
      (node (ref "ENC_87") (pin "B") (pinfunction "B_B") (pintype "bidirectional"))
      (node (ref "MCP_111") (pin "1") (pinfunction "GPB0_1") (pintype "bidirectional"))
      (node (ref "RB84") (pin "1") (pinfunction "1_1") (pintype "passive"))
    )
    (net (code "94") (name "GPB0_11") (class "Default")
      (node (ref "ENC_11") (pin "A") (pinfunction "A_A") (pintype "bidirectional"))
      (node (ref "MCP_000") (pin "1") (pinfunction "GPB0_1") (pintype "bidirectional"))
      (node (ref "R14") (pin "1") (pinfunction "1_1") (pintype "passive"))
    )
    (net (code "95") (name "GPB0_31") (class "Default")
      (node (ref "ENC_57") (pin "B") (pinfunction "B_B") (pintype "bidirectional"))
      (node (ref "MCP_011") (pin "1") (pinfunction "GPB0_1") (pintype "bidirectional"))
      (node (ref "RB48") (pin "1") (pinfunction "1_1") (pintype "passive"))
    )
    (net (code "96") (name "GPB0_32") (class "Default")
      (node (ref "ENC_62") (pin "B") (pinfunction "B_B") (pintype "bidirectional"))
      (node (ref "MCP_100") (pin "1") (pinfunction "GPB0_1") (pintype "bidirectional"))
      (node (ref "RB60") (pin "1") (pinfunction "1_1") (pintype "passive"))
    )
    (net (code "97") (name "GPB0_41") (class "Default")
      (node (ref "MCP_101") (pin "1") (pinfunction "GPB0_1") (pintype "bidirectional"))
      (node (ref "TFT_EXT") (pin "11") (pinfunction "11_11") (pintype "passive"))
    )
    (net (code "98") (name "GPB0_42") (class "Default")
      (node (ref "ENC_73") (pin "B") (pinfunction "B_B") (pintype "bidirectional"))
      (node (ref "MCP_110") (pin "1") (pinfunction "GPB0_1") (pintype "bidirectional"))
      (node (ref "RB81") (pin "1") (pinfunction "1_1") (pintype "passive"))
    )
    (net (code "99") (name "GPB1_2") (class "Default")
      (node (ref "ENC_44") (pin "A") (pinfunction "A_A") (pintype "bidirectional"))
      (node (ref "MCP_010") (pin "2") (pinfunction "GPB1_2") (pintype "bidirectional"))
      (node (ref "RB17") (pin "1") (pinfunction "1_1") (pintype "passive"))
    )
    (net (code "100") (name "GPB1_5") (class "Default")
      (node (ref "ENC_87") (pin "A") (pinfunction "A_A") (pintype "bidirectional"))
      (node (ref "MCP_111") (pin "2") (pinfunction "GPB1_2") (pintype "bidirectional"))
      (node (ref "RB83") (pin "1") (pinfunction "1_1") (pintype "passive"))
    )
    (net (code "101") (name "GPB1_11") (class "Default")
      (node (ref "ENC_11") (pin "B") (pinfunction "B_B") (pintype "bidirectional"))
      (node (ref "MCP_000") (pin "2") (pinfunction "GPB1_2") (pintype "bidirectional"))
      (node (ref "R15") (pin "1") (pinfunction "1_1") (pintype "passive"))
    )
    (net (code "102") (name "GPB1_12") (class "Default")
      (node (ref "MCP_001") (pin "2") (pinfunction "GPB1_2") (pintype "bidirectional"))
      (node (ref "R91") (pin "1") (pinfunction "1_1") (pintype "passive"))
      (node (ref "S31") (pin "B") (pinfunction "B_B") (pintype "bidirectional"))
    )
    (net (code "103") (name "GPB1_31") (class "Default")
      (node (ref "ENC_57") (pin "A") (pinfunction "A_A") (pintype "bidirectional"))
      (node (ref "MCP_011") (pin "2") (pinfunction "GPB1_2") (pintype "bidirectional"))
      (node (ref "RB47") (pin "1") (pinfunction "1_1") (pintype "passive"))
    )
    (net (code "104") (name "GPB1_32") (class "Default")
      (node (ref "ENC_62") (pin "A") (pinfunction "A_A") (pintype "bidirectional"))
      (node (ref "MCP_100") (pin "2") (pinfunction "GPB1_2") (pintype "bidirectional"))
      (node (ref "RB59") (pin "1") (pinfunction "1_1") (pintype "passive"))
    )
    (net (code "105") (name "GPB1_41") (class "Default")
      (node (ref "MCP_101") (pin "2") (pinfunction "GPB1_2") (pintype "bidirectional"))
      (node (ref "TFT_EXT") (pin "12") (pinfunction "12_12") (pintype "passive"))
    )
    (net (code "106") (name "GPB1_42") (class "Default")
      (node (ref "ENC_73") (pin "A") (pinfunction "A_A") (pintype "bidirectional"))
      (node (ref "MCP_110") (pin "2") (pinfunction "GPB1_2") (pintype "bidirectional"))
      (node (ref "RB80") (pin "1") (pinfunction "1_1") (pintype "passive"))
    )
    (net (code "107") (name "GPB2_2") (class "Default")
      (node (ref "ENC_44") (pin "B") (pinfunction "B_B") (pintype "bidirectional"))
      (node (ref "MCP_010") (pin "3") (pinfunction "GPB2_3") (pintype "bidirectional"))
      (node (ref "RB18") (pin "1") (pinfunction "1_1") (pintype "passive"))
    )
    (net (code "108") (name "GPB2_5") (class "Default")
      (node (ref "ENC_88") (pin "3") (pinfunction "SW_3") (pintype "passive"))
      (node (ref "MCP_111") (pin "3") (pinfunction "GPB2_3") (pintype "bidirectional"))
      (node (ref "RB91") (pin "1") (pinfunction "1_1") (pintype "passive"))
      (node (ref "RPD28") (pin "1") (pinfunction "1_1") (pintype "passive"))
    )
    (net (code "109") (name "GPB2_11") (class "Default")
      (node (ref "ENC_13") (pin "A") (pinfunction "A_A") (pintype "bidirectional"))
      (node (ref "MCP_000") (pin "3") (pinfunction "GPB2_3") (pintype "bidirectional"))
      (node (ref "R21") (pin "1") (pinfunction "1_1") (pintype "passive"))
    )
    (net (code "110") (name "GPB2_12") (class "Default")
      (node (ref "MCP_001") (pin "3") (pinfunction "GPB2_3") (pintype "bidirectional"))
      (node (ref "R88") (pin "1") (pinfunction "1_1") (pintype "passive"))
      (node (ref "R93") (pin "1") (pinfunction "1_1") (pintype "passive"))
      (node (ref "S31") (pin "3") (pinfunction "SW_3") (pintype "passive"))
    )
    (net (code "111") (name "GPB2_31") (class "Default")
      (node (ref "ENC_56") (pin "3") (pinfunction "SW_3") (pintype "passive"))
      (node (ref "MCP_011") (pin "3") (pinfunction "GPB2_3") (pintype "bidirectional"))
      (node (ref "RB43") (pin "1") (pinfunction "1_1") (pintype "passive"))
      (node (ref "RPD12") (pin "1") (pinfunction "1_1") (pintype "passive"))
    )
    (net (code "112") (name "GPB2_32") (class "Default")
      (node (ref "ENC_61") (pin "B") (pinfunction "B_B") (pintype "bidirectional"))
      (node (ref "MCP_100") (pin "3") (pinfunction "GPB2_3") (pintype "bidirectional"))
      (node (ref "RB54") (pin "1") (pinfunction "1_1") (pintype "passive"))
    )
    (net (code "113") (name "GPB2_41") (class "Default")
      (node (ref "MCP_101") (pin "3") (pinfunction "GPB2_3") (pintype "bidirectional"))
      (node (ref "TFT_EXT") (pin "10") (pinfunction "10_10") (pintype "passive"))
    )
    (net (code "114") (name "GPB2_42") (class "Default")
      (node (ref "ENC_72") (pin "B") (pinfunction "B_B") (pintype "bidirectional"))
      (node (ref "MCP_110") (pin "3") (pinfunction "GPB2_3") (pintype "bidirectional"))
      (node (ref "RB57") (pin "1") (pinfunction "1_1") (pintype "passive"))
    )
    (net (code "115") (name "GPB3_2") (class "Default")
      (node (ref "ENC_44") (pin "3") (pinfunction "SW_3") (pintype "passive"))
      (node (ref "MCP_010") (pin "4") (pinfunction "GPB3_4") (pintype "bidirectional"))
      (node (ref "RB19") (pin "1") (pinfunction "1_1") (pintype "passive"))
      (node (ref "RPD4") (pin "1") (pinfunction "1_1") (pintype "passive"))
    )
    (net (code "116") (name "GPB3_5") (class "Default")
      (node (ref "ENC_88") (pin "A") (pinfunction "A_A") (pintype "bidirectional"))
      (node (ref "MCP_111") (pin "4") (pinfunction "GPB3_4") (pintype "bidirectional"))
      (node (ref "RB89") (pin "1") (pinfunction "1_1") (pintype "passive"))
    )
    (net (code "117") (name "GPB3_11") (class "Default")
      (node (ref "ENC_13") (pin "B") (pinfunction "B_B") (pintype "bidirectional"))
      (node (ref "MCP_000") (pin "4") (pinfunction "GPB3_4") (pintype "bidirectional"))
      (node (ref "R22") (pin "1") (pinfunction "1_1") (pintype "passive"))
    )
    (net (code "118") (name "GPB3_12") (class "Default")
      (node (ref "MCP_001") (pin "4") (pinfunction "GPB3_4") (pintype "bidirectional"))
      (node (ref "R89") (pin "1") (pinfunction "1_1") (pintype "passive"))
      (node (ref "S31") (pin "A") (pinfunction "A_A") (pintype "bidirectional"))
    )
    (net (code "119") (name "GPB3_31") (class "Default")
      (node (ref "ENC_56") (pin "B") (pinfunction "B_B") (pintype "bidirectional"))
      (node (ref "MCP_011") (pin "4") (pinfunction "GPB3_4") (pintype "bidirectional"))
      (node (ref "RB42") (pin "1") (pinfunction "1_1") (pintype "passive"))
    )
    (net (code "120") (name "GPB3_32") (class "Default")
      (node (ref "ENC_61") (pin "A") (pinfunction "A_A") (pintype "bidirectional"))
      (node (ref "MCP_100") (pin "4") (pinfunction "GPB3_4") (pintype "bidirectional"))
      (node (ref "RB53") (pin "1") (pinfunction "1_1") (pintype "passive"))
    )
    (net (code "121") (name "GPB3_41") (class "Default")
      (node (ref "MCP_101") (pin "4") (pinfunction "GPB3_4") (pintype "bidirectional"))
      (node (ref "TFT_EXT") (pin "8") (pinfunction "8_8") (pintype "passive"))
    )
    (net (code "122") (name "GPB3_42") (class "Default")
      (node (ref "ENC_72") (pin "A") (pinfunction "A_A") (pintype "bidirectional"))
      (node (ref "MCP_110") (pin "4") (pinfunction "GPB3_4") (pintype "bidirectional"))
      (node (ref "RB56") (pin "1") (pinfunction "1_1") (pintype "passive"))
    )
    (net (code "123") (name "GPB4_2") (class "Default")
      (node (ref "ENC_41") (pin "A") (pinfunction "A_A") (pintype "bidirectional"))
      (node (ref "MCP_010") (pin "5") (pinfunction "GPB4_5") (pintype "bidirectional"))
      (node (ref "RB11") (pin "1") (pinfunction "1_1") (pintype "passive"))
    )
    (net (code "124") (name "GPB4_5") (class "Default")
      (node (ref "ENC_88") (pin "B") (pinfunction "B_B") (pintype "bidirectional"))
      (node (ref "MCP_111") (pin "5") (pinfunction "GPB4_5") (pintype "bidirectional"))
      (node (ref "RB90") (pin "1") (pinfunction "1_1") (pintype "passive"))
    )
    (net (code "125") (name "GPB4_11") (class "Default")
      (node (ref "ENC_13") (pin "3") (pinfunction "SW_3") (pintype "passive"))
      (node (ref "MCP_000") (pin "5") (pinfunction "GPB4_5") (pintype "bidirectional"))
      (node (ref "R20") (pin "1") (pinfunction "1_1") (pintype "passive"))
      (node (ref "R23") (pin "1") (pinfunction "1_1") (pintype "passive"))
    )
    (net (code "126") (name "GPB4_12") (class "Default")
      (node (ref "ENC_21") (pin "3") (pinfunction "SW_3") (pintype "passive"))
      (node (ref "MCP_001") (pin "5") (pinfunction "GPB4_5") (pintype "bidirectional"))
      (node (ref "R41") (pin "1") (pinfunction "1_1") (pintype "passive"))
      (node (ref "R44") (pin "1") (pinfunction "1_1") (pintype "passive"))
    )
    (net (code "127") (name "GPB4_31") (class "Default")
      (node (ref "ENC_56") (pin "A") (pinfunction "A_A") (pintype "bidirectional"))
      (node (ref "MCP_011") (pin "5") (pinfunction "GPB4_5") (pintype "bidirectional"))
      (node (ref "RB41") (pin "1") (pinfunction "1_1") (pintype "passive"))
    )
    (net (code "128") (name "GPB4_32") (class "Default")
      (node (ref "ENC_61") (pin "3") (pinfunction "SW_3") (pintype "passive"))
      (node (ref "MCP_100") (pin "5") (pinfunction "GPB4_5") (pintype "bidirectional"))
      (node (ref "RB55") (pin "1") (pinfunction "1_1") (pintype "passive"))
      (node (ref "RPD16") (pin "1") (pinfunction "1_1") (pintype "passive"))
    )
    (net (code "129") (name "GPB4_41") (class "Default")
      (node (ref "MCP_101") (pin "5") (pinfunction "GPB4_5") (pintype "bidirectional"))
      (node (ref "TFT_EXT") (pin "6") (pinfunction "6_6") (pintype "passive"))
    )
    (net (code "130") (name "GPB4_42") (class "Default")
      (node (ref "ENC_72") (pin "3") (pinfunction "SW_3") (pintype "passive"))
      (node (ref "MCP_110") (pin "5") (pinfunction "GPB4_5") (pintype "bidirectional"))
      (node (ref "RB58") (pin "1") (pinfunction "1_1") (pintype "passive"))
      (node (ref "RPD17") (pin "1") (pinfunction "1_1") (pintype "passive"))
    )
    (net (code "131") (name "GPB5_2") (class "Default")
      (node (ref "ENC_41") (pin "B") (pinfunction "B_B") (pintype "bidirectional"))
      (node (ref "MCP_010") (pin "6") (pinfunction "GPB5_6") (pintype "bidirectional"))
      (node (ref "RB12") (pin "1") (pinfunction "1_1") (pintype "passive"))
    )
    (net (code "132") (name "GPB5_5") (class "Default")
      (node (ref "ENC_75") (pin "3") (pinfunction "SW_3") (pintype "passive"))
      (node (ref "MCP_111") (pin "6") (pinfunction "GPB5_6") (pintype "bidirectional"))
      (node (ref "RB100") (pin "1") (pinfunction "1_1") (pintype "passive"))
      (node (ref "RPD31") (pin "1") (pinfunction "1_1") (pintype "passive"))
    )
    (net (code "133") (name "GPB5_11") (class "Default")
      (node (ref "ENC_14") (pin "3") (pinfunction "SW_3") (pintype "passive"))
      (node (ref "MCP_000") (pin "6") (pinfunction "GPB5_6") (pintype "bidirectional"))
      (node (ref "R27") (pin "1") (pinfunction "1_1") (pintype "passive"))
      (node (ref "R30") (pin "1") (pinfunction "1_1") (pintype "passive"))
    )
    (net (code "134") (name "GPB5_12") (class "Default")
      (node (ref "ENC_21") (pin "A") (pinfunction "A_A") (pintype "bidirectional"))
      (node (ref "MCP_001") (pin "6") (pinfunction "GPB5_6") (pintype "bidirectional"))
      (node (ref "R42") (pin "1") (pinfunction "1_1") (pintype "passive"))
    )
    (net (code "135") (name "GPB5_31") (class "Default")
      (node (ref "ENC_55") (pin "A") (pinfunction "A_A") (pintype "bidirectional"))
      (node (ref "MCP_011") (pin "6") (pinfunction "GPB5_6") (pintype "bidirectional"))
      (node (ref "RB35") (pin "1") (pinfunction "1_1") (pintype "passive"))
    )
    (net (code "136") (name "GPB5_32") (class "Default")
      (node (ref "ENC_54") (pin "A") (pinfunction "A_A") (pintype "bidirectional"))
      (node (ref "MCP_100") (pin "6") (pinfunction "GPB5_6") (pintype "bidirectional"))
      (node (ref "RB26") (pin "1") (pinfunction "1_1") (pintype "passive"))
    )
    (net (code "137") (name "GPB5_41") (class "Default")
      (node (ref "MCP_101") (pin "6") (pinfunction "GPB5_6") (pintype "bidirectional"))
      (node (ref "TFT_EXT") (pin "4") (pinfunction "4_4") (pintype "passive"))
    )
    (net (code "138") (name "GPB5_42") (class "Default")
      (node (ref "ENC_71") (pin "B") (pinfunction "B_B") (pintype "bidirectional"))
      (node (ref "MCP_110") (pin "6") (pinfunction "GPB5_6") (pintype "bidirectional"))
      (node (ref "RB33") (pin "1") (pinfunction "1_1") (pintype "passive"))
    )
    (net (code "139") (name "GPB6_2") (class "Default")
      (node (ref "ENC_41") (pin "3") (pinfunction "SW_3") (pintype "passive"))
      (node (ref "MCP_010") (pin "7") (pinfunction "GPB6_7") (pintype "bidirectional"))
      (node (ref "RB13") (pin "1") (pinfunction "1_1") (pintype "passive"))
      (node (ref "RPD2") (pin "1") (pinfunction "1_1") (pintype "passive"))
    )
    (net (code "140") (name "GPB6_5") (class "Default")
      (node (ref "ENC_75") (pin "A") (pinfunction "A_A") (pintype "bidirectional"))
      (node (ref "MCP_111") (pin "7") (pinfunction "GPB6_7") (pintype "bidirectional"))
      (node (ref "RB98") (pin "1") (pinfunction "1_1") (pintype "passive"))
    )
    (net (code "141") (name "GPB6_11") (class "Default")
      (node (ref "ENC_14") (pin "A") (pinfunction "A_A") (pintype "bidirectional"))
      (node (ref "MCP_000") (pin "7") (pinfunction "GPB6_7") (pintype "bidirectional"))
      (node (ref "R28") (pin "1") (pinfunction "1_1") (pintype "passive"))
    )
    (net (code "142") (name "GPB6_12") (class "Default")
      (node (ref "ENC_21") (pin "B") (pinfunction "B_B") (pintype "bidirectional"))
      (node (ref "MCP_001") (pin "7") (pinfunction "GPB6_7") (pintype "bidirectional"))
      (node (ref "R43") (pin "1") (pinfunction "1_1") (pintype "passive"))
    )
    (net (code "143") (name "GPB6_31") (class "Default")
      (node (ref "ENC_55") (pin "B") (pinfunction "B_B") (pintype "bidirectional"))
      (node (ref "MCP_011") (pin "7") (pinfunction "GPB6_7") (pintype "bidirectional"))
      (node (ref "RB36") (pin "1") (pinfunction "1_1") (pintype "passive"))
    )
    (net (code "144") (name "GPB6_32") (class "Default")
      (node (ref "ENC_54") (pin "B") (pinfunction "B_B") (pintype "bidirectional"))
      (node (ref "MCP_100") (pin "7") (pinfunction "GPB6_7") (pintype "bidirectional"))
      (node (ref "RB27") (pin "1") (pinfunction "1_1") (pintype "passive"))
    )
    (net (code "145") (name "GPB6_41") (class "Default")
      (node (ref "ENC_81") (pin "A") (pinfunction "A_A") (pintype "bidirectional"))
      (node (ref "MCP_101") (pin "7") (pinfunction "GPB6_7") (pintype "bidirectional"))
      (node (ref "RB77") (pin "1") (pinfunction "1_1") (pintype "passive"))
    )
    (net (code "146") (name "GPB6_42") (class "Default")
      (node (ref "ENC_71") (pin "A") (pinfunction "A_A") (pintype "bidirectional"))
      (node (ref "MCP_110") (pin "7") (pinfunction "GPB6_7") (pintype "bidirectional"))
      (node (ref "RB32") (pin "1") (pinfunction "1_1") (pintype "passive"))
    )
    (net (code "147") (name "GPB7_2") (class "Default")
      (node (ref "MCP_010") (pin "8") (pinfunction "GPB7_8") (pintype "bidirectional"))
      (node (ref "RB45") (pin "1") (pinfunction "1_1") (pintype "passive"))
      (node (ref "SW_43") (pin "3") (pinfunction "3_3") (pintype "passive"))
      (node (ref "SW_43") (pin "4") (pinfunction "4_4") (pintype "passive"))
    )
    (net (code "148") (name "GPB7_5") (class "Default")
      (node (ref "ENC_75") (pin "B") (pinfunction "B_B") (pintype "bidirectional"))
      (node (ref "MCP_111") (pin "8") (pinfunction "GPB7_8") (pintype "bidirectional"))
      (node (ref "RB99") (pin "1") (pinfunction "1_1") (pintype "passive"))
    )
    (net (code "149") (name "GPB7_11") (class "Default")
      (node (ref "ENC_14") (pin "B") (pinfunction "B_B") (pintype "bidirectional"))
      (node (ref "MCP_000") (pin "8") (pinfunction "GPB7_8") (pintype "bidirectional"))
      (node (ref "R29") (pin "1") (pinfunction "1_1") (pintype "passive"))
    )
    (net (code "150") (name "GPB7_12") (class "Default")
      (node (ref "MCP_001") (pin "8") (pinfunction "GPB7_8") (pintype "bidirectional"))
      (node (ref "RB4") (pin "1") (pinfunction "1_1") (pintype "passive"))
      (node (ref "S_22") (pin "3") (pinfunction "3_3") (pintype "passive"))
      (node (ref "S_22") (pin "4") (pinfunction "4_4") (pintype "passive"))
    )
    (net (code "151") (name "GPB7_31") (class "Default")
      (node (ref "ENC_55") (pin "3") (pinfunction "SW_3") (pintype "passive"))
      (node (ref "MCP_011") (pin "8") (pinfunction "GPB7_8") (pintype "bidirectional"))
      (node (ref "RB37") (pin "1") (pinfunction "1_1") (pintype "passive"))
      (node (ref "RPD10") (pin "1") (pinfunction "1_1") (pintype "passive"))
    )
    (net (code "152") (name "GPB7_32") (class "Default")
      (node (ref "ENC_54") (pin "3") (pinfunction "SW_3") (pintype "passive"))
      (node (ref "MCP_100") (pin "8") (pinfunction "GPB7_8") (pintype "bidirectional"))
      (node (ref "RB28") (pin "1") (pinfunction "1_1") (pintype "passive"))
      (node (ref "RPD7") (pin "1") (pinfunction "1_1") (pintype "passive"))
    )
    (net (code "153") (name "GPB7_41") (class "Default")
      (node (ref "ENC_81") (pin "B") (pinfunction "B_B") (pintype "bidirectional"))
      (node (ref "MCP_101") (pin "8") (pinfunction "GPB7_8") (pintype "bidirectional"))
      (node (ref "RB78") (pin "1") (pinfunction "1_1") (pintype "passive"))
    )
    (net (code "154") (name "GPB7_42") (class "Default")
      (node (ref "ENC_71") (pin "3") (pinfunction "SW_3") (pintype "passive"))
      (node (ref "MCP_110") (pin "8") (pinfunction "GPB7_8") (pintype "bidirectional"))
      (node (ref "RB34") (pin "1") (pinfunction "1_1") (pintype "passive"))
      (node (ref "RPD9") (pin "1") (pinfunction "1_1") (pintype "passive"))
    )
    (net (code "155") (name "GPIO_EXTI0") (class "Default")
      (node (ref "F446") (pin "5") (pinfunction "PH0-OSC_IN_5") (pintype "bidirectional"))
      (node (ref "MCP_101") (pin "19") (pinfunction "INTB_19") (pintype "bidirectional"))
    )
    (net (code "156") (name "GPIO_EXTI1") (class "Default")
      (node (ref "CONN_STH_BRD_1") (pin "17") (pinfunction "17_17") (pintype "passive"))
      (node (ref "F446") (pin "27") (pinfunction "PB1_27") (pintype "bidirectional"))
    )
    (net (code "157") (name "GPIO_EXTI2") (class "Default")
      (node (ref "F446") (pin "10") (pinfunction "PC2_10") (pintype "bidirectional"))
      (node (ref "MCP_110") (pin "19") (pinfunction "INTB_19") (pintype "bidirectional"))
    )
    (net (code "158") (name "GPIO_EXTI3") (class "Default")
      (node (ref "F446") (pin "11") (pinfunction "PC3_11") (pintype "bidirectional"))
      (node (ref "MCP_110") (pin "20") (pinfunction "INTA_20") (pintype "bidirectional"))
    )
    (net (code "159") (name "GPIO_EXTI4") (class "Default")
      (node (ref "F446") (pin "24") (pinfunction "PC4_24") (pintype "bidirectional"))
      (node (ref "MCP_111") (pin "20") (pinfunction "INTA_20") (pintype "bidirectional"))
    )
    (net (code "160") (name "GPIO_EXTI5") (class "Default")
      (node (ref "F446") (pin "25") (pinfunction "PC5_25") (pintype "bidirectional"))
      (node (ref "MCP_111") (pin "19") (pinfunction "INTB_19") (pintype "bidirectional"))
    )
    (net (code "161") (name "GPIO_EXTI6") (class "Default")
      (node (ref "CONN_STH_BRD_1") (pin "16") (pinfunction "16_16") (pintype "passive"))
      (node (ref "F446") (pin "37") (pinfunction "PC6_37") (pintype "bidirectional"))
    )
    (net (code "162") (name "GPIO_EXTI7") (class "Default")
      (node (ref "CONN_STH_BRD_1") (pin "13") (pinfunction "13_13") (pintype "passive"))
      (node (ref "F446") (pin "38") (pinfunction "PC7_38") (pintype "bidirectional"))
    )
    (net (code "163") (name "GPIO_EXTI8") (class "Default")
      (node (ref "CONN_STH_BRD_1") (pin "14") (pinfunction "14_14") (pintype "passive"))
      (node (ref "F446") (pin "39") (pinfunction "PC8_39") (pintype "bidirectional"))
    )
    (net (code "164") (name "GPIO_EXTI9") (class "Default")
      (node (ref "CONN_STH_BRD_1") (pin "9") (pinfunction "9_9") (pintype "passive"))
      (node (ref "F446") (pin "42") (pinfunction "PA9_42") (pintype "bidirectional"))
    )
    (net (code "165") (name "GPIO_EXTI10") (class "Default")
      (node (ref "CONN_STH_BRD_1") (pin "10") (pinfunction "10_10") (pintype "passive"))
      (node (ref "F446") (pin "43") (pinfunction "PA10_43") (pintype "bidirectional"))
    )
    (net (code "166") (name "GPIO_EXTI11") (class "Default")
      (node (ref "CONN_STH_BRD_1") (pin "7") (pinfunction "7_7") (pintype "passive"))
      (node (ref "F446") (pin "44") (pinfunction "PA11_44") (pintype "bidirectional"))
    )
    (net (code "167") (name "GPIO_EXTI12") (class "Default")
      (node (ref "CONN_STH_BRD_1") (pin "8") (pinfunction "8_8") (pintype "passive"))
      (node (ref "F446") (pin "45") (pinfunction "PA12_45") (pintype "bidirectional"))
    )
    (net (code "168") (name "GPIO_EXTI13") (class "Default")
      (node (ref "F446") (pin "2") (pinfunction "PC13_2") (pintype "bidirectional"))
      (node (ref "MCP_101") (pin "20") (pinfunction "INTA_20") (pintype "bidirectional"))
    )
    (net (code "169") (name "GPIO_EXTI14") (class "Default")
      (node (ref "CONN_STH_BRD_1") (pin "18") (pinfunction "18_18") (pintype "passive"))
      (node (ref "F446") (pin "35") (pinfunction "PB14_35") (pintype "bidirectional"))
    )
    (net (code "170") (name "GPIO_EXTI15") (class "Default")
      (node (ref "CONN_STH_BRD_1") (pin "15") (pinfunction "15_15") (pintype "passive"))
      (node (ref "F446") (pin "36") (pinfunction "PB15_36") (pintype "bidirectional"))
    )
    (net (code "171") (name "I2C1_SCL") (class "Default")
      (node (ref "F446") (pin "61") (pinfunction "PB8_61") (pintype "bidirectional"))
      (node (ref "MCP_101") (pin "12") (pinfunction "SCL_12") (pintype "bidirectional"))
      (node (ref "MCP_110") (pin "12") (pinfunction "SCL_12") (pintype "bidirectional"))
      (node (ref "MCP_111") (pin "12") (pinfunction "SCL_12") (pintype "bidirectional"))
      (node (ref "R194") (pin "1") (pinfunction "1_1") (pintype "passive"))
      (node (ref "R199") (pin "1") (pinfunction "1_1") (pintype "passive"))
      (node (ref "R204") (pin "1") (pinfunction "1_1") (pintype "passive"))
    )
    (net (code "172") (name "I2C1_SDA") (class "Default")
      (node (ref "F446") (pin "62") (pinfunction "PB9_62") (pintype "bidirectional"))
      (node (ref "MCP_101") (pin "13") (pinfunction "SDA_13") (pintype "bidirectional"))
      (node (ref "MCP_110") (pin "13") (pinfunction "SDA_13") (pintype "bidirectional"))
      (node (ref "MCP_111") (pin "13") (pinfunction "SDA_13") (pintype "bidirectional"))
      (node (ref "R198") (pin "1") (pinfunction "1_1") (pintype "passive"))
      (node (ref "R203") (pin "1") (pinfunction "1_1") (pintype "passive"))
      (node (ref "R205") (pin "1") (pinfunction "1_1") (pintype "passive"))
    )
    (net (code "173") (name "I2C2_SCL") (class "Default")
      (node (ref "CONN_STH_BRD_1") (pin "20") (pinfunction "20_20") (pintype "passive"))
      (node (ref "CONN_STH_BRD_2") (pin "20") (pinfunction "20_20") (pintype "passive"))
      (node (ref "F446") (pin "29") (pinfunction "PB10_29") (pintype "bidirectional"))
      (node (ref "MCP_010") (pin "12") (pinfunction "SCL_12") (pintype "bidirectional"))
      (node (ref "MCP_011") (pin "12") (pinfunction "SCL_12") (pintype "bidirectional"))
      (node (ref "MCP_100") (pin "12") (pinfunction "SCL_12") (pintype "bidirectional"))
      (node (ref "R1") (pin "1") (pinfunction "1_1") (pintype "passive"))
      (node (ref "R149") (pin "1") (pinfunction "1_1") (pintype "passive"))
      (node (ref "R166") (pin "1") (pinfunction "1_1") (pintype "passive"))
    )
    (net (code "174") (name "I2C2_SDA") (class "Default")
      (node (ref "CONN_STH_BRD_1") (pin "5") (pinfunction "5_5") (pintype "passive"))
      (node (ref "CONN_STH_BRD_2") (pin "5") (pinfunction "5_5") (pintype "passive"))
      (node (ref "F446") (pin "53") (pinfunction "PC12_53") (pintype "bidirectional"))
      (node (ref "MCP_010") (pin "13") (pinfunction "SDA_13") (pintype "bidirectional"))
      (node (ref "MCP_011") (pin "13") (pinfunction "SDA_13") (pintype "bidirectional"))
      (node (ref "MCP_100") (pin "13") (pinfunction "SDA_13") (pintype "bidirectional"))
      (node (ref "R165") (pin "1") (pinfunction "1_1") (pintype "passive"))
      (node (ref "R182") (pin "1") (pinfunction "1_1") (pintype "passive"))
      (node (ref "R2") (pin "1") (pinfunction "1_1") (pintype "passive"))
    )
    (net (code "175") (name "I2C3_SCL") (class "Default")
      (node (ref "CONN_STH_BRD_1") (pin "12") (pinfunction "12_12") (pintype "passive"))
      (node (ref "CONN_STH_BRD_2") (pin "12") (pinfunction "12_12") (pintype "passive"))
      (node (ref "F446") (pin "41") (pinfunction "PA8_41") (pintype "bidirectional"))
      (node (ref "MCP_000") (pin "12") (pinfunction "SCL_12") (pintype "bidirectional"))
      (node (ref "MCP_001") (pin "12") (pinfunction "SCL_12") (pintype "bidirectional"))
      (node (ref "R186") (pin "1") (pinfunction "1_1") (pintype "passive"))
      (node (ref "R4") (pin "1") (pinfunction "1_1") (pintype "passive"))
    )
    (net (code "176") (name "I2C3_SDA") (class "Default")
      (node (ref "CONN_STH_BRD_1") (pin "11") (pinfunction "11_11") (pintype "passive"))
      (node (ref "CONN_STH_BRD_2") (pin "11") (pinfunction "11_11") (pintype "passive"))
      (node (ref "F446") (pin "40") (pinfunction "PC9_40") (pintype "bidirectional"))
      (node (ref "MCP_000") (pin "13") (pinfunction "SDA_13") (pintype "bidirectional"))
      (node (ref "MCP_001") (pin "13") (pinfunction "SDA_13") (pintype "bidirectional"))
      (node (ref "R187") (pin "1") (pinfunction "1_1") (pintype "passive"))
      (node (ref "R5") (pin "1") (pinfunction "1_1") (pintype "passive"))
    )
    (net (code "177") (name "INTA_2") (class "Default")
      (node (ref "CONN_STH_BRD_2") (pin "13") (pinfunction "13_13") (pintype "passive"))
      (node (ref "MCP_010") (pin "20") (pinfunction "INTA_20") (pintype "bidirectional"))
    )
    (net (code "178") (name "INTA_11") (class "Default")
      (node (ref "CONN_STH_BRD_2") (pin "8") (pinfunction "8_8") (pintype "passive"))
      (node (ref "MCP_000") (pin "20") (pinfunction "INTA_20") (pintype "bidirectional"))
    )
    (net (code "179") (name "INTA_12") (class "Default")
      (node (ref "CONN_STH_BRD_2") (pin "9") (pinfunction "9_9") (pintype "passive"))
      (node (ref "MCP_001") (pin "20") (pinfunction "INTA_20") (pintype "bidirectional"))
    )
    (net (code "180") (name "INTA_31") (class "Default")
      (node (ref "CONN_STH_BRD_2") (pin "18") (pinfunction "18_18") (pintype "passive"))
      (node (ref "MCP_011") (pin "20") (pinfunction "INTA_20") (pintype "bidirectional"))
    )
    (net (code "181") (name "INTA_32") (class "Default")
      (node (ref "CONN_STH_BRD_2") (pin "15") (pinfunction "15_15") (pintype "passive"))
      (node (ref "MCP_100") (pin "20") (pinfunction "INTA_20") (pintype "bidirectional"))
    )
    (net (code "182") (name "INTB_2") (class "Default")
      (node (ref "CONN_STH_BRD_2") (pin "14") (pinfunction "14_14") (pintype "passive"))
      (node (ref "MCP_010") (pin "19") (pinfunction "INTB_19") (pintype "bidirectional"))
    )
    (net (code "183") (name "INTB_11") (class "Default")
      (node (ref "CONN_STH_BRD_2") (pin "7") (pinfunction "7_7") (pintype "passive"))
      (node (ref "MCP_000") (pin "19") (pinfunction "INTB_19") (pintype "bidirectional"))
    )
    (net (code "184") (name "INTB_12") (class "Default")
      (node (ref "CONN_STH_BRD_2") (pin "10") (pinfunction "10_10") (pintype "passive"))
      (node (ref "MCP_001") (pin "19") (pinfunction "INTB_19") (pintype "bidirectional"))
    )
    (net (code "185") (name "INTB_31") (class "Default")
      (node (ref "CONN_STH_BRD_2") (pin "17") (pinfunction "17_17") (pintype "passive"))
      (node (ref "MCP_011") (pin "19") (pinfunction "INTB_19") (pintype "bidirectional"))
    )
    (net (code "186") (name "INTB_32") (class "Default")
      (node (ref "CONN_STH_BRD_2") (pin "16") (pinfunction "16_16") (pintype "passive"))
      (node (ref "MCP_100") (pin "19") (pinfunction "INTB_19") (pintype "bidirectional"))
    )
    (net (code "187") (name "NRST") (class "Default")
      (node (ref "C55") (pin "2") (pinfunction "2_2") (pintype "passive"))
      (node (ref "F446") (pin "7") (pinfunction "NRST_7") (pintype "bidirectional"))
      (node (ref "R79") (pin "2") (pinfunction "2_2") (pintype "passive"))
      (node (ref "S2") (pin "2") (pinfunction "2_2") (pintype "bidirectional"))
      (node (ref "STLINK") (pin "3") (pinfunction "3_3") (pintype "passive"))
    )
    (net (code "188") (name "Net-(C4-Pad2)") (class "Default")
      (node (ref "C4") (pin "2") (pinfunction "2_2") (pintype "passive"))
      (node (ref "R14") (pin "2") (pinfunction "2_2") (pintype "passive"))
    )
    (net (code "189") (name "Net-(C5-Pad2)") (class "Default")
      (node (ref "C5") (pin "2") (pinfunction "2_2") (pintype "passive"))
      (node (ref "R15") (pin "2") (pinfunction "2_2") (pintype "passive"))
    )
    (net (code "190") (name "Net-(C6-Pad1)") (class "Default")
      (node (ref "C6") (pin "1") (pinfunction "1_1") (pintype "passive"))
      (node (ref "R16") (pin "2") (pinfunction "2_2") (pintype "passive"))
    )
    (net (code "191") (name "Net-(C7-Pad2)") (class "Default")
      (node (ref "C7") (pin "2") (pinfunction "2_2") (pintype "passive"))
      (node (ref "R21") (pin "2") (pinfunction "2_2") (pintype "passive"))
    )
    (net (code "192") (name "Net-(C8-Pad2)") (class "Default")
      (node (ref "C8") (pin "2") (pinfunction "2_2") (pintype "passive"))
      (node (ref "R22") (pin "2") (pinfunction "2_2") (pintype "passive"))
    )
    (net (code "193") (name "Net-(C9-Pad1)") (class "Default")
      (node (ref "C9") (pin "1") (pinfunction "1_1") (pintype "passive"))
      (node (ref "R23") (pin "2") (pinfunction "2_2") (pintype "passive"))
    )
    (net (code "194") (name "Net-(C10-Pad2)") (class "Default")
      (node (ref "C10") (pin "2") (pinfunction "2_2") (pintype "passive"))
      (node (ref "R28") (pin "2") (pinfunction "2_2") (pintype "passive"))
    )
    (net (code "195") (name "Net-(C11-Pad2)") (class "Default")
      (node (ref "C11") (pin "2") (pinfunction "2_2") (pintype "passive"))
      (node (ref "R29") (pin "2") (pinfunction "2_2") (pintype "passive"))
    )
    (net (code "196") (name "Net-(C12-Pad1)") (class "Default")
      (node (ref "C12") (pin "1") (pinfunction "1_1") (pintype "passive"))
      (node (ref "R30") (pin "2") (pinfunction "2_2") (pintype "passive"))
    )
    (net (code "197") (name "Net-(C16-Pad2)") (class "Default")
      (node (ref "C16") (pin "2") (pinfunction "2_2") (pintype "passive"))
      (node (ref "R42") (pin "2") (pinfunction "2_2") (pintype "passive"))
    )
    (net (code "198") (name "Net-(C17-Pad2)") (class "Default")
      (node (ref "C17") (pin "2") (pinfunction "2_2") (pintype "passive"))
      (node (ref "R43") (pin "2") (pinfunction "2_2") (pintype "passive"))
    )
    (net (code "199") (name "Net-(C18-Pad1)") (class "Default")
      (node (ref "C18") (pin "1") (pinfunction "1_1") (pintype "passive"))
      (node (ref "R44") (pin "2") (pinfunction "2_2") (pintype "passive"))
    )
    (net (code "200") (name "Net-(C22-Pad2)") (class "Default")
      (node (ref "C22") (pin "2") (pinfunction "2_2") (pintype "passive"))
      (node (ref "R56") (pin "2") (pinfunction "2_2") (pintype "passive"))
    )
    (net (code "201") (name "Net-(C23-Pad2)") (class "Default")
      (node (ref "C23") (pin "2") (pinfunction "2_2") (pintype "passive"))
      (node (ref "R57") (pin "2") (pinfunction "2_2") (pintype "passive"))
    )
    (net (code "202") (name "Net-(C24-Pad1)") (class "Default")
      (node (ref "C24") (pin "1") (pinfunction "1_1") (pintype "passive"))
      (node (ref "R58") (pin "2") (pinfunction "2_2") (pintype "passive"))
    )
    (net (code "203") (name "Net-(C28-Pad2)") (class "Default")
      (node (ref "C28") (pin "2") (pinfunction "2_2") (pintype "passive"))
      (node (ref "R70") (pin "2") (pinfunction "2_2") (pintype "passive"))
    )
    (net (code "204") (name "Net-(C29-Pad2)") (class "Default")
      (node (ref "C29") (pin "2") (pinfunction "2_2") (pintype "passive"))
      (node (ref "R71") (pin "2") (pinfunction "2_2") (pintype "passive"))
    )
    (net (code "205") (name "Net-(C30-Pad1)") (class "Default")
      (node (ref "C30") (pin "1") (pinfunction "1_1") (pintype "passive"))
      (node (ref "R72") (pin "2") (pinfunction "2_2") (pintype "passive"))
    )
    (net (code "206") (name "Net-(C34-Pad2)") (class "Default")
      (node (ref "C34") (pin "2") (pinfunction "2_2") (pintype "passive"))
      (node (ref "R89") (pin "2") (pinfunction "2_2") (pintype "passive"))
    )
    (net (code "207") (name "Net-(C35-Pad2)") (class "Default")
      (node (ref "C35") (pin "2") (pinfunction "2_2") (pintype "passive"))
      (node (ref "R91") (pin "2") (pinfunction "2_2") (pintype "passive"))
    )
    (net (code "208") (name "Net-(C36-Pad1)") (class "Default")
      (node (ref "C36") (pin "1") (pinfunction "1_1") (pintype "passive"))
      (node (ref "R93") (pin "2") (pinfunction "2_2") (pintype "passive"))
    )
    (net (code "209") (name "Net-(C40-Pad2)") (class "Default")
      (node (ref "C40") (pin "2") (pinfunction "2_2") (pintype "passive"))
      (node (ref "R106") (pin "2") (pinfunction "2_2") (pintype "passive"))
    )
    (net (code "210") (name "Net-(C41-Pad2)") (class "Default")
      (node (ref "C41") (pin "2") (pinfunction "2_2") (pintype "passive"))
      (node (ref "R107") (pin "2") (pinfunction "2_2") (pintype "passive"))
    )
    (net (code "211") (name "Net-(C42-Pad1)") (class "Default")
      (node (ref "C42") (pin "1") (pinfunction "1_1") (pintype "passive"))
      (node (ref "R108") (pin "2") (pinfunction "2_2") (pintype "passive"))
    )
    (net (code "212") (name "Net-(C46-Pad2)") (class "Default")
      (node (ref "C46") (pin "2") (pinfunction "2_2") (pintype "passive"))
      (node (ref "R120") (pin "2") (pinfunction "2_2") (pintype "passive"))
    )
    (net (code "213") (name "Net-(C47-Pad2)") (class "Default")
      (node (ref "C47") (pin "2") (pinfunction "2_2") (pintype "passive"))
      (node (ref "R121") (pin "2") (pinfunction "2_2") (pintype "passive"))
    )
    (net (code "214") (name "Net-(C48-Pad1)") (class "Default")
      (node (ref "C48") (pin "1") (pinfunction "1_1") (pintype "passive"))
      (node (ref "R122") (pin "2") (pinfunction "2_2") (pintype "passive"))
    )
    (net (code "215") (name "Net-(CB1-Pad2)") (class "Default")
      (node (ref "CB1") (pin "2") (pinfunction "2_2") (pintype "passive"))
      (node (ref "RB1") (pin "2") (pinfunction "2_2") (pintype "passive"))
    )
    (net (code "216") (name "Net-(CB2-Pad2)") (class "Default")
      (node (ref "CB2") (pin "2") (pinfunction "2_2") (pintype "passive"))
      (node (ref "RB2") (pin "2") (pinfunction "2_2") (pintype "passive"))
    )
    (net (code "217") (name "Net-(CB3-Pad2)") (class "Default")
      (node (ref "CB3") (pin "2") (pinfunction "2_2") (pintype "passive"))
      (node (ref "RB3") (pin "2") (pinfunction "2_2") (pintype "passive"))
    )
    (net (code "218") (name "Net-(CB4-Pad2)") (class "Default")
      (node (ref "CB4") (pin "2") (pinfunction "2_2") (pintype "passive"))
      (node (ref "RB4") (pin "2") (pinfunction "2_2") (pintype "passive"))
    )
    (net (code "219") (name "Net-(CB5-Pad2)") (class "Default")
      (node (ref "CB5") (pin "2") (pinfunction "2_2") (pintype "passive"))
      (node (ref "RB5") (pin "2") (pinfunction "2_2") (pintype "passive"))
    )
    (net (code "220") (name "Net-(CB6-Pad2)") (class "Default")
      (node (ref "CB6") (pin "2") (pinfunction "2_2") (pintype "passive"))
      (node (ref "RB6") (pin "2") (pinfunction "2_2") (pintype "passive"))
    )
    (net (code "221") (name "Net-(CB8-Pad2)") (class "Default")
      (node (ref "CB8") (pin "2") (pinfunction "2_2") (pintype "passive"))
      (node (ref "RB8") (pin "2") (pinfunction "2_2") (pintype "passive"))
    )
    (net (code "222") (name "Net-(CB9-Pad2)") (class "Default")
      (node (ref "CB9") (pin "2") (pinfunction "2_2") (pintype "passive"))
      (node (ref "RB9") (pin "2") (pinfunction "2_2") (pintype "passive"))
    )
    (net (code "223") (name "Net-(CB10-Pad1)") (class "Default")
      (node (ref "CB10") (pin "1") (pinfunction "1_1") (pintype "passive"))
      (node (ref "RB10") (pin "2") (pinfunction "2_2") (pintype "passive"))
    )
    (net (code "224") (name "Net-(CB11-Pad2)") (class "Default")
      (node (ref "CB11") (pin "2") (pinfunction "2_2") (pintype "passive"))
      (node (ref "RB11") (pin "2") (pinfunction "2_2") (pintype "passive"))
    )
    (net (code "225") (name "Net-(CB12-Pad2)") (class "Default")
      (node (ref "CB12") (pin "2") (pinfunction "2_2") (pintype "passive"))
      (node (ref "RB12") (pin "2") (pinfunction "2_2") (pintype "passive"))
    )
    (net (code "226") (name "Net-(CB13-Pad1)") (class "Default")
      (node (ref "CB13") (pin "1") (pinfunction "1_1") (pintype "passive"))
      (node (ref "RB13") (pin "2") (pinfunction "2_2") (pintype "passive"))
    )
    (net (code "227") (name "Net-(CB14-Pad2)") (class "Default")
      (node (ref "CB14") (pin "2") (pinfunction "2_2") (pintype "passive"))
      (node (ref "RB14") (pin "2") (pinfunction "2_2") (pintype "passive"))
    )
    (net (code "228") (name "Net-(CB15-Pad2)") (class "Default")
      (node (ref "CB15") (pin "2") (pinfunction "2_2") (pintype "passive"))
      (node (ref "RB15") (pin "2") (pinfunction "2_2") (pintype "passive"))
    )
    (net (code "229") (name "Net-(CB16-Pad1)") (class "Default")
      (node (ref "CB16") (pin "1") (pinfunction "1_1") (pintype "passive"))
      (node (ref "RB16") (pin "2") (pinfunction "2_2") (pintype "passive"))
    )
    (net (code "230") (name "Net-(CB17-Pad2)") (class "Default")
      (node (ref "CB17") (pin "2") (pinfunction "2_2") (pintype "passive"))
      (node (ref "RB17") (pin "2") (pinfunction "2_2") (pintype "passive"))
    )
    (net (code "231") (name "Net-(CB18-Pad2)") (class "Default")
      (node (ref "CB18") (pin "2") (pinfunction "2_2") (pintype "passive"))
      (node (ref "RB18") (pin "2") (pinfunction "2_2") (pintype "passive"))
    )
    (net (code "232") (name "Net-(CB19-Pad1)") (class "Default")
      (node (ref "CB19") (pin "1") (pinfunction "1_1") (pintype "passive"))
      (node (ref "RB19") (pin "2") (pinfunction "2_2") (pintype "passive"))
    )
    (net (code "233") (name "Net-(CB20-Pad2)") (class "Default")
      (node (ref "CB20") (pin "2") (pinfunction "2_2") (pintype "passive"))
      (node (ref "RB20") (pin "2") (pinfunction "2_2") (pintype "passive"))
    )
    (net (code "234") (name "Net-(CB21-Pad2)") (class "Default")
      (node (ref "CB21") (pin "2") (pinfunction "2_2") (pintype "passive"))
      (node (ref "RB21") (pin "2") (pinfunction "2_2") (pintype "passive"))
    )
    (net (code "235") (name "Net-(CB22-Pad1)") (class "Default")
      (node (ref "CB22") (pin "1") (pinfunction "1_1") (pintype "passive"))
      (node (ref "RB22") (pin "2") (pinfunction "2_2") (pintype "passive"))
    )
    (net (code "236") (name "Net-(CB23-Pad2)") (class "Default")
      (node (ref "CB23") (pin "2") (pinfunction "2_2") (pintype "passive"))
      (node (ref "RB23") (pin "2") (pinfunction "2_2") (pintype "passive"))
    )
    (net (code "237") (name "Net-(CB24-Pad2)") (class "Default")
      (node (ref "CB24") (pin "2") (pinfunction "2_2") (pintype "passive"))
      (node (ref "RB24") (pin "2") (pinfunction "2_2") (pintype "passive"))
    )
    (net (code "238") (name "Net-(CB25-Pad1)") (class "Default")
      (node (ref "CB25") (pin "1") (pinfunction "1_1") (pintype "passive"))
      (node (ref "RB25") (pin "2") (pinfunction "2_2") (pintype "passive"))
    )
    (net (code "239") (name "Net-(CB26-Pad2)") (class "Default")
      (node (ref "CB26") (pin "2") (pinfunction "2_2") (pintype "passive"))
      (node (ref "RB26") (pin "2") (pinfunction "2_2") (pintype "passive"))
    )
    (net (code "240") (name "Net-(CB27-Pad2)") (class "Default")
      (node (ref "CB27") (pin "2") (pinfunction "2_2") (pintype "passive"))
      (node (ref "RB27") (pin "2") (pinfunction "2_2") (pintype "passive"))
    )
    (net (code "241") (name "Net-(CB28-Pad1)") (class "Default")
      (node (ref "CB28") (pin "1") (pinfunction "1_1") (pintype "passive"))
      (node (ref "RB28") (pin "2") (pinfunction "2_2") (pintype "passive"))
    )
    (net (code "242") (name "Net-(CB29-Pad2)") (class "Default")
      (node (ref "CB29") (pin "2") (pinfunction "2_2") (pintype "passive"))
      (node (ref "RB29") (pin "2") (pinfunction "2_2") (pintype "passive"))
    )
    (net (code "243") (name "Net-(CB30-Pad2)") (class "Default")
      (node (ref "CB30") (pin "2") (pinfunction "2_2") (pintype "passive"))
      (node (ref "RB30") (pin "2") (pinfunction "2_2") (pintype "passive"))
    )
    (net (code "244") (name "Net-(CB31-Pad1)") (class "Default")
      (node (ref "CB31") (pin "1") (pinfunction "1_1") (pintype "passive"))
      (node (ref "RB31") (pin "2") (pinfunction "2_2") (pintype "passive"))
    )
    (net (code "245") (name "Net-(CB32-Pad2)") (class "Default")
      (node (ref "CB32") (pin "2") (pinfunction "2_2") (pintype "passive"))
      (node (ref "RB32") (pin "2") (pinfunction "2_2") (pintype "passive"))
    )
    (net (code "246") (name "Net-(CB33-Pad2)") (class "Default")
      (node (ref "CB33") (pin "2") (pinfunction "2_2") (pintype "passive"))
      (node (ref "RB33") (pin "2") (pinfunction "2_2") (pintype "passive"))
    )
    (net (code "247") (name "Net-(CB34-Pad1)") (class "Default")
      (node (ref "CB34") (pin "1") (pinfunction "1_1") (pintype "passive"))
      (node (ref "RB34") (pin "2") (pinfunction "2_2") (pintype "passive"))
    )
    (net (code "248") (name "Net-(CB35-Pad2)") (class "Default")
      (node (ref "CB35") (pin "2") (pinfunction "2_2") (pintype "passive"))
      (node (ref "RB35") (pin "2") (pinfunction "2_2") (pintype "passive"))
    )
    (net (code "249") (name "Net-(CB36-Pad2)") (class "Default")
      (node (ref "CB36") (pin "2") (pinfunction "2_2") (pintype "passive"))
      (node (ref "RB36") (pin "2") (pinfunction "2_2") (pintype "passive"))
    )
    (net (code "250") (name "Net-(CB37-Pad1)") (class "Default")
      (node (ref "CB37") (pin "1") (pinfunction "1_1") (pintype "passive"))
      (node (ref "RB37") (pin "2") (pinfunction "2_2") (pintype "passive"))
    )
    (net (code "251") (name "Net-(CB38-Pad2)") (class "Default")
      (node (ref "CB38") (pin "2") (pinfunction "2_2") (pintype "passive"))
      (node (ref "RB38") (pin "2") (pinfunction "2_2") (pintype "passive"))
    )
    (net (code "252") (name "Net-(CB39-Pad2)") (class "Default")
      (node (ref "CB39") (pin "2") (pinfunction "2_2") (pintype "passive"))
      (node (ref "RB39") (pin "2") (pinfunction "2_2") (pintype "passive"))
    )
    (net (code "253") (name "Net-(CB40-Pad1)") (class "Default")
      (node (ref "CB40") (pin "1") (pinfunction "1_1") (pintype "passive"))
      (node (ref "RB40") (pin "2") (pinfunction "2_2") (pintype "passive"))
    )
    (net (code "254") (name "Net-(CB41-Pad2)") (class "Default")
      (node (ref "CB41") (pin "2") (pinfunction "2_2") (pintype "passive"))
      (node (ref "RB41") (pin "2") (pinfunction "2_2") (pintype "passive"))
    )
    (net (code "255") (name "Net-(CB42-Pad2)") (class "Default")
      (node (ref "CB42") (pin "2") (pinfunction "2_2") (pintype "passive"))
      (node (ref "RB42") (pin "2") (pinfunction "2_2") (pintype "passive"))
    )
    (net (code "256") (name "Net-(CB43-Pad1)") (class "Default")
      (node (ref "CB43") (pin "1") (pinfunction "1_1") (pintype "passive"))
      (node (ref "RB43") (pin "2") (pinfunction "2_2") (pintype "passive"))
    )
    (net (code "257") (name "Net-(CB44-Pad2)") (class "Default")
      (node (ref "CB44") (pin "2") (pinfunction "2_2") (pintype "passive"))
      (node (ref "RB44") (pin "2") (pinfunction "2_2") (pintype "passive"))
    )
    (net (code "258") (name "Net-(CB45-Pad2)") (class "Default")
      (node (ref "CB45") (pin "2") (pinfunction "2_2") (pintype "passive"))
      (node (ref "RB45") (pin "2") (pinfunction "2_2") (pintype "passive"))
    )
    (net (code "259") (name "Net-(CB47-Pad2)") (class "Default")
      (node (ref "CB47") (pin "2") (pinfunction "2_2") (pintype "passive"))
      (node (ref "RB47") (pin "2") (pinfunction "2_2") (pintype "passive"))
    )
    (net (code "260") (name "Net-(CB48-Pad2)") (class "Default")
      (node (ref "CB48") (pin "2") (pinfunction "2_2") (pintype "passive"))
      (node (ref "RB48") (pin "2") (pinfunction "2_2") (pintype "passive"))
    )
    (net (code "261") (name "Net-(CB49-Pad1)") (class "Default")
      (node (ref "CB49") (pin "1") (pinfunction "1_1") (pintype "passive"))
      (node (ref "RB49") (pin "2") (pinfunction "2_2") (pintype "passive"))
    )
    (net (code "262") (name "Net-(CB50-Pad2)") (class "Default")
      (node (ref "CB50") (pin "2") (pinfunction "2_2") (pintype "passive"))
      (node (ref "RB50") (pin "2") (pinfunction "2_2") (pintype "passive"))
    )
    (net (code "263") (name "Net-(CB51-Pad2)") (class "Default")
      (node (ref "CB51") (pin "2") (pinfunction "2_2") (pintype "passive"))
      (node (ref "RB51") (pin "2") (pinfunction "2_2") (pintype "passive"))
    )
    (net (code "264") (name "Net-(CB52-Pad1)") (class "Default")
      (node (ref "CB52") (pin "1") (pinfunction "1_1") (pintype "passive"))
      (node (ref "RB52") (pin "2") (pinfunction "2_2") (pintype "passive"))
    )
    (net (code "265") (name "Net-(CB53-Pad2)") (class "Default")
      (node (ref "CB53") (pin "2") (pinfunction "2_2") (pintype "passive"))
      (node (ref "RB53") (pin "2") (pinfunction "2_2") (pintype "passive"))
    )
    (net (code "266") (name "Net-(CB54-Pad2)") (class "Default")
      (node (ref "CB54") (pin "2") (pinfunction "2_2") (pintype "passive"))
      (node (ref "RB54") (pin "2") (pinfunction "2_2") (pintype "passive"))
    )
    (net (code "267") (name "Net-(CB55-Pad1)") (class "Default")
      (node (ref "CB55") (pin "1") (pinfunction "1_1") (pintype "passive"))
      (node (ref "RB55") (pin "2") (pinfunction "2_2") (pintype "passive"))
    )
    (net (code "268") (name "Net-(CB56-Pad2)") (class "Default")
      (node (ref "CB56") (pin "2") (pinfunction "2_2") (pintype "passive"))
      (node (ref "RB56") (pin "2") (pinfunction "2_2") (pintype "passive"))
    )
    (net (code "269") (name "Net-(CB57-Pad2)") (class "Default")
      (node (ref "CB57") (pin "2") (pinfunction "2_2") (pintype "passive"))
      (node (ref "RB57") (pin "2") (pinfunction "2_2") (pintype "passive"))
    )
    (net (code "270") (name "Net-(CB58-Pad1)") (class "Default")
      (node (ref "CB58") (pin "1") (pinfunction "1_1") (pintype "passive"))
      (node (ref "RB58") (pin "2") (pinfunction "2_2") (pintype "passive"))
    )
    (net (code "271") (name "Net-(CB59-Pad2)") (class "Default")
      (node (ref "CB59") (pin "2") (pinfunction "2_2") (pintype "passive"))
      (node (ref "RB59") (pin "2") (pinfunction "2_2") (pintype "passive"))
    )
    (net (code "272") (name "Net-(CB60-Pad2)") (class "Default")
      (node (ref "CB60") (pin "2") (pinfunction "2_2") (pintype "passive"))
      (node (ref "RB60") (pin "2") (pinfunction "2_2") (pintype "passive"))
    )
    (net (code "273") (name "Net-(CB61-Pad1)") (class "Default")
      (node (ref "CB61") (pin "1") (pinfunction "1_1") (pintype "passive"))
      (node (ref "RB61") (pin "2") (pinfunction "2_2") (pintype "passive"))
    )
    (net (code "274") (name "Net-(CB62-Pad2)") (class "Default")
      (node (ref "CB62") (pin "2") (pinfunction "2_2") (pintype "passive"))
      (node (ref "RB62") (pin "2") (pinfunction "2_2") (pintype "passive"))
    )
    (net (code "275") (name "Net-(CB63-Pad2)") (class "Default")
      (node (ref "CB63") (pin "2") (pinfunction "2_2") (pintype "passive"))
      (node (ref "RB63") (pin "2") (pinfunction "2_2") (pintype "passive"))
    )
    (net (code "276") (name "Net-(CB64-Pad1)") (class "Default")
      (node (ref "CB64") (pin "1") (pinfunction "1_1") (pintype "passive"))
      (node (ref "RB64") (pin "2") (pinfunction "2_2") (pintype "passive"))
    )
    (net (code "277") (name "Net-(CB65-Pad2)") (class "Default")
      (node (ref "CB65") (pin "2") (pinfunction "2_2") (pintype "passive"))
      (node (ref "RB65") (pin "2") (pinfunction "2_2") (pintype "passive"))
    )
    (net (code "278") (name "Net-(CB66-Pad2)") (class "Default")
      (node (ref "CB66") (pin "2") (pinfunction "2_2") (pintype "passive"))
      (node (ref "RB66") (pin "2") (pinfunction "2_2") (pintype "passive"))
    )
    (net (code "279") (name "Net-(CB67-Pad1)") (class "Default")
      (node (ref "CB67") (pin "1") (pinfunction "1_1") (pintype "passive"))
      (node (ref "RB67") (pin "2") (pinfunction "2_2") (pintype "passive"))
    )
    (net (code "280") (name "Net-(CB68-Pad2)") (class "Default")
      (node (ref "CB68") (pin "2") (pinfunction "2_2") (pintype "passive"))
      (node (ref "RB68") (pin "2") (pinfunction "2_2") (pintype "passive"))
    )
    (net (code "281") (name "Net-(CB70-Pad2)") (class "Default")
      (node (ref "CB70") (pin "2") (pinfunction "2_2") (pintype "passive"))
      (node (ref "RB70") (pin "2") (pinfunction "2_2") (pintype "passive"))
    )
    (net (code "282") (name "Net-(CB71-Pad2)") (class "Default")
      (node (ref "CB71") (pin "2") (pinfunction "2_2") (pintype "passive"))
      (node (ref "RB71") (pin "2") (pinfunction "2_2") (pintype "passive"))
    )
    (net (code "283") (name "Net-(CB72-Pad2)") (class "Default")
      (node (ref "CB72") (pin "2") (pinfunction "2_2") (pintype "passive"))
      (node (ref "RB72") (pin "2") (pinfunction "2_2") (pintype "passive"))
    )
    (net (code "284") (name "Net-(CB73-Pad1)") (class "Default")
      (node (ref "CB73") (pin "1") (pinfunction "1_1") (pintype "passive"))
      (node (ref "RB73") (pin "2") (pinfunction "2_2") (pintype "passive"))
    )
    (net (code "285") (name "Net-(CB74-Pad2)") (class "Default")
      (node (ref "CB74") (pin "2") (pinfunction "2_2") (pintype "passive"))
      (node (ref "RB74") (pin "2") (pinfunction "2_2") (pintype "passive"))
    )
    (net (code "286") (name "Net-(CB75-Pad2)") (class "Default")
      (node (ref "CB75") (pin "2") (pinfunction "2_2") (pintype "passive"))
      (node (ref "RB75") (pin "2") (pinfunction "2_2") (pintype "passive"))
    )
    (net (code "287") (name "Net-(CB76-Pad1)") (class "Default")
      (node (ref "CB76") (pin "1") (pinfunction "1_1") (pintype "passive"))
      (node (ref "RB76") (pin "2") (pinfunction "2_2") (pintype "passive"))
    )
    (net (code "288") (name "Net-(CB77-Pad2)") (class "Default")
      (node (ref "CB77") (pin "2") (pinfunction "2_2") (pintype "passive"))
      (node (ref "RB77") (pin "2") (pinfunction "2_2") (pintype "passive"))
    )
    (net (code "289") (name "Net-(CB78-Pad2)") (class "Default")
      (node (ref "CB78") (pin "2") (pinfunction "2_2") (pintype "passive"))
      (node (ref "RB78") (pin "2") (pinfunction "2_2") (pintype "passive"))
    )
    (net (code "290") (name "Net-(CB79-Pad1)") (class "Default")
      (node (ref "CB79") (pin "1") (pinfunction "1_1") (pintype "passive"))
      (node (ref "RB79") (pin "2") (pinfunction "2_2") (pintype "passive"))
    )
    (net (code "291") (name "Net-(CB80-Pad2)") (class "Default")
      (node (ref "CB80") (pin "2") (pinfunction "2_2") (pintype "passive"))
      (node (ref "RB80") (pin "2") (pinfunction "2_2") (pintype "passive"))
    )
    (net (code "292") (name "Net-(CB81-Pad2)") (class "Default")
      (node (ref "CB81") (pin "2") (pinfunction "2_2") (pintype "passive"))
      (node (ref "RB81") (pin "2") (pinfunction "2_2") (pintype "passive"))
    )
    (net (code "293") (name "Net-(CB82-Pad1)") (class "Default")
      (node (ref "CB82") (pin "1") (pinfunction "1_1") (pintype "passive"))
      (node (ref "RB82") (pin "2") (pinfunction "2_2") (pintype "passive"))
    )
    (net (code "294") (name "Net-(CB83-Pad2)") (class "Default")
      (node (ref "CB83") (pin "2") (pinfunction "2_2") (pintype "passive"))
      (node (ref "RB83") (pin "2") (pinfunction "2_2") (pintype "passive"))
    )
    (net (code "295") (name "Net-(CB84-Pad2)") (class "Default")
      (node (ref "CB84") (pin "2") (pinfunction "2_2") (pintype "passive"))
      (node (ref "RB84") (pin "2") (pinfunction "2_2") (pintype "passive"))
    )
    (net (code "296") (name "Net-(CB85-Pad1)") (class "Default")
      (node (ref "CB85") (pin "1") (pinfunction "1_1") (pintype "passive"))
      (node (ref "RB85") (pin "2") (pinfunction "2_2") (pintype "passive"))
    )
    (net (code "297") (name "Net-(CB89-Pad2)") (class "Default")
      (node (ref "CB89") (pin "2") (pinfunction "2_2") (pintype "passive"))
      (node (ref "RB89") (pin "2") (pinfunction "2_2") (pintype "passive"))
    )
    (net (code "298") (name "Net-(CB90-Pad2)") (class "Default")
      (node (ref "CB90") (pin "2") (pinfunction "2_2") (pintype "passive"))
      (node (ref "RB90") (pin "2") (pinfunction "2_2") (pintype "passive"))
    )
    (net (code "299") (name "Net-(CB91-Pad1)") (class "Default")
      (node (ref "CB91") (pin "1") (pinfunction "1_1") (pintype "passive"))
      (node (ref "RB91") (pin "2") (pinfunction "2_2") (pintype "passive"))
    )
    (net (code "300") (name "Net-(CB92-Pad2)") (class "Default")
      (node (ref "CB92") (pin "2") (pinfunction "2_2") (pintype "passive"))
      (node (ref "RB92") (pin "2") (pinfunction "2_2") (pintype "passive"))
    )
    (net (code "301") (name "Net-(CB93-Pad2)") (class "Default")
      (node (ref "CB93") (pin "2") (pinfunction "2_2") (pintype "passive"))
      (node (ref "RB93") (pin "2") (pinfunction "2_2") (pintype "passive"))
    )
    (net (code "302") (name "Net-(CB94-Pad1)") (class "Default")
      (node (ref "CB94") (pin "1") (pinfunction "1_1") (pintype "passive"))
      (node (ref "RB94") (pin "2") (pinfunction "2_2") (pintype "passive"))
    )
    (net (code "303") (name "Net-(CB98-Pad2)") (class "Default")
      (node (ref "CB98") (pin "2") (pinfunction "2_2") (pintype "passive"))
      (node (ref "RB98") (pin "2") (pinfunction "2_2") (pintype "passive"))
    )
    (net (code "304") (name "Net-(CB99-Pad2)") (class "Default")
      (node (ref "CB99") (pin "2") (pinfunction "2_2") (pintype "passive"))
      (node (ref "RB99") (pin "2") (pinfunction "2_2") (pintype "passive"))
    )
    (net (code "305") (name "Net-(CB100-Pad1)") (class "Default")
      (node (ref "CB100") (pin "1") (pinfunction "1_1") (pintype "passive"))
      (node (ref "RB100") (pin "2") (pinfunction "2_2") (pintype "passive"))
    )
    (net (code "306") (name "Net-(CB104-Pad2)") (class "Default")
      (node (ref "CB104") (pin "2") (pinfunction "2_2") (pintype "passive"))
      (node (ref "RB104") (pin "2") (pinfunction "2_2") (pintype "passive"))
    )
    (net (code "307") (name "Net-(CB105-Pad2)") (class "Default")
      (node (ref "CB105") (pin "2") (pinfunction "2_2") (pintype "passive"))
      (node (ref "RB105") (pin "2") (pinfunction "2_2") (pintype "passive"))
    )
    (net (code "308") (name "Net-(CB106-Pad1)") (class "Default")
      (node (ref "CB106") (pin "1") (pinfunction "1_1") (pintype "passive"))
      (node (ref "RB106") (pin "2") (pinfunction "2_2") (pintype "passive"))
    )
    (net (code "309") (name "Net-(CB110-Pad2)") (class "Default")
      (node (ref "CB110") (pin "2") (pinfunction "2_2") (pintype "passive"))
      (node (ref "RB110") (pin "2") (pinfunction "2_2") (pintype "passive"))
    )
    (net (code "310") (name "Net-(CB111-Pad2)") (class "Default")
      (node (ref "CB111") (pin "2") (pinfunction "2_2") (pintype "passive"))
      (node (ref "RB111") (pin "2") (pinfunction "2_2") (pintype "passive"))
    )
    (net (code "311") (name "Net-(CB112-Pad1)") (class "Default")
      (node (ref "CB112") (pin "1") (pinfunction "1_1") (pintype "passive"))
      (node (ref "RB112") (pin "2") (pinfunction "2_2") (pintype "passive"))
    )
    (net (code "312") (name "Net-(CB116-Pad2)") (class "Default")
      (node (ref "CB116") (pin "2") (pinfunction "2_2") (pintype "passive"))
      (node (ref "RB116") (pin "2") (pinfunction "2_2") (pintype "passive"))
    )
    (net (code "313") (name "Net-(CB117-Pad2)") (class "Default")
      (node (ref "CB117") (pin "2") (pinfunction "2_2") (pintype "passive"))
      (node (ref "RB117") (pin "2") (pinfunction "2_2") (pintype "passive"))
    )
    (net (code "314") (name "Net-(CB118-Pad1)") (class "Default")
      (node (ref "CB118") (pin "1") (pinfunction "1_1") (pintype "passive"))
      (node (ref "RB118") (pin "2") (pinfunction "2_2") (pintype "passive"))
    )
    (net (code "315") (name "Net-(ENC_01--B)") (class "Default")
      (node (ref "ENC_01") (pin "4") (pinfunction "-B_4") (pintype "passive"))
      (node (ref "R185") (pin "2") (pinfunction "2_2") (pintype "passive"))
    )
    (net (code "316") (name "Net-(ENC_01--G)") (class "Default")
      (node (ref "ENC_01") (pin "2") (pinfunction "-G_2") (pintype "passive"))
      (node (ref "R184") (pin "2") (pinfunction "2_2") (pintype "passive"))
    )
    (net (code "317") (name "Net-(ENC_01--R)") (class "Default")
      (node (ref "ENC_01") (pin "1") (pinfunction "-R_1") (pintype "passive"))
      (node (ref "R183") (pin "2") (pinfunction "2_2") (pintype "passive"))
    )
    (net (code "318") (name "Net-(ENC_02--B)") (class "Default")
      (node (ref "ENC_02") (pin "4") (pinfunction "-B_4") (pintype "passive"))
      (node (ref "R191") (pin "2") (pinfunction "2_2") (pintype "passive"))
    )
    (net (code "319") (name "Net-(ENC_02--G)") (class "Default")
      (node (ref "ENC_02") (pin "2") (pinfunction "-G_2") (pintype "passive"))
      (node (ref "R190") (pin "2") (pinfunction "2_2") (pintype "passive"))
    )
    (net (code "320") (name "Net-(ENC_02--R)") (class "Default")
      (node (ref "ENC_02") (pin "1") (pinfunction "-R_1") (pintype "passive"))
      (node (ref "R189") (pin "2") (pinfunction "2_2") (pintype "passive"))
    )
    (net (code "321") (name "Net-(ENC_3--B)") (class "Default")
      (node (ref "ENC_3") (pin "4") (pinfunction "-B_4") (pintype "passive"))
      (node (ref "R197") (pin "2") (pinfunction "2_2") (pintype "passive"))
    )
    (net (code "322") (name "Net-(ENC_3--G)") (class "Default")
      (node (ref "ENC_3") (pin "2") (pinfunction "-G_2") (pintype "passive"))
      (node (ref "R196") (pin "2") (pinfunction "2_2") (pintype "passive"))
    )
    (net (code "323") (name "Net-(ENC_3--R)") (class "Default")
      (node (ref "ENC_3") (pin "1") (pinfunction "-R_1") (pintype "passive"))
      (node (ref "R195") (pin "2") (pinfunction "2_2") (pintype "passive"))
    )
    (net (code "324") (name "Net-(ENC_11--B)") (class "Default")
      (node (ref "ENC_11") (pin "4") (pinfunction "-B_4") (pintype "passive"))
      (node (ref "R12") (pin "2") (pinfunction "2_2") (pintype "passive"))
    )
    (net (code "325") (name "Net-(ENC_11--G)") (class "Default")
      (node (ref "ENC_11") (pin "2") (pinfunction "-G_2") (pintype "passive"))
      (node (ref "R11") (pin "2") (pinfunction "2_2") (pintype "passive"))
    )
    (net (code "326") (name "Net-(ENC_11--R)") (class "Default")
      (node (ref "ENC_11") (pin "1") (pinfunction "-R_1") (pintype "passive"))
      (node (ref "R10") (pin "2") (pinfunction "2_2") (pintype "passive"))
    )
    (net (code "327") (name "Net-(ENC_13--B)") (class "Default")
      (node (ref "ENC_13") (pin "4") (pinfunction "-B_4") (pintype "passive"))
      (node (ref "R19") (pin "2") (pinfunction "2_2") (pintype "passive"))
    )
    (net (code "328") (name "Net-(ENC_13--G)") (class "Default")
      (node (ref "ENC_13") (pin "2") (pinfunction "-G_2") (pintype "passive"))
      (node (ref "R18") (pin "2") (pinfunction "2_2") (pintype "passive"))
    )
    (net (code "329") (name "Net-(ENC_13--R)") (class "Default")
      (node (ref "ENC_13") (pin "1") (pinfunction "-R_1") (pintype "passive"))
      (node (ref "R17") (pin "2") (pinfunction "2_2") (pintype "passive"))
    )
    (net (code "330") (name "Net-(ENC_14--B)") (class "Default")
      (node (ref "ENC_14") (pin "4") (pinfunction "-B_4") (pintype "passive"))
      (node (ref "R26") (pin "2") (pinfunction "2_2") (pintype "passive"))
    )
    (net (code "331") (name "Net-(ENC_14--G)") (class "Default")
      (node (ref "ENC_14") (pin "2") (pinfunction "-G_2") (pintype "passive"))
      (node (ref "R25") (pin "2") (pinfunction "2_2") (pintype "passive"))
    )
    (net (code "332") (name "Net-(ENC_14--R)") (class "Default")
      (node (ref "ENC_14") (pin "1") (pinfunction "-R_1") (pintype "passive"))
      (node (ref "R24") (pin "2") (pinfunction "2_2") (pintype "passive"))
    )
    (net (code "333") (name "Net-(ENC_21--B)") (class "Default")
      (node (ref "ENC_21") (pin "4") (pinfunction "-B_4") (pintype "passive"))
      (node (ref "R40") (pin "2") (pinfunction "2_2") (pintype "passive"))
    )
    (net (code "334") (name "Net-(ENC_21--G)") (class "Default")
      (node (ref "ENC_21") (pin "2") (pinfunction "-G_2") (pintype "passive"))
      (node (ref "R39") (pin "2") (pinfunction "2_2") (pintype "passive"))
    )
    (net (code "335") (name "Net-(ENC_21--R)") (class "Default")
      (node (ref "ENC_21") (pin "1") (pinfunction "-R_1") (pintype "passive"))
      (node (ref "R38") (pin "2") (pinfunction "2_2") (pintype "passive"))
    )
    (net (code "336") (name "Net-(ENC_23--B)") (class "Default")
      (node (ref "ENC_23") (pin "4") (pinfunction "-B_4") (pintype "passive"))
      (node (ref "R54") (pin "2") (pinfunction "2_2") (pintype "passive"))
    )
    (net (code "337") (name "Net-(ENC_23--G)") (class "Default")
      (node (ref "ENC_23") (pin "2") (pinfunction "-G_2") (pintype "passive"))
      (node (ref "R53") (pin "2") (pinfunction "2_2") (pintype "passive"))
    )
    (net (code "338") (name "Net-(ENC_23--R)") (class "Default")
      (node (ref "ENC_23") (pin "1") (pinfunction "-R_1") (pintype "passive"))
      (node (ref "R52") (pin "2") (pinfunction "2_2") (pintype "passive"))
    )
    (net (code "339") (name "Net-(ENC_41--B)") (class "Default")
      (node (ref "ENC_41") (pin "4") (pinfunction "-B_4") (pintype "passive"))
      (node (ref "R51") (pin "2") (pinfunction "2_2") (pintype "passive"))
    )
    (net (code "340") (name "Net-(ENC_41--G)") (class "Default")
      (node (ref "ENC_41") (pin "2") (pinfunction "-G_2") (pintype "passive"))
      (node (ref "R47") (pin "2") (pinfunction "2_2") (pintype "passive"))
    )
    (net (code "341") (name "Net-(ENC_41--R)") (class "Default")
      (node (ref "ENC_41") (pin "1") (pinfunction "-R_1") (pintype "passive"))
      (node (ref "R46") (pin "2") (pinfunction "2_2") (pintype "passive"))
    )
    (net (code "342") (name "Net-(ENC_44--B)") (class "Default")
      (node (ref "ENC_44") (pin "4") (pinfunction "-B_4") (pintype "passive"))
      (node (ref "R64") (pin "2") (pinfunction "2_2") (pintype "passive"))
    )
    (net (code "343") (name "Net-(ENC_44--G)") (class "Default")
      (node (ref "ENC_44") (pin "2") (pinfunction "-G_2") (pintype "passive"))
      (node (ref "R63") (pin "2") (pinfunction "2_2") (pintype "passive"))
    )
    (net (code "344") (name "Net-(ENC_44--R)") (class "Default")
      (node (ref "ENC_44") (pin "1") (pinfunction "-R_1") (pintype "passive"))
      (node (ref "R62") (pin "2") (pinfunction "2_2") (pintype "passive"))
    )
    (net (code "345") (name "Net-(ENC_45--B)") (class "Default")
      (node (ref "ENC_45") (pin "4") (pinfunction "-B_4") (pintype "passive"))
      (node (ref "R77") (pin "2") (pinfunction "2_2") (pintype "passive"))
    )
    (net (code "346") (name "Net-(ENC_45--G)") (class "Default")
      (node (ref "ENC_45") (pin "2") (pinfunction "-G_2") (pintype "passive"))
      (node (ref "R76") (pin "2") (pinfunction "2_2") (pintype "passive"))
    )
    (net (code "347") (name "Net-(ENC_45--R)") (class "Default")
      (node (ref "ENC_45") (pin "1") (pinfunction "-R_1") (pintype "passive"))
      (node (ref "R75") (pin "2") (pinfunction "2_2") (pintype "passive"))
    )
    (net (code "348") (name "Net-(ENC_48--B)") (class "Default")
      (node (ref "ENC_48") (pin "4") (pinfunction "-B_4") (pintype "passive"))
      (node (ref "R96") (pin "2") (pinfunction "2_2") (pintype "passive"))
    )
    (net (code "349") (name "Net-(ENC_48--G)") (class "Default")
      (node (ref "ENC_48") (pin "2") (pinfunction "-G_2") (pintype "passive"))
      (node (ref "R94") (pin "2") (pinfunction "2_2") (pintype "passive"))
    )
    (net (code "350") (name "Net-(ENC_48--R)") (class "Default")
      (node (ref "ENC_48") (pin "1") (pinfunction "-R_1") (pintype "passive"))
      (node (ref "R86") (pin "2") (pinfunction "2_2") (pintype "passive"))
    )
    (net (code "351") (name "Net-(ENC_51--B)") (class "Default")
      (node (ref "ENC_51") (pin "4") (pinfunction "-B_4") (pintype "passive"))
      (node (ref "R45") (pin "2") (pinfunction "2_2") (pintype "passive"))
    )
    (net (code "352") (name "Net-(ENC_51--G)") (class "Default")
      (node (ref "ENC_51") (pin "2") (pinfunction "-G_2") (pintype "passive"))
      (node (ref "R34") (pin "2") (pinfunction "2_2") (pintype "passive"))
    )
    (net (code "353") (name "Net-(ENC_51--R)") (class "Default")
      (node (ref "ENC_51") (pin "1") (pinfunction "-R_1") (pintype "passive"))
      (node (ref "R33") (pin "2") (pinfunction "2_2") (pintype "passive"))
    )
    (net (code "354") (name "Net-(ENC_53--B)") (class "Default")
      (node (ref "ENC_53") (pin "4") (pinfunction "-B_4") (pintype "passive"))
      (node (ref "R61") (pin "2") (pinfunction "2_2") (pintype "passive"))
    )
    (net (code "355") (name "Net-(ENC_53--G)") (class "Default")
      (node (ref "ENC_53") (pin "2") (pinfunction "-G_2") (pintype "passive"))
      (node (ref "R60") (pin "2") (pinfunction "2_2") (pintype "passive"))
    )
    (net (code "356") (name "Net-(ENC_53--R)") (class "Default")
      (node (ref "ENC_53") (pin "1") (pinfunction "-R_1") (pintype "passive"))
      (node (ref "R59") (pin "2") (pinfunction "2_2") (pintype "passive"))
    )
    (net (code "357") (name "Net-(ENC_54--B)") (class "Default")
      (node (ref "ENC_54") (pin "4") (pinfunction "-B_4") (pintype "passive"))
      (node (ref "R83") (pin "2") (pinfunction "2_2") (pintype "passive"))
    )
    (net (code "358") (name "Net-(ENC_54--G)") (class "Default")
      (node (ref "ENC_54") (pin "2") (pinfunction "-G_2") (pintype "passive"))
      (node (ref "R80") (pin "2") (pinfunction "2_2") (pintype "passive"))
    )
    (net (code "359") (name "Net-(ENC_54--R)") (class "Default")
      (node (ref "ENC_54") (pin "1") (pinfunction "-R_1") (pintype "passive"))
      (node (ref "R78") (pin "2") (pinfunction "2_2") (pintype "passive"))
    )
    (net (code "360") (name "Net-(ENC_55--B)") (class "Default")
      (node (ref "ENC_55") (pin "4") (pinfunction "-B_4") (pintype "passive"))
      (node (ref "R109") (pin "2") (pinfunction "2_2") (pintype "passive"))
    )
    (net (code "361") (name "Net-(ENC_55--G)") (class "Default")
      (node (ref "ENC_55") (pin "2") (pinfunction "-G_2") (pintype "passive"))
      (node (ref "R101") (pin "2") (pinfunction "2_2") (pintype "passive"))
    )
    (net (code "362") (name "Net-(ENC_55--R)") (class "Default")
      (node (ref "ENC_55") (pin "1") (pinfunction "-R_1") (pintype "passive"))
      (node (ref "R100") (pin "2") (pinfunction "2_2") (pintype "passive"))
    )
    (net (code "363") (name "Net-(ENC_56--B)") (class "Default")
      (node (ref "ENC_56") (pin "4") (pinfunction "-B_4") (pintype "passive"))
      (node (ref "R115") (pin "2") (pinfunction "2_2") (pintype "passive"))
    )
    (net (code "364") (name "Net-(ENC_56--G)") (class "Default")
      (node (ref "ENC_56") (pin "2") (pinfunction "-G_2") (pintype "passive"))
      (node (ref "R114") (pin "2") (pinfunction "2_2") (pintype "passive"))
    )
    (net (code "365") (name "Net-(ENC_56--R)") (class "Default")
      (node (ref "ENC_56") (pin "1") (pinfunction "-R_1") (pintype "passive"))
      (node (ref "R113") (pin "2") (pinfunction "2_2") (pintype "passive"))
    )
    (net (code "366") (name "Net-(ENC_57--B)") (class "Default")
      (node (ref "ENC_57") (pin "4") (pinfunction "-B_4") (pintype "passive"))
      (node (ref "R128") (pin "2") (pinfunction "2_2") (pintype "passive"))
    )
    (net (code "367") (name "Net-(ENC_57--G)") (class "Default")
      (node (ref "ENC_57") (pin "2") (pinfunction "-G_2") (pintype "passive"))
      (node (ref "R127") (pin "2") (pinfunction "2_2") (pintype "passive"))
    )
    (net (code "368") (name "Net-(ENC_57--R)") (class "Default")
      (node (ref "ENC_57") (pin "1") (pinfunction "-R_1") (pintype "passive"))
      (node (ref "R126") (pin "2") (pinfunction "2_2") (pintype "passive"))
    )
    (net (code "369") (name "Net-(ENC_61--B)") (class "Default")
      (node (ref "ENC_61") (pin "4") (pinfunction "-B_4") (pintype "passive"))
      (node (ref "R134") (pin "2") (pinfunction "2_2") (pintype "passive"))
    )
    (net (code "370") (name "Net-(ENC_61--G)") (class "Default")
      (node (ref "ENC_61") (pin "2") (pinfunction "-G_2") (pintype "passive"))
      (node (ref "R133") (pin "2") (pinfunction "2_2") (pintype "passive"))
    )
    (net (code "371") (name "Net-(ENC_61--R)") (class "Default")
      (node (ref "ENC_61") (pin "1") (pinfunction "-R_1") (pintype "passive"))
      (node (ref "R132") (pin "2") (pinfunction "2_2") (pintype "passive"))
    )
    (net (code "372") (name "Net-(ENC_62--B)") (class "Default")
      (node (ref "ENC_62") (pin "4") (pinfunction "-B_4") (pintype "passive"))
      (node (ref "R140") (pin "2") (pinfunction "2_2") (pintype "passive"))
    )
    (net (code "373") (name "Net-(ENC_62--G)") (class "Default")
      (node (ref "ENC_62") (pin "2") (pinfunction "-G_2") (pintype "passive"))
      (node (ref "R139") (pin "2") (pinfunction "2_2") (pintype "passive"))
    )
    (net (code "374") (name "Net-(ENC_62--R)") (class "Default")
      (node (ref "ENC_62") (pin "1") (pinfunction "-R_1") (pintype "passive"))
      (node (ref "R138") (pin "2") (pinfunction "2_2") (pintype "passive"))
    )
    (net (code "375") (name "Net-(ENC_63--B)") (class "Default")
      (node (ref "ENC_63") (pin "4") (pinfunction "-B_4") (pintype "passive"))
      (node (ref "R146") (pin "2") (pinfunction "2_2") (pintype "passive"))
    )
    (net (code "376") (name "Net-(ENC_63--G)") (class "Default")
      (node (ref "ENC_63") (pin "2") (pinfunction "-G_2") (pintype "passive"))
      (node (ref "R145") (pin "2") (pinfunction "2_2") (pintype "passive"))
    )
    (net (code "377") (name "Net-(ENC_63--R)") (class "Default")
      (node (ref "ENC_63") (pin "1") (pinfunction "-R_1") (pintype "passive"))
      (node (ref "R144") (pin "2") (pinfunction "2_2") (pintype "passive"))
    )
    (net (code "378") (name "Net-(ENC_64--B)") (class "Default")
      (node (ref "ENC_64") (pin "4") (pinfunction "-B_4") (pintype "passive"))
      (node (ref "R152") (pin "2") (pinfunction "2_2") (pintype "passive"))
    )
    (net (code "379") (name "Net-(ENC_64--G)") (class "Default")
      (node (ref "ENC_64") (pin "2") (pinfunction "-G_2") (pintype "passive"))
      (node (ref "R151") (pin "2") (pinfunction "2_2") (pintype "passive"))
    )
    (net (code "380") (name "Net-(ENC_64--R)") (class "Default")
      (node (ref "ENC_64") (pin "1") (pinfunction "-R_1") (pintype "passive"))
      (node (ref "R150") (pin "2") (pinfunction "2_2") (pintype "passive"))
    )
    (net (code "381") (name "Net-(ENC_71--B)") (class "Default")
      (node (ref "ENC_71") (pin "4") (pinfunction "-B_4") (pintype "passive"))
      (node (ref "R99") (pin "2") (pinfunction "2_2") (pintype "passive"))
    )
    (net (code "382") (name "Net-(ENC_71--G)") (class "Default")
      (node (ref "ENC_71") (pin "2") (pinfunction "-G_2") (pintype "passive"))
      (node (ref "R98") (pin "2") (pinfunction "2_2") (pintype "passive"))
    )
    (net (code "383") (name "Net-(ENC_71--R)") (class "Default")
      (node (ref "ENC_71") (pin "1") (pinfunction "-R_1") (pintype "passive"))
      (node (ref "R97") (pin "2") (pinfunction "2_2") (pintype "passive"))
    )
    (net (code "384") (name "Net-(ENC_72--B)") (class "Default")
      (node (ref "ENC_72") (pin "4") (pinfunction "-B_4") (pintype "passive"))
      (node (ref "R137") (pin "2") (pinfunction "2_2") (pintype "passive"))
    )
    (net (code "385") (name "Net-(ENC_72--G)") (class "Default")
      (node (ref "ENC_72") (pin "2") (pinfunction "-G_2") (pintype "passive"))
      (node (ref "R136") (pin "2") (pinfunction "2_2") (pintype "passive"))
    )
    (net (code "386") (name "Net-(ENC_72--R)") (class "Default")
      (node (ref "ENC_72") (pin "1") (pinfunction "-R_1") (pintype "passive"))
      (node (ref "R135") (pin "2") (pinfunction "2_2") (pintype "passive"))
    )
    (net (code "387") (name "Net-(ENC_73--B)") (class "Default")
      (node (ref "ENC_73") (pin "4") (pinfunction "-B_4") (pintype "passive"))
      (node (ref "R161") (pin "2") (pinfunction "2_2") (pintype "passive"))
    )
    (net (code "388") (name "Net-(ENC_73--G)") (class "Default")
      (node (ref "ENC_73") (pin "2") (pinfunction "-G_2") (pintype "passive"))
      (node (ref "R160") (pin "2") (pinfunction "2_2") (pintype "passive"))
    )
    (net (code "389") (name "Net-(ENC_73--R)") (class "Default")
      (node (ref "ENC_73") (pin "1") (pinfunction "-R_1") (pintype "passive"))
      (node (ref "R159") (pin "2") (pinfunction "2_2") (pintype "passive"))
    )
    (net (code "390") (name "Net-(ENC_74--B)") (class "Default")
      (node (ref "ENC_74") (pin "4") (pinfunction "-B_4") (pintype "passive"))
      (node (ref "R173") (pin "2") (pinfunction "2_2") (pintype "passive"))
    )
    (net (code "391") (name "Net-(ENC_74--G)") (class "Default")
      (node (ref "ENC_74") (pin "2") (pinfunction "-G_2") (pintype "passive"))
      (node (ref "R172") (pin "2") (pinfunction "2_2") (pintype "passive"))
    )
    (net (code "392") (name "Net-(ENC_74--R)") (class "Default")
      (node (ref "ENC_74") (pin "1") (pinfunction "-R_1") (pintype "passive"))
      (node (ref "R171") (pin "2") (pinfunction "2_2") (pintype "passive"))
    )
    (net (code "393") (name "Net-(ENC_75--B)") (class "Default")
      (node (ref "ENC_75") (pin "4") (pinfunction "-B_4") (pintype "passive"))
      (node (ref "R179") (pin "2") (pinfunction "2_2") (pintype "passive"))
    )
    (net (code "394") (name "Net-(ENC_75--G)") (class "Default")
      (node (ref "ENC_75") (pin "2") (pinfunction "-G_2") (pintype "passive"))
      (node (ref "R178") (pin "2") (pinfunction "2_2") (pintype "passive"))
    )
    (net (code "395") (name "Net-(ENC_75--R)") (class "Default")
      (node (ref "ENC_75") (pin "1") (pinfunction "-R_1") (pintype "passive"))
      (node (ref "R177") (pin "2") (pinfunction "2_2") (pintype "passive"))
    )
    (net (code "396") (name "Net-(ENC_81--B)") (class "Default")
      (node (ref "ENC_81") (pin "4") (pinfunction "-B_4") (pintype "passive"))
      (node (ref "R158") (pin "2") (pinfunction "2_2") (pintype "passive"))
    )
    (net (code "397") (name "Net-(ENC_81--G)") (class "Default")
      (node (ref "ENC_81") (pin "2") (pinfunction "-G_2") (pintype "passive"))
      (node (ref "R157") (pin "2") (pinfunction "2_2") (pintype "passive"))
    )
    (net (code "398") (name "Net-(ENC_81--R)") (class "Default")
      (node (ref "ENC_81") (pin "1") (pinfunction "-R_1") (pintype "passive"))
      (node (ref "R156") (pin "2") (pinfunction "2_2") (pintype "passive"))
    )
    (net (code "399") (name "Net-(ENC_82--B)") (class "Default")
      (node (ref "ENC_82") (pin "4") (pinfunction "-B_4") (pintype "passive"))
      (node (ref "R74") (pin "2") (pinfunction "2_2") (pintype "passive"))
    )
    (net (code "400") (name "Net-(ENC_82--G)") (class "Default")
      (node (ref "ENC_82") (pin "2") (pinfunction "-G_2") (pintype "passive"))
      (node (ref "R73") (pin "2") (pinfunction "2_2") (pintype "passive"))
    )
    (net (code "401") (name "Net-(ENC_82--R)") (class "Default")
      (node (ref "ENC_82") (pin "1") (pinfunction "-R_1") (pintype "passive"))
      (node (ref "R65") (pin "2") (pinfunction "2_2") (pintype "passive"))
    )
    (net (code "402") (name "Net-(ENC_83--B)") (class "Default")
      (node (ref "ENC_83") (pin "4") (pinfunction "-B_4") (pintype "passive"))
      (node (ref "R112") (pin "2") (pinfunction "2_2") (pintype "passive"))
    )
    (net (code "403") (name "Net-(ENC_83--G)") (class "Default")
      (node (ref "ENC_83") (pin "2") (pinfunction "-G_2") (pintype "passive"))
      (node (ref "R111") (pin "2") (pinfunction "2_2") (pintype "passive"))
    )
    (net (code "404") (name "Net-(ENC_83--R)") (class "Default")
      (node (ref "ENC_83") (pin "1") (pinfunction "-R_1") (pintype "passive"))
      (node (ref "R110") (pin "2") (pinfunction "2_2") (pintype "passive"))
    )
    (net (code "405") (name "Net-(ENC_84--B)") (class "Default")
      (node (ref "ENC_84") (pin "4") (pinfunction "-B_4") (pintype "passive"))
      (node (ref "R131") (pin "2") (pinfunction "2_2") (pintype "passive"))
    )
    (net (code "406") (name "Net-(ENC_84--G)") (class "Default")
      (node (ref "ENC_84") (pin "2") (pinfunction "-G_2") (pintype "passive"))
      (node (ref "R130") (pin "2") (pinfunction "2_2") (pintype "passive"))
    )
    (net (code "407") (name "Net-(ENC_84--R)") (class "Default")
      (node (ref "ENC_84") (pin "1") (pinfunction "-R_1") (pintype "passive"))
      (node (ref "R129") (pin "2") (pinfunction "2_2") (pintype "passive"))
    )
    (net (code "408") (name "Net-(ENC_85--B)") (class "Default")
      (node (ref "ENC_85") (pin "4") (pinfunction "-B_4") (pintype "passive"))
      (node (ref "R143") (pin "2") (pinfunction "2_2") (pintype "passive"))
    )
    (net (code "409") (name "Net-(ENC_85--G)") (class "Default")
      (node (ref "ENC_85") (pin "2") (pinfunction "-G_2") (pintype "passive"))
      (node (ref "R142") (pin "2") (pinfunction "2_2") (pintype "passive"))
    )
    (net (code "410") (name "Net-(ENC_85--R)") (class "Default")
      (node (ref "ENC_85") (pin "1") (pinfunction "-R_1") (pintype "passive"))
      (node (ref "R141") (pin "2") (pinfunction "2_2") (pintype "passive"))
    )
    (net (code "411") (name "Net-(ENC_86--B)") (class "Default")
      (node (ref "ENC_86") (pin "4") (pinfunction "-B_4") (pintype "passive"))
      (node (ref "R155") (pin "2") (pinfunction "2_2") (pintype "passive"))
    )
    (net (code "412") (name "Net-(ENC_86--G)") (class "Default")
      (node (ref "ENC_86") (pin "2") (pinfunction "-G_2") (pintype "passive"))
      (node (ref "R154") (pin "2") (pinfunction "2_2") (pintype "passive"))
    )
    (net (code "413") (name "Net-(ENC_86--R)") (class "Default")
      (node (ref "ENC_86") (pin "1") (pinfunction "-R_1") (pintype "passive"))
      (node (ref "R153") (pin "2") (pinfunction "2_2") (pintype "passive"))
    )
    (net (code "414") (name "Net-(ENC_87--B)") (class "Default")
      (node (ref "ENC_87") (pin "4") (pinfunction "-B_4") (pintype "passive"))
      (node (ref "R164") (pin "2") (pinfunction "2_2") (pintype "passive"))
    )
    (net (code "415") (name "Net-(ENC_87--G)") (class "Default")
      (node (ref "ENC_87") (pin "2") (pinfunction "-G_2") (pintype "passive"))
      (node (ref "R163") (pin "2") (pinfunction "2_2") (pintype "passive"))
    )
    (net (code "416") (name "Net-(ENC_87--R)") (class "Default")
      (node (ref "ENC_87") (pin "1") (pinfunction "-R_1") (pintype "passive"))
      (node (ref "R162") (pin "2") (pinfunction "2_2") (pintype "passive"))
    )
    (net (code "417") (name "Net-(ENC_88--B)") (class "Default")
      (node (ref "ENC_88") (pin "4") (pinfunction "-B_4") (pintype "passive"))
      (node (ref "R170") (pin "2") (pinfunction "2_2") (pintype "passive"))
    )
    (net (code "418") (name "Net-(ENC_88--G)") (class "Default")
      (node (ref "ENC_88") (pin "2") (pinfunction "-G_2") (pintype "passive"))
      (node (ref "R169") (pin "2") (pinfunction "2_2") (pintype "passive"))
    )
    (net (code "419") (name "Net-(ENC_88--R)") (class "Default")
      (node (ref "ENC_88") (pin "1") (pinfunction "-R_1") (pintype "passive"))
      (node (ref "R168") (pin "2") (pinfunction "2_2") (pintype "passive"))
    )
    (net (code "420") (name "Net-(F446-BOOT0)") (class "Default")
      (node (ref "F446") (pin "60") (pinfunction "BOOT0_60") (pintype "input"))
      (node (ref "R81") (pin "1") (pinfunction "1_1") (pintype "passive"))
    )
    (net (code "421") (name "Net-(F446-VCAP_1)") (class "Default")
      (node (ref "C60") (pin "2") (pinfunction "2_2") (pintype "passive"))
      (node (ref "F446") (pin "30") (pinfunction "VCAP_1_30") (pintype "power_in"))
    )
    (net (code "422") (name "Net-(GREEN-PadA)") (class "Default")
      (node (ref "GREEN") (pin "A") (pinfunction "A_A") (pintype "passive"))
      (node (ref "R90") (pin "2") (pinfunction "2_2") (pintype "passive"))
    )
    (net (code "423") (name "Net-(L1-Pad1)") (class "Default")
      (node (ref "L1") (pin "1") (pinfunction "1_1") (pintype "passive"))
      (node (ref "R87") (pin "1") (pinfunction "1_1") (pintype "passive"))
    )
    (net (code "424") (name "Net-(LED1-B)") (class "Default")
      (node (ref "LED1") (pin "4") (pinfunction "B_4") (pintype "bidirectional"))
      (node (ref "R6") (pin "2") (pinfunction "2_2") (pintype "passive"))
    )
    (net (code "425") (name "Net-(LED1-G)") (class "Default")
      (node (ref "LED1") (pin "3") (pinfunction "G_3") (pintype "bidirectional"))
      (node (ref "R3") (pin "2") (pinfunction "2_2") (pintype "passive"))
    )
    (net (code "426") (name "Net-(LED1-R)") (class "Default")
      (node (ref "LED1") (pin "1") (pinfunction "R_1") (pintype "bidirectional"))
      (node (ref "R7") (pin "2") (pinfunction "2_2") (pintype "passive"))
    )
    (net (code "427") (name "Net-(LED2-B)") (class "Default")
      (node (ref "LED2") (pin "4") (pinfunction "B_4") (pintype "bidirectional"))
      (node (ref "R9") (pin "2") (pinfunction "2_2") (pintype "passive"))
    )
    (net (code "428") (name "Net-(LED2-G)") (class "Default")
      (node (ref "LED2") (pin "3") (pinfunction "G_3") (pintype "bidirectional"))
      (node (ref "R8") (pin "2") (pinfunction "2_2") (pintype "passive"))
    )
    (net (code "429") (name "Net-(LED2-R)") (class "Default")
      (node (ref "LED2") (pin "1") (pinfunction "R_1") (pintype "bidirectional"))
      (node (ref "R31") (pin "2") (pinfunction "2_2") (pintype "passive"))
    )
    (net (code "430") (name "Net-(LED4-B)") (class "Default")
      (node (ref "LED4") (pin "4") (pinfunction "B_4") (pintype "bidirectional"))
      (node (ref "R147") (pin "2") (pinfunction "2_2") (pintype "passive"))
    )
    (net (code "431") (name "Net-(LED4-G)") (class "Default")
      (node (ref "LED4") (pin "3") (pinfunction "G_3") (pintype "bidirectional"))
      (node (ref "R125") (pin "2") (pinfunction "2_2") (pintype "passive"))
    )
    (net (code "432") (name "Net-(LED4-R)") (class "Default")
      (node (ref "LED4") (pin "1") (pinfunction "R_1") (pintype "bidirectional"))
      (node (ref "R148") (pin "2") (pinfunction "2_2") (pintype "passive"))
    )
    (net (code "433") (name "Net-(LED6-B)") (class "Default")
      (node (ref "LED6") (pin "4") (pinfunction "B_4") (pintype "bidirectional"))
      (node (ref "R49") (pin "2") (pinfunction "2_2") (pintype "passive"))
    )
    (net (code "434") (name "Net-(LED6-G)") (class "Default")
      (node (ref "LED6") (pin "3") (pinfunction "G_3") (pintype "bidirectional"))
      (node (ref "R48") (pin "2") (pinfunction "2_2") (pintype "passive"))
    )
    (net (code "435") (name "Net-(LED6-R)") (class "Default")
      (node (ref "LED6") (pin "1") (pinfunction "R_1") (pintype "bidirectional"))
      (node (ref "R50") (pin "2") (pinfunction "2_2") (pintype "passive"))
    )
    (net (code "436") (name "Net-(LED7-B)") (class "Default")
      (node (ref "LED7") (pin "4") (pinfunction "B_4") (pintype "bidirectional"))
      (node (ref "R174") (pin "2") (pinfunction "2_2") (pintype "passive"))
    )
    (net (code "437") (name "Net-(LED7-G)") (class "Default")
      (node (ref "LED7") (pin "3") (pinfunction "G_3") (pintype "bidirectional"))
      (node (ref "R167") (pin "2") (pinfunction "2_2") (pintype "passive"))
    )
    (net (code "438") (name "Net-(LED7-R)") (class "Default")
      (node (ref "LED7") (pin "1") (pinfunction "R_1") (pintype "bidirectional"))
      (node (ref "R175") (pin "2") (pinfunction "2_2") (pintype "passive"))
    )
    (net (code "439") (name "Net-(LED22-B)") (class "Default")
      (node (ref "LED22") (pin "4") (pinfunction "B_4") (pintype "bidirectional"))
      (node (ref "R36") (pin "2") (pinfunction "2_2") (pintype "passive"))
    )
    (net (code "440") (name "Net-(LED22-G)") (class "Default")
      (node (ref "LED22") (pin "3") (pinfunction "G_3") (pintype "bidirectional"))
      (node (ref "R35") (pin "2") (pinfunction "2_2") (pintype "passive"))
    )
    (net (code "441") (name "Net-(LED22-R)") (class "Default")
      (node (ref "LED22") (pin "1") (pinfunction "R_1") (pintype "bidirectional"))
      (node (ref "R37") (pin "2") (pinfunction "2_2") (pintype "passive"))
    )
    (net (code "442") (name "Net-(LED_3V3-PadA)") (class "Default")
      (node (ref "LED_3V3") (pin "A") (pinfunction "A_A") (pintype "passive"))
      (node (ref "R95") (pin "2") (pinfunction "2_2") (pintype "passive"))
    )
    (net (code "443") (name "Net-(LED_5V-PadA)") (class "Default")
      (node (ref "LED_5V") (pin "A") (pinfunction "A_A") (pintype "passive"))
      (node (ref "R92") (pin "2") (pinfunction "2_2") (pintype "passive"))
    )
    (net (code "444") (name "Net-(LED_42-B)") (class "Default")
      (node (ref "LED_42") (pin "4") (pinfunction "B_4") (pintype "bidirectional"))
      (node (ref "R123") (pin "2") (pinfunction "2_2") (pintype "passive"))
    )
    (net (code "445") (name "Net-(LED_42-G)") (class "Default")
      (node (ref "LED_42") (pin "3") (pinfunction "G_3") (pintype "bidirectional"))
      (node (ref "R32") (pin "2") (pinfunction "2_2") (pintype "passive"))
    )
    (net (code "446") (name "Net-(LED_42-R)") (class "Default")
      (node (ref "LED_42") (pin "1") (pinfunction "R_1") (pintype "bidirectional"))
      (node (ref "R124") (pin "2") (pinfunction "2_2") (pintype "passive"))
    )
    (net (code "447") (name "Net-(LED_43-B)") (class "Default")
      (node (ref "LED_43") (pin "4") (pinfunction "B_4") (pintype "bidirectional"))
      (node (ref "R180") (pin "2") (pinfunction "2_2") (pintype "passive"))
    )
    (net (code "448") (name "Net-(LED_43-G)") (class "Default")
      (node (ref "LED_43") (pin "3") (pinfunction "G_3") (pintype "bidirectional"))
      (node (ref "R176") (pin "2") (pinfunction "2_2") (pintype "passive"))
    )
    (net (code "449") (name "Net-(LED_43-R)") (class "Default")
      (node (ref "LED_43") (pin "1") (pinfunction "R_1") (pintype "bidirectional"))
      (node (ref "R181") (pin "2") (pinfunction "2_2") (pintype "passive"))
    )
    (net (code "450") (name "Net-(LED_46-B)") (class "Default")
      (node (ref "LED_46") (pin "4") (pinfunction "B_4") (pintype "bidirectional"))
      (node (ref "R192") (pin "2") (pinfunction "2_2") (pintype "passive"))
    )
    (net (code "451") (name "Net-(LED_46-G)") (class "Default")
      (node (ref "LED_46") (pin "3") (pinfunction "G_3") (pintype "bidirectional"))
      (node (ref "R188") (pin "2") (pinfunction "2_2") (pintype "passive"))
    )
    (net (code "452") (name "Net-(LED_46-R)") (class "Default")
      (node (ref "LED_46") (pin "1") (pinfunction "R_1") (pintype "bidirectional"))
      (node (ref "R193") (pin "2") (pinfunction "2_2") (pintype "passive"))
    )
    (net (code "453") (name "Net-(LED_47-B)") (class "Default")
      (node (ref "LED_47") (pin "4") (pinfunction "B_4") (pintype "bidirectional"))
      (node (ref "R201") (pin "2") (pinfunction "2_2") (pintype "passive"))
    )
    (net (code "454") (name "Net-(LED_47-G)") (class "Default")
      (node (ref "LED_47") (pin "3") (pinfunction "G_3") (pintype "bidirectional"))
      (node (ref "R200") (pin "2") (pinfunction "2_2") (pintype "passive"))
    )
    (net (code "455") (name "Net-(LED_47-R)") (class "Default")
      (node (ref "LED_47") (pin "1") (pinfunction "R_1") (pintype "bidirectional"))
      (node (ref "R202") (pin "2") (pinfunction "2_2") (pintype "passive"))
    )
    (net (code "456") (name "Net-(PIXEL_01-OUT0)") (class "Default")
      (node (ref "PIXEL_01") (pin "1") (pinfunction "OUT0_1") (pintype "bidirectional"))
      (node (ref "R183") (pin "1") (pinfunction "1_1") (pintype "passive"))
    )
    (net (code "457") (name "Net-(PIXEL_01-OUT1)") (class "Default")
      (node (ref "PIXEL_01") (pin "2") (pinfunction "OUT1_2") (pintype "bidirectional"))
      (node (ref "R184") (pin "1") (pinfunction "1_1") (pintype "passive"))
    )
    (net (code "458") (name "Net-(PIXEL_01-OUT2)") (class "Default")
      (node (ref "PIXEL_01") (pin "3") (pinfunction "OUT2_3") (pintype "bidirectional"))
      (node (ref "R185") (pin "1") (pinfunction "1_1") (pintype "passive"))
    )
    (net (code "459") (name "Net-(PIXEL_02-OUT0)") (class "Default")
      (node (ref "PIXEL_02") (pin "1") (pinfunction "OUT0_1") (pintype "bidirectional"))
      (node (ref "R189") (pin "1") (pinfunction "1_1") (pintype "passive"))
    )
    (net (code "460") (name "Net-(PIXEL_02-OUT1)") (class "Default")
      (node (ref "PIXEL_02") (pin "2") (pinfunction "OUT1_2") (pintype "bidirectional"))
      (node (ref "R190") (pin "1") (pinfunction "1_1") (pintype "passive"))
    )
    (net (code "461") (name "Net-(PIXEL_02-OUT2)") (class "Default")
      (node (ref "PIXEL_02") (pin "3") (pinfunction "OUT2_3") (pintype "bidirectional"))
      (node (ref "R191") (pin "1") (pinfunction "1_1") (pintype "passive"))
    )
    (net (code "462") (name "Net-(PIXEL_03-OUT0)") (class "Default")
      (node (ref "PIXEL_03") (pin "1") (pinfunction "OUT0_1") (pintype "bidirectional"))
      (node (ref "R195") (pin "1") (pinfunction "1_1") (pintype "passive"))
    )
    (net (code "463") (name "Net-(PIXEL_03-OUT1)") (class "Default")
      (node (ref "PIXEL_03") (pin "2") (pinfunction "OUT1_2") (pintype "bidirectional"))
      (node (ref "R196") (pin "1") (pinfunction "1_1") (pintype "passive"))
    )
    (net (code "464") (name "Net-(PIXEL_03-OUT2)") (class "Default")
      (node (ref "PIXEL_03") (pin "3") (pinfunction "OUT2_3") (pintype "bidirectional"))
      (node (ref "R197") (pin "1") (pinfunction "1_1") (pintype "passive"))
    )
    (net (code "465") (name "Net-(PIXEL_11-OUT0)") (class "Default")
      (node (ref "PIXEL_11") (pin "1") (pinfunction "OUT0_1") (pintype "bidirectional"))
      (node (ref "R10") (pin "1") (pinfunction "1_1") (pintype "passive"))
    )
    (net (code "466") (name "Net-(PIXEL_11-OUT1)") (class "Default")
      (node (ref "PIXEL_11") (pin "2") (pinfunction "OUT1_2") (pintype "bidirectional"))
      (node (ref "R11") (pin "1") (pinfunction "1_1") (pintype "passive"))
    )
    (net (code "467") (name "Net-(PIXEL_11-OUT2)") (class "Default")
      (node (ref "PIXEL_11") (pin "3") (pinfunction "OUT2_3") (pintype "bidirectional"))
      (node (ref "R12") (pin "1") (pinfunction "1_1") (pintype "passive"))
    )
    (net (code "468") (name "Net-(PIXEL_12-OUT0)") (class "Default")
      (node (ref "PIXEL_12") (pin "1") (pinfunction "OUT0_1") (pintype "bidirectional"))
      (node (ref "R8") (pin "1") (pinfunction "1_1") (pintype "passive"))
    )
    (net (code "469") (name "Net-(PIXEL_12-OUT1)") (class "Default")
      (node (ref "PIXEL_12") (pin "2") (pinfunction "OUT1_2") (pintype "bidirectional"))
      (node (ref "R9") (pin "1") (pinfunction "1_1") (pintype "passive"))
    )
    (net (code "470") (name "Net-(PIXEL_12-OUT2)") (class "Default")
      (node (ref "PIXEL_12") (pin "3") (pinfunction "OUT2_3") (pintype "bidirectional"))
      (node (ref "R31") (pin "1") (pinfunction "1_1") (pintype "passive"))
    )
    (net (code "471") (name "Net-(PIXEL_13-OUT0)") (class "Default")
      (node (ref "PIXEL_13") (pin "1") (pinfunction "OUT0_1") (pintype "bidirectional"))
      (node (ref "R17") (pin "1") (pinfunction "1_1") (pintype "passive"))
    )
    (net (code "472") (name "Net-(PIXEL_13-OUT1)") (class "Default")
      (node (ref "PIXEL_13") (pin "2") (pinfunction "OUT1_2") (pintype "bidirectional"))
      (node (ref "R18") (pin "1") (pinfunction "1_1") (pintype "passive"))
    )
    (net (code "473") (name "Net-(PIXEL_13-OUT2)") (class "Default")
      (node (ref "PIXEL_13") (pin "3") (pinfunction "OUT2_3") (pintype "bidirectional"))
      (node (ref "R19") (pin "1") (pinfunction "1_1") (pintype "passive"))
    )
    (net (code "474") (name "Net-(PIXEL_14-OUT0)") (class "Default")
      (node (ref "PIXEL_14") (pin "1") (pinfunction "OUT0_1") (pintype "bidirectional"))
      (node (ref "R24") (pin "1") (pinfunction "1_1") (pintype "passive"))
    )
    (net (code "475") (name "Net-(PIXEL_14-OUT1)") (class "Default")
      (node (ref "PIXEL_14") (pin "2") (pinfunction "OUT1_2") (pintype "bidirectional"))
      (node (ref "R25") (pin "1") (pinfunction "1_1") (pintype "passive"))
    )
    (net (code "476") (name "Net-(PIXEL_14-OUT2)") (class "Default")
      (node (ref "PIXEL_14") (pin "3") (pinfunction "OUT2_3") (pintype "bidirectional"))
      (node (ref "R26") (pin "1") (pinfunction "1_1") (pintype "passive"))
    )
    (net (code "477") (name "Net-(PIXEL_21-OUT0)") (class "Default")
      (node (ref "PIXEL_21") (pin "1") (pinfunction "OUT0_1") (pintype "bidirectional"))
      (node (ref "R38") (pin "1") (pinfunction "1_1") (pintype "passive"))
    )
    (net (code "478") (name "Net-(PIXEL_21-OUT1)") (class "Default")
      (node (ref "PIXEL_21") (pin "2") (pinfunction "OUT1_2") (pintype "bidirectional"))
      (node (ref "R39") (pin "1") (pinfunction "1_1") (pintype "passive"))
    )
    (net (code "479") (name "Net-(PIXEL_21-OUT2)") (class "Default")
      (node (ref "PIXEL_21") (pin "3") (pinfunction "OUT2_3") (pintype "bidirectional"))
      (node (ref "R40") (pin "1") (pinfunction "1_1") (pintype "passive"))
    )
    (net (code "480") (name "Net-(PIXEL_22-OUT0)") (class "Default")
      (node (ref "PIXEL_22") (pin "1") (pinfunction "OUT0_1") (pintype "bidirectional"))
      (node (ref "R35") (pin "1") (pinfunction "1_1") (pintype "passive"))
    )
    (net (code "481") (name "Net-(PIXEL_22-OUT1)") (class "Default")
      (node (ref "PIXEL_22") (pin "2") (pinfunction "OUT1_2") (pintype "bidirectional"))
      (node (ref "R36") (pin "1") (pinfunction "1_1") (pintype "passive"))
    )
    (net (code "482") (name "Net-(PIXEL_22-OUT2)") (class "Default")
      (node (ref "PIXEL_22") (pin "3") (pinfunction "OUT2_3") (pintype "bidirectional"))
      (node (ref "R37") (pin "1") (pinfunction "1_1") (pintype "passive"))
    )
    (net (code "483") (name "Net-(PIXEL_23-OUT0)") (class "Default")
      (node (ref "PIXEL_23") (pin "1") (pinfunction "OUT0_1") (pintype "bidirectional"))
      (node (ref "R52") (pin "1") (pinfunction "1_1") (pintype "passive"))
    )
    (net (code "484") (name "Net-(PIXEL_23-OUT1)") (class "Default")
      (node (ref "PIXEL_23") (pin "2") (pinfunction "OUT1_2") (pintype "bidirectional"))
      (node (ref "R53") (pin "1") (pinfunction "1_1") (pintype "passive"))
    )
    (net (code "485") (name "Net-(PIXEL_23-OUT2)") (class "Default")
      (node (ref "PIXEL_23") (pin "3") (pinfunction "OUT2_3") (pintype "bidirectional"))
      (node (ref "R54") (pin "1") (pinfunction "1_1") (pintype "passive"))
    )
    (net (code "486") (name "Net-(PIXEL_24-OUT0)") (class "Default")
      (node (ref "PIXEL_24") (pin "1") (pinfunction "OUT0_1") (pintype "bidirectional"))
      (node (ref "R66") (pin "1") (pinfunction "1_1") (pintype "passive"))
    )
    (net (code "487") (name "Net-(PIXEL_24-OUT1)") (class "Default")
      (node (ref "PIXEL_24") (pin "2") (pinfunction "OUT1_2") (pintype "bidirectional"))
      (node (ref "R67") (pin "1") (pinfunction "1_1") (pintype "passive"))
    )
    (net (code "488") (name "Net-(PIXEL_24-OUT2)") (class "Default")
      (node (ref "PIXEL_24") (pin "3") (pinfunction "OUT2_3") (pintype "bidirectional"))
      (node (ref "R68") (pin "1") (pinfunction "1_1") (pintype "passive"))
    )
    (net (code "489") (name "Net-(PIXEL_31-OUT0)") (class "Default")
      (node (ref "PIXEL_31") (pin "1") (pinfunction "OUT0_1") (pintype "bidirectional"))
      (node (ref "R82") (pin "1") (pinfunction "1_1") (pintype "passive"))
    )
    (net (code "490") (name "Net-(PIXEL_31-OUT1)") (class "Default")
      (node (ref "PIXEL_31") (pin "2") (pinfunction "OUT1_2") (pintype "bidirectional"))
      (node (ref "R84") (pin "1") (pinfunction "1_1") (pintype "passive"))
    )
    (net (code "491") (name "Net-(PIXEL_31-OUT2)") (class "Default")
      (node (ref "PIXEL_31") (pin "3") (pinfunction "OUT2_3") (pintype "bidirectional"))
      (node (ref "R85") (pin "1") (pinfunction "1_1") (pintype "passive"))
    )
    (net (code "492") (name "Net-(PIXEL_32-OUT0)") (class "Default")
      (node (ref "PIXEL_32") (pin "1") (pinfunction "OUT0_1") (pintype "bidirectional"))
      (node (ref "R3") (pin "1") (pinfunction "1_1") (pintype "passive"))
    )
    (net (code "493") (name "Net-(PIXEL_32-OUT1)") (class "Default")
      (node (ref "PIXEL_32") (pin "2") (pinfunction "OUT1_2") (pintype "bidirectional"))
      (node (ref "R6") (pin "1") (pinfunction "1_1") (pintype "passive"))
    )
    (net (code "494") (name "Net-(PIXEL_32-OUT2)") (class "Default")
      (node (ref "PIXEL_32") (pin "3") (pinfunction "OUT2_3") (pintype "bidirectional"))
      (node (ref "R7") (pin "1") (pinfunction "1_1") (pintype "passive"))
    )
    (net (code "495") (name "Net-(PIXEL_33-OUT0)") (class "Default")
      (node (ref "PIXEL_33") (pin "1") (pinfunction "OUT0_1") (pintype "bidirectional"))
      (node (ref "R48") (pin "1") (pinfunction "1_1") (pintype "passive"))
    )
    (net (code "496") (name "Net-(PIXEL_33-OUT1)") (class "Default")
      (node (ref "PIXEL_33") (pin "2") (pinfunction "OUT1_2") (pintype "bidirectional"))
      (node (ref "R49") (pin "1") (pinfunction "1_1") (pintype "passive"))
    )
    (net (code "497") (name "Net-(PIXEL_33-OUT2)") (class "Default")
      (node (ref "PIXEL_33") (pin "3") (pinfunction "OUT2_3") (pintype "bidirectional"))
      (node (ref "R50") (pin "1") (pinfunction "1_1") (pintype "passive"))
    )
    (net (code "498") (name "Net-(PIXEL_34-OUT0)") (class "Default")
      (node (ref "PIXEL_34") (pin "1") (pinfunction "OUT0_1") (pintype "bidirectional"))
      (node (ref "R102") (pin "1") (pinfunction "1_1") (pintype "passive"))
    )
    (net (code "499") (name "Net-(PIXEL_34-OUT1)") (class "Default")
      (node (ref "PIXEL_34") (pin "2") (pinfunction "OUT1_2") (pintype "bidirectional"))
      (node (ref "R103") (pin "1") (pinfunction "1_1") (pintype "passive"))
    )
    (net (code "500") (name "Net-(PIXEL_34-OUT2)") (class "Default")
      (node (ref "PIXEL_34") (pin "3") (pinfunction "OUT2_3") (pintype "bidirectional"))
      (node (ref "R104") (pin "1") (pinfunction "1_1") (pintype "passive"))
    )
    (net (code "501") (name "Net-(PIXEL_35-OUT0)") (class "Default")
      (node (ref "PIXEL_35") (pin "1") (pinfunction "OUT0_1") (pintype "bidirectional"))
      (node (ref "R116") (pin "1") (pinfunction "1_1") (pintype "passive"))
    )
    (net (code "502") (name "Net-(PIXEL_35-OUT1)") (class "Default")
      (node (ref "PIXEL_35") (pin "2") (pinfunction "OUT1_2") (pintype "bidirectional"))
      (node (ref "R117") (pin "1") (pinfunction "1_1") (pintype "passive"))
    )
    (net (code "503") (name "Net-(PIXEL_35-OUT2)") (class "Default")
      (node (ref "PIXEL_35") (pin "3") (pinfunction "OUT2_3") (pintype "bidirectional"))
      (node (ref "R118") (pin "1") (pinfunction "1_1") (pintype "passive"))
    )
    (net (code "504") (name "Net-(PIXEL_41-OUT0)") (class "Default")
      (node (ref "PIXEL_41") (pin "1") (pinfunction "OUT0_1") (pintype "bidirectional"))
      (node (ref "R46") (pin "1") (pinfunction "1_1") (pintype "passive"))
    )
    (net (code "505") (name "Net-(PIXEL_41-OUT1)") (class "Default")
      (node (ref "PIXEL_41") (pin "2") (pinfunction "OUT1_2") (pintype "bidirectional"))
      (node (ref "R47") (pin "1") (pinfunction "1_1") (pintype "passive"))
    )
    (net (code "506") (name "Net-(PIXEL_41-OUT2)") (class "Default")
      (node (ref "PIXEL_41") (pin "3") (pinfunction "OUT2_3") (pintype "bidirectional"))
      (node (ref "R51") (pin "1") (pinfunction "1_1") (pintype "passive"))
    )
    (net (code "507") (name "Net-(PIXEL_42-OUT0)") (class "Default")
      (node (ref "PIXEL_42") (pin "1") (pinfunction "OUT0_1") (pintype "bidirectional"))
      (node (ref "R32") (pin "1") (pinfunction "1_1") (pintype "passive"))
    )
    (net (code "508") (name "Net-(PIXEL_42-OUT1)") (class "Default")
      (node (ref "PIXEL_42") (pin "2") (pinfunction "OUT1_2") (pintype "bidirectional"))
      (node (ref "R123") (pin "1") (pinfunction "1_1") (pintype "passive"))
    )
    (net (code "509") (name "Net-(PIXEL_42-OUT2)") (class "Default")
      (node (ref "PIXEL_42") (pin "3") (pinfunction "OUT2_3") (pintype "bidirectional"))
      (node (ref "R124") (pin "1") (pinfunction "1_1") (pintype "passive"))
    )
    (net (code "510") (name "Net-(PIXEL_43-OUT0)") (class "Default")
      (node (ref "PIXEL_43") (pin "1") (pinfunction "OUT0_1") (pintype "bidirectional"))
      (node (ref "R176") (pin "1") (pinfunction "1_1") (pintype "passive"))
    )
    (net (code "511") (name "Net-(PIXEL_43-OUT1)") (class "Default")
      (node (ref "PIXEL_43") (pin "2") (pinfunction "OUT1_2") (pintype "bidirectional"))
      (node (ref "R180") (pin "1") (pinfunction "1_1") (pintype "passive"))
    )
    (net (code "512") (name "Net-(PIXEL_43-OUT2)") (class "Default")
      (node (ref "PIXEL_43") (pin "3") (pinfunction "OUT2_3") (pintype "bidirectional"))
      (node (ref "R181") (pin "1") (pinfunction "1_1") (pintype "passive"))
    )
    (net (code "513") (name "Net-(PIXEL_44-OUT0)") (class "Default")
      (node (ref "PIXEL_44") (pin "1") (pinfunction "OUT0_1") (pintype "bidirectional"))
      (node (ref "R62") (pin "1") (pinfunction "1_1") (pintype "passive"))
    )
    (net (code "514") (name "Net-(PIXEL_44-OUT1)") (class "Default")
      (node (ref "PIXEL_44") (pin "2") (pinfunction "OUT1_2") (pintype "bidirectional"))
      (node (ref "R63") (pin "1") (pinfunction "1_1") (pintype "passive"))
    )
    (net (code "515") (name "Net-(PIXEL_44-OUT2)") (class "Default")
      (node (ref "PIXEL_44") (pin "3") (pinfunction "OUT2_3") (pintype "bidirectional"))
      (node (ref "R64") (pin "1") (pinfunction "1_1") (pintype "passive"))
    )
    (net (code "516") (name "Net-(PIXEL_45-OUT0)") (class "Default")
      (node (ref "PIXEL_45") (pin "1") (pinfunction "OUT0_1") (pintype "bidirectional"))
      (node (ref "R75") (pin "1") (pinfunction "1_1") (pintype "passive"))
    )
    (net (code "517") (name "Net-(PIXEL_45-OUT1)") (class "Default")
      (node (ref "PIXEL_45") (pin "2") (pinfunction "OUT1_2") (pintype "bidirectional"))
      (node (ref "R76") (pin "1") (pinfunction "1_1") (pintype "passive"))
    )
    (net (code "518") (name "Net-(PIXEL_45-OUT2)") (class "Default")
      (node (ref "PIXEL_45") (pin "3") (pinfunction "OUT2_3") (pintype "bidirectional"))
      (node (ref "R77") (pin "1") (pinfunction "1_1") (pintype "passive"))
    )
    (net (code "519") (name "Net-(PIXEL_46-OUT0)") (class "Default")
      (node (ref "PIXEL_46") (pin "1") (pinfunction "OUT0_1") (pintype "bidirectional"))
      (node (ref "R188") (pin "1") (pinfunction "1_1") (pintype "passive"))
    )
    (net (code "520") (name "Net-(PIXEL_46-OUT1)") (class "Default")
      (node (ref "PIXEL_46") (pin "2") (pinfunction "OUT1_2") (pintype "bidirectional"))
      (node (ref "R192") (pin "1") (pinfunction "1_1") (pintype "passive"))
    )
    (net (code "521") (name "Net-(PIXEL_46-OUT2)") (class "Default")
      (node (ref "PIXEL_46") (pin "3") (pinfunction "OUT2_3") (pintype "bidirectional"))
      (node (ref "R193") (pin "1") (pinfunction "1_1") (pintype "passive"))
    )
    (net (code "522") (name "Net-(PIXEL_47-OUT0)") (class "Default")
      (node (ref "PIXEL_47") (pin "1") (pinfunction "OUT0_1") (pintype "bidirectional"))
      (node (ref "R200") (pin "1") (pinfunction "1_1") (pintype "passive"))
    )
    (net (code "523") (name "Net-(PIXEL_47-OUT1)") (class "Default")
      (node (ref "PIXEL_47") (pin "2") (pinfunction "OUT1_2") (pintype "bidirectional"))
      (node (ref "R201") (pin "1") (pinfunction "1_1") (pintype "passive"))
    )
    (net (code "524") (name "Net-(PIXEL_47-OUT2)") (class "Default")
      (node (ref "PIXEL_47") (pin "3") (pinfunction "OUT2_3") (pintype "bidirectional"))
      (node (ref "R202") (pin "1") (pinfunction "1_1") (pintype "passive"))
    )
    (net (code "525") (name "Net-(PIXEL_48-OUT0)") (class "Default")
      (node (ref "PIXEL_48") (pin "1") (pinfunction "OUT0_1") (pintype "bidirectional"))
      (node (ref "R86") (pin "1") (pinfunction "1_1") (pintype "passive"))
    )
    (net (code "526") (name "Net-(PIXEL_48-OUT1)") (class "Default")
      (node (ref "PIXEL_48") (pin "2") (pinfunction "OUT1_2") (pintype "bidirectional"))
      (node (ref "R94") (pin "1") (pinfunction "1_1") (pintype "passive"))
    )
    (net (code "527") (name "Net-(PIXEL_48-OUT2)") (class "Default")
      (node (ref "PIXEL_48") (pin "3") (pinfunction "OUT2_3") (pintype "bidirectional"))
      (node (ref "R96") (pin "1") (pinfunction "1_1") (pintype "passive"))
    )
    (net (code "528") (name "Net-(PIXEL_51-OUT0)") (class "Default")
      (node (ref "PIXEL_51") (pin "1") (pinfunction "OUT0_1") (pintype "bidirectional"))
      (node (ref "R33") (pin "1") (pinfunction "1_1") (pintype "passive"))
    )
    (net (code "529") (name "Net-(PIXEL_51-OUT1)") (class "Default")
      (node (ref "PIXEL_51") (pin "2") (pinfunction "OUT1_2") (pintype "bidirectional"))
      (node (ref "R34") (pin "1") (pinfunction "1_1") (pintype "passive"))
    )
    (net (code "530") (name "Net-(PIXEL_51-OUT2)") (class "Default")
      (node (ref "PIXEL_51") (pin "3") (pinfunction "OUT2_3") (pintype "bidirectional"))
      (node (ref "R45") (pin "1") (pinfunction "1_1") (pintype "passive"))
    )
    (net (code "531") (name "Net-(PIXEL_52-OUT0)") (class "Default")
      (node (ref "PIXEL_52") (pin "1") (pinfunction "OUT0_1") (pintype "bidirectional"))
      (node (ref "R125") (pin "1") (pinfunction "1_1") (pintype "passive"))
    )
    (net (code "532") (name "Net-(PIXEL_52-OUT1)") (class "Default")
      (node (ref "PIXEL_52") (pin "2") (pinfunction "OUT1_2") (pintype "bidirectional"))
      (node (ref "R147") (pin "1") (pinfunction "1_1") (pintype "passive"))
    )
    (net (code "533") (name "Net-(PIXEL_52-OUT2)") (class "Default")
      (node (ref "PIXEL_52") (pin "3") (pinfunction "OUT2_3") (pintype "bidirectional"))
      (node (ref "R148") (pin "1") (pinfunction "1_1") (pintype "passive"))
    )
    (net (code "534") (name "Net-(PIXEL_53-OUT0)") (class "Default")
      (node (ref "PIXEL_53") (pin "1") (pinfunction "OUT0_1") (pintype "bidirectional"))
      (node (ref "R59") (pin "1") (pinfunction "1_1") (pintype "passive"))
    )
    (net (code "535") (name "Net-(PIXEL_53-OUT1)") (class "Default")
      (node (ref "PIXEL_53") (pin "2") (pinfunction "OUT1_2") (pintype "bidirectional"))
      (node (ref "R60") (pin "1") (pinfunction "1_1") (pintype "passive"))
    )
    (net (code "536") (name "Net-(PIXEL_53-OUT2)") (class "Default")
      (node (ref "PIXEL_53") (pin "3") (pinfunction "OUT2_3") (pintype "bidirectional"))
      (node (ref "R61") (pin "1") (pinfunction "1_1") (pintype "passive"))
    )
    (net (code "537") (name "Net-(PIXEL_54-OUT0)") (class "Default")
      (node (ref "PIXEL_54") (pin "1") (pinfunction "OUT0_1") (pintype "bidirectional"))
      (node (ref "R78") (pin "1") (pinfunction "1_1") (pintype "passive"))
    )
    (net (code "538") (name "Net-(PIXEL_54-OUT1)") (class "Default")
      (node (ref "PIXEL_54") (pin "2") (pinfunction "OUT1_2") (pintype "bidirectional"))
      (node (ref "R80") (pin "1") (pinfunction "1_1") (pintype "passive"))
    )
    (net (code "539") (name "Net-(PIXEL_54-OUT2)") (class "Default")
      (node (ref "PIXEL_54") (pin "3") (pinfunction "OUT2_3") (pintype "bidirectional"))
      (node (ref "R83") (pin "1") (pinfunction "1_1") (pintype "passive"))
    )
    (net (code "540") (name "Net-(PIXEL_55-OUT0)") (class "Default")
      (node (ref "PIXEL_55") (pin "1") (pinfunction "OUT0_1") (pintype "bidirectional"))
      (node (ref "R100") (pin "1") (pinfunction "1_1") (pintype "passive"))
    )
    (net (code "541") (name "Net-(PIXEL_55-OUT1)") (class "Default")
      (node (ref "PIXEL_55") (pin "2") (pinfunction "OUT1_2") (pintype "bidirectional"))
      (node (ref "R101") (pin "1") (pinfunction "1_1") (pintype "passive"))
    )
    (net (code "542") (name "Net-(PIXEL_55-OUT2)") (class "Default")
      (node (ref "PIXEL_55") (pin "3") (pinfunction "OUT2_3") (pintype "bidirectional"))
      (node (ref "R109") (pin "1") (pinfunction "1_1") (pintype "passive"))
    )
    (net (code "543") (name "Net-(PIXEL_56-OUT0)") (class "Default")
      (node (ref "PIXEL_56") (pin "1") (pinfunction "OUT0_1") (pintype "bidirectional"))
      (node (ref "R113") (pin "1") (pinfunction "1_1") (pintype "passive"))
    )
    (net (code "544") (name "Net-(PIXEL_56-OUT1)") (class "Default")
      (node (ref "PIXEL_56") (pin "2") (pinfunction "OUT1_2") (pintype "bidirectional"))
      (node (ref "R114") (pin "1") (pinfunction "1_1") (pintype "passive"))
    )
    (net (code "545") (name "Net-(PIXEL_56-OUT2)") (class "Default")
      (node (ref "PIXEL_56") (pin "3") (pinfunction "OUT2_3") (pintype "bidirectional"))
      (node (ref "R115") (pin "1") (pinfunction "1_1") (pintype "passive"))
    )
    (net (code "546") (name "Net-(PIXEL_57-OUT0)") (class "Default")
      (node (ref "PIXEL_57") (pin "1") (pinfunction "OUT0_1") (pintype "bidirectional"))
      (node (ref "R126") (pin "1") (pinfunction "1_1") (pintype "passive"))
    )
    (net (code "547") (name "Net-(PIXEL_57-OUT1)") (class "Default")
      (node (ref "PIXEL_57") (pin "2") (pinfunction "OUT1_2") (pintype "bidirectional"))
      (node (ref "R127") (pin "1") (pinfunction "1_1") (pintype "passive"))
    )
    (net (code "548") (name "Net-(PIXEL_57-OUT2)") (class "Default")
      (node (ref "PIXEL_57") (pin "3") (pinfunction "OUT2_3") (pintype "bidirectional"))
      (node (ref "R128") (pin "1") (pinfunction "1_1") (pintype "passive"))
    )
    (net (code "549") (name "Net-(PIXEL_61-OUT0)") (class "Default")
      (node (ref "PIXEL_61") (pin "1") (pinfunction "OUT0_1") (pintype "bidirectional"))
      (node (ref "R132") (pin "1") (pinfunction "1_1") (pintype "passive"))
    )
    (net (code "550") (name "Net-(PIXEL_61-OUT1)") (class "Default")
      (node (ref "PIXEL_61") (pin "2") (pinfunction "OUT1_2") (pintype "bidirectional"))
      (node (ref "R133") (pin "1") (pinfunction "1_1") (pintype "passive"))
    )
    (net (code "551") (name "Net-(PIXEL_61-OUT2)") (class "Default")
      (node (ref "PIXEL_61") (pin "3") (pinfunction "OUT2_3") (pintype "bidirectional"))
      (node (ref "R134") (pin "1") (pinfunction "1_1") (pintype "passive"))
    )
    (net (code "552") (name "Net-(PIXEL_62-OUT0)") (class "Default")
      (node (ref "PIXEL_62") (pin "1") (pinfunction "OUT0_1") (pintype "bidirectional"))
      (node (ref "R138") (pin "1") (pinfunction "1_1") (pintype "passive"))
    )
    (net (code "553") (name "Net-(PIXEL_62-OUT1)") (class "Default")
      (node (ref "PIXEL_62") (pin "2") (pinfunction "OUT1_2") (pintype "bidirectional"))
      (node (ref "R139") (pin "1") (pinfunction "1_1") (pintype "passive"))
    )
    (net (code "554") (name "Net-(PIXEL_62-OUT2)") (class "Default")
      (node (ref "PIXEL_62") (pin "3") (pinfunction "OUT2_3") (pintype "bidirectional"))
      (node (ref "R140") (pin "1") (pinfunction "1_1") (pintype "passive"))
    )
    (net (code "555") (name "Net-(PIXEL_63-OUT0)") (class "Default")
      (node (ref "PIXEL_63") (pin "1") (pinfunction "OUT0_1") (pintype "bidirectional"))
      (node (ref "R144") (pin "1") (pinfunction "1_1") (pintype "passive"))
    )
    (net (code "556") (name "Net-(PIXEL_63-OUT1)") (class "Default")
      (node (ref "PIXEL_63") (pin "2") (pinfunction "OUT1_2") (pintype "bidirectional"))
      (node (ref "R145") (pin "1") (pinfunction "1_1") (pintype "passive"))
    )
    (net (code "557") (name "Net-(PIXEL_63-OUT2)") (class "Default")
      (node (ref "PIXEL_63") (pin "3") (pinfunction "OUT2_3") (pintype "bidirectional"))
      (node (ref "R146") (pin "1") (pinfunction "1_1") (pintype "passive"))
    )
    (net (code "558") (name "Net-(PIXEL_64-OUT0)") (class "Default")
      (node (ref "PIXEL_64") (pin "1") (pinfunction "OUT0_1") (pintype "bidirectional"))
      (node (ref "R150") (pin "1") (pinfunction "1_1") (pintype "passive"))
    )
    (net (code "559") (name "Net-(PIXEL_64-OUT1)") (class "Default")
      (node (ref "PIXEL_64") (pin "2") (pinfunction "OUT1_2") (pintype "bidirectional"))
      (node (ref "R151") (pin "1") (pinfunction "1_1") (pintype "passive"))
    )
    (net (code "560") (name "Net-(PIXEL_64-OUT2)") (class "Default")
      (node (ref "PIXEL_64") (pin "3") (pinfunction "OUT2_3") (pintype "bidirectional"))
      (node (ref "R152") (pin "1") (pinfunction "1_1") (pintype "passive"))
    )
    (net (code "561") (name "Net-(PIXEL_65-OUT0)") (class "Default")
      (node (ref "PIXEL_65") (pin "1") (pinfunction "OUT0_1") (pintype "bidirectional"))
      (node (ref "R167") (pin "1") (pinfunction "1_1") (pintype "passive"))
    )
    (net (code "562") (name "Net-(PIXEL_65-OUT1)") (class "Default")
      (node (ref "PIXEL_65") (pin "2") (pinfunction "OUT1_2") (pintype "bidirectional"))
      (node (ref "R174") (pin "1") (pinfunction "1_1") (pintype "passive"))
    )
    (net (code "563") (name "Net-(PIXEL_65-OUT2)") (class "Default")
      (node (ref "PIXEL_65") (pin "3") (pinfunction "OUT2_3") (pintype "bidirectional"))
      (node (ref "R175") (pin "1") (pinfunction "1_1") (pintype "passive"))
    )
    (net (code "564") (name "Net-(PIXEL_71-OUT0)") (class "Default")
      (node (ref "PIXEL_71") (pin "1") (pinfunction "OUT0_1") (pintype "bidirectional"))
      (node (ref "R97") (pin "1") (pinfunction "1_1") (pintype "passive"))
    )
    (net (code "565") (name "Net-(PIXEL_71-OUT1)") (class "Default")
      (node (ref "PIXEL_71") (pin "2") (pinfunction "OUT1_2") (pintype "bidirectional"))
      (node (ref "R98") (pin "1") (pinfunction "1_1") (pintype "passive"))
    )
    (net (code "566") (name "Net-(PIXEL_71-OUT2)") (class "Default")
      (node (ref "PIXEL_71") (pin "3") (pinfunction "OUT2_3") (pintype "bidirectional"))
      (node (ref "R99") (pin "1") (pinfunction "1_1") (pintype "passive"))
    )
    (net (code "567") (name "Net-(PIXEL_72-OUT0)") (class "Default")
      (node (ref "PIXEL_72") (pin "1") (pinfunction "OUT0_1") (pintype "bidirectional"))
      (node (ref "R135") (pin "1") (pinfunction "1_1") (pintype "passive"))
    )
    (net (code "568") (name "Net-(PIXEL_72-OUT1)") (class "Default")
      (node (ref "PIXEL_72") (pin "2") (pinfunction "OUT1_2") (pintype "bidirectional"))
      (node (ref "R136") (pin "1") (pinfunction "1_1") (pintype "passive"))
    )
    (net (code "569") (name "Net-(PIXEL_72-OUT2)") (class "Default")
      (node (ref "PIXEL_72") (pin "3") (pinfunction "OUT2_3") (pintype "bidirectional"))
      (node (ref "R137") (pin "1") (pinfunction "1_1") (pintype "passive"))
    )
    (net (code "570") (name "Net-(PIXEL_73-OUT0)") (class "Default")
      (node (ref "PIXEL_73") (pin "1") (pinfunction "OUT0_1") (pintype "bidirectional"))
      (node (ref "R159") (pin "1") (pinfunction "1_1") (pintype "passive"))
    )
    (net (code "571") (name "Net-(PIXEL_73-OUT1)") (class "Default")
      (node (ref "PIXEL_73") (pin "2") (pinfunction "OUT1_2") (pintype "bidirectional"))
      (node (ref "R160") (pin "1") (pinfunction "1_1") (pintype "passive"))
    )
    (net (code "572") (name "Net-(PIXEL_73-OUT2)") (class "Default")
      (node (ref "PIXEL_73") (pin "3") (pinfunction "OUT2_3") (pintype "bidirectional"))
      (node (ref "R161") (pin "1") (pinfunction "1_1") (pintype "passive"))
    )
    (net (code "573") (name "Net-(PIXEL_74-OUT0)") (class "Default")
      (node (ref "PIXEL_74") (pin "1") (pinfunction "OUT0_1") (pintype "bidirectional"))
      (node (ref "R171") (pin "1") (pinfunction "1_1") (pintype "passive"))
    )
    (net (code "574") (name "Net-(PIXEL_74-OUT1)") (class "Default")
      (node (ref "PIXEL_74") (pin "2") (pinfunction "OUT1_2") (pintype "bidirectional"))
      (node (ref "R172") (pin "1") (pinfunction "1_1") (pintype "passive"))
    )
    (net (code "575") (name "Net-(PIXEL_74-OUT2)") (class "Default")
      (node (ref "PIXEL_74") (pin "3") (pinfunction "OUT2_3") (pintype "bidirectional"))
      (node (ref "R173") (pin "1") (pinfunction "1_1") (pintype "passive"))
    )
    (net (code "576") (name "Net-(PIXEL_75-OUT0)") (class "Default")
      (node (ref "PIXEL_75") (pin "1") (pinfunction "OUT0_1") (pintype "bidirectional"))
      (node (ref "R177") (pin "1") (pinfunction "1_1") (pintype "passive"))
    )
    (net (code "577") (name "Net-(PIXEL_75-OUT1)") (class "Default")
      (node (ref "PIXEL_75") (pin "2") (pinfunction "OUT1_2") (pintype "bidirectional"))
      (node (ref "R178") (pin "1") (pinfunction "1_1") (pintype "passive"))
    )
    (net (code "578") (name "Net-(PIXEL_75-OUT2)") (class "Default")
      (node (ref "PIXEL_75") (pin "3") (pinfunction "OUT2_3") (pintype "bidirectional"))
      (node (ref "R179") (pin "1") (pinfunction "1_1") (pintype "passive"))
    )
    (net (code "579") (name "Net-(PIXEL_81-OUT0)") (class "Default")
      (node (ref "PIXEL_81") (pin "1") (pinfunction "OUT0_1") (pintype "bidirectional"))
      (node (ref "R156") (pin "1") (pinfunction "1_1") (pintype "passive"))
    )
    (net (code "580") (name "Net-(PIXEL_81-OUT1)") (class "Default")
      (node (ref "PIXEL_81") (pin "2") (pinfunction "OUT1_2") (pintype "bidirectional"))
      (node (ref "R157") (pin "1") (pinfunction "1_1") (pintype "passive"))
    )
    (net (code "581") (name "Net-(PIXEL_81-OUT2)") (class "Default")
      (node (ref "PIXEL_81") (pin "3") (pinfunction "OUT2_3") (pintype "bidirectional"))
      (node (ref "R158") (pin "1") (pinfunction "1_1") (pintype "passive"))
    )
    (net (code "582") (name "Net-(PIXEL_83-OUT0)") (class "Default")
      (node (ref "PIXEL_83") (pin "1") (pinfunction "OUT0_1") (pintype "bidirectional"))
      (node (ref "R110") (pin "1") (pinfunction "1_1") (pintype "passive"))
    )
    (net (code "583") (name "Net-(PIXEL_83-OUT1)") (class "Default")
      (node (ref "PIXEL_83") (pin "2") (pinfunction "OUT1_2") (pintype "bidirectional"))
      (node (ref "R111") (pin "1") (pinfunction "1_1") (pintype "passive"))
    )
    (net (code "584") (name "Net-(PIXEL_83-OUT2)") (class "Default")
      (node (ref "PIXEL_83") (pin "3") (pinfunction "OUT2_3") (pintype "bidirectional"))
      (node (ref "R112") (pin "1") (pinfunction "1_1") (pintype "passive"))
    )
    (net (code "585") (name "Net-(PIXEL_84-OUT0)") (class "Default")
      (node (ref "PIXEL_84") (pin "1") (pinfunction "OUT0_1") (pintype "bidirectional"))
      (node (ref "R129") (pin "1") (pinfunction "1_1") (pintype "passive"))
    )
    (net (code "586") (name "Net-(PIXEL_84-OUT1)") (class "Default")
      (node (ref "PIXEL_84") (pin "2") (pinfunction "OUT1_2") (pintype "bidirectional"))
      (node (ref "R130") (pin "1") (pinfunction "1_1") (pintype "passive"))
    )
    (net (code "587") (name "Net-(PIXEL_84-OUT2)") (class "Default")
      (node (ref "PIXEL_84") (pin "3") (pinfunction "OUT2_3") (pintype "bidirectional"))
      (node (ref "R131") (pin "1") (pinfunction "1_1") (pintype "passive"))
    )
    (net (code "588") (name "Net-(PIXEL_85-OUT0)") (class "Default")
      (node (ref "PIXEL_85") (pin "1") (pinfunction "OUT0_1") (pintype "bidirectional"))
      (node (ref "R141") (pin "1") (pinfunction "1_1") (pintype "passive"))
    )
    (net (code "589") (name "Net-(PIXEL_85-OUT1)") (class "Default")
      (node (ref "PIXEL_85") (pin "2") (pinfunction "OUT1_2") (pintype "bidirectional"))
      (node (ref "R142") (pin "1") (pinfunction "1_1") (pintype "passive"))
    )
    (net (code "590") (name "Net-(PIXEL_85-OUT2)") (class "Default")
      (node (ref "PIXEL_85") (pin "3") (pinfunction "OUT2_3") (pintype "bidirectional"))
      (node (ref "R143") (pin "1") (pinfunction "1_1") (pintype "passive"))
    )
    (net (code "591") (name "Net-(PIXEL_86-OUT0)") (class "Default")
      (node (ref "PIXEL_86") (pin "1") (pinfunction "OUT0_1") (pintype "bidirectional"))
      (node (ref "R153") (pin "1") (pinfunction "1_1") (pintype "passive"))
    )
    (net (code "592") (name "Net-(PIXEL_86-OUT1)") (class "Default")
      (node (ref "PIXEL_86") (pin "2") (pinfunction "OUT1_2") (pintype "bidirectional"))
      (node (ref "R154") (pin "1") (pinfunction "1_1") (pintype "passive"))
    )
    (net (code "593") (name "Net-(PIXEL_86-OUT2)") (class "Default")
      (node (ref "PIXEL_86") (pin "3") (pinfunction "OUT2_3") (pintype "bidirectional"))
      (node (ref "R155") (pin "1") (pinfunction "1_1") (pintype "passive"))
    )
    (net (code "594") (name "Net-(PIXEL_87-OUT0)") (class "Default")
      (node (ref "PIXEL_87") (pin "1") (pinfunction "OUT0_1") (pintype "bidirectional"))
      (node (ref "R162") (pin "1") (pinfunction "1_1") (pintype "passive"))
    )
    (net (code "595") (name "Net-(PIXEL_87-OUT1)") (class "Default")
      (node (ref "PIXEL_87") (pin "2") (pinfunction "OUT1_2") (pintype "bidirectional"))
      (node (ref "R163") (pin "1") (pinfunction "1_1") (pintype "passive"))
    )
    (net (code "596") (name "Net-(PIXEL_87-OUT2)") (class "Default")
      (node (ref "PIXEL_87") (pin "3") (pinfunction "OUT2_3") (pintype "bidirectional"))
      (node (ref "R164") (pin "1") (pinfunction "1_1") (pintype "passive"))
    )
    (net (code "597") (name "Net-(PIXEL_88-OUT0)") (class "Default")
      (node (ref "PIXEL_88") (pin "1") (pinfunction "OUT0_1") (pintype "bidirectional"))
      (node (ref "R168") (pin "1") (pinfunction "1_1") (pintype "passive"))
    )
    (net (code "598") (name "Net-(PIXEL_88-OUT1)") (class "Default")
      (node (ref "PIXEL_88") (pin "2") (pinfunction "OUT1_2") (pintype "bidirectional"))
      (node (ref "R169") (pin "1") (pinfunction "1_1") (pintype "passive"))
    )
    (net (code "599") (name "Net-(PIXEL_88-OUT2)") (class "Default")
      (node (ref "PIXEL_88") (pin "3") (pinfunction "OUT2_3") (pintype "bidirectional"))
      (node (ref "R170") (pin "1") (pinfunction "1_1") (pintype "passive"))
    )
    (net (code "600") (name "Net-(PIXE_82-OUT0)") (class "Default")
      (node (ref "PIXE_82") (pin "1") (pinfunction "OUT0_1") (pintype "bidirectional"))
      (node (ref "R65") (pin "1") (pinfunction "1_1") (pintype "passive"))
    )
    (net (code "601") (name "Net-(PIXE_82-OUT1)") (class "Default")
      (node (ref "PIXE_82") (pin "2") (pinfunction "OUT1_2") (pintype "bidirectional"))
      (node (ref "R73") (pin "1") (pinfunction "1_1") (pintype "passive"))
    )
    (net (code "602") (name "Net-(PIXE_82-OUT2)") (class "Default")
      (node (ref "PIXE_82") (pin "3") (pinfunction "OUT2_3") (pintype "bidirectional"))
      (node (ref "R74") (pin "1") (pinfunction "1_1") (pintype "passive"))
    )
    (net (code "603") (name "Net-(S24--B)") (class "Default")
      (node (ref "R68") (pin "2") (pinfunction "2_2") (pintype "passive"))
      (node (ref "S24") (pin "4") (pinfunction "-B_4") (pintype "passive"))
    )
    (net (code "604") (name "Net-(S24--G)") (class "Default")
      (node (ref "R67") (pin "2") (pinfunction "2_2") (pintype "passive"))
      (node (ref "S24") (pin "2") (pinfunction "-G_2") (pintype "passive"))
    )
    (net (code "605") (name "Net-(S24--R)") (class "Default")
      (node (ref "R66") (pin "2") (pinfunction "2_2") (pintype "passive"))
      (node (ref "S24") (pin "1") (pinfunction "-R_1") (pintype "passive"))
    )
    (net (code "606") (name "Net-(S31--B)") (class "Default")
      (node (ref "R85") (pin "2") (pinfunction "2_2") (pintype "passive"))
      (node (ref "S31") (pin "4") (pinfunction "-B_4") (pintype "passive"))
    )
    (net (code "607") (name "Net-(S31--G)") (class "Default")
      (node (ref "R84") (pin "2") (pinfunction "2_2") (pintype "passive"))
      (node (ref "S31") (pin "2") (pinfunction "-G_2") (pintype "passive"))
    )
    (net (code "608") (name "Net-(S31--R)") (class "Default")
      (node (ref "R82") (pin "2") (pinfunction "2_2") (pintype "passive"))
      (node (ref "S31") (pin "1") (pinfunction "-R_1") (pintype "passive"))
    )
    (net (code "609") (name "Net-(S34--B)") (class "Default")
      (node (ref "R104") (pin "2") (pinfunction "2_2") (pintype "passive"))
      (node (ref "S34") (pin "4") (pinfunction "-B_4") (pintype "passive"))
    )
    (net (code "610") (name "Net-(S34--G)") (class "Default")
      (node (ref "R103") (pin "2") (pinfunction "2_2") (pintype "passive"))
      (node (ref "S34") (pin "2") (pinfunction "-G_2") (pintype "passive"))
    )
    (net (code "611") (name "Net-(S34--R)") (class "Default")
      (node (ref "R102") (pin "2") (pinfunction "2_2") (pintype "passive"))
      (node (ref "S34") (pin "1") (pinfunction "-R_1") (pintype "passive"))
    )
    (net (code "612") (name "Net-(S35--B)") (class "Default")
      (node (ref "R118") (pin "2") (pinfunction "2_2") (pintype "passive"))
      (node (ref "S35") (pin "4") (pinfunction "-B_4") (pintype "passive"))
    )
    (net (code "613") (name "Net-(S35--G)") (class "Default")
      (node (ref "R117") (pin "2") (pinfunction "2_2") (pintype "passive"))
      (node (ref "S35") (pin "2") (pinfunction "-G_2") (pintype "passive"))
    )
    (net (code "614") (name "Net-(S35--R)") (class "Default")
      (node (ref "R116") (pin "2") (pinfunction "2_2") (pintype "passive"))
      (node (ref "S35") (pin "1") (pinfunction "-R_1") (pintype "passive"))
    )
    (net (code "615") (name "Net-(TLV75533-OUT)") (class "Default")
      (node (ref "R87") (pin "2") (pinfunction "2_2") (pintype "passive"))
      (node (ref "TLV75533") (pin "5") (pinfunction "OUT_5") (pintype "output"))
    )
    (net (code "616") (name "PIXEL41") (class "Default")
      (node (ref "PIXEL_41") (pin "5") (pinfunction "SDO_5") (pintype "bidirectional"))
      (node (ref "PIXEL_43") (pin "6") (pinfunction "SDI_6") (pintype "bidirectional"))
    )
    (net (code "617") (name "PIXEL42") (class "Default")
      (node (ref "PIXEL_14") (pin "6") (pinfunction "SDI_6") (pintype "bidirectional"))
      (node (ref "PIXEL_42") (pin "5") (pinfunction "SDO_5") (pintype "bidirectional"))
    )
    (net (code "618") (name "PIXEL43") (class "Default")
      (node (ref "PIXEL_43") (pin "5") (pinfunction "SDO_5") (pintype "bidirectional"))
      (node (ref "PIXEL_44") (pin "6") (pinfunction "SDI_6") (pintype "bidirectional"))
    )
    (net (code "619") (name "PIXEL44") (class "Default")
      (node (ref "PIXEL_42") (pin "6") (pinfunction "SDI_6") (pintype "bidirectional"))
      (node (ref "PIXEL_44") (pin "5") (pinfunction "SDO_5") (pintype "bidirectional"))
    )
    (net (code "620") (name "PIXEL_02") (class "Default")
      (node (ref "PIXEL_01") (pin "6") (pinfunction "SDI_6") (pintype "bidirectional"))
      (node (ref "PIXEL_02") (pin "5") (pinfunction "SDO_5") (pintype "bidirectional"))
    )
    (net (code "621") (name "PIXEL_03") (class "Default")
      (node (ref "PIXEL_02") (pin "6") (pinfunction "SDI_6") (pintype "bidirectional"))
      (node (ref "PIXEL_03") (pin "5") (pinfunction "SDO_5") (pintype "bidirectional"))
    )
    (net (code "622") (name "PIXEL_45") (class "Default")
      (node (ref "PIXEL_45") (pin "5") (pinfunction "SDO_5") (pintype "bidirectional"))
      (node (ref "PIXEL_46") (pin "6") (pinfunction "SDI_6") (pintype "bidirectional"))
    )
    (net (code "623") (name "PIXEL_46") (class "Default")
      (node (ref "PIXEL_46") (pin "5") (pinfunction "SDO_5") (pintype "bidirectional"))
      (node (ref "PIXEL_48") (pin "6") (pinfunction "SDI_6") (pintype "bidirectional"))
    )
    (net (code "624") (name "PIXEL_47") (class "Default")
      (node (ref "PIXEL_45") (pin "6") (pinfunction "SDI_6") (pintype "bidirectional"))
      (node (ref "PIXEL_47") (pin "5") (pinfunction "SDO_5") (pintype "bidirectional"))
    )
    (net (code "625") (name "PIXEL_48") (class "Default")
      (node (ref "PIXEL_48") (pin "5") (pinfunction "SDO_5") (pintype "bidirectional"))
      (node (ref "PIXEL_61") (pin "6") (pinfunction "SDI_6") (pintype "bidirectional"))
    )
    (net (code "626") (name "PIXEL_51") (class "Default")
      (node (ref "PIXEL_51") (pin "5") (pinfunction "SDO_5") (pintype "bidirectional"))
      (node (ref "PIXEL_52") (pin "6") (pinfunction "SDI_6") (pintype "bidirectional"))
    )
    (net (code "627") (name "PIXEL_52") (class "Default")
      (node (ref "PIXEL_52") (pin "5") (pinfunction "SDO_5") (pintype "bidirectional"))
      (node (ref "PIXEL_53") (pin "6") (pinfunction "SDI_6") (pintype "bidirectional"))
    )
    (net (code "628") (name "PIXEL_53") (class "Default")
      (node (ref "PIXEL_53") (pin "5") (pinfunction "SDO_5") (pintype "bidirectional"))
      (node (ref "PIXEL_57") (pin "6") (pinfunction "SDI_6") (pintype "bidirectional"))
    )
    (net (code "629") (name "PIXEL_54") (class "Default")
      (node (ref "PIXEL_47") (pin "6") (pinfunction "SDI_6") (pintype "bidirectional"))
      (node (ref "PIXEL_54") (pin "5") (pinfunction "SDO_5") (pintype "bidirectional"))
    )
    (net (code "630") (name "PIXEL_55") (class "Default")
      (node (ref "PIXEL_54") (pin "6") (pinfunction "SDI_6") (pintype "bidirectional"))
      (node (ref "PIXEL_55") (pin "5") (pinfunction "SDO_5") (pintype "bidirectional"))
    )
    (net (code "631") (name "PIXEL_56") (class "Default")
      (node (ref "PIXEL_55") (pin "6") (pinfunction "SDI_6") (pintype "bidirectional"))
      (node (ref "PIXEL_56") (pin "5") (pinfunction "SDO_5") (pintype "bidirectional"))
    )
    (net (code "632") (name "PIXEL_57") (class "Default")
      (node (ref "PIXEL_56") (pin "6") (pinfunction "SDI_6") (pintype "bidirectional"))
      (node (ref "PIXEL_57") (pin "5") (pinfunction "SDO_5") (pintype "bidirectional"))
    )
    (net (code "633") (name "PIXEL_61") (class "Default")
      (node (ref "PIXEL_61") (pin "5") (pinfunction "SDO_5") (pintype "bidirectional"))
      (node (ref "PIXEL_62") (pin "6") (pinfunction "SDI_6") (pintype "bidirectional"))
    )
    (net (code "634") (name "PIXEL_62") (class "Default")
      (node (ref "PIXEL_62") (pin "5") (pinfunction "SDO_5") (pintype "bidirectional"))
      (node (ref "PIXEL_63") (pin "6") (pinfunction "SDI_6") (pintype "bidirectional"))
    )
    (net (code "635") (name "PIXEL_63") (class "Default")
      (node (ref "PIXEL_63") (pin "5") (pinfunction "SDO_5") (pintype "bidirectional"))
      (node (ref "PIXEL_64") (pin "6") (pinfunction "SDI_6") (pintype "bidirectional"))
    )
    (net (code "636") (name "PIXEL_64") (class "Default")
      (node (ref "PIXEL_64") (pin "5") (pinfunction "SDO_5") (pintype "bidirectional"))
      (node (ref "PIXEL_65") (pin "6") (pinfunction "SDI_6") (pintype "bidirectional"))
    )
    (net (code "637") (name "PIXEL_71") (class "Default")
      (node (ref "PIXEL_71") (pin "5") (pinfunction "SDO_5") (pintype "bidirectional"))
      (node (ref "PIXEL_72") (pin "6") (pinfunction "SDI_6") (pintype "bidirectional"))
    )
    (net (code "638") (name "PIXEL_72") (class "Default")
      (node (ref "PIXEL_72") (pin "5") (pinfunction "SDO_5") (pintype "bidirectional"))
      (node (ref "PIXEL_73") (pin "6") (pinfunction "SDI_6") (pintype "bidirectional"))
    )
    (net (code "639") (name "PIXEL_73") (class "Default")
      (node (ref "PIXEL_73") (pin "5") (pinfunction "SDO_5") (pintype "bidirectional"))
      (node (ref "PIXEL_74") (pin "6") (pinfunction "SDI_6") (pintype "bidirectional"))
    )
    (net (code "640") (name "PIXEL_74") (class "Default")
      (node (ref "PIXEL_74") (pin "5") (pinfunction "SDO_5") (pintype "bidirectional"))
      (node (ref "PIXEL_75") (pin "6") (pinfunction "SDI_6") (pintype "bidirectional"))
    )
    (net (code "641") (name "PIXEL_75") (class "Default")
      (node (ref "PIXEL_75") (pin "5") (pinfunction "SDO_5") (pintype "bidirectional"))
      (node (ref "PIXEL_88") (pin "6") (pinfunction "SDI_6") (pintype "bidirectional"))
    )
    (net (code "642") (name "PIXEL_81") (class "Default")
      (node (ref "PIXEL_81") (pin "5") (pinfunction "SDO_5") (pintype "bidirectional"))
      (node (ref "TFT_EXT") (pin "9") (pinfunction "9_9") (pintype "passive"))
    )
    (net (code "643") (name "PIXEL_82") (class "Default")
      (node (ref "PIXEL_81") (pin "6") (pinfunction "SDI_6") (pintype "bidirectional"))
      (node (ref "PIXE_82") (pin "5") (pinfunction "SDO_5") (pintype "bidirectional"))
    )
    (net (code "644") (name "PIXEL_83") (class "Default")
      (node (ref "PIXEL_83") (pin "5") (pinfunction "SDO_5") (pintype "bidirectional"))
      (node (ref "PIXE_82") (pin "6") (pinfunction "SDI_6") (pintype "bidirectional"))
    )
    (net (code "645") (name "PIXEL_84") (class "Default")
      (node (ref "PIXEL_83") (pin "6") (pinfunction "SDI_6") (pintype "bidirectional"))
      (node (ref "PIXEL_84") (pin "5") (pinfunction "SDO_5") (pintype "bidirectional"))
    )
    (net (code "646") (name "PIXEL_85") (class "Default")
      (node (ref "PIXEL_84") (pin "6") (pinfunction "SDI_6") (pintype "bidirectional"))
      (node (ref "PIXEL_85") (pin "5") (pinfunction "SDO_5") (pintype "bidirectional"))
    )
    (net (code "647") (name "PIXEL_86") (class "Default")
      (node (ref "PIXEL_85") (pin "6") (pinfunction "SDI_6") (pintype "bidirectional"))
      (node (ref "PIXEL_86") (pin "5") (pinfunction "SDO_5") (pintype "bidirectional"))
    )
    (net (code "648") (name "PIXEL_87") (class "Default")
      (node (ref "PIXEL_86") (pin "6") (pinfunction "SDI_6") (pintype "bidirectional"))
      (node (ref "PIXEL_87") (pin "5") (pinfunction "SDO_5") (pintype "bidirectional"))
    )
    (net (code "649") (name "PIXEL_88") (class "Default")
      (node (ref "PIXEL_87") (pin "6") (pinfunction "SDI_6") (pintype "bidirectional"))
      (node (ref "PIXEL_88") (pin "5") (pinfunction "SDO_5") (pintype "bidirectional"))
    )
    (net (code "650") (name "PIXEL_IN") (class "Default")
      (node (ref "PIXEL_03") (pin "6") (pinfunction "SDI_6") (pintype "bidirectional"))
      (node (ref "TFT_EXT_2") (pin "9") (pinfunction "9_9") (pintype "passive"))
    )
    (net (code "651") (name "RST") (class "Default")
      (node (ref "CONN_STH_BRD_1") (pin "3") (pinfunction "3_3") (pintype "passive"))
      (node (ref "CONN_STH_BRD_2") (pin "3") (pinfunction "3_3") (pintype "passive"))
      (node (ref "F446") (pin "55") (pinfunction "PB3_55") (pintype "bidirectional"))
      (node (ref "MCP_000") (pin "18") (pinfunction "~{RESET}_18") (pintype "bidirectional"))
      (node (ref "MCP_001") (pin "18") (pinfunction "~{RESET}_18") (pintype "bidirectional"))
      (node (ref "MCP_010") (pin "18") (pinfunction "~{RESET}_18") (pintype "bidirectional"))
      (node (ref "MCP_011") (pin "18") (pinfunction "~{RESET}_18") (pintype "bidirectional"))
      (node (ref "MCP_100") (pin "18") (pinfunction "~{RESET}_18") (pintype "bidirectional"))
      (node (ref "MCP_101") (pin "18") (pinfunction "~{RESET}_18") (pintype "bidirectional"))
      (node (ref "MCP_110") (pin "18") (pinfunction "~{RESET}_18") (pintype "bidirectional"))
      (node (ref "MCP_111") (pin "18") (pinfunction "~{RESET}_18") (pintype "bidirectional"))
    )
    (net (code "652") (name "SPI1_MOSI") (class "Default")
      (node (ref "CONN_STH_BRD_1") (pin "6") (pinfunction "6_6") (pintype "passive"))
      (node (ref "CONN_STH_BRD_2") (pin "6") (pinfunction "6_6") (pintype "passive"))
      (node (ref "F446") (pin "23") (pinfunction "PA7_23") (pintype "bidirectional"))
      (node (ref "PIXEL_41") (pin "6") (pinfunction "SDI_6") (pintype "bidirectional"))
    )
    (net (code "653") (name "SPI2_MOSI") (class "Default")
      (node (ref "F446") (pin "9") (pinfunction "PC1_9") (pintype "bidirectional"))
      (node (ref "PIXEL_71") (pin "6") (pinfunction "SDI_6") (pintype "bidirectional"))
    )
    (net (code "654") (name "SPI3_MOSI") (class "Default")
      (node (ref "CONN_STH_BRD_1") (pin "19") (pinfunction "19_19") (pintype "passive"))
      (node (ref "CONN_STH_BRD_2") (pin "19") (pinfunction "19_19") (pintype "passive"))
      (node (ref "F446") (pin "26") (pinfunction "PB0_26") (pintype "bidirectional"))
      (node (ref "PIXEL_51") (pin "6") (pinfunction "SDI_6") (pintype "bidirectional"))
    )
    (net (code "655") (name "SWCLK") (class "Default")
      (node (ref "F446") (pin "49") (pinfunction "PA14_49") (pintype "bidirectional"))
      (node (ref "STLINK") (pin "4") (pinfunction "4_4") (pintype "passive"))
    )
    (net (code "656") (name "SWDIO") (class "Default")
      (node (ref "F446") (pin "46") (pinfunction "PA13_46") (pintype "bidirectional"))
      (node (ref "STLINK") (pin "2") (pinfunction "2_2") (pintype "passive"))
    )
    (net (code "657") (name "TIM3_CH1") (class "Default")
      (node (ref "F446") (pin "22") (pinfunction "PA6_22") (pintype "bidirectional"))
      (node (ref "R90") (pin "1") (pinfunction "1_1") (pintype "passive"))
    )
    (net (code "658") (name "UART4_RX") (class "Default")
      (node (ref "F446") (pin "52") (pinfunction "PC11_52") (pintype "bidirectional"))
      (node (ref "UART_ANALOG") (pin "2") (pinfunction "2_2") (pintype "passive"))
    )
    (net (code "659") (name "UART4_TX") (class "Default")
      (node (ref "F446") (pin "14") (pinfunction "PA0_14") (pintype "bidirectional"))
      (node (ref "UART_ANALOG") (pin "3") (pinfunction "3_3") (pintype "passive"))
    )
    (net (code "660") (name "USART1_RX") (class "Default")
      (node (ref "F446") (pin "59") (pinfunction "PB7_59") (pintype "bidirectional"))
      (node (ref "UART_DISCO") (pin "2") (pinfunction "2_2") (pintype "passive"))
    )
    (net (code "661") (name "USART1_TX") (class "Default")
      (node (ref "F446") (pin "58") (pinfunction "PB6_58") (pintype "bidirectional"))
      (node (ref "UART_DISCO") (pin "3") (pinfunction "3_3") (pintype "passive"))
    )
    (net (code "662") (name "USART2_RX") (class "Default")
      (node (ref "F446") (pin "17") (pinfunction "PA3_17") (pintype "bidirectional"))
      (node (ref "UART_MIDI") (pin "2") (pinfunction "2_2") (pintype "passive"))
    )
    (net (code "663") (name "USART2_TX") (class "Default")
      (node (ref "F446") (pin "16") (pinfunction "PA2_16") (pintype "bidirectional"))
      (node (ref "UART_MIDI") (pin "3") (pinfunction "3_3") (pintype "passive"))
    )
    (net (code "664") (name "unconnected-(F446-PA5-Pad21)") (class "Default")
      (node (ref "F446") (pin "21") (pinfunction "PA5_21") (pintype "bidirectional"))
    )
    (net (code "665") (name "unconnected-(F446-PA15-Pad50)") (class "Default")
      (node (ref "F446") (pin "50") (pinfunction "PA15_50") (pintype "bidirectional"))
    )
    (net (code "666") (name "unconnected-(F446-PB2-Pad28)") (class "Default")
      (node (ref "F446") (pin "28") (pinfunction "PB2_28") (pintype "bidirectional"))
    )
    (net (code "667") (name "unconnected-(F446-PB4-Pad56)") (class "Default")
      (node (ref "F446") (pin "56") (pinfunction "PB4_56") (pintype "bidirectional"))
    )
    (net (code "668") (name "unconnected-(F446-PB5-Pad57)") (class "Default")
      (node (ref "F446") (pin "57") (pinfunction "PB5_57") (pintype "bidirectional"))
    )
    (net (code "669") (name "unconnected-(F446-PB12-Pad33)") (class "Default")
      (node (ref "F446") (pin "33") (pinfunction "PB12_33") (pintype "bidirectional"))
    )
    (net (code "670") (name "unconnected-(F446-PB13-Pad34)") (class "Default")
      (node (ref "F446") (pin "34") (pinfunction "PB13_34") (pintype "bidirectional"))
    )
    (net (code "671") (name "unconnected-(F446-PC10-Pad51)") (class "Default")
      (node (ref "F446") (pin "51") (pinfunction "PC10_51") (pintype "bidirectional"))
    )
    (net (code "672") (name "unconnected-(F446-PC14-OSC32_IN-Pad3)") (class "Default")
      (node (ref "F446") (pin "3") (pinfunction "PC14-OSC32_IN_3") (pintype "bidirectional"))
    )
    (net (code "673") (name "unconnected-(F446-PC15-OSC32_OUT-Pad4)") (class "Default")
      (node (ref "F446") (pin "4") (pinfunction "PC15-OSC32_OUT_4") (pintype "bidirectional"))
    )
    (net (code "674") (name "unconnected-(F446-PD2-Pad54)") (class "Default")
      (node (ref "F446") (pin "54") (pinfunction "PD2_54") (pintype "bidirectional"))
    )
    (net (code "675") (name "unconnected-(F446-PH1-OSC_OUT-Pad6)") (class "Default")
      (node (ref "F446") (pin "6") (pinfunction "PH1-OSC_OUT_6") (pintype "bidirectional"))
    )
    (net (code "676") (name "unconnected-(MCP_001-GPB0-Pad1)") (class "Default")
      (node (ref "MCP_001") (pin "1") (pinfunction "GPB0_1") (pintype "bidirectional"))
    )
    (net (code "677") (name "unconnected-(PIXEL_01-SDO-Pad5)") (class "Default")
      (node (ref "PIXEL_01") (pin "5") (pinfunction "SDO_5") (pintype "bidirectional"))
    )
    (net (code "678") (name "unconnected-(PIXEL_01-TEST-Pad7)") (class "Default")
      (node (ref "PIXEL_01") (pin "7") (pinfunction "TEST_7") (pintype "bidirectional"))
    )
    (net (code "679") (name "unconnected-(PIXEL_02-TEST-Pad7)") (class "Default")
      (node (ref "PIXEL_02") (pin "7") (pinfunction "TEST_7") (pintype "bidirectional"))
    )
    (net (code "680") (name "unconnected-(PIXEL_03-TEST-Pad7)") (class "Default")
      (node (ref "PIXEL_03") (pin "7") (pinfunction "TEST_7") (pintype "bidirectional"))
    )
    (net (code "681") (name "unconnected-(PIXEL_11-TEST-Pad7)") (class "Default")
      (node (ref "PIXEL_11") (pin "7") (pinfunction "TEST_7") (pintype "bidirectional"))
    )
    (net (code "682") (name "unconnected-(PIXEL_12-TEST-Pad7)") (class "Default")
      (node (ref "PIXEL_12") (pin "7") (pinfunction "TEST_7") (pintype "bidirectional"))
    )
    (net (code "683") (name "unconnected-(PIXEL_13-TEST-Pad7)") (class "Default")
      (node (ref "PIXEL_13") (pin "7") (pinfunction "TEST_7") (pintype "bidirectional"))
    )
    (net (code "684") (name "unconnected-(PIXEL_14-TEST-Pad7)") (class "Default")
      (node (ref "PIXEL_14") (pin "7") (pinfunction "TEST_7") (pintype "bidirectional"))
    )
    (net (code "685") (name "unconnected-(PIXEL_21-TEST-Pad7)") (class "Default")
      (node (ref "PIXEL_21") (pin "7") (pinfunction "TEST_7") (pintype "bidirectional"))
    )
    (net (code "686") (name "unconnected-(PIXEL_22-TEST-Pad7)") (class "Default")
      (node (ref "PIXEL_22") (pin "7") (pinfunction "TEST_7") (pintype "bidirectional"))
    )
    (net (code "687") (name "unconnected-(PIXEL_23-TEST-Pad7)") (class "Default")
      (node (ref "PIXEL_23") (pin "7") (pinfunction "TEST_7") (pintype "bidirectional"))
    )
    (net (code "688") (name "unconnected-(PIXEL_24-TEST-Pad7)") (class "Default")
      (node (ref "PIXEL_24") (pin "7") (pinfunction "TEST_7") (pintype "bidirectional"))
    )
    (net (code "689") (name "unconnected-(PIXEL_31-SDO-Pad5)") (class "Default")
      (node (ref "PIXEL_31") (pin "5") (pinfunction "SDO_5") (pintype "bidirectional"))
    )
    (net (code "690") (name "unconnected-(PIXEL_31-TEST-Pad7)") (class "Default")
      (node (ref "PIXEL_31") (pin "7") (pinfunction "TEST_7") (pintype "bidirectional"))
    )
    (net (code "691") (name "unconnected-(PIXEL_32-TEST-Pad7)") (class "Default")
      (node (ref "PIXEL_32") (pin "7") (pinfunction "TEST_7") (pintype "bidirectional"))
    )
    (net (code "692") (name "unconnected-(PIXEL_33-TEST-Pad7)") (class "Default")
      (node (ref "PIXEL_33") (pin "7") (pinfunction "TEST_7") (pintype "bidirectional"))
    )
    (net (code "693") (name "unconnected-(PIXEL_34-TEST-Pad7)") (class "Default")
      (node (ref "PIXEL_34") (pin "7") (pinfunction "TEST_7") (pintype "bidirectional"))
    )
    (net (code "694") (name "unconnected-(PIXEL_35-TEST-Pad7)") (class "Default")
      (node (ref "PIXEL_35") (pin "7") (pinfunction "TEST_7") (pintype "bidirectional"))
    )
    (net (code "695") (name "unconnected-(PIXEL_41-TEST-Pad7)") (class "Default")
      (node (ref "PIXEL_41") (pin "7") (pinfunction "TEST_7") (pintype "bidirectional"))
    )
    (net (code "696") (name "unconnected-(PIXEL_42-TEST-Pad7)") (class "Default")
      (node (ref "PIXEL_42") (pin "7") (pinfunction "TEST_7") (pintype "bidirectional"))
    )
    (net (code "697") (name "unconnected-(PIXEL_43-TEST-Pad7)") (class "Default")
      (node (ref "PIXEL_43") (pin "7") (pinfunction "TEST_7") (pintype "bidirectional"))
    )
    (net (code "698") (name "unconnected-(PIXEL_44-TEST-Pad7)") (class "Default")
      (node (ref "PIXEL_44") (pin "7") (pinfunction "TEST_7") (pintype "bidirectional"))
    )
    (net (code "699") (name "unconnected-(PIXEL_45-TEST-Pad7)") (class "Default")
      (node (ref "PIXEL_45") (pin "7") (pinfunction "TEST_7") (pintype "bidirectional"))
    )
    (net (code "700") (name "unconnected-(PIXEL_46-TEST-Pad7)") (class "Default")
      (node (ref "PIXEL_46") (pin "7") (pinfunction "TEST_7") (pintype "bidirectional"))
    )
    (net (code "701") (name "unconnected-(PIXEL_47-TEST-Pad7)") (class "Default")
      (node (ref "PIXEL_47") (pin "7") (pinfunction "TEST_7") (pintype "bidirectional"))
    )
    (net (code "702") (name "unconnected-(PIXEL_48-TEST-Pad7)") (class "Default")
      (node (ref "PIXEL_48") (pin "7") (pinfunction "TEST_7") (pintype "bidirectional"))
    )
    (net (code "703") (name "unconnected-(PIXEL_51-TEST-Pad7)") (class "Default")
      (node (ref "PIXEL_51") (pin "7") (pinfunction "TEST_7") (pintype "bidirectional"))
    )
    (net (code "704") (name "unconnected-(PIXEL_52-TEST-Pad7)") (class "Default")
      (node (ref "PIXEL_52") (pin "7") (pinfunction "TEST_7") (pintype "bidirectional"))
    )
    (net (code "705") (name "unconnected-(PIXEL_53-TEST-Pad7)") (class "Default")
      (node (ref "PIXEL_53") (pin "7") (pinfunction "TEST_7") (pintype "bidirectional"))
    )
    (net (code "706") (name "unconnected-(PIXEL_54-TEST-Pad7)") (class "Default")
      (node (ref "PIXEL_54") (pin "7") (pinfunction "TEST_7") (pintype "bidirectional"))
    )
    (net (code "707") (name "unconnected-(PIXEL_55-TEST-Pad7)") (class "Default")
      (node (ref "PIXEL_55") (pin "7") (pinfunction "TEST_7") (pintype "bidirectional"))
    )
    (net (code "708") (name "unconnected-(PIXEL_56-TEST-Pad7)") (class "Default")
      (node (ref "PIXEL_56") (pin "7") (pinfunction "TEST_7") (pintype "bidirectional"))
    )
    (net (code "709") (name "unconnected-(PIXEL_57-TEST-Pad7)") (class "Default")
      (node (ref "PIXEL_57") (pin "7") (pinfunction "TEST_7") (pintype "bidirectional"))
    )
    (net (code "710") (name "unconnected-(PIXEL_61-TEST-Pad7)") (class "Default")
      (node (ref "PIXEL_61") (pin "7") (pinfunction "TEST_7") (pintype "bidirectional"))
    )
    (net (code "711") (name "unconnected-(PIXEL_62-TEST-Pad7)") (class "Default")
      (node (ref "PIXEL_62") (pin "7") (pinfunction "TEST_7") (pintype "bidirectional"))
    )
    (net (code "712") (name "unconnected-(PIXEL_63-TEST-Pad7)") (class "Default")
      (node (ref "PIXEL_63") (pin "7") (pinfunction "TEST_7") (pintype "bidirectional"))
    )
    (net (code "713") (name "unconnected-(PIXEL_64-TEST-Pad7)") (class "Default")
      (node (ref "PIXEL_64") (pin "7") (pinfunction "TEST_7") (pintype "bidirectional"))
    )
    (net (code "714") (name "unconnected-(PIXEL_65-SDO-Pad5)") (class "Default")
      (node (ref "PIXEL_65") (pin "5") (pinfunction "SDO_5") (pintype "bidirectional"))
    )
    (net (code "715") (name "unconnected-(PIXEL_65-TEST-Pad7)") (class "Default")
      (node (ref "PIXEL_65") (pin "7") (pinfunction "TEST_7") (pintype "bidirectional"))
    )
    (net (code "716") (name "unconnected-(PIXEL_71-TEST-Pad7)") (class "Default")
      (node (ref "PIXEL_71") (pin "7") (pinfunction "TEST_7") (pintype "bidirectional"))
    )
    (net (code "717") (name "unconnected-(PIXEL_72-TEST-Pad7)") (class "Default")
      (node (ref "PIXEL_72") (pin "7") (pinfunction "TEST_7") (pintype "bidirectional"))
    )
    (net (code "718") (name "unconnected-(PIXEL_73-TEST-Pad7)") (class "Default")
      (node (ref "PIXEL_73") (pin "7") (pinfunction "TEST_7") (pintype "bidirectional"))
    )
    (net (code "719") (name "unconnected-(PIXEL_74-TEST-Pad7)") (class "Default")
      (node (ref "PIXEL_74") (pin "7") (pinfunction "TEST_7") (pintype "bidirectional"))
    )
    (net (code "720") (name "unconnected-(PIXEL_75-TEST-Pad7)") (class "Default")
      (node (ref "PIXEL_75") (pin "7") (pinfunction "TEST_7") (pintype "bidirectional"))
    )
    (net (code "721") (name "unconnected-(PIXEL_81-TEST-Pad7)") (class "Default")
      (node (ref "PIXEL_81") (pin "7") (pinfunction "TEST_7") (pintype "bidirectional"))
    )
    (net (code "722") (name "unconnected-(PIXEL_83-TEST-Pad7)") (class "Default")
      (node (ref "PIXEL_83") (pin "7") (pinfunction "TEST_7") (pintype "bidirectional"))
    )
    (net (code "723") (name "unconnected-(PIXEL_84-TEST-Pad7)") (class "Default")
      (node (ref "PIXEL_84") (pin "7") (pinfunction "TEST_7") (pintype "bidirectional"))
    )
    (net (code "724") (name "unconnected-(PIXEL_85-TEST-Pad7)") (class "Default")
      (node (ref "PIXEL_85") (pin "7") (pinfunction "TEST_7") (pintype "bidirectional"))
    )
    (net (code "725") (name "unconnected-(PIXEL_86-TEST-Pad7)") (class "Default")
      (node (ref "PIXEL_86") (pin "7") (pinfunction "TEST_7") (pintype "bidirectional"))
    )
    (net (code "726") (name "unconnected-(PIXEL_87-TEST-Pad7)") (class "Default")
      (node (ref "PIXEL_87") (pin "7") (pinfunction "TEST_7") (pintype "bidirectional"))
    )
    (net (code "727") (name "unconnected-(PIXEL_88-TEST-Pad7)") (class "Default")
      (node (ref "PIXEL_88") (pin "7") (pinfunction "TEST_7") (pintype "bidirectional"))
    )
    (net (code "728") (name "unconnected-(PIXE_82-TEST-Pad7)") (class "Default")
      (node (ref "PIXE_82") (pin "7") (pinfunction "TEST_7") (pintype "bidirectional"))
    )
    (net (code "729") (name "unconnected-(STLINK-Pad6)") (class "Default")
      (node (ref "STLINK") (pin "6") (pinfunction "6_6") (pintype "passive"))
    )
  )
)
